# 9-de-8.net
KiCad netlist of a schematic drawn in EAGLE
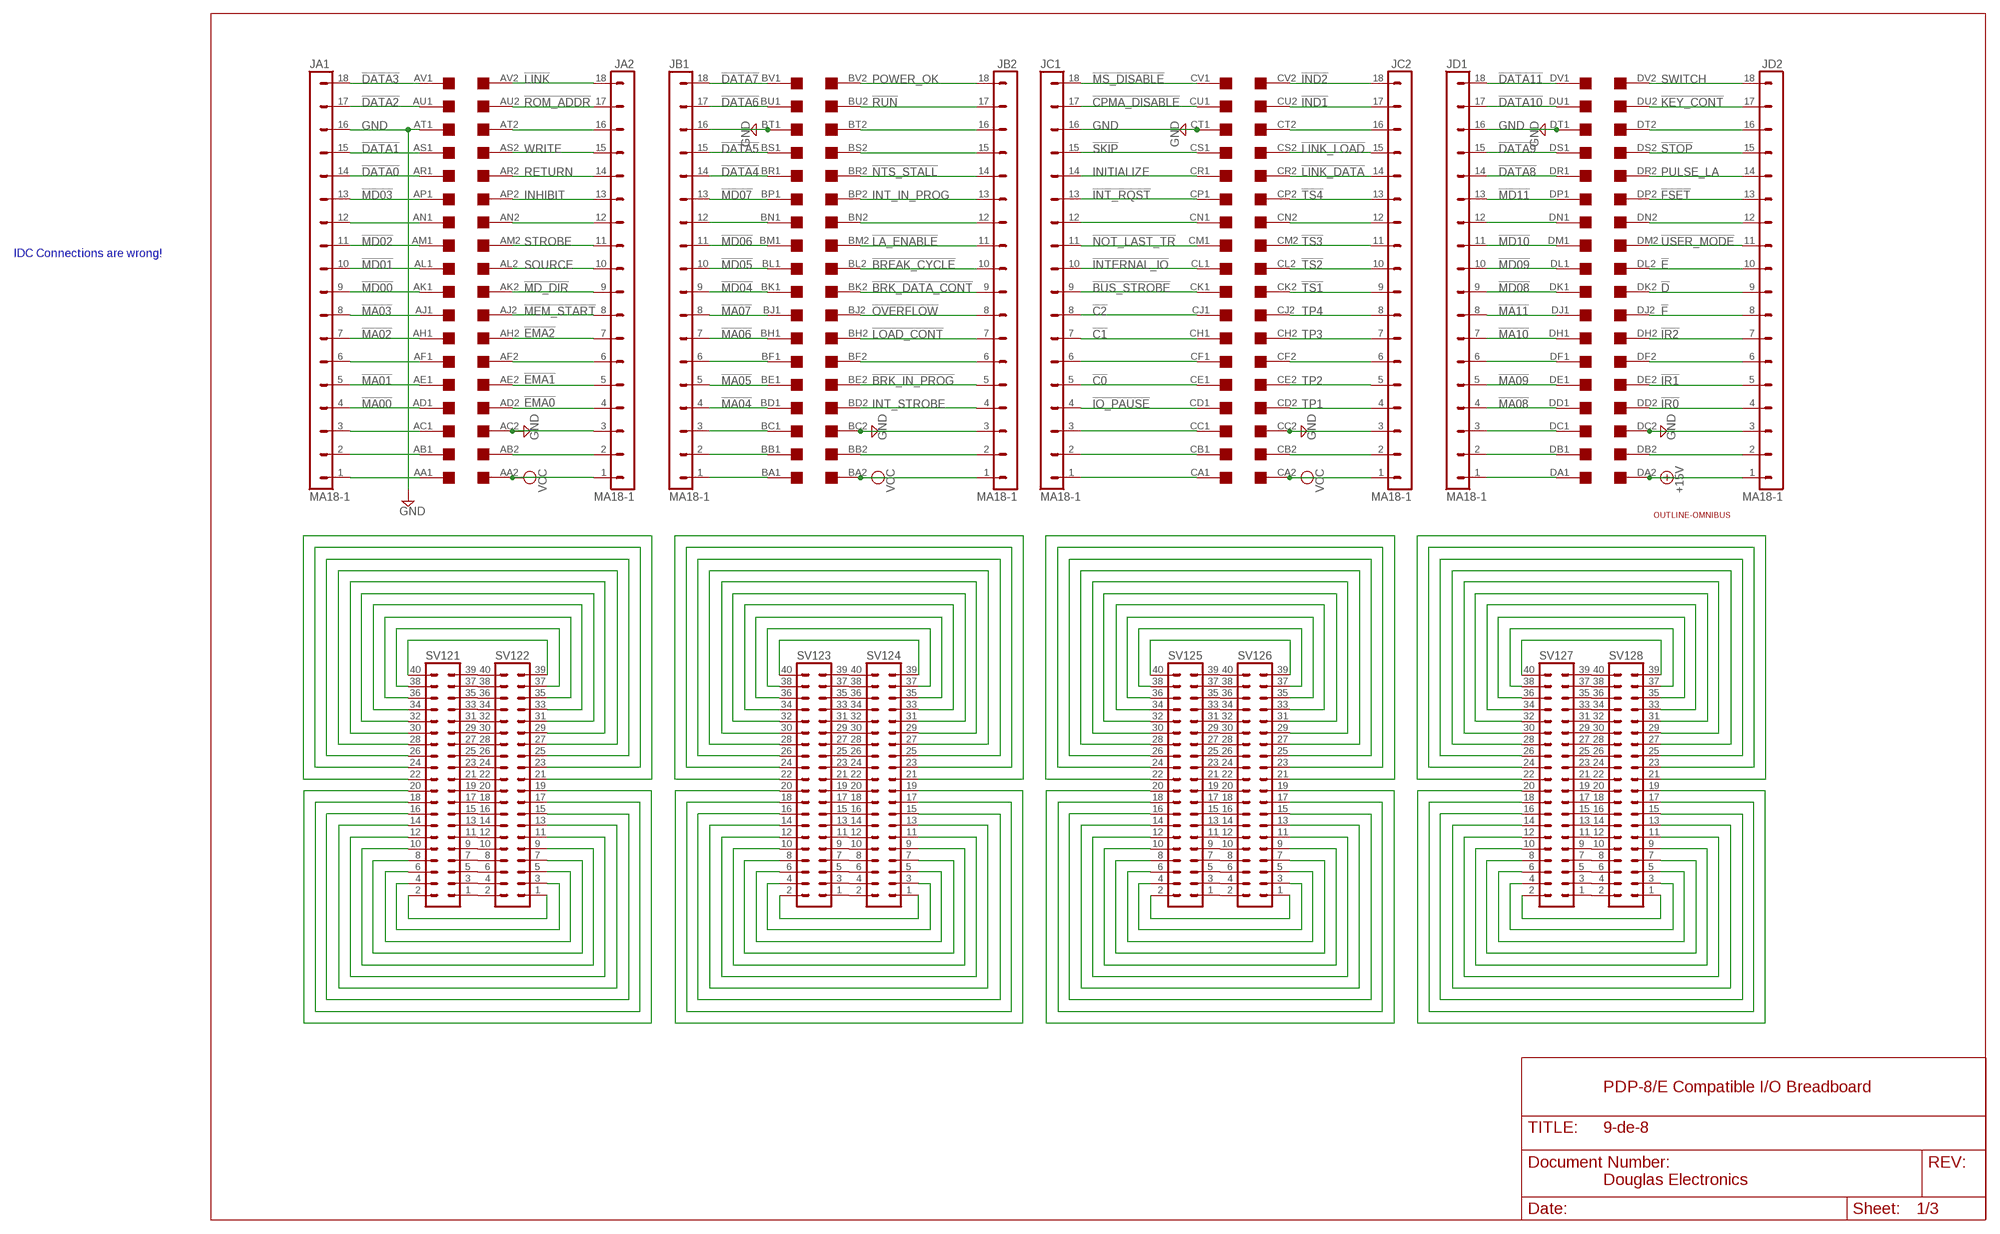
[diagram p0: schematic, sheet 1]
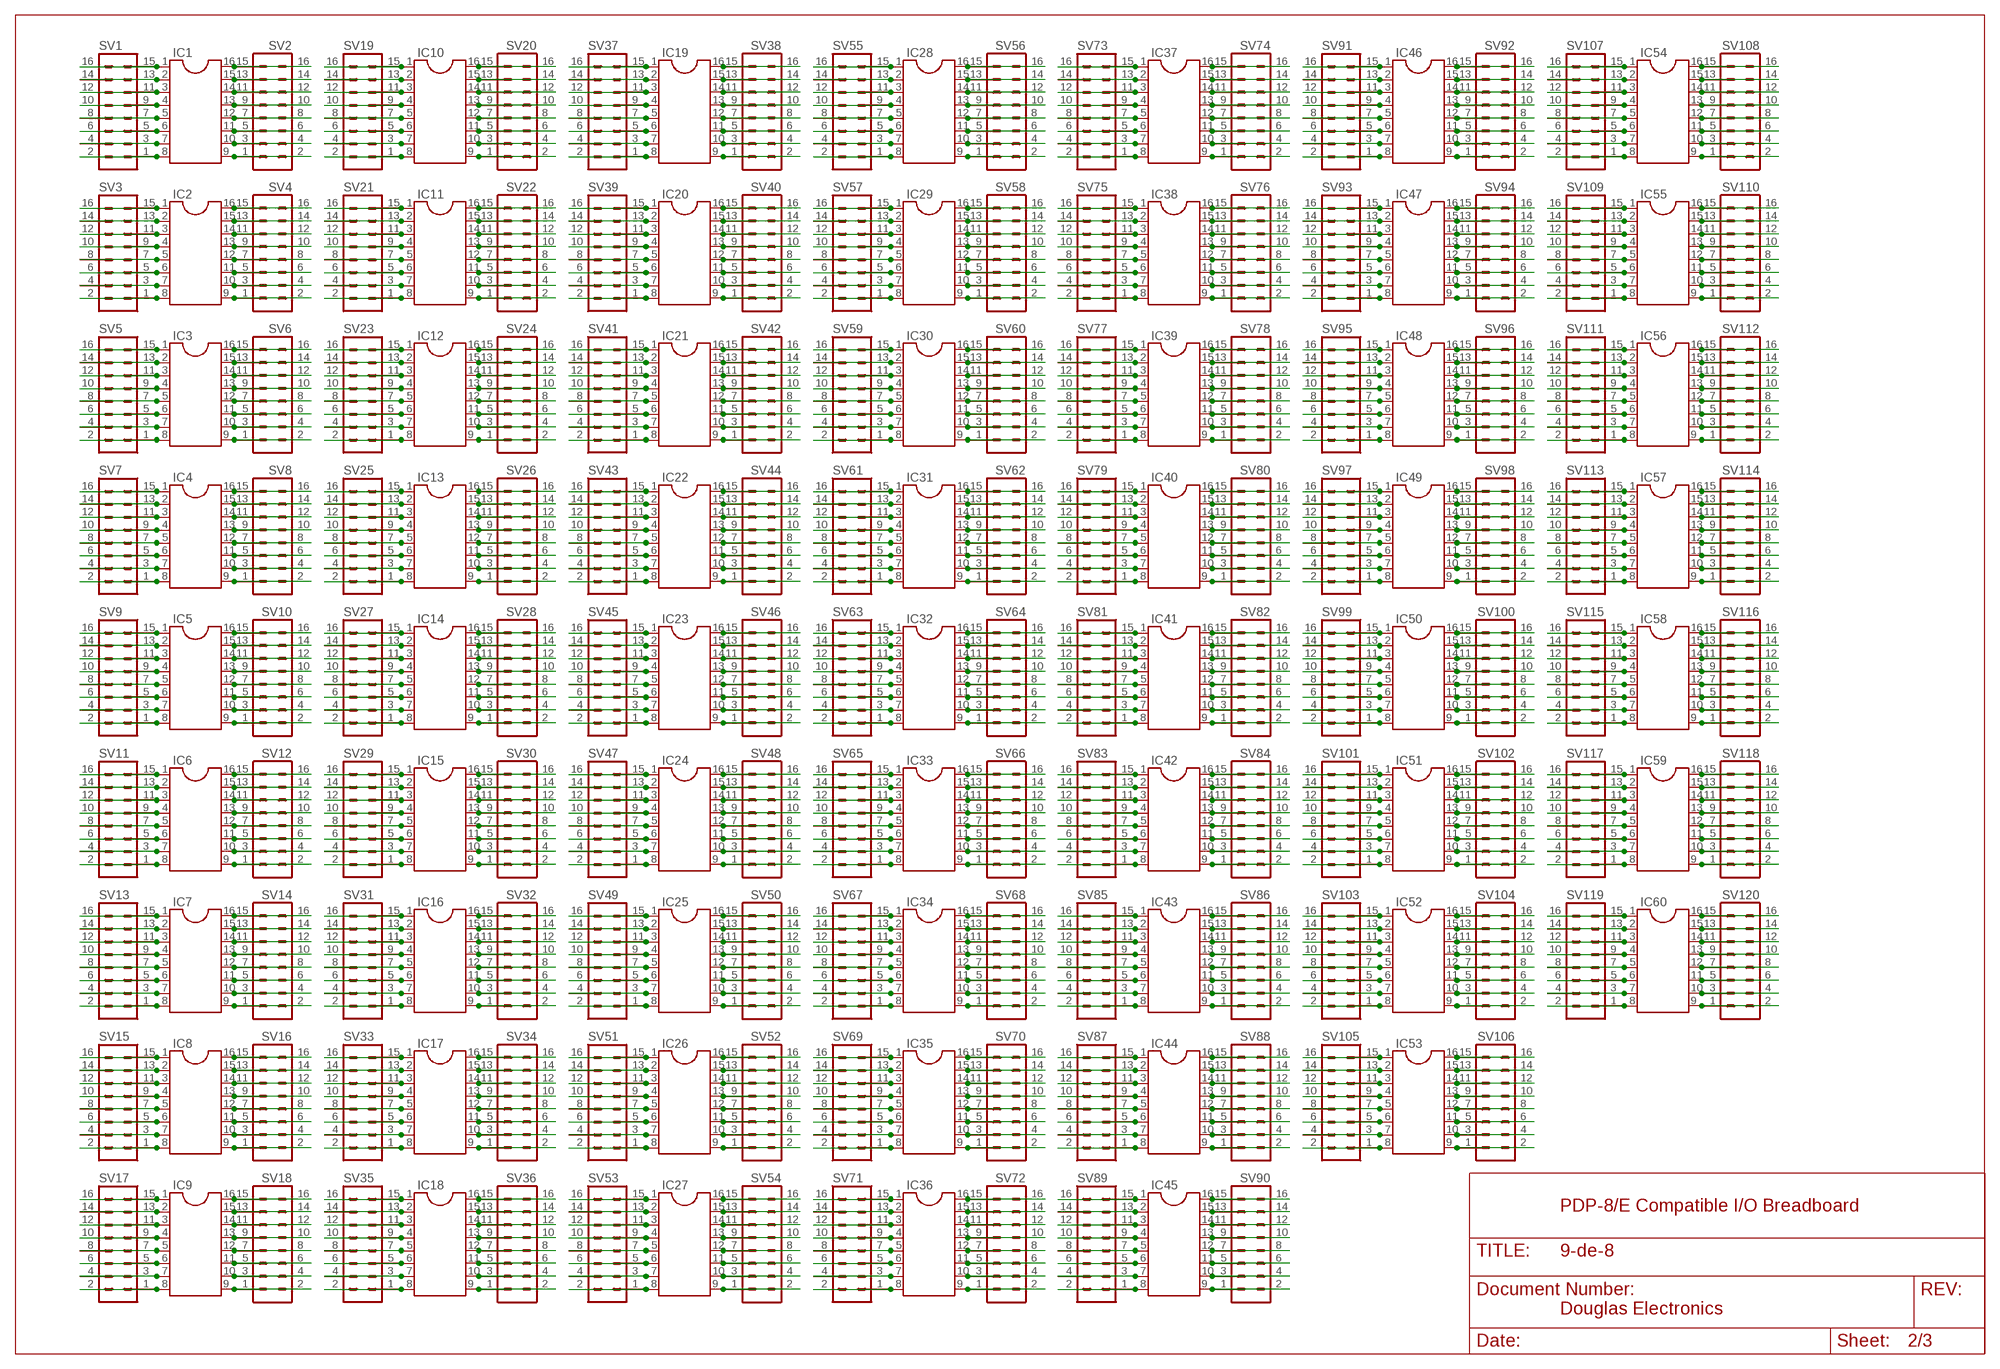
[diagram p1: schematic, sheet 2]
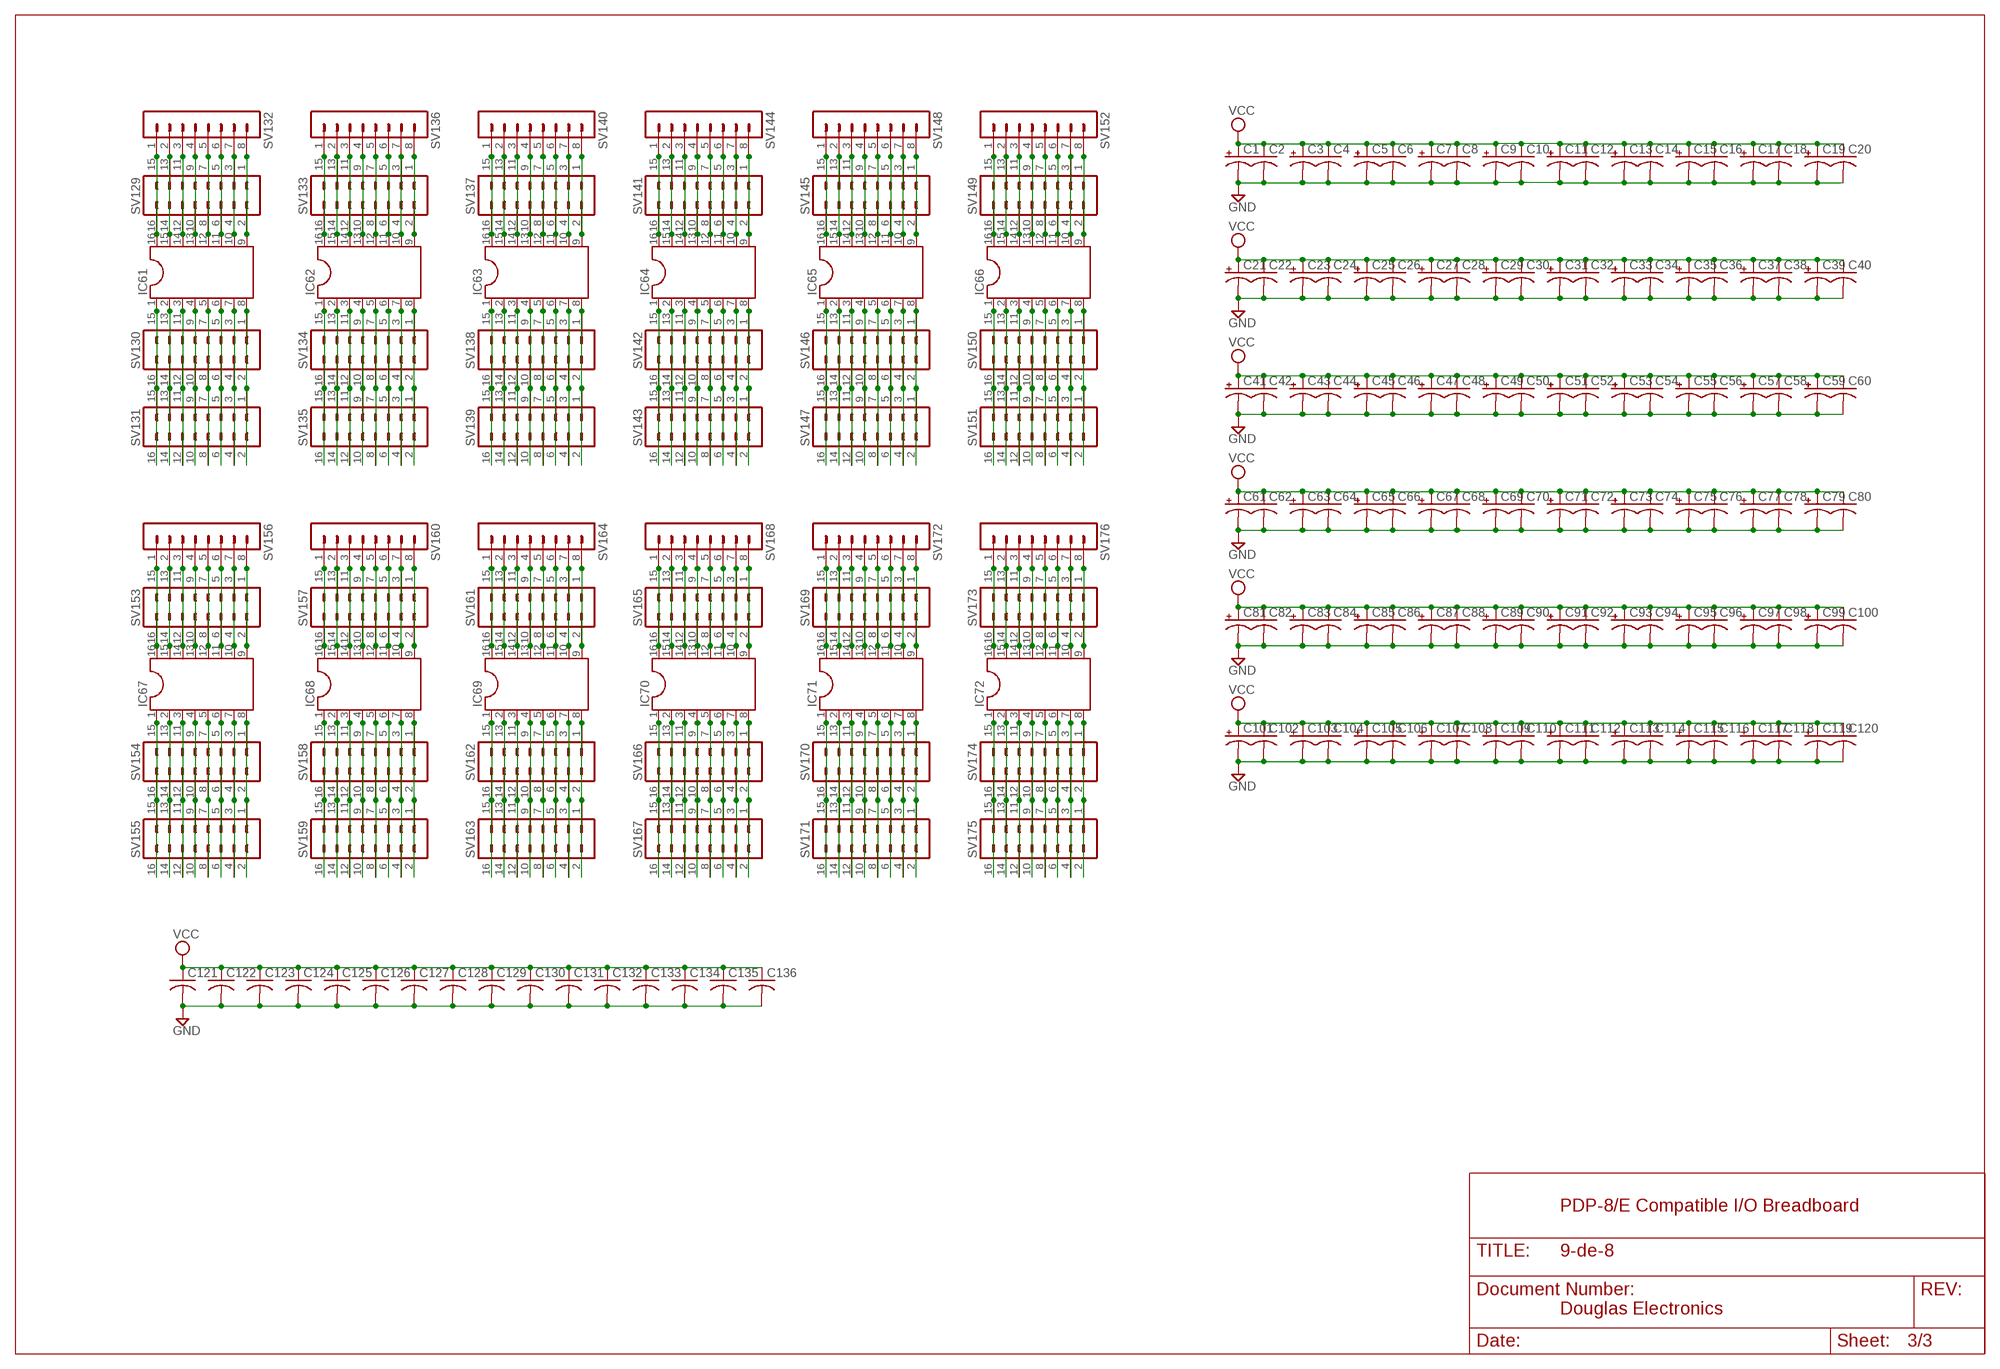
[diagram p2: schematic, sheet 3]

(export (version "E")
  (design (tool "Eeschema 10.0.6"))
  (components
    (comp (ref "JA1")
      (value "MA18-1")
      (footprint "eagle-import:MA18-1")
      (libsource (lib "eagle-import") (part "MA18-1"))
    )
    (comp (ref "JA2")
      (value "MA18-1")
      (footprint "eagle-import:MA18-1")
      (libsource (lib "eagle-import") (part "MA18-1"))
    )
    (comp (ref "JB1")
      (value "MA18-1")
      (footprint "eagle-import:MA18-1")
      (libsource (lib "eagle-import") (part "MA18-1"))
    )
    (comp (ref "JB2")
      (value "MA18-1")
      (footprint "eagle-import:MA18-1")
      (libsource (lib "eagle-import") (part "MA18-1"))
    )
    (comp (ref "JC1")
      (value "MA18-1")
      (footprint "eagle-import:MA18-1")
      (libsource (lib "eagle-import") (part "MA18-1"))
    )
    (comp (ref "JC2")
      (value "MA18-1")
      (footprint "eagle-import:MA18-1")
      (libsource (lib "eagle-import") (part "MA18-1"))
    )
    (comp (ref "JD1")
      (value "MA18-1")
      (footprint "eagle-import:MA18-1")
      (libsource (lib "eagle-import") (part "MA18-1"))
    )
    (comp (ref "JD2")
      (value "MA18-1")
      (footprint "eagle-import:MA18-1")
      (libsource (lib "eagle-import") (part "MA18-1"))
    )
    (comp (ref "SV121")
      (value "MA20-2")
      (footprint "eagle-import:MA20-2")
      (libsource (lib "eagle-import") (part "MA20-2"))
    )
    (comp (ref "SV122")
      (value "MA20-2")
      (footprint "eagle-import:MA20-2")
      (libsource (lib "eagle-import") (part "MA20-2"))
    )
    (comp (ref "SV123")
      (value "MA20-2")
      (footprint "eagle-import:MA20-2")
      (libsource (lib "eagle-import") (part "MA20-2"))
    )
    (comp (ref "SV124")
      (value "MA20-2")
      (footprint "eagle-import:MA20-2")
      (libsource (lib "eagle-import") (part "MA20-2"))
    )
    (comp (ref "SV125")
      (value "MA20-2")
      (footprint "eagle-import:MA20-2")
      (libsource (lib "eagle-import") (part "MA20-2"))
    )
    (comp (ref "SV126")
      (value "MA20-2")
      (footprint "eagle-import:MA20-2")
      (libsource (lib "eagle-import") (part "MA20-2"))
    )
    (comp (ref "SV127")
      (value "MA20-2")
      (footprint "eagle-import:MA20-2")
      (libsource (lib "eagle-import") (part "MA20-2"))
    )
    (comp (ref "SV128")
      (value "MA20-2")
      (footprint "eagle-import:MA20-2")
      (libsource (lib "eagle-import") (part "MA20-2"))
    )
    (comp (ref "U$1")
      (value "OUTLINE-OMNIBUS")
      (footprint "eagle-import:OMNIBUS")
      (libsource (lib "eagle-import") (part "OUTLINE-OMNIBUS"))
    )
    (comp (ref "U$2")
      (value "QUAD")
      (footprint "eagle-import:EDGE-CON8")
      (libsource (lib "eagle-import") (part "QUAD"))
    )
    (comp (ref "IC1")
      (value "DIL16")
      (footprint "eagle-import:DIL16")
      (libsource (lib "eagle-import") (part "DIL16"))
    )
    (comp (ref "IC2")
      (value "DIL16")
      (footprint "eagle-import:DIL16")
      (libsource (lib "eagle-import") (part "DIL16"))
    )
    (comp (ref "IC3")
      (value "DIL16")
      (footprint "eagle-import:DIL16")
      (libsource (lib "eagle-import") (part "DIL16"))
    )
    (comp (ref "IC4")
      (value "DIL16")
      (footprint "eagle-import:DIL16")
      (libsource (lib "eagle-import") (part "DIL16"))
    )
    (comp (ref "IC5")
      (value "DIL16")
      (footprint "eagle-import:DIL16")
      (libsource (lib "eagle-import") (part "DIL16"))
    )
    (comp (ref "IC6")
      (value "DIL16")
      (footprint "eagle-import:DIL16")
      (libsource (lib "eagle-import") (part "DIL16"))
    )
    (comp (ref "IC7")
      (value "DIL16")
      (footprint "eagle-import:DIL16")
      (libsource (lib "eagle-import") (part "DIL16"))
    )
    (comp (ref "IC8")
      (value "DIL16")
      (footprint "eagle-import:DIL16")
      (libsource (lib "eagle-import") (part "DIL16"))
    )
    (comp (ref "IC9")
      (value "DIL16")
      (footprint "eagle-import:DIL16")
      (libsource (lib "eagle-import") (part "DIL16"))
    )
    (comp (ref "IC10")
      (value "DIL16")
      (footprint "eagle-import:DIL16")
      (libsource (lib "eagle-import") (part "DIL16"))
    )
    (comp (ref "IC11")
      (value "DIL16")
      (footprint "eagle-import:DIL16")
      (libsource (lib "eagle-import") (part "DIL16"))
    )
    (comp (ref "IC12")
      (value "DIL16")
      (footprint "eagle-import:DIL16")
      (libsource (lib "eagle-import") (part "DIL16"))
    )
    (comp (ref "IC13")
      (value "DIL16")
      (footprint "eagle-import:DIL16")
      (libsource (lib "eagle-import") (part "DIL16"))
    )
    (comp (ref "IC14")
      (value "DIL16")
      (footprint "eagle-import:DIL16")
      (libsource (lib "eagle-import") (part "DIL16"))
    )
    (comp (ref "IC15")
      (value "DIL16")
      (footprint "eagle-import:DIL16")
      (libsource (lib "eagle-import") (part "DIL16"))
    )
    (comp (ref "IC16")
      (value "DIL16")
      (footprint "eagle-import:DIL16")
      (libsource (lib "eagle-import") (part "DIL16"))
    )
    (comp (ref "IC17")
      (value "DIL16")
      (footprint "eagle-import:DIL16")
      (libsource (lib "eagle-import") (part "DIL16"))
    )
    (comp (ref "IC18")
      (value "DIL16")
      (footprint "eagle-import:DIL16")
      (libsource (lib "eagle-import") (part "DIL16"))
    )
    (comp (ref "IC19")
      (value "DIL16")
      (footprint "eagle-import:DIL16")
      (libsource (lib "eagle-import") (part "DIL16"))
    )
    (comp (ref "IC20")
      (value "DIL16")
      (footprint "eagle-import:DIL16")
      (libsource (lib "eagle-import") (part "DIL16"))
    )
    (comp (ref "IC21")
      (value "DIL16")
      (footprint "eagle-import:DIL16")
      (libsource (lib "eagle-import") (part "DIL16"))
    )
    (comp (ref "IC22")
      (value "DIL16")
      (footprint "eagle-import:DIL16")
      (libsource (lib "eagle-import") (part "DIL16"))
    )
    (comp (ref "IC23")
      (value "DIL16")
      (footprint "eagle-import:DIL16")
      (libsource (lib "eagle-import") (part "DIL16"))
    )
    (comp (ref "IC24")
      (value "DIL16")
      (footprint "eagle-import:DIL16")
      (libsource (lib "eagle-import") (part "DIL16"))
    )
    (comp (ref "IC25")
      (value "DIL16")
      (footprint "eagle-import:DIL16")
      (libsource (lib "eagle-import") (part "DIL16"))
    )
    (comp (ref "IC26")
      (value "DIL16")
      (footprint "eagle-import:DIL16")
      (libsource (lib "eagle-import") (part "DIL16"))
    )
    (comp (ref "IC27")
      (value "DIL16")
      (footprint "eagle-import:DIL16")
      (libsource (lib "eagle-import") (part "DIL16"))
    )
    (comp (ref "IC28")
      (value "DIL16")
      (footprint "eagle-import:DIL16")
      (libsource (lib "eagle-import") (part "DIL16"))
    )
    (comp (ref "IC29")
      (value "DIL16")
      (footprint "eagle-import:DIL16")
      (libsource (lib "eagle-import") (part "DIL16"))
    )
    (comp (ref "IC30")
      (value "DIL16")
      (footprint "eagle-import:DIL16")
      (libsource (lib "eagle-import") (part "DIL16"))
    )
    (comp (ref "IC31")
      (value "DIL16")
      (footprint "eagle-import:DIL16")
      (libsource (lib "eagle-import") (part "DIL16"))
    )
    (comp (ref "IC32")
      (value "DIL16")
      (footprint "eagle-import:DIL16")
      (libsource (lib "eagle-import") (part "DIL16"))
    )
    (comp (ref "IC33")
      (value "DIL16")
      (footprint "eagle-import:DIL16")
      (libsource (lib "eagle-import") (part "DIL16"))
    )
    (comp (ref "IC34")
      (value "DIL16")
      (footprint "eagle-import:DIL16")
      (libsource (lib "eagle-import") (part "DIL16"))
    )
    (comp (ref "IC35")
      (value "DIL16")
      (footprint "eagle-import:DIL16")
      (libsource (lib "eagle-import") (part "DIL16"))
    )
    (comp (ref "IC36")
      (value "DIL16")
      (footprint "eagle-import:DIL16")
      (libsource (lib "eagle-import") (part "DIL16"))
    )
    (comp (ref "IC37")
      (value "DIL16")
      (footprint "eagle-import:DIL16")
      (libsource (lib "eagle-import") (part "DIL16"))
    )
    (comp (ref "IC38")
      (value "DIL16")
      (footprint "eagle-import:DIL16")
      (libsource (lib "eagle-import") (part "DIL16"))
    )
    (comp (ref "IC39")
      (value "DIL16")
      (footprint "eagle-import:DIL16")
      (libsource (lib "eagle-import") (part "DIL16"))
    )
    (comp (ref "IC40")
      (value "DIL16")
      (footprint "eagle-import:DIL16")
      (libsource (lib "eagle-import") (part "DIL16"))
    )
    (comp (ref "IC41")
      (value "DIL16")
      (footprint "eagle-import:DIL16")
      (libsource (lib "eagle-import") (part "DIL16"))
    )
    (comp (ref "IC42")
      (value "DIL16")
      (footprint "eagle-import:DIL16")
      (libsource (lib "eagle-import") (part "DIL16"))
    )
    (comp (ref "IC43")
      (value "DIL16")
      (footprint "eagle-import:DIL16")
      (libsource (lib "eagle-import") (part "DIL16"))
    )
    (comp (ref "IC44")
      (value "DIL16")
      (footprint "eagle-import:DIL16")
      (libsource (lib "eagle-import") (part "DIL16"))
    )
    (comp (ref "IC45")
      (value "DIL16")
      (footprint "eagle-import:DIL16")
      (libsource (lib "eagle-import") (part "DIL16"))
    )
    (comp (ref "IC46")
      (value "DIL16")
      (footprint "eagle-import:DIL16")
      (libsource (lib "eagle-import") (part "DIL16"))
    )
    (comp (ref "IC47")
      (value "DIL16")
      (footprint "eagle-import:DIL16")
      (libsource (lib "eagle-import") (part "DIL16"))
    )
    (comp (ref "IC48")
      (value "DIL16")
      (footprint "eagle-import:DIL16")
      (libsource (lib "eagle-import") (part "DIL16"))
    )
    (comp (ref "IC49")
      (value "DIL16")
      (footprint "eagle-import:DIL16")
      (libsource (lib "eagle-import") (part "DIL16"))
    )
    (comp (ref "IC50")
      (value "DIL16")
      (footprint "eagle-import:DIL16")
      (libsource (lib "eagle-import") (part "DIL16"))
    )
    (comp (ref "IC51")
      (value "DIL16")
      (footprint "eagle-import:DIL16")
      (libsource (lib "eagle-import") (part "DIL16"))
    )
    (comp (ref "IC52")
      (value "DIL16")
      (footprint "eagle-import:DIL16")
      (libsource (lib "eagle-import") (part "DIL16"))
    )
    (comp (ref "IC53")
      (value "DIL16")
      (footprint "eagle-import:DIL16")
      (libsource (lib "eagle-import") (part "DIL16"))
    )
    (comp (ref "IC54")
      (value "DIL16")
      (footprint "eagle-import:DIL16")
      (libsource (lib "eagle-import") (part "DIL16"))
    )
    (comp (ref "IC55")
      (value "DIL16")
      (footprint "eagle-import:DIL16")
      (libsource (lib "eagle-import") (part "DIL16"))
    )
    (comp (ref "IC56")
      (value "DIL16")
      (footprint "eagle-import:DIL16")
      (libsource (lib "eagle-import") (part "DIL16"))
    )
    (comp (ref "IC57")
      (value "DIL16")
      (footprint "eagle-import:DIL16")
      (libsource (lib "eagle-import") (part "DIL16"))
    )
    (comp (ref "IC58")
      (value "DIL16")
      (footprint "eagle-import:DIL16")
      (libsource (lib "eagle-import") (part "DIL16"))
    )
    (comp (ref "IC59")
      (value "DIL16")
      (footprint "eagle-import:DIL16")
      (libsource (lib "eagle-import") (part "DIL16"))
    )
    (comp (ref "IC60")
      (value "DIL16")
      (footprint "eagle-import:DIL16")
      (libsource (lib "eagle-import") (part "DIL16"))
    )
    (comp (ref "SV1")
      (value "MA08-2")
      (footprint "eagle-import:MA08-2")
      (libsource (lib "eagle-import") (part "MA08-2"))
    )
    (comp (ref "SV2")
      (value "MA08-2")
      (footprint "eagle-import:MA08-2")
      (libsource (lib "eagle-import") (part "MA08-2"))
    )
    (comp (ref "SV3")
      (value "MA08-2")
      (footprint "eagle-import:MA08-2")
      (libsource (lib "eagle-import") (part "MA08-2"))
    )
    (comp (ref "SV4")
      (value "MA08-2")
      (footprint "eagle-import:MA08-2")
      (libsource (lib "eagle-import") (part "MA08-2"))
    )
    (comp (ref "SV5")
      (value "MA08-2")
      (footprint "eagle-import:MA08-2")
      (libsource (lib "eagle-import") (part "MA08-2"))
    )
    (comp (ref "SV6")
      (value "MA08-2")
      (footprint "eagle-import:MA08-2")
      (libsource (lib "eagle-import") (part "MA08-2"))
    )
    (comp (ref "SV7")
      (value "MA08-2")
      (footprint "eagle-import:MA08-2")
      (libsource (lib "eagle-import") (part "MA08-2"))
    )
    (comp (ref "SV8")
      (value "MA08-2")
      (footprint "eagle-import:MA08-2")
      (libsource (lib "eagle-import") (part "MA08-2"))
    )
    (comp (ref "SV9")
      (value "MA08-2")
      (footprint "eagle-import:MA08-2")
      (libsource (lib "eagle-import") (part "MA08-2"))
    )
    (comp (ref "SV10")
      (value "MA08-2")
      (footprint "eagle-import:MA08-2")
      (libsource (lib "eagle-import") (part "MA08-2"))
    )
    (comp (ref "SV11")
      (value "MA08-2")
      (footprint "eagle-import:MA08-2")
      (libsource (lib "eagle-import") (part "MA08-2"))
    )
    (comp (ref "SV12")
      (value "MA08-2")
      (footprint "eagle-import:MA08-2")
      (libsource (lib "eagle-import") (part "MA08-2"))
    )
    (comp (ref "SV13")
      (value "MA08-2")
      (footprint "eagle-import:MA08-2")
      (libsource (lib "eagle-import") (part "MA08-2"))
    )
    (comp (ref "SV14")
      (value "MA08-2")
      (footprint "eagle-import:MA08-2")
      (libsource (lib "eagle-import") (part "MA08-2"))
    )
    (comp (ref "SV15")
      (value "MA08-2")
      (footprint "eagle-import:MA08-2")
      (libsource (lib "eagle-import") (part "MA08-2"))
    )
    (comp (ref "SV16")
      (value "MA08-2")
      (footprint "eagle-import:MA08-2")
      (libsource (lib "eagle-import") (part "MA08-2"))
    )
    (comp (ref "SV17")
      (value "MA08-2")
      (footprint "eagle-import:MA08-2")
      (libsource (lib "eagle-import") (part "MA08-2"))
    )
    (comp (ref "SV18")
      (value "MA08-2")
      (footprint "eagle-import:MA08-2")
      (libsource (lib "eagle-import") (part "MA08-2"))
    )
    (comp (ref "SV19")
      (value "MA08-2")
      (footprint "eagle-import:MA08-2")
      (libsource (lib "eagle-import") (part "MA08-2"))
    )
    (comp (ref "SV20")
      (value "MA08-2")
      (footprint "eagle-import:MA08-2")
      (libsource (lib "eagle-import") (part "MA08-2"))
    )
    (comp (ref "SV21")
      (value "MA08-2")
      (footprint "eagle-import:MA08-2")
      (libsource (lib "eagle-import") (part "MA08-2"))
    )
    (comp (ref "SV22")
      (value "MA08-2")
      (footprint "eagle-import:MA08-2")
      (libsource (lib "eagle-import") (part "MA08-2"))
    )
    (comp (ref "SV23")
      (value "MA08-2")
      (footprint "eagle-import:MA08-2")
      (libsource (lib "eagle-import") (part "MA08-2"))
    )
    (comp (ref "SV24")
      (value "MA08-2")
      (footprint "eagle-import:MA08-2")
      (libsource (lib "eagle-import") (part "MA08-2"))
    )
    (comp (ref "SV25")
      (value "MA08-2")
      (footprint "eagle-import:MA08-2")
      (libsource (lib "eagle-import") (part "MA08-2"))
    )
    (comp (ref "SV26")
      (value "MA08-2")
      (footprint "eagle-import:MA08-2")
      (libsource (lib "eagle-import") (part "MA08-2"))
    )
    (comp (ref "SV27")
      (value "MA08-2")
      (footprint "eagle-import:MA08-2")
      (libsource (lib "eagle-import") (part "MA08-2"))
    )
    (comp (ref "SV28")
      (value "MA08-2")
      (footprint "eagle-import:MA08-2")
      (libsource (lib "eagle-import") (part "MA08-2"))
    )
    (comp (ref "SV29")
      (value "MA08-2")
      (footprint "eagle-import:MA08-2")
      (libsource (lib "eagle-import") (part "MA08-2"))
    )
    (comp (ref "SV30")
      (value "MA08-2")
      (footprint "eagle-import:MA08-2")
      (libsource (lib "eagle-import") (part "MA08-2"))
    )
    (comp (ref "SV31")
      (value "MA08-2")
      (footprint "eagle-import:MA08-2")
      (libsource (lib "eagle-import") (part "MA08-2"))
    )
    (comp (ref "SV32")
      (value "MA08-2")
      (footprint "eagle-import:MA08-2")
      (libsource (lib "eagle-import") (part "MA08-2"))
    )
    (comp (ref "SV33")
      (value "MA08-2")
      (footprint "eagle-import:MA08-2")
      (libsource (lib "eagle-import") (part "MA08-2"))
    )
    (comp (ref "SV34")
      (value "MA08-2")
      (footprint "eagle-import:MA08-2")
      (libsource (lib "eagle-import") (part "MA08-2"))
    )
    (comp (ref "SV35")
      (value "MA08-2")
      (footprint "eagle-import:MA08-2")
      (libsource (lib "eagle-import") (part "MA08-2"))
    )
    (comp (ref "SV36")
      (value "MA08-2")
      (footprint "eagle-import:MA08-2")
      (libsource (lib "eagle-import") (part "MA08-2"))
    )
    (comp (ref "SV37")
      (value "MA08-2")
      (footprint "eagle-import:MA08-2")
      (libsource (lib "eagle-import") (part "MA08-2"))
    )
    (comp (ref "SV38")
      (value "MA08-2")
      (footprint "eagle-import:MA08-2")
      (libsource (lib "eagle-import") (part "MA08-2"))
    )
    (comp (ref "SV39")
      (value "MA08-2")
      (footprint "eagle-import:MA08-2")
      (libsource (lib "eagle-import") (part "MA08-2"))
    )
    (comp (ref "SV40")
      (value "MA08-2")
      (footprint "eagle-import:MA08-2")
      (libsource (lib "eagle-import") (part "MA08-2"))
    )
    (comp (ref "SV41")
      (value "MA08-2")
      (footprint "eagle-import:MA08-2")
      (libsource (lib "eagle-import") (part "MA08-2"))
    )
    (comp (ref "SV42")
      (value "MA08-2")
      (footprint "eagle-import:MA08-2")
      (libsource (lib "eagle-import") (part "MA08-2"))
    )
    (comp (ref "SV43")
      (value "MA08-2")
      (footprint "eagle-import:MA08-2")
      (libsource (lib "eagle-import") (part "MA08-2"))
    )
    (comp (ref "SV44")
      (value "MA08-2")
      (footprint "eagle-import:MA08-2")
      (libsource (lib "eagle-import") (part "MA08-2"))
    )
    (comp (ref "SV45")
      (value "MA08-2")
      (footprint "eagle-import:MA08-2")
      (libsource (lib "eagle-import") (part "MA08-2"))
    )
    (comp (ref "SV46")
      (value "MA08-2")
      (footprint "eagle-import:MA08-2")
      (libsource (lib "eagle-import") (part "MA08-2"))
    )
    (comp (ref "SV47")
      (value "MA08-2")
      (footprint "eagle-import:MA08-2")
      (libsource (lib "eagle-import") (part "MA08-2"))
    )
    (comp (ref "SV48")
      (value "MA08-2")
      (footprint "eagle-import:MA08-2")
      (libsource (lib "eagle-import") (part "MA08-2"))
    )
    (comp (ref "SV49")
      (value "MA08-2")
      (footprint "eagle-import:MA08-2")
      (libsource (lib "eagle-import") (part "MA08-2"))
    )
    (comp (ref "SV50")
      (value "MA08-2")
      (footprint "eagle-import:MA08-2")
      (libsource (lib "eagle-import") (part "MA08-2"))
    )
    (comp (ref "SV51")
      (value "MA08-2")
      (footprint "eagle-import:MA08-2")
      (libsource (lib "eagle-import") (part "MA08-2"))
    )
    (comp (ref "SV52")
      (value "MA08-2")
      (footprint "eagle-import:MA08-2")
      (libsource (lib "eagle-import") (part "MA08-2"))
    )
    (comp (ref "SV53")
      (value "MA08-2")
      (footprint "eagle-import:MA08-2")
      (libsource (lib "eagle-import") (part "MA08-2"))
    )
    (comp (ref "SV54")
      (value "MA08-2")
      (footprint "eagle-import:MA08-2")
      (libsource (lib "eagle-import") (part "MA08-2"))
    )
    (comp (ref "SV55")
      (value "MA08-2")
      (footprint "eagle-import:MA08-2")
      (libsource (lib "eagle-import") (part "MA08-2"))
    )
    (comp (ref "SV56")
      (value "MA08-2")
      (footprint "eagle-import:MA08-2")
      (libsource (lib "eagle-import") (part "MA08-2"))
    )
    (comp (ref "SV57")
      (value "MA08-2")
      (footprint "eagle-import:MA08-2")
      (libsource (lib "eagle-import") (part "MA08-2"))
    )
    (comp (ref "SV58")
      (value "MA08-2")
      (footprint "eagle-import:MA08-2")
      (libsource (lib "eagle-import") (part "MA08-2"))
    )
    (comp (ref "SV59")
      (value "MA08-2")
      (footprint "eagle-import:MA08-2")
      (libsource (lib "eagle-import") (part "MA08-2"))
    )
    (comp (ref "SV60")
      (value "MA08-2")
      (footprint "eagle-import:MA08-2")
      (libsource (lib "eagle-import") (part "MA08-2"))
    )
    (comp (ref "SV61")
      (value "MA08-2")
      (footprint "eagle-import:MA08-2")
      (libsource (lib "eagle-import") (part "MA08-2"))
    )
    (comp (ref "SV62")
      (value "MA08-2")
      (footprint "eagle-import:MA08-2")
      (libsource (lib "eagle-import") (part "MA08-2"))
    )
    (comp (ref "SV63")
      (value "MA08-2")
      (footprint "eagle-import:MA08-2")
      (libsource (lib "eagle-import") (part "MA08-2"))
    )
    (comp (ref "SV64")
      (value "MA08-2")
      (footprint "eagle-import:MA08-2")
      (libsource (lib "eagle-import") (part "MA08-2"))
    )
    (comp (ref "SV65")
      (value "MA08-2")
      (footprint "eagle-import:MA08-2")
      (libsource (lib "eagle-import") (part "MA08-2"))
    )
    (comp (ref "SV66")
      (value "MA08-2")
      (footprint "eagle-import:MA08-2")
      (libsource (lib "eagle-import") (part "MA08-2"))
    )
    (comp (ref "SV67")
      (value "MA08-2")
      (footprint "eagle-import:MA08-2")
      (libsource (lib "eagle-import") (part "MA08-2"))
    )
    (comp (ref "SV68")
      (value "MA08-2")
      (footprint "eagle-import:MA08-2")
      (libsource (lib "eagle-import") (part "MA08-2"))
    )
    (comp (ref "SV69")
      (value "MA08-2")
      (footprint "eagle-import:MA08-2")
      (libsource (lib "eagle-import") (part "MA08-2"))
    )
    (comp (ref "SV70")
      (value "MA08-2")
      (footprint "eagle-import:MA08-2")
      (libsource (lib "eagle-import") (part "MA08-2"))
    )
    (comp (ref "SV71")
      (value "MA08-2")
      (footprint "eagle-import:MA08-2")
      (libsource (lib "eagle-import") (part "MA08-2"))
    )
    (comp (ref "SV72")
      (value "MA08-2")
      (footprint "eagle-import:MA08-2")
      (libsource (lib "eagle-import") (part "MA08-2"))
    )
    (comp (ref "SV73")
      (value "MA08-2")
      (footprint "eagle-import:MA08-2")
      (libsource (lib "eagle-import") (part "MA08-2"))
    )
    (comp (ref "SV74")
      (value "MA08-2")
      (footprint "eagle-import:MA08-2")
      (libsource (lib "eagle-import") (part "MA08-2"))
    )
    (comp (ref "SV75")
      (value "MA08-2")
      (footprint "eagle-import:MA08-2")
      (libsource (lib "eagle-import") (part "MA08-2"))
    )
    (comp (ref "SV76")
      (value "MA08-2")
      (footprint "eagle-import:MA08-2")
      (libsource (lib "eagle-import") (part "MA08-2"))
    )
    (comp (ref "SV77")
      (value "MA08-2")
      (footprint "eagle-import:MA08-2")
      (libsource (lib "eagle-import") (part "MA08-2"))
    )
    (comp (ref "SV78")
      (value "MA08-2")
      (footprint "eagle-import:MA08-2")
      (libsource (lib "eagle-import") (part "MA08-2"))
    )
    (comp (ref "SV79")
      (value "MA08-2")
      (footprint "eagle-import:MA08-2")
      (libsource (lib "eagle-import") (part "MA08-2"))
    )
    (comp (ref "SV80")
      (value "MA08-2")
      (footprint "eagle-import:MA08-2")
      (libsource (lib "eagle-import") (part "MA08-2"))
    )
    (comp (ref "SV81")
      (value "MA08-2")
      (footprint "eagle-import:MA08-2")
      (libsource (lib "eagle-import") (part "MA08-2"))
    )
    (comp (ref "SV82")
      (value "MA08-2")
      (footprint "eagle-import:MA08-2")
      (libsource (lib "eagle-import") (part "MA08-2"))
    )
    (comp (ref "SV83")
      (value "MA08-2")
      (footprint "eagle-import:MA08-2")
      (libsource (lib "eagle-import") (part "MA08-2"))
    )
    (comp (ref "SV84")
      (value "MA08-2")
      (footprint "eagle-import:MA08-2")
      (libsource (lib "eagle-import") (part "MA08-2"))
    )
    (comp (ref "SV85")
      (value "MA08-2")
      (footprint "eagle-import:MA08-2")
      (libsource (lib "eagle-import") (part "MA08-2"))
    )
    (comp (ref "SV86")
      (value "MA08-2")
      (footprint "eagle-import:MA08-2")
      (libsource (lib "eagle-import") (part "MA08-2"))
    )
    (comp (ref "SV87")
      (value "MA08-2")
      (footprint "eagle-import:MA08-2")
      (libsource (lib "eagle-import") (part "MA08-2"))
    )
    (comp (ref "SV88")
      (value "MA08-2")
      (footprint "eagle-import:MA08-2")
      (libsource (lib "eagle-import") (part "MA08-2"))
    )
    (comp (ref "SV89")
      (value "MA08-2")
      (footprint "eagle-import:MA08-2")
      (libsource (lib "eagle-import") (part "MA08-2"))
    )
    (comp (ref "SV90")
      (value "MA08-2")
      (footprint "eagle-import:MA08-2")
      (libsource (lib "eagle-import") (part "MA08-2"))
    )
    (comp (ref "SV91")
      (value "MA08-2")
      (footprint "eagle-import:MA08-2")
      (libsource (lib "eagle-import") (part "MA08-2"))
    )
    (comp (ref "SV92")
      (value "MA08-2")
      (footprint "eagle-import:MA08-2")
      (libsource (lib "eagle-import") (part "MA08-2"))
    )
    (comp (ref "SV93")
      (value "MA08-2")
      (footprint "eagle-import:MA08-2")
      (libsource (lib "eagle-import") (part "MA08-2"))
    )
    (comp (ref "SV94")
      (value "MA08-2")
      (footprint "eagle-import:MA08-2")
      (libsource (lib "eagle-import") (part "MA08-2"))
    )
    (comp (ref "SV95")
      (value "MA08-2")
      (footprint "eagle-import:MA08-2")
      (libsource (lib "eagle-import") (part "MA08-2"))
    )
    (comp (ref "SV96")
      (value "MA08-2")
      (footprint "eagle-import:MA08-2")
      (libsource (lib "eagle-import") (part "MA08-2"))
    )
    (comp (ref "SV97")
      (value "MA08-2")
      (footprint "eagle-import:MA08-2")
      (libsource (lib "eagle-import") (part "MA08-2"))
    )
    (comp (ref "SV98")
      (value "MA08-2")
      (footprint "eagle-import:MA08-2")
      (libsource (lib "eagle-import") (part "MA08-2"))
    )
    (comp (ref "SV99")
      (value "MA08-2")
      (footprint "eagle-import:MA08-2")
      (libsource (lib "eagle-import") (part "MA08-2"))
    )
    (comp (ref "SV100")
      (value "MA08-2")
      (footprint "eagle-import:MA08-2")
      (libsource (lib "eagle-import") (part "MA08-2"))
    )
    (comp (ref "SV101")
      (value "MA08-2")
      (footprint "eagle-import:MA08-2")
      (libsource (lib "eagle-import") (part "MA08-2"))
    )
    (comp (ref "SV102")
      (value "MA08-2")
      (footprint "eagle-import:MA08-2")
      (libsource (lib "eagle-import") (part "MA08-2"))
    )
    (comp (ref "SV103")
      (value "MA08-2")
      (footprint "eagle-import:MA08-2")
      (libsource (lib "eagle-import") (part "MA08-2"))
    )
    (comp (ref "SV104")
      (value "MA08-2")
      (footprint "eagle-import:MA08-2")
      (libsource (lib "eagle-import") (part "MA08-2"))
    )
    (comp (ref "SV105")
      (value "MA08-2")
      (footprint "eagle-import:MA08-2")
      (libsource (lib "eagle-import") (part "MA08-2"))
    )
    (comp (ref "SV106")
      (value "MA08-2")
      (footprint "eagle-import:MA08-2")
      (libsource (lib "eagle-import") (part "MA08-2"))
    )
    (comp (ref "SV107")
      (value "MA08-2")
      (footprint "eagle-import:MA08-2")
      (libsource (lib "eagle-import") (part "MA08-2"))
    )
    (comp (ref "SV108")
      (value "MA08-2")
      (footprint "eagle-import:MA08-2")
      (libsource (lib "eagle-import") (part "MA08-2"))
    )
    (comp (ref "SV109")
      (value "MA08-2")
      (footprint "eagle-import:MA08-2")
      (libsource (lib "eagle-import") (part "MA08-2"))
    )
    (comp (ref "SV110")
      (value "MA08-2")
      (footprint "eagle-import:MA08-2")
      (libsource (lib "eagle-import") (part "MA08-2"))
    )
    (comp (ref "SV111")
      (value "MA08-2")
      (footprint "eagle-import:MA08-2")
      (libsource (lib "eagle-import") (part "MA08-2"))
    )
    (comp (ref "SV112")
      (value "MA08-2")
      (footprint "eagle-import:MA08-2")
      (libsource (lib "eagle-import") (part "MA08-2"))
    )
    (comp (ref "SV113")
      (value "MA08-2")
      (footprint "eagle-import:MA08-2")
      (libsource (lib "eagle-import") (part "MA08-2"))
    )
    (comp (ref "SV114")
      (value "MA08-2")
      (footprint "eagle-import:MA08-2")
      (libsource (lib "eagle-import") (part "MA08-2"))
    )
    (comp (ref "SV115")
      (value "MA08-2")
      (footprint "eagle-import:MA08-2")
      (libsource (lib "eagle-import") (part "MA08-2"))
    )
    (comp (ref "SV116")
      (value "MA08-2")
      (footprint "eagle-import:MA08-2")
      (libsource (lib "eagle-import") (part "MA08-2"))
    )
    (comp (ref "SV117")
      (value "MA08-2")
      (footprint "eagle-import:MA08-2")
      (libsource (lib "eagle-import") (part "MA08-2"))
    )
    (comp (ref "SV118")
      (value "MA08-2")
      (footprint "eagle-import:MA08-2")
      (libsource (lib "eagle-import") (part "MA08-2"))
    )
    (comp (ref "SV119")
      (value "MA08-2")
      (footprint "eagle-import:MA08-2")
      (libsource (lib "eagle-import") (part "MA08-2"))
    )
    (comp (ref "SV120")
      (value "MA08-2")
      (footprint "eagle-import:MA08-2")
      (libsource (lib "eagle-import") (part "MA08-2"))
    )
    (comp (ref "C1")
      (value "CPOL-USE12-4AXIAL")
      (footprint "eagle-import:E12-4")
      (libsource (lib "eagle-import") (part "CPOL-USE12-4AXIAL"))
    )
    (comp (ref "C2")
      (value "C-US050-025X075")
      (footprint "eagle-import:C050-025X075")
      (libsource (lib "eagle-import") (part "C-US050-025X075"))
    )
    (comp (ref "C3")
      (value "CPOL-USE12-4AXIAL")
      (footprint "eagle-import:E12-4")
      (libsource (lib "eagle-import") (part "CPOL-USE12-4AXIAL"))
    )
    (comp (ref "C4")
      (value "C-US050-025X075")
      (footprint "eagle-import:C050-025X075")
      (libsource (lib "eagle-import") (part "C-US050-025X075"))
    )
    (comp (ref "C5")
      (value "CPOL-USE12-4AXIAL")
      (footprint "eagle-import:E12-4")
      (libsource (lib "eagle-import") (part "CPOL-USE12-4AXIAL"))
    )
    (comp (ref "C6")
      (value "C-US050-025X075")
      (footprint "eagle-import:C050-025X075")
      (libsource (lib "eagle-import") (part "C-US050-025X075"))
    )
    (comp (ref "C7")
      (value "CPOL-USE12-4AXIAL")
      (footprint "eagle-import:E12-4")
      (libsource (lib "eagle-import") (part "CPOL-USE12-4AXIAL"))
    )
    (comp (ref "C8")
      (value "C-US050-025X075")
      (footprint "eagle-import:C050-025X075")
      (libsource (lib "eagle-import") (part "C-US050-025X075"))
    )
    (comp (ref "C9")
      (value "CPOL-USE12-4AXIAL")
      (footprint "eagle-import:E12-4")
      (libsource (lib "eagle-import") (part "CPOL-USE12-4AXIAL"))
    )
    (comp (ref "C10")
      (value "C-US050-025X075")
      (footprint "eagle-import:C050-025X075")
      (libsource (lib "eagle-import") (part "C-US050-025X075"))
    )
    (comp (ref "C11")
      (value "CPOL-USE12-4AXIAL")
      (footprint "eagle-import:E12-4")
      (libsource (lib "eagle-import") (part "CPOL-USE12-4AXIAL"))
    )
    (comp (ref "C12")
      (value "C-US050-025X075")
      (footprint "eagle-import:C050-025X075")
      (libsource (lib "eagle-import") (part "C-US050-025X075"))
    )
    (comp (ref "C13")
      (value "CPOL-USE12-4AXIAL")
      (footprint "eagle-import:E12-4")
      (libsource (lib "eagle-import") (part "CPOL-USE12-4AXIAL"))
    )
    (comp (ref "C14")
      (value "C-US050-025X075")
      (footprint "eagle-import:C050-025X075")
      (libsource (lib "eagle-import") (part "C-US050-025X075"))
    )
    (comp (ref "C15")
      (value "CPOL-USE12-4AXIAL")
      (footprint "eagle-import:E12-4")
      (libsource (lib "eagle-import") (part "CPOL-USE12-4AXIAL"))
    )
    (comp (ref "C16")
      (value "C-US050-025X075")
      (footprint "eagle-import:C050-025X075")
      (libsource (lib "eagle-import") (part "C-US050-025X075"))
    )
    (comp (ref "C17")
      (value "CPOL-USE12-4AXIAL")
      (footprint "eagle-import:E12-4")
      (libsource (lib "eagle-import") (part "CPOL-USE12-4AXIAL"))
    )
    (comp (ref "C18")
      (value "C-US050-025X075")
      (footprint "eagle-import:C050-025X075")
      (libsource (lib "eagle-import") (part "C-US050-025X075"))
    )
    (comp (ref "C19")
      (value "CPOL-USE12-4AXIAL")
      (footprint "eagle-import:E12-4")
      (libsource (lib "eagle-import") (part "CPOL-USE12-4AXIAL"))
    )
    (comp (ref "C20")
      (value "C-US050-025X075")
      (footprint "eagle-import:C050-025X075")
      (libsource (lib "eagle-import") (part "C-US050-025X075"))
    )
    (comp (ref "C21")
      (value "CPOL-USE12-4AXIAL")
      (footprint "eagle-import:E12-4")
      (libsource (lib "eagle-import") (part "CPOL-USE12-4AXIAL"))
    )
    (comp (ref "C22")
      (value "C-US050-025X075")
      (footprint "eagle-import:C050-025X075")
      (libsource (lib "eagle-import") (part "C-US050-025X075"))
    )
    (comp (ref "C23")
      (value "CPOL-USE12-4AXIAL")
      (footprint "eagle-import:E12-4")
      (libsource (lib "eagle-import") (part "CPOL-USE12-4AXIAL"))
    )
    (comp (ref "C24")
      (value "C-US050-025X075")
      (footprint "eagle-import:C050-025X075")
      (libsource (lib "eagle-import") (part "C-US050-025X075"))
    )
    (comp (ref "C25")
      (value "CPOL-USE12-4AXIAL")
      (footprint "eagle-import:E12-4")
      (libsource (lib "eagle-import") (part "CPOL-USE12-4AXIAL"))
    )
    (comp (ref "C26")
      (value "C-US050-025X075")
      (footprint "eagle-import:C050-025X075")
      (libsource (lib "eagle-import") (part "C-US050-025X075"))
    )
    (comp (ref "C27")
      (value "CPOL-USE12-4AXIAL")
      (footprint "eagle-import:E12-4")
      (libsource (lib "eagle-import") (part "CPOL-USE12-4AXIAL"))
    )
    (comp (ref "C28")
      (value "C-US050-025X075")
      (footprint "eagle-import:C050-025X075")
      (libsource (lib "eagle-import") (part "C-US050-025X075"))
    )
    (comp (ref "C29")
      (value "CPOL-USE12-4AXIAL")
      (footprint "eagle-import:E12-4")
      (libsource (lib "eagle-import") (part "CPOL-USE12-4AXIAL"))
    )
    (comp (ref "C30")
      (value "C-US050-025X075")
      (footprint "eagle-import:C050-025X075")
      (libsource (lib "eagle-import") (part "C-US050-025X075"))
    )
    (comp (ref "C31")
      (value "CPOL-USE12-4AXIAL")
      (footprint "eagle-import:E12-4")
      (libsource (lib "eagle-import") (part "CPOL-USE12-4AXIAL"))
    )
    (comp (ref "C32")
      (value "C-US050-025X075")
      (footprint "eagle-import:C050-025X075")
      (libsource (lib "eagle-import") (part "C-US050-025X075"))
    )
    (comp (ref "C33")
      (value "CPOL-USE12-4AXIAL")
      (footprint "eagle-import:E12-4")
      (libsource (lib "eagle-import") (part "CPOL-USE12-4AXIAL"))
    )
    (comp (ref "C34")
      (value "C-US050-025X075")
      (footprint "eagle-import:C050-025X075")
      (libsource (lib "eagle-import") (part "C-US050-025X075"))
    )
    (comp (ref "C35")
      (value "CPOL-USE12-4AXIAL")
      (footprint "eagle-import:E12-4")
      (libsource (lib "eagle-import") (part "CPOL-USE12-4AXIAL"))
    )
    (comp (ref "C36")
      (value "C-US050-025X075")
      (footprint "eagle-import:C050-025X075")
      (libsource (lib "eagle-import") (part "C-US050-025X075"))
    )
    (comp (ref "C37")
      (value "CPOL-USE12-4AXIAL")
      (footprint "eagle-import:E12-4")
      (libsource (lib "eagle-import") (part "CPOL-USE12-4AXIAL"))
    )
    (comp (ref "C38")
      (value "C-US050-025X075")
      (footprint "eagle-import:C050-025X075")
      (libsource (lib "eagle-import") (part "C-US050-025X075"))
    )
    (comp (ref "C39")
      (value "CPOL-USE12-4AXIAL")
      (footprint "eagle-import:E12-4")
      (libsource (lib "eagle-import") (part "CPOL-USE12-4AXIAL"))
    )
    (comp (ref "C40")
      (value "C-US050-025X075")
      (footprint "eagle-import:C050-025X075")
      (libsource (lib "eagle-import") (part "C-US050-025X075"))
    )
    (comp (ref "C41")
      (value "CPOL-USE12-4AXIAL")
      (footprint "eagle-import:E12-4")
      (libsource (lib "eagle-import") (part "CPOL-USE12-4AXIAL"))
    )
    (comp (ref "C42")
      (value "C-US050-025X075")
      (footprint "eagle-import:C050-025X075")
      (libsource (lib "eagle-import") (part "C-US050-025X075"))
    )
    (comp (ref "C43")
      (value "CPOL-USE12-4AXIAL")
      (footprint "eagle-import:E12-4")
      (libsource (lib "eagle-import") (part "CPOL-USE12-4AXIAL"))
    )
    (comp (ref "C44")
      (value "C-US050-025X075")
      (footprint "eagle-import:C050-025X075")
      (libsource (lib "eagle-import") (part "C-US050-025X075"))
    )
    (comp (ref "C45")
      (value "CPOL-USE12-4AXIAL")
      (footprint "eagle-import:E12-4")
      (libsource (lib "eagle-import") (part "CPOL-USE12-4AXIAL"))
    )
    (comp (ref "C46")
      (value "C-US050-025X075")
      (footprint "eagle-import:C050-025X075")
      (libsource (lib "eagle-import") (part "C-US050-025X075"))
    )
    (comp (ref "C47")
      (value "CPOL-USE12-4AXIAL")
      (footprint "eagle-import:E12-4")
      (libsource (lib "eagle-import") (part "CPOL-USE12-4AXIAL"))
    )
    (comp (ref "C48")
      (value "C-US050-025X075")
      (footprint "eagle-import:C050-025X075")
      (libsource (lib "eagle-import") (part "C-US050-025X075"))
    )
    (comp (ref "C49")
      (value "CPOL-USE12-4AXIAL")
      (footprint "eagle-import:E12-4")
      (libsource (lib "eagle-import") (part "CPOL-USE12-4AXIAL"))
    )
    (comp (ref "C50")
      (value "C-US050-025X075")
      (footprint "eagle-import:C050-025X075")
      (libsource (lib "eagle-import") (part "C-US050-025X075"))
    )
    (comp (ref "C51")
      (value "CPOL-USE12-4AXIAL")
      (footprint "eagle-import:E12-4")
      (libsource (lib "eagle-import") (part "CPOL-USE12-4AXIAL"))
    )
    (comp (ref "C52")
      (value "C-US050-025X075")
      (footprint "eagle-import:C050-025X075")
      (libsource (lib "eagle-import") (part "C-US050-025X075"))
    )
    (comp (ref "C53")
      (value "CPOL-USE12-4AXIAL")
      (footprint "eagle-import:E12-4")
      (libsource (lib "eagle-import") (part "CPOL-USE12-4AXIAL"))
    )
    (comp (ref "C54")
      (value "C-US050-025X075")
      (footprint "eagle-import:C050-025X075")
      (libsource (lib "eagle-import") (part "C-US050-025X075"))
    )
    (comp (ref "C55")
      (value "CPOL-USE12-4AXIAL")
      (footprint "eagle-import:E12-4")
      (libsource (lib "eagle-import") (part "CPOL-USE12-4AXIAL"))
    )
    (comp (ref "C56")
      (value "C-US050-025X075")
      (footprint "eagle-import:C050-025X075")
      (libsource (lib "eagle-import") (part "C-US050-025X075"))
    )
    (comp (ref "C57")
      (value "CPOL-USE12-4AXIAL")
      (footprint "eagle-import:E12-4")
      (libsource (lib "eagle-import") (part "CPOL-USE12-4AXIAL"))
    )
    (comp (ref "C58")
      (value "C-US050-025X075")
      (footprint "eagle-import:C050-025X075")
      (libsource (lib "eagle-import") (part "C-US050-025X075"))
    )
    (comp (ref "C59")
      (value "CPOL-USE12-4AXIAL")
      (footprint "eagle-import:E12-4")
      (libsource (lib "eagle-import") (part "CPOL-USE12-4AXIAL"))
    )
    (comp (ref "C60")
      (value "C-US050-025X075")
      (footprint "eagle-import:C050-025X075")
      (libsource (lib "eagle-import") (part "C-US050-025X075"))
    )
    (comp (ref "C61")
      (value "CPOL-USE12-4AXIAL")
      (footprint "eagle-import:E12-4")
      (libsource (lib "eagle-import") (part "CPOL-USE12-4AXIAL"))
    )
    (comp (ref "C62")
      (value "C-US050-025X075")
      (footprint "eagle-import:C050-025X075")
      (libsource (lib "eagle-import") (part "C-US050-025X075"))
    )
    (comp (ref "C63")
      (value "CPOL-USE12-4AXIAL")
      (footprint "eagle-import:E12-4")
      (libsource (lib "eagle-import") (part "CPOL-USE12-4AXIAL"))
    )
    (comp (ref "C64")
      (value "C-US050-025X075")
      (footprint "eagle-import:C050-025X075")
      (libsource (lib "eagle-import") (part "C-US050-025X075"))
    )
    (comp (ref "C65")
      (value "CPOL-USE12-4AXIAL")
      (footprint "eagle-import:E12-4")
      (libsource (lib "eagle-import") (part "CPOL-USE12-4AXIAL"))
    )
    (comp (ref "C66")
      (value "C-US050-025X075")
      (footprint "eagle-import:C050-025X075")
      (libsource (lib "eagle-import") (part "C-US050-025X075"))
    )
    (comp (ref "C67")
      (value "CPOL-USE12-4AXIAL")
      (footprint "eagle-import:E12-4")
      (libsource (lib "eagle-import") (part "CPOL-USE12-4AXIAL"))
    )
    (comp (ref "C68")
      (value "C-US050-025X075")
      (footprint "eagle-import:C050-025X075")
      (libsource (lib "eagle-import") (part "C-US050-025X075"))
    )
    (comp (ref "C69")
      (value "CPOL-USE12-4AXIAL")
      (footprint "eagle-import:E12-4")
      (libsource (lib "eagle-import") (part "CPOL-USE12-4AXIAL"))
    )
    (comp (ref "C70")
      (value "C-US050-025X075")
      (footprint "eagle-import:C050-025X075")
      (libsource (lib "eagle-import") (part "C-US050-025X075"))
    )
    (comp (ref "C71")
      (value "CPOL-USE12-4AXIAL")
      (footprint "eagle-import:E12-4")
      (libsource (lib "eagle-import") (part "CPOL-USE12-4AXIAL"))
    )
    (comp (ref "C72")
      (value "C-US050-025X075")
      (footprint "eagle-import:C050-025X075")
      (libsource (lib "eagle-import") (part "C-US050-025X075"))
    )
    (comp (ref "C73")
      (value "CPOL-USE12-4AXIAL")
      (footprint "eagle-import:E12-4")
      (libsource (lib "eagle-import") (part "CPOL-USE12-4AXIAL"))
    )
    (comp (ref "C74")
      (value "C-US050-025X075")
      (footprint "eagle-import:C050-025X075")
      (libsource (lib "eagle-import") (part "C-US050-025X075"))
    )
    (comp (ref "C75")
      (value "CPOL-USE12-4AXIAL")
      (footprint "eagle-import:E12-4")
      (libsource (lib "eagle-import") (part "CPOL-USE12-4AXIAL"))
    )
    (comp (ref "C76")
      (value "C-US050-025X075")
      (footprint "eagle-import:C050-025X075")
      (libsource (lib "eagle-import") (part "C-US050-025X075"))
    )
    (comp (ref "C77")
      (value "CPOL-USE12-4AXIAL")
      (footprint "eagle-import:E12-4")
      (libsource (lib "eagle-import") (part "CPOL-USE12-4AXIAL"))
    )
    (comp (ref "C78")
      (value "C-US050-025X075")
      (footprint "eagle-import:C050-025X075")
      (libsource (lib "eagle-import") (part "C-US050-025X075"))
    )
    (comp (ref "C79")
      (value "CPOL-USE12-4AXIAL")
      (footprint "eagle-import:E12-4")
      (libsource (lib "eagle-import") (part "CPOL-USE12-4AXIAL"))
    )
    (comp (ref "C80")
      (value "C-US050-025X075")
      (footprint "eagle-import:C050-025X075")
      (libsource (lib "eagle-import") (part "C-US050-025X075"))
    )
    (comp (ref "C81")
      (value "CPOL-USE12-4AXIAL")
      (footprint "eagle-import:E12-4")
      (libsource (lib "eagle-import") (part "CPOL-USE12-4AXIAL"))
    )
    (comp (ref "C82")
      (value "C-US050-025X075")
      (footprint "eagle-import:C050-025X075")
      (libsource (lib "eagle-import") (part "C-US050-025X075"))
    )
    (comp (ref "C83")
      (value "CPOL-USE12-4AXIAL")
      (footprint "eagle-import:E12-4")
      (libsource (lib "eagle-import") (part "CPOL-USE12-4AXIAL"))
    )
    (comp (ref "C84")
      (value "C-US050-025X075")
      (footprint "eagle-import:C050-025X075")
      (libsource (lib "eagle-import") (part "C-US050-025X075"))
    )
    (comp (ref "C85")
      (value "CPOL-USE12-4AXIAL")
      (footprint "eagle-import:E12-4")
      (libsource (lib "eagle-import") (part "CPOL-USE12-4AXIAL"))
    )
    (comp (ref "C86")
      (value "C-US050-025X075")
      (footprint "eagle-import:C050-025X075")
      (libsource (lib "eagle-import") (part "C-US050-025X075"))
    )
    (comp (ref "C87")
      (value "CPOL-USE12-4AXIAL")
      (footprint "eagle-import:E12-4")
      (libsource (lib "eagle-import") (part "CPOL-USE12-4AXIAL"))
    )
    (comp (ref "C88")
      (value "C-US050-025X075")
      (footprint "eagle-import:C050-025X075")
      (libsource (lib "eagle-import") (part "C-US050-025X075"))
    )
    (comp (ref "C89")
      (value "CPOL-USE12-4AXIAL")
      (footprint "eagle-import:E12-4")
      (libsource (lib "eagle-import") (part "CPOL-USE12-4AXIAL"))
    )
    (comp (ref "C90")
      (value "C-US050-025X075")
      (footprint "eagle-import:C050-025X075")
      (libsource (lib "eagle-import") (part "C-US050-025X075"))
    )
    (comp (ref "C91")
      (value "CPOL-USE12-4AXIAL")
      (footprint "eagle-import:E12-4")
      (libsource (lib "eagle-import") (part "CPOL-USE12-4AXIAL"))
    )
    (comp (ref "C92")
      (value "C-US050-025X075")
      (footprint "eagle-import:C050-025X075")
      (libsource (lib "eagle-import") (part "C-US050-025X075"))
    )
    (comp (ref "C93")
      (value "CPOL-USE12-4AXIAL")
      (footprint "eagle-import:E12-4")
      (libsource (lib "eagle-import") (part "CPOL-USE12-4AXIAL"))
    )
    (comp (ref "C94")
      (value "C-US050-025X075")
      (footprint "eagle-import:C050-025X075")
      (libsource (lib "eagle-import") (part "C-US050-025X075"))
    )
    (comp (ref "C95")
      (value "CPOL-USE12-4AXIAL")
      (footprint "eagle-import:E12-4")
      (libsource (lib "eagle-import") (part "CPOL-USE12-4AXIAL"))
    )
    (comp (ref "C96")
      (value "C-US050-025X075")
      (footprint "eagle-import:C050-025X075")
      (libsource (lib "eagle-import") (part "C-US050-025X075"))
    )
    (comp (ref "C97")
      (value "CPOL-USE12-4AXIAL")
      (footprint "eagle-import:E12-4")
      (libsource (lib "eagle-import") (part "CPOL-USE12-4AXIAL"))
    )
    (comp (ref "C98")
      (value "C-US050-025X075")
      (footprint "eagle-import:C050-025X075")
      (libsource (lib "eagle-import") (part "C-US050-025X075"))
    )
    (comp (ref "C99")
      (value "CPOL-USE12-4AXIAL")
      (footprint "eagle-import:E12-4")
      (libsource (lib "eagle-import") (part "CPOL-USE12-4AXIAL"))
    )
    (comp (ref "C100")
      (value "C-US050-025X075")
      (footprint "eagle-import:C050-025X075")
      (libsource (lib "eagle-import") (part "C-US050-025X075"))
    )
    (comp (ref "C101")
      (value "CPOL-USE12-4AXIAL")
      (footprint "eagle-import:E12-4")
      (libsource (lib "eagle-import") (part "CPOL-USE12-4AXIAL"))
    )
    (comp (ref "C102")
      (value "C-US050-025X075")
      (footprint "eagle-import:C050-025X075")
      (libsource (lib "eagle-import") (part "C-US050-025X075"))
    )
    (comp (ref "C103")
      (value "CPOL-USE12-4AXIAL")
      (footprint "eagle-import:E12-4")
      (libsource (lib "eagle-import") (part "CPOL-USE12-4AXIAL"))
    )
    (comp (ref "C104")
      (value "C-US050-025X075")
      (footprint "eagle-import:C050-025X075")
      (libsource (lib "eagle-import") (part "C-US050-025X075"))
    )
    (comp (ref "C105")
      (value "CPOL-USE12-4AXIAL")
      (footprint "eagle-import:E12-4")
      (libsource (lib "eagle-import") (part "CPOL-USE12-4AXIAL"))
    )
    (comp (ref "C106")
      (value "C-US050-025X075")
      (footprint "eagle-import:C050-025X075")
      (libsource (lib "eagle-import") (part "C-US050-025X075"))
    )
    (comp (ref "C107")
      (value "CPOL-USE12-4AXIAL")
      (footprint "eagle-import:E12-4")
      (libsource (lib "eagle-import") (part "CPOL-USE12-4AXIAL"))
    )
    (comp (ref "C108")
      (value "C-US050-025X075")
      (footprint "eagle-import:C050-025X075")
      (libsource (lib "eagle-import") (part "C-US050-025X075"))
    )
    (comp (ref "C109")
      (value "CPOL-USE12-4AXIAL")
      (footprint "eagle-import:E12-4")
      (libsource (lib "eagle-import") (part "CPOL-USE12-4AXIAL"))
    )
    (comp (ref "C110")
      (value "C-US050-025X075")
      (footprint "eagle-import:C050-025X075")
      (libsource (lib "eagle-import") (part "C-US050-025X075"))
    )
    (comp (ref "C111")
      (value "CPOL-USE12-4AXIAL")
      (footprint "eagle-import:E12-4")
      (libsource (lib "eagle-import") (part "CPOL-USE12-4AXIAL"))
    )
    (comp (ref "C112")
      (value "C-US050-025X075")
      (footprint "eagle-import:C050-025X075")
      (libsource (lib "eagle-import") (part "C-US050-025X075"))
    )
    (comp (ref "C113")
      (value "CPOL-USE12-4AXIAL")
      (footprint "eagle-import:E12-4")
      (libsource (lib "eagle-import") (part "CPOL-USE12-4AXIAL"))
    )
    (comp (ref "C114")
      (value "C-US050-025X075")
      (footprint "eagle-import:C050-025X075")
      (libsource (lib "eagle-import") (part "C-US050-025X075"))
    )
    (comp (ref "C115")
      (value "CPOL-USE12-4AXIAL")
      (footprint "eagle-import:E12-4")
      (libsource (lib "eagle-import") (part "CPOL-USE12-4AXIAL"))
    )
    (comp (ref "C116")
      (value "C-US050-025X075")
      (footprint "eagle-import:C050-025X075")
      (libsource (lib "eagle-import") (part "C-US050-025X075"))
    )
    (comp (ref "C117")
      (value "CPOL-USE12-4AXIAL")
      (footprint "eagle-import:E12-4")
      (libsource (lib "eagle-import") (part "CPOL-USE12-4AXIAL"))
    )
    (comp (ref "C118")
      (value "C-US050-025X075")
      (footprint "eagle-import:C050-025X075")
      (libsource (lib "eagle-import") (part "C-US050-025X075"))
    )
    (comp (ref "C119")
      (value "CPOL-USE12-4AXIAL")
      (footprint "eagle-import:E12-4")
      (libsource (lib "eagle-import") (part "CPOL-USE12-4AXIAL"))
    )
    (comp (ref "C120")
      (value "C-US050-025X075")
      (footprint "eagle-import:C050-025X075")
      (libsource (lib "eagle-import") (part "C-US050-025X075"))
    )
    (comp (ref "C121")
      (value "C-US075-032X103")
      (footprint "eagle-import:C075-032X103")
      (libsource (lib "eagle-import") (part "C-US075-032X103"))
    )
    (comp (ref "C122")
      (value "C-US075-032X103")
      (footprint "eagle-import:C075-032X103")
      (libsource (lib "eagle-import") (part "C-US075-032X103"))
    )
    (comp (ref "C123")
      (value "C-US075-032X103")
      (footprint "eagle-import:C075-032X103")
      (libsource (lib "eagle-import") (part "C-US075-032X103"))
    )
    (comp (ref "C124")
      (value "C-US075-032X103")
      (footprint "eagle-import:C075-032X103")
      (libsource (lib "eagle-import") (part "C-US075-032X103"))
    )
    (comp (ref "C125")
      (value "C-US075-032X103")
      (footprint "eagle-import:C075-032X103")
      (libsource (lib "eagle-import") (part "C-US075-032X103"))
    )
    (comp (ref "C126")
      (value "C-US075-032X103")
      (footprint "eagle-import:C075-032X103")
      (libsource (lib "eagle-import") (part "C-US075-032X103"))
    )
    (comp (ref "C127")
      (value "C-US075-032X103")
      (footprint "eagle-import:C075-032X103")
      (libsource (lib "eagle-import") (part "C-US075-032X103"))
    )
    (comp (ref "C128")
      (value "C-US075-032X103")
      (footprint "eagle-import:C075-032X103")
      (libsource (lib "eagle-import") (part "C-US075-032X103"))
    )
    (comp (ref "C129")
      (value "C-US075-032X103")
      (footprint "eagle-import:C075-032X103")
      (libsource (lib "eagle-import") (part "C-US075-032X103"))
    )
    (comp (ref "C130")
      (value "C-US075-032X103")
      (footprint "eagle-import:C075-032X103")
      (libsource (lib "eagle-import") (part "C-US075-032X103"))
    )
    (comp (ref "C131")
      (value "C-US075-032X103")
      (footprint "eagle-import:C075-032X103")
      (libsource (lib "eagle-import") (part "C-US075-032X103"))
    )
    (comp (ref "C132")
      (value "C-US075-032X103")
      (footprint "eagle-import:C075-032X103")
      (libsource (lib "eagle-import") (part "C-US075-032X103"))
    )
    (comp (ref "C133")
      (value "C-US075-032X103")
      (footprint "eagle-import:C075-032X103")
      (libsource (lib "eagle-import") (part "C-US075-032X103"))
    )
    (comp (ref "C134")
      (value "C-US075-032X103")
      (footprint "eagle-import:C075-032X103")
      (libsource (lib "eagle-import") (part "C-US075-032X103"))
    )
    (comp (ref "C135")
      (value "C-US075-032X103")
      (footprint "eagle-import:C075-032X103")
      (libsource (lib "eagle-import") (part "C-US075-032X103"))
    )
    (comp (ref "C136")
      (value "C-US075-032X103")
      (footprint "eagle-import:C075-032X103")
      (libsource (lib "eagle-import") (part "C-US075-032X103"))
    )
    (comp (ref "IC61")
      (value "DIL16")
      (footprint "eagle-import:DIL16")
      (libsource (lib "eagle-import") (part "DIL16"))
    )
    (comp (ref "IC62")
      (value "DIL16")
      (footprint "eagle-import:DIL16")
      (libsource (lib "eagle-import") (part "DIL16"))
    )
    (comp (ref "IC63")
      (value "DIL16")
      (footprint "eagle-import:DIL16")
      (libsource (lib "eagle-import") (part "DIL16"))
    )
    (comp (ref "IC64")
      (value "DIL16")
      (footprint "eagle-import:DIL16")
      (libsource (lib "eagle-import") (part "DIL16"))
    )
    (comp (ref "IC65")
      (value "DIL16")
      (footprint "eagle-import:DIL16")
      (libsource (lib "eagle-import") (part "DIL16"))
    )
    (comp (ref "IC66")
      (value "DIL16")
      (footprint "eagle-import:DIL16")
      (libsource (lib "eagle-import") (part "DIL16"))
    )
    (comp (ref "IC67")
      (value "DIL16")
      (footprint "eagle-import:DIL16")
      (libsource (lib "eagle-import") (part "DIL16"))
    )
    (comp (ref "IC68")
      (value "DIL16")
      (footprint "eagle-import:DIL16")
      (libsource (lib "eagle-import") (part "DIL16"))
    )
    (comp (ref "IC69")
      (value "DIL16")
      (footprint "eagle-import:DIL16")
      (libsource (lib "eagle-import") (part "DIL16"))
    )
    (comp (ref "IC70")
      (value "DIL16")
      (footprint "eagle-import:DIL16")
      (libsource (lib "eagle-import") (part "DIL16"))
    )
    (comp (ref "IC71")
      (value "DIL16")
      (footprint "eagle-import:DIL16")
      (libsource (lib "eagle-import") (part "DIL16"))
    )
    (comp (ref "IC72")
      (value "DIL16")
      (footprint "eagle-import:DIL16")
      (libsource (lib "eagle-import") (part "DIL16"))
    )
    (comp (ref "SV129")
      (value "MA08-2")
      (footprint "eagle-import:MA08-2")
      (libsource (lib "eagle-import") (part "MA08-2"))
    )
    (comp (ref "SV130")
      (value "MA08-2")
      (footprint "eagle-import:MA08-2")
      (libsource (lib "eagle-import") (part "MA08-2"))
    )
    (comp (ref "SV131")
      (value "MA08-2")
      (footprint "eagle-import:MA08-2")
      (libsource (lib "eagle-import") (part "MA08-2"))
    )
    (comp (ref "SV132")
      (value "MA08-1")
      (footprint "eagle-import:MA08-1")
      (libsource (lib "eagle-import") (part "MA08-1"))
    )
    (comp (ref "SV133")
      (value "MA08-2")
      (footprint "eagle-import:MA08-2")
      (libsource (lib "eagle-import") (part "MA08-2"))
    )
    (comp (ref "SV134")
      (value "MA08-2")
      (footprint "eagle-import:MA08-2")
      (libsource (lib "eagle-import") (part "MA08-2"))
    )
    (comp (ref "SV135")
      (value "MA08-2")
      (footprint "eagle-import:MA08-2")
      (libsource (lib "eagle-import") (part "MA08-2"))
    )
    (comp (ref "SV136")
      (value "MA08-1")
      (footprint "eagle-import:MA08-1")
      (libsource (lib "eagle-import") (part "MA08-1"))
    )
    (comp (ref "SV137")
      (value "MA08-2")
      (footprint "eagle-import:MA08-2")
      (libsource (lib "eagle-import") (part "MA08-2"))
    )
    (comp (ref "SV138")
      (value "MA08-2")
      (footprint "eagle-import:MA08-2")
      (libsource (lib "eagle-import") (part "MA08-2"))
    )
    (comp (ref "SV139")
      (value "MA08-2")
      (footprint "eagle-import:MA08-2")
      (libsource (lib "eagle-import") (part "MA08-2"))
    )
    (comp (ref "SV140")
      (value "MA08-1")
      (footprint "eagle-import:MA08-1")
      (libsource (lib "eagle-import") (part "MA08-1"))
    )
    (comp (ref "SV141")
      (value "MA08-2")
      (footprint "eagle-import:MA08-2")
      (libsource (lib "eagle-import") (part "MA08-2"))
    )
    (comp (ref "SV142")
      (value "MA08-2")
      (footprint "eagle-import:MA08-2")
      (libsource (lib "eagle-import") (part "MA08-2"))
    )
    (comp (ref "SV143")
      (value "MA08-2")
      (footprint "eagle-import:MA08-2")
      (libsource (lib "eagle-import") (part "MA08-2"))
    )
    (comp (ref "SV144")
      (value "MA08-1")
      (footprint "eagle-import:MA08-1")
      (libsource (lib "eagle-import") (part "MA08-1"))
    )
    (comp (ref "SV145")
      (value "MA08-2")
      (footprint "eagle-import:MA08-2")
      (libsource (lib "eagle-import") (part "MA08-2"))
    )
    (comp (ref "SV146")
      (value "MA08-2")
      (footprint "eagle-import:MA08-2")
      (libsource (lib "eagle-import") (part "MA08-2"))
    )
    (comp (ref "SV147")
      (value "MA08-2")
      (footprint "eagle-import:MA08-2")
      (libsource (lib "eagle-import") (part "MA08-2"))
    )
    (comp (ref "SV148")
      (value "MA08-1")
      (footprint "eagle-import:MA08-1")
      (libsource (lib "eagle-import") (part "MA08-1"))
    )
    (comp (ref "SV149")
      (value "MA08-2")
      (footprint "eagle-import:MA08-2")
      (libsource (lib "eagle-import") (part "MA08-2"))
    )
    (comp (ref "SV150")
      (value "MA08-2")
      (footprint "eagle-import:MA08-2")
      (libsource (lib "eagle-import") (part "MA08-2"))
    )
    (comp (ref "SV151")
      (value "MA08-2")
      (footprint "eagle-import:MA08-2")
      (libsource (lib "eagle-import") (part "MA08-2"))
    )
    (comp (ref "SV152")
      (value "MA08-1")
      (footprint "eagle-import:MA08-1")
      (libsource (lib "eagle-import") (part "MA08-1"))
    )
    (comp (ref "SV153")
      (value "MA08-2")
      (footprint "eagle-import:MA08-2")
      (libsource (lib "eagle-import") (part "MA08-2"))
    )
    (comp (ref "SV154")
      (value "MA08-2")
      (footprint "eagle-import:MA08-2")
      (libsource (lib "eagle-import") (part "MA08-2"))
    )
    (comp (ref "SV155")
      (value "MA08-2")
      (footprint "eagle-import:MA08-2")
      (libsource (lib "eagle-import") (part "MA08-2"))
    )
    (comp (ref "SV156")
      (value "MA08-1")
      (footprint "eagle-import:MA08-1")
      (libsource (lib "eagle-import") (part "MA08-1"))
    )
    (comp (ref "SV157")
      (value "MA08-2")
      (footprint "eagle-import:MA08-2")
      (libsource (lib "eagle-import") (part "MA08-2"))
    )
    (comp (ref "SV158")
      (value "MA08-2")
      (footprint "eagle-import:MA08-2")
      (libsource (lib "eagle-import") (part "MA08-2"))
    )
    (comp (ref "SV159")
      (value "MA08-2")
      (footprint "eagle-import:MA08-2")
      (libsource (lib "eagle-import") (part "MA08-2"))
    )
    (comp (ref "SV160")
      (value "MA08-1")
      (footprint "eagle-import:MA08-1")
      (libsource (lib "eagle-import") (part "MA08-1"))
    )
    (comp (ref "SV161")
      (value "MA08-2")
      (footprint "eagle-import:MA08-2")
      (libsource (lib "eagle-import") (part "MA08-2"))
    )
    (comp (ref "SV162")
      (value "MA08-2")
      (footprint "eagle-import:MA08-2")
      (libsource (lib "eagle-import") (part "MA08-2"))
    )
    (comp (ref "SV163")
      (value "MA08-2")
      (footprint "eagle-import:MA08-2")
      (libsource (lib "eagle-import") (part "MA08-2"))
    )
    (comp (ref "SV164")
      (value "MA08-1")
      (footprint "eagle-import:MA08-1")
      (libsource (lib "eagle-import") (part "MA08-1"))
    )
    (comp (ref "SV165")
      (value "MA08-2")
      (footprint "eagle-import:MA08-2")
      (libsource (lib "eagle-import") (part "MA08-2"))
    )
    (comp (ref "SV166")
      (value "MA08-2")
      (footprint "eagle-import:MA08-2")
      (libsource (lib "eagle-import") (part "MA08-2"))
    )
    (comp (ref "SV167")
      (value "MA08-2")
      (footprint "eagle-import:MA08-2")
      (libsource (lib "eagle-import") (part "MA08-2"))
    )
    (comp (ref "SV168")
      (value "MA08-1")
      (footprint "eagle-import:MA08-1")
      (libsource (lib "eagle-import") (part "MA08-1"))
    )
    (comp (ref "SV169")
      (value "MA08-2")
      (footprint "eagle-import:MA08-2")
      (libsource (lib "eagle-import") (part "MA08-2"))
    )
    (comp (ref "SV170")
      (value "MA08-2")
      (footprint "eagle-import:MA08-2")
      (libsource (lib "eagle-import") (part "MA08-2"))
    )
    (comp (ref "SV171")
      (value "MA08-2")
      (footprint "eagle-import:MA08-2")
      (libsource (lib "eagle-import") (part "MA08-2"))
    )
    (comp (ref "SV172")
      (value "MA08-1")
      (footprint "eagle-import:MA08-1")
      (libsource (lib "eagle-import") (part "MA08-1"))
    )
    (comp (ref "SV173")
      (value "MA08-2")
      (footprint "eagle-import:MA08-2")
      (libsource (lib "eagle-import") (part "MA08-2"))
    )
    (comp (ref "SV174")
      (value "MA08-2")
      (footprint "eagle-import:MA08-2")
      (libsource (lib "eagle-import") (part "MA08-2"))
    )
    (comp (ref "SV175")
      (value "MA08-2")
      (footprint "eagle-import:MA08-2")
      (libsource (lib "eagle-import") (part "MA08-2"))
    )
    (comp (ref "SV176")
      (value "MA08-1")
      (footprint "eagle-import:MA08-1")
      (libsource (lib "eagle-import") (part "MA08-1"))
    )
  )
  (nets
    (net (code "1") (name "+15V") (class "Default")
      (node (ref "JD2") (pin "1") (pinfunction "1_1") (pintype "passive"))
      (node (ref "U$2") (pin "DA2") (pinfunction "1_DA2") (pintype "bidirectional"))
    )
    (net (code "2") (name "GND") (class "Default")
      (node (ref "C1") (pin "-") (pinfunction "-_-") (pintype "passive"))
      (node (ref "C10") (pin "2") (pinfunction "2_2") (pintype "passive"))
      (node (ref "C100") (pin "2") (pinfunction "2_2") (pintype "passive"))
      (node (ref "C101") (pin "-") (pinfunction "-_-") (pintype "passive"))
      (node (ref "C102") (pin "2") (pinfunction "2_2") (pintype "passive"))
      (node (ref "C103") (pin "-") (pinfunction "-_-") (pintype "passive"))
      (node (ref "C104") (pin "2") (pinfunction "2_2") (pintype "passive"))
      (node (ref "C105") (pin "-") (pinfunction "-_-") (pintype "passive"))
      (node (ref "C106") (pin "2") (pinfunction "2_2") (pintype "passive"))
      (node (ref "C107") (pin "-") (pinfunction "-_-") (pintype "passive"))
      (node (ref "C108") (pin "2") (pinfunction "2_2") (pintype "passive"))
      (node (ref "C109") (pin "-") (pinfunction "-_-") (pintype "passive"))
      (node (ref "C11") (pin "-") (pinfunction "-_-") (pintype "passive"))
      (node (ref "C110") (pin "2") (pinfunction "2_2") (pintype "passive"))
      (node (ref "C111") (pin "-") (pinfunction "-_-") (pintype "passive"))
      (node (ref "C112") (pin "2") (pinfunction "2_2") (pintype "passive"))
      (node (ref "C113") (pin "-") (pinfunction "-_-") (pintype "passive"))
      (node (ref "C114") (pin "2") (pinfunction "2_2") (pintype "passive"))
      (node (ref "C115") (pin "-") (pinfunction "-_-") (pintype "passive"))
      (node (ref "C116") (pin "2") (pinfunction "2_2") (pintype "passive"))
      (node (ref "C117") (pin "-") (pinfunction "-_-") (pintype "passive"))
      (node (ref "C118") (pin "2") (pinfunction "2_2") (pintype "passive"))
      (node (ref "C119") (pin "-") (pinfunction "-_-") (pintype "passive"))
      (node (ref "C12") (pin "2") (pinfunction "2_2") (pintype "passive"))
      (node (ref "C120") (pin "2") (pinfunction "2_2") (pintype "passive"))
      (node (ref "C121") (pin "2") (pinfunction "2_2") (pintype "passive"))
      (node (ref "C122") (pin "2") (pinfunction "2_2") (pintype "passive"))
      (node (ref "C123") (pin "2") (pinfunction "2_2") (pintype "passive"))
      (node (ref "C124") (pin "2") (pinfunction "2_2") (pintype "passive"))
      (node (ref "C125") (pin "2") (pinfunction "2_2") (pintype "passive"))
      (node (ref "C126") (pin "2") (pinfunction "2_2") (pintype "passive"))
      (node (ref "C127") (pin "2") (pinfunction "2_2") (pintype "passive"))
      (node (ref "C128") (pin "2") (pinfunction "2_2") (pintype "passive"))
      (node (ref "C129") (pin "2") (pinfunction "2_2") (pintype "passive"))
      (node (ref "C13") (pin "-") (pinfunction "-_-") (pintype "passive"))
      (node (ref "C130") (pin "2") (pinfunction "2_2") (pintype "passive"))
      (node (ref "C131") (pin "2") (pinfunction "2_2") (pintype "passive"))
      (node (ref "C132") (pin "2") (pinfunction "2_2") (pintype "passive"))
      (node (ref "C133") (pin "2") (pinfunction "2_2") (pintype "passive"))
      (node (ref "C134") (pin "2") (pinfunction "2_2") (pintype "passive"))
      (node (ref "C135") (pin "2") (pinfunction "2_2") (pintype "passive"))
      (node (ref "C136") (pin "2") (pinfunction "2_2") (pintype "passive"))
      (node (ref "C14") (pin "2") (pinfunction "2_2") (pintype "passive"))
      (node (ref "C15") (pin "-") (pinfunction "-_-") (pintype "passive"))
      (node (ref "C16") (pin "2") (pinfunction "2_2") (pintype "passive"))
      (node (ref "C17") (pin "-") (pinfunction "-_-") (pintype "passive"))
      (node (ref "C18") (pin "2") (pinfunction "2_2") (pintype "passive"))
      (node (ref "C19") (pin "-") (pinfunction "-_-") (pintype "passive"))
      (node (ref "C2") (pin "2") (pinfunction "2_2") (pintype "passive"))
      (node (ref "C20") (pin "2") (pinfunction "2_2") (pintype "passive"))
      (node (ref "C21") (pin "-") (pinfunction "-_-") (pintype "passive"))
      (node (ref "C22") (pin "2") (pinfunction "2_2") (pintype "passive"))
      (node (ref "C23") (pin "-") (pinfunction "-_-") (pintype "passive"))
      (node (ref "C24") (pin "2") (pinfunction "2_2") (pintype "passive"))
      (node (ref "C25") (pin "-") (pinfunction "-_-") (pintype "passive"))
      (node (ref "C26") (pin "2") (pinfunction "2_2") (pintype "passive"))
      (node (ref "C27") (pin "-") (pinfunction "-_-") (pintype "passive"))
      (node (ref "C28") (pin "2") (pinfunction "2_2") (pintype "passive"))
      (node (ref "C29") (pin "-") (pinfunction "-_-") (pintype "passive"))
      (node (ref "C3") (pin "-") (pinfunction "-_-") (pintype "passive"))
      (node (ref "C30") (pin "2") (pinfunction "2_2") (pintype "passive"))
      (node (ref "C31") (pin "-") (pinfunction "-_-") (pintype "passive"))
      (node (ref "C32") (pin "2") (pinfunction "2_2") (pintype "passive"))
      (node (ref "C33") (pin "-") (pinfunction "-_-") (pintype "passive"))
      (node (ref "C34") (pin "2") (pinfunction "2_2") (pintype "passive"))
      (node (ref "C35") (pin "-") (pinfunction "-_-") (pintype "passive"))
      (node (ref "C36") (pin "2") (pinfunction "2_2") (pintype "passive"))
      (node (ref "C37") (pin "-") (pinfunction "-_-") (pintype "passive"))
      (node (ref "C38") (pin "2") (pinfunction "2_2") (pintype "passive"))
      (node (ref "C39") (pin "-") (pinfunction "-_-") (pintype "passive"))
      (node (ref "C4") (pin "2") (pinfunction "2_2") (pintype "passive"))
      (node (ref "C40") (pin "2") (pinfunction "2_2") (pintype "passive"))
      (node (ref "C41") (pin "-") (pinfunction "-_-") (pintype "passive"))
      (node (ref "C42") (pin "2") (pinfunction "2_2") (pintype "passive"))
      (node (ref "C43") (pin "-") (pinfunction "-_-") (pintype "passive"))
      (node (ref "C44") (pin "2") (pinfunction "2_2") (pintype "passive"))
      (node (ref "C45") (pin "-") (pinfunction "-_-") (pintype "passive"))
      (node (ref "C46") (pin "2") (pinfunction "2_2") (pintype "passive"))
      (node (ref "C47") (pin "-") (pinfunction "-_-") (pintype "passive"))
      (node (ref "C48") (pin "2") (pinfunction "2_2") (pintype "passive"))
      (node (ref "C49") (pin "-") (pinfunction "-_-") (pintype "passive"))
      (node (ref "C5") (pin "-") (pinfunction "-_-") (pintype "passive"))
      (node (ref "C50") (pin "2") (pinfunction "2_2") (pintype "passive"))
      (node (ref "C51") (pin "-") (pinfunction "-_-") (pintype "passive"))
      (node (ref "C52") (pin "2") (pinfunction "2_2") (pintype "passive"))
      (node (ref "C53") (pin "-") (pinfunction "-_-") (pintype "passive"))
      (node (ref "C54") (pin "2") (pinfunction "2_2") (pintype "passive"))
      (node (ref "C55") (pin "-") (pinfunction "-_-") (pintype "passive"))
      (node (ref "C56") (pin "2") (pinfunction "2_2") (pintype "passive"))
      (node (ref "C57") (pin "-") (pinfunction "-_-") (pintype "passive"))
      (node (ref "C58") (pin "2") (pinfunction "2_2") (pintype "passive"))
      (node (ref "C59") (pin "-") (pinfunction "-_-") (pintype "passive"))
      (node (ref "C6") (pin "2") (pinfunction "2_2") (pintype "passive"))
      (node (ref "C60") (pin "2") (pinfunction "2_2") (pintype "passive"))
      (node (ref "C61") (pin "-") (pinfunction "-_-") (pintype "passive"))
      (node (ref "C62") (pin "2") (pinfunction "2_2") (pintype "passive"))
      (node (ref "C63") (pin "-") (pinfunction "-_-") (pintype "passive"))
      (node (ref "C64") (pin "2") (pinfunction "2_2") (pintype "passive"))
      (node (ref "C65") (pin "-") (pinfunction "-_-") (pintype "passive"))
      (node (ref "C66") (pin "2") (pinfunction "2_2") (pintype "passive"))
      (node (ref "C67") (pin "-") (pinfunction "-_-") (pintype "passive"))
      (node (ref "C68") (pin "2") (pinfunction "2_2") (pintype "passive"))
      (node (ref "C69") (pin "-") (pinfunction "-_-") (pintype "passive"))
      (node (ref "C7") (pin "-") (pinfunction "-_-") (pintype "passive"))
      (node (ref "C70") (pin "2") (pinfunction "2_2") (pintype "passive"))
      (node (ref "C71") (pin "-") (pinfunction "-_-") (pintype "passive"))
      (node (ref "C72") (pin "2") (pinfunction "2_2") (pintype "passive"))
      (node (ref "C73") (pin "-") (pinfunction "-_-") (pintype "passive"))
      (node (ref "C74") (pin "2") (pinfunction "2_2") (pintype "passive"))
      (node (ref "C75") (pin "-") (pinfunction "-_-") (pintype "passive"))
      (node (ref "C76") (pin "2") (pinfunction "2_2") (pintype "passive"))
      (node (ref "C77") (pin "-") (pinfunction "-_-") (pintype "passive"))
      (node (ref "C78") (pin "2") (pinfunction "2_2") (pintype "passive"))
      (node (ref "C79") (pin "-") (pinfunction "-_-") (pintype "passive"))
      (node (ref "C8") (pin "2") (pinfunction "2_2") (pintype "passive"))
      (node (ref "C80") (pin "2") (pinfunction "2_2") (pintype "passive"))
      (node (ref "C81") (pin "-") (pinfunction "-_-") (pintype "passive"))
      (node (ref "C82") (pin "2") (pinfunction "2_2") (pintype "passive"))
      (node (ref "C83") (pin "-") (pinfunction "-_-") (pintype "passive"))
      (node (ref "C84") (pin "2") (pinfunction "2_2") (pintype "passive"))
      (node (ref "C85") (pin "-") (pinfunction "-_-") (pintype "passive"))
      (node (ref "C86") (pin "2") (pinfunction "2_2") (pintype "passive"))
      (node (ref "C87") (pin "-") (pinfunction "-_-") (pintype "passive"))
      (node (ref "C88") (pin "2") (pinfunction "2_2") (pintype "passive"))
      (node (ref "C89") (pin "-") (pinfunction "-_-") (pintype "passive"))
      (node (ref "C9") (pin "-") (pinfunction "-_-") (pintype "passive"))
      (node (ref "C90") (pin "2") (pinfunction "2_2") (pintype "passive"))
      (node (ref "C91") (pin "-") (pinfunction "-_-") (pintype "passive"))
      (node (ref "C92") (pin "2") (pinfunction "2_2") (pintype "passive"))
      (node (ref "C93") (pin "-") (pinfunction "-_-") (pintype "passive"))
      (node (ref "C94") (pin "2") (pinfunction "2_2") (pintype "passive"))
      (node (ref "C95") (pin "-") (pinfunction "-_-") (pintype "passive"))
      (node (ref "C96") (pin "2") (pinfunction "2_2") (pintype "passive"))
      (node (ref "C97") (pin "-") (pinfunction "-_-") (pintype "passive"))
      (node (ref "C98") (pin "2") (pinfunction "2_2") (pintype "passive"))
      (node (ref "C99") (pin "-") (pinfunction "-_-") (pintype "passive"))
      (node (ref "JA1") (pin "16") (pinfunction "16_16") (pintype "passive"))
      (node (ref "JA2") (pin "3") (pinfunction "3_3") (pintype "passive"))
      (node (ref "JB1") (pin "16") (pinfunction "16_16") (pintype "passive"))
      (node (ref "JB2") (pin "3") (pinfunction "3_3") (pintype "passive"))
      (node (ref "JC1") (pin "16") (pinfunction "16_16") (pintype "passive"))
      (node (ref "JC2") (pin "3") (pinfunction "3_3") (pintype "passive"))
      (node (ref "JD1") (pin "16") (pinfunction "16_16") (pintype "passive"))
      (node (ref "JD2") (pin "3") (pinfunction "3_3") (pintype "passive"))
      (node (ref "U$2") (pin "AC2") (pinfunction "1_AC2") (pintype "bidirectional"))
      (node (ref "U$2") (pin "AT1") (pinfunction "1_AT1") (pintype "bidirectional"))
      (node (ref "U$2") (pin "BC2") (pinfunction "1_BC2") (pintype "bidirectional"))
      (node (ref "U$2") (pin "BT1") (pinfunction "1_BT1") (pintype "bidirectional"))
      (node (ref "U$2") (pin "CC2") (pinfunction "1_CC2") (pintype "bidirectional"))
      (node (ref "U$2") (pin "CT1") (pinfunction "1_CT1") (pintype "bidirectional"))
      (node (ref "U$2") (pin "DC2") (pinfunction "1_DC2") (pintype "bidirectional"))
      (node (ref "U$2") (pin "DT1") (pinfunction "1_DT1") (pintype "bidirectional"))
    )
    (net (code "3") (name "INHIBIT") (class "Default")
      (node (ref "JA2") (pin "13") (pinfunction "13_13") (pintype "passive"))
      (node (ref "U$2") (pin "AP2") (pinfunction "1_AP2") (pintype "bidirectional"))
    )
    (net (code "4") (name "INITIALIZE") (class "Default")
      (node (ref "JC1") (pin "14") (pinfunction "14_14") (pintype "passive"))
      (node (ref "U$2") (pin "CR1") (pinfunction "1_CR1") (pintype "bidirectional"))
    )
    (net (code "5") (name "INT_IN_PROG") (class "Default")
      (node (ref "JB2") (pin "13") (pinfunction "13_13") (pintype "passive"))
      (node (ref "U$2") (pin "BP2") (pinfunction "1_BP2") (pintype "bidirectional"))
    )
    (net (code "6") (name "INT_STROBE") (class "Default")
      (node (ref "JB2") (pin "4") (pinfunction "4_4") (pintype "passive"))
      (node (ref "U$2") (pin "BD2") (pinfunction "1_BD2") (pintype "bidirectional"))
    )
    (net (code "7") (name "Net-(IC1-Pad1)") (class "Default")
      (node (ref "IC1") (pin "1") (pinfunction "1_1") (pintype "passive"))
      (node (ref "SV1") (pin "15") (pinfunction "15_15") (pintype "passive"))
      (node (ref "SV1") (pin "16") (pinfunction "16_16") (pintype "passive"))
    )
    (net (code "8") (name "Net-(IC1-Pad2)") (class "Default")
      (node (ref "IC1") (pin "2") (pinfunction "2_2") (pintype "passive"))
      (node (ref "SV1") (pin "13") (pinfunction "13_13") (pintype "passive"))
      (node (ref "SV1") (pin "14") (pinfunction "14_14") (pintype "passive"))
    )
    (net (code "9") (name "Net-(IC1-Pad3)") (class "Default")
      (node (ref "IC1") (pin "3") (pinfunction "3_3") (pintype "passive"))
      (node (ref "SV1") (pin "11") (pinfunction "11_11") (pintype "passive"))
      (node (ref "SV1") (pin "12") (pinfunction "12_12") (pintype "passive"))
    )
    (net (code "10") (name "Net-(IC1-Pad4)") (class "Default")
      (node (ref "IC1") (pin "4") (pinfunction "4_4") (pintype "passive"))
      (node (ref "SV1") (pin "10") (pinfunction "10_10") (pintype "passive"))
      (node (ref "SV1") (pin "9") (pinfunction "9_9") (pintype "passive"))
    )
    (net (code "11") (name "Net-(IC1-Pad5)") (class "Default")
      (node (ref "IC1") (pin "5") (pinfunction "5_5") (pintype "passive"))
      (node (ref "SV1") (pin "7") (pinfunction "7_7") (pintype "passive"))
      (node (ref "SV1") (pin "8") (pinfunction "8_8") (pintype "passive"))
    )
    (net (code "12") (name "Net-(IC1-Pad6)") (class "Default")
      (node (ref "IC1") (pin "6") (pinfunction "6_6") (pintype "passive"))
      (node (ref "SV1") (pin "5") (pinfunction "5_5") (pintype "passive"))
      (node (ref "SV1") (pin "6") (pinfunction "6_6") (pintype "passive"))
    )
    (net (code "13") (name "Net-(IC1-Pad7)") (class "Default")
      (node (ref "IC1") (pin "7") (pinfunction "7_7") (pintype "passive"))
      (node (ref "SV1") (pin "3") (pinfunction "3_3") (pintype "passive"))
      (node (ref "SV1") (pin "4") (pinfunction "4_4") (pintype "passive"))
    )
    (net (code "14") (name "Net-(IC1-Pad8)") (class "Default")
      (node (ref "IC1") (pin "8") (pinfunction "8_8") (pintype "passive"))
      (node (ref "SV1") (pin "1") (pinfunction "1_1") (pintype "passive"))
      (node (ref "SV1") (pin "2") (pinfunction "2_2") (pintype "passive"))
    )
    (net (code "15") (name "Net-(IC1-Pad9)") (class "Default")
      (node (ref "IC1") (pin "9") (pinfunction "9_9") (pintype "passive"))
      (node (ref "SV2") (pin "1") (pinfunction "1_1") (pintype "passive"))
      (node (ref "SV2") (pin "2") (pinfunction "2_2") (pintype "passive"))
    )
    (net (code "16") (name "Net-(IC1-Pad10)") (class "Default")
      (node (ref "IC1") (pin "10") (pinfunction "10_10") (pintype "passive"))
      (node (ref "SV2") (pin "3") (pinfunction "3_3") (pintype "passive"))
      (node (ref "SV2") (pin "4") (pinfunction "4_4") (pintype "passive"))
    )
    (net (code "17") (name "Net-(IC1-Pad11)") (class "Default")
      (node (ref "IC1") (pin "11") (pinfunction "11_11") (pintype "passive"))
      (node (ref "SV2") (pin "5") (pinfunction "5_5") (pintype "passive"))
      (node (ref "SV2") (pin "6") (pinfunction "6_6") (pintype "passive"))
    )
    (net (code "18") (name "Net-(IC1-Pad12)") (class "Default")
      (node (ref "IC1") (pin "12") (pinfunction "12_12") (pintype "passive"))
      (node (ref "SV2") (pin "7") (pinfunction "7_7") (pintype "passive"))
      (node (ref "SV2") (pin "8") (pinfunction "8_8") (pintype "passive"))
    )
    (net (code "19") (name "Net-(IC1-Pad13)") (class "Default")
      (node (ref "IC1") (pin "13") (pinfunction "13_13") (pintype "passive"))
      (node (ref "SV2") (pin "10") (pinfunction "10_10") (pintype "passive"))
      (node (ref "SV2") (pin "9") (pinfunction "9_9") (pintype "passive"))
    )
    (net (code "20") (name "Net-(IC1-Pad14)") (class "Default")
      (node (ref "IC1") (pin "14") (pinfunction "14_14") (pintype "passive"))
      (node (ref "SV2") (pin "11") (pinfunction "11_11") (pintype "passive"))
      (node (ref "SV2") (pin "12") (pinfunction "12_12") (pintype "passive"))
    )
    (net (code "21") (name "Net-(IC1-Pad15)") (class "Default")
      (node (ref "IC1") (pin "15") (pinfunction "15_15") (pintype "passive"))
      (node (ref "SV2") (pin "13") (pinfunction "13_13") (pintype "passive"))
      (node (ref "SV2") (pin "14") (pinfunction "14_14") (pintype "passive"))
    )
    (net (code "22") (name "Net-(IC1-Pad16)") (class "Default")
      (node (ref "IC1") (pin "16") (pinfunction "16_16") (pintype "passive"))
      (node (ref "SV2") (pin "15") (pinfunction "15_15") (pintype "passive"))
      (node (ref "SV2") (pin "16") (pinfunction "16_16") (pintype "passive"))
    )
    (net (code "23") (name "Net-(IC2-Pad1)") (class "Default")
      (node (ref "IC2") (pin "1") (pinfunction "1_1") (pintype "passive"))
      (node (ref "SV3") (pin "15") (pinfunction "15_15") (pintype "passive"))
      (node (ref "SV3") (pin "16") (pinfunction "16_16") (pintype "passive"))
    )
    (net (code "24") (name "Net-(IC2-Pad2)") (class "Default")
      (node (ref "IC2") (pin "2") (pinfunction "2_2") (pintype "passive"))
      (node (ref "SV3") (pin "13") (pinfunction "13_13") (pintype "passive"))
      (node (ref "SV3") (pin "14") (pinfunction "14_14") (pintype "passive"))
    )
    (net (code "25") (name "Net-(IC2-Pad3)") (class "Default")
      (node (ref "IC2") (pin "3") (pinfunction "3_3") (pintype "passive"))
      (node (ref "SV3") (pin "11") (pinfunction "11_11") (pintype "passive"))
      (node (ref "SV3") (pin "12") (pinfunction "12_12") (pintype "passive"))
    )
    (net (code "26") (name "Net-(IC2-Pad4)") (class "Default")
      (node (ref "IC2") (pin "4") (pinfunction "4_4") (pintype "passive"))
      (node (ref "SV3") (pin "10") (pinfunction "10_10") (pintype "passive"))
      (node (ref "SV3") (pin "9") (pinfunction "9_9") (pintype "passive"))
    )
    (net (code "27") (name "Net-(IC2-Pad5)") (class "Default")
      (node (ref "IC2") (pin "5") (pinfunction "5_5") (pintype "passive"))
      (node (ref "SV3") (pin "7") (pinfunction "7_7") (pintype "passive"))
      (node (ref "SV3") (pin "8") (pinfunction "8_8") (pintype "passive"))
    )
    (net (code "28") (name "Net-(IC2-Pad6)") (class "Default")
      (node (ref "IC2") (pin "6") (pinfunction "6_6") (pintype "passive"))
      (node (ref "SV3") (pin "5") (pinfunction "5_5") (pintype "passive"))
      (node (ref "SV3") (pin "6") (pinfunction "6_6") (pintype "passive"))
    )
    (net (code "29") (name "Net-(IC2-Pad7)") (class "Default")
      (node (ref "IC2") (pin "7") (pinfunction "7_7") (pintype "passive"))
      (node (ref "SV3") (pin "3") (pinfunction "3_3") (pintype "passive"))
      (node (ref "SV3") (pin "4") (pinfunction "4_4") (pintype "passive"))
    )
    (net (code "30") (name "Net-(IC2-Pad8)") (class "Default")
      (node (ref "IC2") (pin "8") (pinfunction "8_8") (pintype "passive"))
      (node (ref "SV3") (pin "1") (pinfunction "1_1") (pintype "passive"))
      (node (ref "SV3") (pin "2") (pinfunction "2_2") (pintype "passive"))
    )
    (net (code "31") (name "Net-(IC2-Pad9)") (class "Default")
      (node (ref "IC2") (pin "9") (pinfunction "9_9") (pintype "passive"))
      (node (ref "SV4") (pin "1") (pinfunction "1_1") (pintype "passive"))
      (node (ref "SV4") (pin "2") (pinfunction "2_2") (pintype "passive"))
    )
    (net (code "32") (name "Net-(IC2-Pad10)") (class "Default")
      (node (ref "IC2") (pin "10") (pinfunction "10_10") (pintype "passive"))
      (node (ref "SV4") (pin "3") (pinfunction "3_3") (pintype "passive"))
      (node (ref "SV4") (pin "4") (pinfunction "4_4") (pintype "passive"))
    )
    (net (code "33") (name "Net-(IC2-Pad11)") (class "Default")
      (node (ref "IC2") (pin "11") (pinfunction "11_11") (pintype "passive"))
      (node (ref "SV4") (pin "5") (pinfunction "5_5") (pintype "passive"))
      (node (ref "SV4") (pin "6") (pinfunction "6_6") (pintype "passive"))
    )
    (net (code "34") (name "Net-(IC2-Pad12)") (class "Default")
      (node (ref "IC2") (pin "12") (pinfunction "12_12") (pintype "passive"))
      (node (ref "SV4") (pin "7") (pinfunction "7_7") (pintype "passive"))
      (node (ref "SV4") (pin "8") (pinfunction "8_8") (pintype "passive"))
    )
    (net (code "35") (name "Net-(IC2-Pad13)") (class "Default")
      (node (ref "IC2") (pin "13") (pinfunction "13_13") (pintype "passive"))
      (node (ref "SV4") (pin "10") (pinfunction "10_10") (pintype "passive"))
      (node (ref "SV4") (pin "9") (pinfunction "9_9") (pintype "passive"))
    )
    (net (code "36") (name "Net-(IC2-Pad14)") (class "Default")
      (node (ref "IC2") (pin "14") (pinfunction "14_14") (pintype "passive"))
      (node (ref "SV4") (pin "11") (pinfunction "11_11") (pintype "passive"))
      (node (ref "SV4") (pin "12") (pinfunction "12_12") (pintype "passive"))
    )
    (net (code "37") (name "Net-(IC2-Pad15)") (class "Default")
      (node (ref "IC2") (pin "15") (pinfunction "15_15") (pintype "passive"))
      (node (ref "SV4") (pin "13") (pinfunction "13_13") (pintype "passive"))
      (node (ref "SV4") (pin "14") (pinfunction "14_14") (pintype "passive"))
    )
    (net (code "38") (name "Net-(IC2-Pad16)") (class "Default")
      (node (ref "IC2") (pin "16") (pinfunction "16_16") (pintype "passive"))
      (node (ref "SV4") (pin "15") (pinfunction "15_15") (pintype "passive"))
      (node (ref "SV4") (pin "16") (pinfunction "16_16") (pintype "passive"))
    )
    (net (code "39") (name "Net-(IC3-Pad1)") (class "Default")
      (node (ref "IC3") (pin "1") (pinfunction "1_1") (pintype "passive"))
      (node (ref "SV5") (pin "15") (pinfunction "15_15") (pintype "passive"))
      (node (ref "SV5") (pin "16") (pinfunction "16_16") (pintype "passive"))
    )
    (net (code "40") (name "Net-(IC3-Pad2)") (class "Default")
      (node (ref "IC3") (pin "2") (pinfunction "2_2") (pintype "passive"))
      (node (ref "SV5") (pin "13") (pinfunction "13_13") (pintype "passive"))
      (node (ref "SV5") (pin "14") (pinfunction "14_14") (pintype "passive"))
    )
    (net (code "41") (name "Net-(IC3-Pad3)") (class "Default")
      (node (ref "IC3") (pin "3") (pinfunction "3_3") (pintype "passive"))
      (node (ref "SV5") (pin "11") (pinfunction "11_11") (pintype "passive"))
      (node (ref "SV5") (pin "12") (pinfunction "12_12") (pintype "passive"))
    )
    (net (code "42") (name "Net-(IC3-Pad4)") (class "Default")
      (node (ref "IC3") (pin "4") (pinfunction "4_4") (pintype "passive"))
      (node (ref "SV5") (pin "10") (pinfunction "10_10") (pintype "passive"))
      (node (ref "SV5") (pin "9") (pinfunction "9_9") (pintype "passive"))
    )
    (net (code "43") (name "Net-(IC3-Pad5)") (class "Default")
      (node (ref "IC3") (pin "5") (pinfunction "5_5") (pintype "passive"))
      (node (ref "SV5") (pin "7") (pinfunction "7_7") (pintype "passive"))
      (node (ref "SV5") (pin "8") (pinfunction "8_8") (pintype "passive"))
    )
    (net (code "44") (name "Net-(IC3-Pad6)") (class "Default")
      (node (ref "IC3") (pin "6") (pinfunction "6_6") (pintype "passive"))
      (node (ref "SV5") (pin "5") (pinfunction "5_5") (pintype "passive"))
      (node (ref "SV5") (pin "6") (pinfunction "6_6") (pintype "passive"))
    )
    (net (code "45") (name "Net-(IC3-Pad7)") (class "Default")
      (node (ref "IC3") (pin "7") (pinfunction "7_7") (pintype "passive"))
      (node (ref "SV5") (pin "3") (pinfunction "3_3") (pintype "passive"))
      (node (ref "SV5") (pin "4") (pinfunction "4_4") (pintype "passive"))
    )
    (net (code "46") (name "Net-(IC3-Pad8)") (class "Default")
      (node (ref "IC3") (pin "8") (pinfunction "8_8") (pintype "passive"))
      (node (ref "SV5") (pin "1") (pinfunction "1_1") (pintype "passive"))
      (node (ref "SV5") (pin "2") (pinfunction "2_2") (pintype "passive"))
    )
    (net (code "47") (name "Net-(IC3-Pad9)") (class "Default")
      (node (ref "IC3") (pin "9") (pinfunction "9_9") (pintype "passive"))
      (node (ref "SV6") (pin "1") (pinfunction "1_1") (pintype "passive"))
      (node (ref "SV6") (pin "2") (pinfunction "2_2") (pintype "passive"))
    )
    (net (code "48") (name "Net-(IC3-Pad10)") (class "Default")
      (node (ref "IC3") (pin "10") (pinfunction "10_10") (pintype "passive"))
      (node (ref "SV6") (pin "3") (pinfunction "3_3") (pintype "passive"))
      (node (ref "SV6") (pin "4") (pinfunction "4_4") (pintype "passive"))
    )
    (net (code "49") (name "Net-(IC3-Pad11)") (class "Default")
      (node (ref "IC3") (pin "11") (pinfunction "11_11") (pintype "passive"))
      (node (ref "SV6") (pin "5") (pinfunction "5_5") (pintype "passive"))
      (node (ref "SV6") (pin "6") (pinfunction "6_6") (pintype "passive"))
    )
    (net (code "50") (name "Net-(IC3-Pad12)") (class "Default")
      (node (ref "IC3") (pin "12") (pinfunction "12_12") (pintype "passive"))
      (node (ref "SV6") (pin "7") (pinfunction "7_7") (pintype "passive"))
      (node (ref "SV6") (pin "8") (pinfunction "8_8") (pintype "passive"))
    )
    (net (code "51") (name "Net-(IC3-Pad13)") (class "Default")
      (node (ref "IC3") (pin "13") (pinfunction "13_13") (pintype "passive"))
      (node (ref "SV6") (pin "10") (pinfunction "10_10") (pintype "passive"))
      (node (ref "SV6") (pin "9") (pinfunction "9_9") (pintype "passive"))
    )
    (net (code "52") (name "Net-(IC3-Pad14)") (class "Default")
      (node (ref "IC3") (pin "14") (pinfunction "14_14") (pintype "passive"))
      (node (ref "SV6") (pin "11") (pinfunction "11_11") (pintype "passive"))
      (node (ref "SV6") (pin "12") (pinfunction "12_12") (pintype "passive"))
    )
    (net (code "53") (name "Net-(IC3-Pad15)") (class "Default")
      (node (ref "IC3") (pin "15") (pinfunction "15_15") (pintype "passive"))
      (node (ref "SV6") (pin "13") (pinfunction "13_13") (pintype "passive"))
      (node (ref "SV6") (pin "14") (pinfunction "14_14") (pintype "passive"))
    )
    (net (code "54") (name "Net-(IC3-Pad16)") (class "Default")
      (node (ref "IC3") (pin "16") (pinfunction "16_16") (pintype "passive"))
      (node (ref "SV6") (pin "15") (pinfunction "15_15") (pintype "passive"))
      (node (ref "SV6") (pin "16") (pinfunction "16_16") (pintype "passive"))
    )
    (net (code "55") (name "Net-(IC4-Pad1)") (class "Default")
      (node (ref "IC4") (pin "1") (pinfunction "1_1") (pintype "passive"))
      (node (ref "SV7") (pin "15") (pinfunction "15_15") (pintype "passive"))
      (node (ref "SV7") (pin "16") (pinfunction "16_16") (pintype "passive"))
    )
    (net (code "56") (name "Net-(IC4-Pad2)") (class "Default")
      (node (ref "IC4") (pin "2") (pinfunction "2_2") (pintype "passive"))
      (node (ref "SV7") (pin "13") (pinfunction "13_13") (pintype "passive"))
      (node (ref "SV7") (pin "14") (pinfunction "14_14") (pintype "passive"))
    )
    (net (code "57") (name "Net-(IC4-Pad3)") (class "Default")
      (node (ref "IC4") (pin "3") (pinfunction "3_3") (pintype "passive"))
      (node (ref "SV7") (pin "11") (pinfunction "11_11") (pintype "passive"))
      (node (ref "SV7") (pin "12") (pinfunction "12_12") (pintype "passive"))
    )
    (net (code "58") (name "Net-(IC4-Pad4)") (class "Default")
      (node (ref "IC4") (pin "4") (pinfunction "4_4") (pintype "passive"))
      (node (ref "SV7") (pin "10") (pinfunction "10_10") (pintype "passive"))
      (node (ref "SV7") (pin "9") (pinfunction "9_9") (pintype "passive"))
    )
    (net (code "59") (name "Net-(IC4-Pad5)") (class "Default")
      (node (ref "IC4") (pin "5") (pinfunction "5_5") (pintype "passive"))
      (node (ref "SV7") (pin "7") (pinfunction "7_7") (pintype "passive"))
      (node (ref "SV7") (pin "8") (pinfunction "8_8") (pintype "passive"))
    )
    (net (code "60") (name "Net-(IC4-Pad6)") (class "Default")
      (node (ref "IC4") (pin "6") (pinfunction "6_6") (pintype "passive"))
      (node (ref "SV7") (pin "5") (pinfunction "5_5") (pintype "passive"))
      (node (ref "SV7") (pin "6") (pinfunction "6_6") (pintype "passive"))
    )
    (net (code "61") (name "Net-(IC4-Pad7)") (class "Default")
      (node (ref "IC4") (pin "7") (pinfunction "7_7") (pintype "passive"))
      (node (ref "SV7") (pin "3") (pinfunction "3_3") (pintype "passive"))
      (node (ref "SV7") (pin "4") (pinfunction "4_4") (pintype "passive"))
    )
    (net (code "62") (name "Net-(IC4-Pad8)") (class "Default")
      (node (ref "IC4") (pin "8") (pinfunction "8_8") (pintype "passive"))
      (node (ref "SV7") (pin "1") (pinfunction "1_1") (pintype "passive"))
      (node (ref "SV7") (pin "2") (pinfunction "2_2") (pintype "passive"))
    )
    (net (code "63") (name "Net-(IC4-Pad9)") (class "Default")
      (node (ref "IC4") (pin "9") (pinfunction "9_9") (pintype "passive"))
      (node (ref "SV8") (pin "1") (pinfunction "1_1") (pintype "passive"))
      (node (ref "SV8") (pin "2") (pinfunction "2_2") (pintype "passive"))
    )
    (net (code "64") (name "Net-(IC4-Pad10)") (class "Default")
      (node (ref "IC4") (pin "10") (pinfunction "10_10") (pintype "passive"))
      (node (ref "SV8") (pin "3") (pinfunction "3_3") (pintype "passive"))
      (node (ref "SV8") (pin "4") (pinfunction "4_4") (pintype "passive"))
    )
    (net (code "65") (name "Net-(IC4-Pad11)") (class "Default")
      (node (ref "IC4") (pin "11") (pinfunction "11_11") (pintype "passive"))
      (node (ref "SV8") (pin "5") (pinfunction "5_5") (pintype "passive"))
      (node (ref "SV8") (pin "6") (pinfunction "6_6") (pintype "passive"))
    )
    (net (code "66") (name "Net-(IC4-Pad12)") (class "Default")
      (node (ref "IC4") (pin "12") (pinfunction "12_12") (pintype "passive"))
      (node (ref "SV8") (pin "7") (pinfunction "7_7") (pintype "passive"))
      (node (ref "SV8") (pin "8") (pinfunction "8_8") (pintype "passive"))
    )
    (net (code "67") (name "Net-(IC4-Pad13)") (class "Default")
      (node (ref "IC4") (pin "13") (pinfunction "13_13") (pintype "passive"))
      (node (ref "SV8") (pin "10") (pinfunction "10_10") (pintype "passive"))
      (node (ref "SV8") (pin "9") (pinfunction "9_9") (pintype "passive"))
    )
    (net (code "68") (name "Net-(IC4-Pad14)") (class "Default")
      (node (ref "IC4") (pin "14") (pinfunction "14_14") (pintype "passive"))
      (node (ref "SV8") (pin "11") (pinfunction "11_11") (pintype "passive"))
      (node (ref "SV8") (pin "12") (pinfunction "12_12") (pintype "passive"))
    )
    (net (code "69") (name "Net-(IC4-Pad15)") (class "Default")
      (node (ref "IC4") (pin "15") (pinfunction "15_15") (pintype "passive"))
      (node (ref "SV8") (pin "13") (pinfunction "13_13") (pintype "passive"))
      (node (ref "SV8") (pin "14") (pinfunction "14_14") (pintype "passive"))
    )
    (net (code "70") (name "Net-(IC4-Pad16)") (class "Default")
      (node (ref "IC4") (pin "16") (pinfunction "16_16") (pintype "passive"))
      (node (ref "SV8") (pin "15") (pinfunction "15_15") (pintype "passive"))
      (node (ref "SV8") (pin "16") (pinfunction "16_16") (pintype "passive"))
    )
    (net (code "71") (name "Net-(IC5-Pad1)") (class "Default")
      (node (ref "IC5") (pin "1") (pinfunction "1_1") (pintype "passive"))
      (node (ref "SV9") (pin "15") (pinfunction "15_15") (pintype "passive"))
      (node (ref "SV9") (pin "16") (pinfunction "16_16") (pintype "passive"))
    )
    (net (code "72") (name "Net-(IC5-Pad2)") (class "Default")
      (node (ref "IC5") (pin "2") (pinfunction "2_2") (pintype "passive"))
      (node (ref "SV9") (pin "13") (pinfunction "13_13") (pintype "passive"))
      (node (ref "SV9") (pin "14") (pinfunction "14_14") (pintype "passive"))
    )
    (net (code "73") (name "Net-(IC5-Pad3)") (class "Default")
      (node (ref "IC5") (pin "3") (pinfunction "3_3") (pintype "passive"))
      (node (ref "SV9") (pin "11") (pinfunction "11_11") (pintype "passive"))
      (node (ref "SV9") (pin "12") (pinfunction "12_12") (pintype "passive"))
    )
    (net (code "74") (name "Net-(IC5-Pad4)") (class "Default")
      (node (ref "IC5") (pin "4") (pinfunction "4_4") (pintype "passive"))
      (node (ref "SV9") (pin "10") (pinfunction "10_10") (pintype "passive"))
      (node (ref "SV9") (pin "9") (pinfunction "9_9") (pintype "passive"))
    )
    (net (code "75") (name "Net-(IC5-Pad5)") (class "Default")
      (node (ref "IC5") (pin "5") (pinfunction "5_5") (pintype "passive"))
      (node (ref "SV9") (pin "7") (pinfunction "7_7") (pintype "passive"))
      (node (ref "SV9") (pin "8") (pinfunction "8_8") (pintype "passive"))
    )
    (net (code "76") (name "Net-(IC5-Pad6)") (class "Default")
      (node (ref "IC5") (pin "6") (pinfunction "6_6") (pintype "passive"))
      (node (ref "SV9") (pin "5") (pinfunction "5_5") (pintype "passive"))
      (node (ref "SV9") (pin "6") (pinfunction "6_6") (pintype "passive"))
    )
    (net (code "77") (name "Net-(IC5-Pad7)") (class "Default")
      (node (ref "IC5") (pin "7") (pinfunction "7_7") (pintype "passive"))
      (node (ref "SV9") (pin "3") (pinfunction "3_3") (pintype "passive"))
      (node (ref "SV9") (pin "4") (pinfunction "4_4") (pintype "passive"))
    )
    (net (code "78") (name "Net-(IC5-Pad8)") (class "Default")
      (node (ref "IC5") (pin "8") (pinfunction "8_8") (pintype "passive"))
      (node (ref "SV9") (pin "1") (pinfunction "1_1") (pintype "passive"))
      (node (ref "SV9") (pin "2") (pinfunction "2_2") (pintype "passive"))
    )
    (net (code "79") (name "Net-(IC5-Pad9)") (class "Default")
      (node (ref "IC5") (pin "9") (pinfunction "9_9") (pintype "passive"))
      (node (ref "SV10") (pin "1") (pinfunction "1_1") (pintype "passive"))
      (node (ref "SV10") (pin "2") (pinfunction "2_2") (pintype "passive"))
    )
    (net (code "80") (name "Net-(IC5-Pad10)") (class "Default")
      (node (ref "IC5") (pin "10") (pinfunction "10_10") (pintype "passive"))
      (node (ref "SV10") (pin "3") (pinfunction "3_3") (pintype "passive"))
      (node (ref "SV10") (pin "4") (pinfunction "4_4") (pintype "passive"))
    )
    (net (code "81") (name "Net-(IC5-Pad11)") (class "Default")
      (node (ref "IC5") (pin "11") (pinfunction "11_11") (pintype "passive"))
      (node (ref "SV10") (pin "5") (pinfunction "5_5") (pintype "passive"))
      (node (ref "SV10") (pin "6") (pinfunction "6_6") (pintype "passive"))
    )
    (net (code "82") (name "Net-(IC5-Pad12)") (class "Default")
      (node (ref "IC5") (pin "12") (pinfunction "12_12") (pintype "passive"))
      (node (ref "SV10") (pin "7") (pinfunction "7_7") (pintype "passive"))
      (node (ref "SV10") (pin "8") (pinfunction "8_8") (pintype "passive"))
    )
    (net (code "83") (name "Net-(IC5-Pad13)") (class "Default")
      (node (ref "IC5") (pin "13") (pinfunction "13_13") (pintype "passive"))
      (node (ref "SV10") (pin "10") (pinfunction "10_10") (pintype "passive"))
      (node (ref "SV10") (pin "9") (pinfunction "9_9") (pintype "passive"))
    )
    (net (code "84") (name "Net-(IC5-Pad14)") (class "Default")
      (node (ref "IC5") (pin "14") (pinfunction "14_14") (pintype "passive"))
      (node (ref "SV10") (pin "11") (pinfunction "11_11") (pintype "passive"))
      (node (ref "SV10") (pin "12") (pinfunction "12_12") (pintype "passive"))
    )
    (net (code "85") (name "Net-(IC5-Pad15)") (class "Default")
      (node (ref "IC5") (pin "15") (pinfunction "15_15") (pintype "passive"))
      (node (ref "SV10") (pin "13") (pinfunction "13_13") (pintype "passive"))
      (node (ref "SV10") (pin "14") (pinfunction "14_14") (pintype "passive"))
    )
    (net (code "86") (name "Net-(IC5-Pad16)") (class "Default")
      (node (ref "IC5") (pin "16") (pinfunction "16_16") (pintype "passive"))
      (node (ref "SV10") (pin "15") (pinfunction "15_15") (pintype "passive"))
      (node (ref "SV10") (pin "16") (pinfunction "16_16") (pintype "passive"))
    )
    (net (code "87") (name "Net-(IC6-Pad1)") (class "Default")
      (node (ref "IC6") (pin "1") (pinfunction "1_1") (pintype "passive"))
      (node (ref "SV11") (pin "15") (pinfunction "15_15") (pintype "passive"))
      (node (ref "SV11") (pin "16") (pinfunction "16_16") (pintype "passive"))
    )
    (net (code "88") (name "Net-(IC6-Pad2)") (class "Default")
      (node (ref "IC6") (pin "2") (pinfunction "2_2") (pintype "passive"))
      (node (ref "SV11") (pin "13") (pinfunction "13_13") (pintype "passive"))
      (node (ref "SV11") (pin "14") (pinfunction "14_14") (pintype "passive"))
    )
    (net (code "89") (name "Net-(IC6-Pad3)") (class "Default")
      (node (ref "IC6") (pin "3") (pinfunction "3_3") (pintype "passive"))
      (node (ref "SV11") (pin "11") (pinfunction "11_11") (pintype "passive"))
      (node (ref "SV11") (pin "12") (pinfunction "12_12") (pintype "passive"))
    )
    (net (code "90") (name "Net-(IC6-Pad4)") (class "Default")
      (node (ref "IC6") (pin "4") (pinfunction "4_4") (pintype "passive"))
      (node (ref "SV11") (pin "10") (pinfunction "10_10") (pintype "passive"))
      (node (ref "SV11") (pin "9") (pinfunction "9_9") (pintype "passive"))
    )
    (net (code "91") (name "Net-(IC6-Pad5)") (class "Default")
      (node (ref "IC6") (pin "5") (pinfunction "5_5") (pintype "passive"))
      (node (ref "SV11") (pin "7") (pinfunction "7_7") (pintype "passive"))
      (node (ref "SV11") (pin "8") (pinfunction "8_8") (pintype "passive"))
    )
    (net (code "92") (name "Net-(IC6-Pad6)") (class "Default")
      (node (ref "IC6") (pin "6") (pinfunction "6_6") (pintype "passive"))
      (node (ref "SV11") (pin "5") (pinfunction "5_5") (pintype "passive"))
      (node (ref "SV11") (pin "6") (pinfunction "6_6") (pintype "passive"))
    )
    (net (code "93") (name "Net-(IC6-Pad7)") (class "Default")
      (node (ref "IC6") (pin "7") (pinfunction "7_7") (pintype "passive"))
      (node (ref "SV11") (pin "3") (pinfunction "3_3") (pintype "passive"))
      (node (ref "SV11") (pin "4") (pinfunction "4_4") (pintype "passive"))
    )
    (net (code "94") (name "Net-(IC6-Pad8)") (class "Default")
      (node (ref "IC6") (pin "8") (pinfunction "8_8") (pintype "passive"))
      (node (ref "SV11") (pin "1") (pinfunction "1_1") (pintype "passive"))
      (node (ref "SV11") (pin "2") (pinfunction "2_2") (pintype "passive"))
    )
    (net (code "95") (name "Net-(IC6-Pad9)") (class "Default")
      (node (ref "IC6") (pin "9") (pinfunction "9_9") (pintype "passive"))
      (node (ref "SV12") (pin "1") (pinfunction "1_1") (pintype "passive"))
      (node (ref "SV12") (pin "2") (pinfunction "2_2") (pintype "passive"))
    )
    (net (code "96") (name "Net-(IC6-Pad10)") (class "Default")
      (node (ref "IC6") (pin "10") (pinfunction "10_10") (pintype "passive"))
      (node (ref "SV12") (pin "3") (pinfunction "3_3") (pintype "passive"))
      (node (ref "SV12") (pin "4") (pinfunction "4_4") (pintype "passive"))
    )
    (net (code "97") (name "Net-(IC6-Pad11)") (class "Default")
      (node (ref "IC6") (pin "11") (pinfunction "11_11") (pintype "passive"))
      (node (ref "SV12") (pin "5") (pinfunction "5_5") (pintype "passive"))
      (node (ref "SV12") (pin "6") (pinfunction "6_6") (pintype "passive"))
    )
    (net (code "98") (name "Net-(IC6-Pad12)") (class "Default")
      (node (ref "IC6") (pin "12") (pinfunction "12_12") (pintype "passive"))
      (node (ref "SV12") (pin "7") (pinfunction "7_7") (pintype "passive"))
      (node (ref "SV12") (pin "8") (pinfunction "8_8") (pintype "passive"))
    )
    (net (code "99") (name "Net-(IC6-Pad13)") (class "Default")
      (node (ref "IC6") (pin "13") (pinfunction "13_13") (pintype "passive"))
      (node (ref "SV12") (pin "10") (pinfunction "10_10") (pintype "passive"))
      (node (ref "SV12") (pin "9") (pinfunction "9_9") (pintype "passive"))
    )
    (net (code "100") (name "Net-(IC6-Pad14)") (class "Default")
      (node (ref "IC6") (pin "14") (pinfunction "14_14") (pintype "passive"))
      (node (ref "SV12") (pin "11") (pinfunction "11_11") (pintype "passive"))
      (node (ref "SV12") (pin "12") (pinfunction "12_12") (pintype "passive"))
    )
    (net (code "101") (name "Net-(IC6-Pad15)") (class "Default")
      (node (ref "IC6") (pin "15") (pinfunction "15_15") (pintype "passive"))
      (node (ref "SV12") (pin "13") (pinfunction "13_13") (pintype "passive"))
      (node (ref "SV12") (pin "14") (pinfunction "14_14") (pintype "passive"))
    )
    (net (code "102") (name "Net-(IC6-Pad16)") (class "Default")
      (node (ref "IC6") (pin "16") (pinfunction "16_16") (pintype "passive"))
      (node (ref "SV12") (pin "15") (pinfunction "15_15") (pintype "passive"))
      (node (ref "SV12") (pin "16") (pinfunction "16_16") (pintype "passive"))
    )
    (net (code "103") (name "Net-(IC7-Pad1)") (class "Default")
      (node (ref "IC7") (pin "1") (pinfunction "1_1") (pintype "passive"))
      (node (ref "SV13") (pin "15") (pinfunction "15_15") (pintype "passive"))
      (node (ref "SV13") (pin "16") (pinfunction "16_16") (pintype "passive"))
    )
    (net (code "104") (name "Net-(IC7-Pad2)") (class "Default")
      (node (ref "IC7") (pin "2") (pinfunction "2_2") (pintype "passive"))
      (node (ref "SV13") (pin "13") (pinfunction "13_13") (pintype "passive"))
      (node (ref "SV13") (pin "14") (pinfunction "14_14") (pintype "passive"))
    )
    (net (code "105") (name "Net-(IC7-Pad3)") (class "Default")
      (node (ref "IC7") (pin "3") (pinfunction "3_3") (pintype "passive"))
      (node (ref "SV13") (pin "11") (pinfunction "11_11") (pintype "passive"))
      (node (ref "SV13") (pin "12") (pinfunction "12_12") (pintype "passive"))
    )
    (net (code "106") (name "Net-(IC7-Pad4)") (class "Default")
      (node (ref "IC7") (pin "4") (pinfunction "4_4") (pintype "passive"))
      (node (ref "SV13") (pin "10") (pinfunction "10_10") (pintype "passive"))
      (node (ref "SV13") (pin "9") (pinfunction "9_9") (pintype "passive"))
    )
    (net (code "107") (name "Net-(IC7-Pad5)") (class "Default")
      (node (ref "IC7") (pin "5") (pinfunction "5_5") (pintype "passive"))
      (node (ref "SV13") (pin "7") (pinfunction "7_7") (pintype "passive"))
      (node (ref "SV13") (pin "8") (pinfunction "8_8") (pintype "passive"))
    )
    (net (code "108") (name "Net-(IC7-Pad6)") (class "Default")
      (node (ref "IC7") (pin "6") (pinfunction "6_6") (pintype "passive"))
      (node (ref "SV13") (pin "5") (pinfunction "5_5") (pintype "passive"))
      (node (ref "SV13") (pin "6") (pinfunction "6_6") (pintype "passive"))
    )
    (net (code "109") (name "Net-(IC7-Pad7)") (class "Default")
      (node (ref "IC7") (pin "7") (pinfunction "7_7") (pintype "passive"))
      (node (ref "SV13") (pin "3") (pinfunction "3_3") (pintype "passive"))
      (node (ref "SV13") (pin "4") (pinfunction "4_4") (pintype "passive"))
    )
    (net (code "110") (name "Net-(IC7-Pad8)") (class "Default")
      (node (ref "IC7") (pin "8") (pinfunction "8_8") (pintype "passive"))
      (node (ref "SV13") (pin "1") (pinfunction "1_1") (pintype "passive"))
      (node (ref "SV13") (pin "2") (pinfunction "2_2") (pintype "passive"))
    )
    (net (code "111") (name "Net-(IC7-Pad9)") (class "Default")
      (node (ref "IC7") (pin "9") (pinfunction "9_9") (pintype "passive"))
      (node (ref "SV14") (pin "1") (pinfunction "1_1") (pintype "passive"))
      (node (ref "SV14") (pin "2") (pinfunction "2_2") (pintype "passive"))
    )
    (net (code "112") (name "Net-(IC7-Pad10)") (class "Default")
      (node (ref "IC7") (pin "10") (pinfunction "10_10") (pintype "passive"))
      (node (ref "SV14") (pin "3") (pinfunction "3_3") (pintype "passive"))
      (node (ref "SV14") (pin "4") (pinfunction "4_4") (pintype "passive"))
    )
    (net (code "113") (name "Net-(IC7-Pad11)") (class "Default")
      (node (ref "IC7") (pin "11") (pinfunction "11_11") (pintype "passive"))
      (node (ref "SV14") (pin "5") (pinfunction "5_5") (pintype "passive"))
      (node (ref "SV14") (pin "6") (pinfunction "6_6") (pintype "passive"))
    )
    (net (code "114") (name "Net-(IC7-Pad12)") (class "Default")
      (node (ref "IC7") (pin "12") (pinfunction "12_12") (pintype "passive"))
      (node (ref "SV14") (pin "7") (pinfunction "7_7") (pintype "passive"))
      (node (ref "SV14") (pin "8") (pinfunction "8_8") (pintype "passive"))
    )
    (net (code "115") (name "Net-(IC7-Pad13)") (class "Default")
      (node (ref "IC7") (pin "13") (pinfunction "13_13") (pintype "passive"))
      (node (ref "SV14") (pin "10") (pinfunction "10_10") (pintype "passive"))
      (node (ref "SV14") (pin "9") (pinfunction "9_9") (pintype "passive"))
    )
    (net (code "116") (name "Net-(IC7-Pad14)") (class "Default")
      (node (ref "IC7") (pin "14") (pinfunction "14_14") (pintype "passive"))
      (node (ref "SV14") (pin "11") (pinfunction "11_11") (pintype "passive"))
      (node (ref "SV14") (pin "12") (pinfunction "12_12") (pintype "passive"))
    )
    (net (code "117") (name "Net-(IC7-Pad15)") (class "Default")
      (node (ref "IC7") (pin "15") (pinfunction "15_15") (pintype "passive"))
      (node (ref "SV14") (pin "13") (pinfunction "13_13") (pintype "passive"))
      (node (ref "SV14") (pin "14") (pinfunction "14_14") (pintype "passive"))
    )
    (net (code "118") (name "Net-(IC7-Pad16)") (class "Default")
      (node (ref "IC7") (pin "16") (pinfunction "16_16") (pintype "passive"))
      (node (ref "SV14") (pin "15") (pinfunction "15_15") (pintype "passive"))
      (node (ref "SV14") (pin "16") (pinfunction "16_16") (pintype "passive"))
    )
    (net (code "119") (name "Net-(IC8-Pad1)") (class "Default")
      (node (ref "IC8") (pin "1") (pinfunction "1_1") (pintype "passive"))
      (node (ref "SV15") (pin "15") (pinfunction "15_15") (pintype "passive"))
      (node (ref "SV15") (pin "16") (pinfunction "16_16") (pintype "passive"))
    )
    (net (code "120") (name "Net-(IC8-Pad2)") (class "Default")
      (node (ref "IC8") (pin "2") (pinfunction "2_2") (pintype "passive"))
      (node (ref "SV15") (pin "13") (pinfunction "13_13") (pintype "passive"))
      (node (ref "SV15") (pin "14") (pinfunction "14_14") (pintype "passive"))
    )
    (net (code "121") (name "Net-(IC8-Pad3)") (class "Default")
      (node (ref "IC8") (pin "3") (pinfunction "3_3") (pintype "passive"))
      (node (ref "SV15") (pin "11") (pinfunction "11_11") (pintype "passive"))
      (node (ref "SV15") (pin "12") (pinfunction "12_12") (pintype "passive"))
    )
    (net (code "122") (name "Net-(IC8-Pad4)") (class "Default")
      (node (ref "IC8") (pin "4") (pinfunction "4_4") (pintype "passive"))
      (node (ref "SV15") (pin "10") (pinfunction "10_10") (pintype "passive"))
      (node (ref "SV15") (pin "9") (pinfunction "9_9") (pintype "passive"))
    )
    (net (code "123") (name "Net-(IC8-Pad5)") (class "Default")
      (node (ref "IC8") (pin "5") (pinfunction "5_5") (pintype "passive"))
      (node (ref "SV15") (pin "7") (pinfunction "7_7") (pintype "passive"))
      (node (ref "SV15") (pin "8") (pinfunction "8_8") (pintype "passive"))
    )
    (net (code "124") (name "Net-(IC8-Pad6)") (class "Default")
      (node (ref "IC8") (pin "6") (pinfunction "6_6") (pintype "passive"))
      (node (ref "SV15") (pin "5") (pinfunction "5_5") (pintype "passive"))
      (node (ref "SV15") (pin "6") (pinfunction "6_6") (pintype "passive"))
    )
    (net (code "125") (name "Net-(IC8-Pad7)") (class "Default")
      (node (ref "IC8") (pin "7") (pinfunction "7_7") (pintype "passive"))
      (node (ref "SV15") (pin "3") (pinfunction "3_3") (pintype "passive"))
      (node (ref "SV15") (pin "4") (pinfunction "4_4") (pintype "passive"))
    )
    (net (code "126") (name "Net-(IC8-Pad8)") (class "Default")
      (node (ref "IC8") (pin "8") (pinfunction "8_8") (pintype "passive"))
      (node (ref "SV15") (pin "1") (pinfunction "1_1") (pintype "passive"))
      (node (ref "SV15") (pin "2") (pinfunction "2_2") (pintype "passive"))
    )
    (net (code "127") (name "Net-(IC8-Pad9)") (class "Default")
      (node (ref "IC8") (pin "9") (pinfunction "9_9") (pintype "passive"))
      (node (ref "SV16") (pin "1") (pinfunction "1_1") (pintype "passive"))
      (node (ref "SV16") (pin "2") (pinfunction "2_2") (pintype "passive"))
    )
    (net (code "128") (name "Net-(IC8-Pad10)") (class "Default")
      (node (ref "IC8") (pin "10") (pinfunction "10_10") (pintype "passive"))
      (node (ref "SV16") (pin "3") (pinfunction "3_3") (pintype "passive"))
      (node (ref "SV16") (pin "4") (pinfunction "4_4") (pintype "passive"))
    )
    (net (code "129") (name "Net-(IC8-Pad11)") (class "Default")
      (node (ref "IC8") (pin "11") (pinfunction "11_11") (pintype "passive"))
      (node (ref "SV16") (pin "5") (pinfunction "5_5") (pintype "passive"))
      (node (ref "SV16") (pin "6") (pinfunction "6_6") (pintype "passive"))
    )
    (net (code "130") (name "Net-(IC8-Pad12)") (class "Default")
      (node (ref "IC8") (pin "12") (pinfunction "12_12") (pintype "passive"))
      (node (ref "SV16") (pin "7") (pinfunction "7_7") (pintype "passive"))
      (node (ref "SV16") (pin "8") (pinfunction "8_8") (pintype "passive"))
    )
    (net (code "131") (name "Net-(IC8-Pad13)") (class "Default")
      (node (ref "IC8") (pin "13") (pinfunction "13_13") (pintype "passive"))
      (node (ref "SV16") (pin "10") (pinfunction "10_10") (pintype "passive"))
      (node (ref "SV16") (pin "9") (pinfunction "9_9") (pintype "passive"))
    )
    (net (code "132") (name "Net-(IC8-Pad14)") (class "Default")
      (node (ref "IC8") (pin "14") (pinfunction "14_14") (pintype "passive"))
      (node (ref "SV16") (pin "11") (pinfunction "11_11") (pintype "passive"))
      (node (ref "SV16") (pin "12") (pinfunction "12_12") (pintype "passive"))
    )
    (net (code "133") (name "Net-(IC8-Pad15)") (class "Default")
      (node (ref "IC8") (pin "15") (pinfunction "15_15") (pintype "passive"))
      (node (ref "SV16") (pin "13") (pinfunction "13_13") (pintype "passive"))
      (node (ref "SV16") (pin "14") (pinfunction "14_14") (pintype "passive"))
    )
    (net (code "134") (name "Net-(IC8-Pad16)") (class "Default")
      (node (ref "IC8") (pin "16") (pinfunction "16_16") (pintype "passive"))
      (node (ref "SV16") (pin "15") (pinfunction "15_15") (pintype "passive"))
      (node (ref "SV16") (pin "16") (pinfunction "16_16") (pintype "passive"))
    )
    (net (code "135") (name "Net-(IC9-Pad1)") (class "Default")
      (node (ref "IC9") (pin "1") (pinfunction "1_1") (pintype "passive"))
      (node (ref "SV17") (pin "15") (pinfunction "15_15") (pintype "passive"))
      (node (ref "SV17") (pin "16") (pinfunction "16_16") (pintype "passive"))
    )
    (net (code "136") (name "Net-(IC9-Pad2)") (class "Default")
      (node (ref "IC9") (pin "2") (pinfunction "2_2") (pintype "passive"))
      (node (ref "SV17") (pin "13") (pinfunction "13_13") (pintype "passive"))
      (node (ref "SV17") (pin "14") (pinfunction "14_14") (pintype "passive"))
    )
    (net (code "137") (name "Net-(IC9-Pad3)") (class "Default")
      (node (ref "IC9") (pin "3") (pinfunction "3_3") (pintype "passive"))
      (node (ref "SV17") (pin "11") (pinfunction "11_11") (pintype "passive"))
      (node (ref "SV17") (pin "12") (pinfunction "12_12") (pintype "passive"))
    )
    (net (code "138") (name "Net-(IC9-Pad4)") (class "Default")
      (node (ref "IC9") (pin "4") (pinfunction "4_4") (pintype "passive"))
      (node (ref "SV17") (pin "10") (pinfunction "10_10") (pintype "passive"))
      (node (ref "SV17") (pin "9") (pinfunction "9_9") (pintype "passive"))
    )
    (net (code "139") (name "Net-(IC9-Pad5)") (class "Default")
      (node (ref "IC9") (pin "5") (pinfunction "5_5") (pintype "passive"))
      (node (ref "SV17") (pin "7") (pinfunction "7_7") (pintype "passive"))
      (node (ref "SV17") (pin "8") (pinfunction "8_8") (pintype "passive"))
    )
    (net (code "140") (name "Net-(IC9-Pad6)") (class "Default")
      (node (ref "IC9") (pin "6") (pinfunction "6_6") (pintype "passive"))
      (node (ref "SV17") (pin "5") (pinfunction "5_5") (pintype "passive"))
      (node (ref "SV17") (pin "6") (pinfunction "6_6") (pintype "passive"))
    )
    (net (code "141") (name "Net-(IC9-Pad7)") (class "Default")
      (node (ref "IC9") (pin "7") (pinfunction "7_7") (pintype "passive"))
      (node (ref "SV17") (pin "3") (pinfunction "3_3") (pintype "passive"))
      (node (ref "SV17") (pin "4") (pinfunction "4_4") (pintype "passive"))
    )
    (net (code "142") (name "Net-(IC9-Pad8)") (class "Default")
      (node (ref "IC9") (pin "8") (pinfunction "8_8") (pintype "passive"))
      (node (ref "SV17") (pin "1") (pinfunction "1_1") (pintype "passive"))
      (node (ref "SV17") (pin "2") (pinfunction "2_2") (pintype "passive"))
    )
    (net (code "143") (name "Net-(IC9-Pad9)") (class "Default")
      (node (ref "IC9") (pin "9") (pinfunction "9_9") (pintype "passive"))
      (node (ref "SV18") (pin "1") (pinfunction "1_1") (pintype "passive"))
      (node (ref "SV18") (pin "2") (pinfunction "2_2") (pintype "passive"))
    )
    (net (code "144") (name "Net-(IC9-Pad10)") (class "Default")
      (node (ref "IC9") (pin "10") (pinfunction "10_10") (pintype "passive"))
      (node (ref "SV18") (pin "3") (pinfunction "3_3") (pintype "passive"))
      (node (ref "SV18") (pin "4") (pinfunction "4_4") (pintype "passive"))
    )
    (net (code "145") (name "Net-(IC9-Pad11)") (class "Default")
      (node (ref "IC9") (pin "11") (pinfunction "11_11") (pintype "passive"))
      (node (ref "SV18") (pin "5") (pinfunction "5_5") (pintype "passive"))
      (node (ref "SV18") (pin "6") (pinfunction "6_6") (pintype "passive"))
    )
    (net (code "146") (name "Net-(IC9-Pad12)") (class "Default")
      (node (ref "IC9") (pin "12") (pinfunction "12_12") (pintype "passive"))
      (node (ref "SV18") (pin "7") (pinfunction "7_7") (pintype "passive"))
      (node (ref "SV18") (pin "8") (pinfunction "8_8") (pintype "passive"))
    )
    (net (code "147") (name "Net-(IC9-Pad13)") (class "Default")
      (node (ref "IC9") (pin "13") (pinfunction "13_13") (pintype "passive"))
      (node (ref "SV18") (pin "10") (pinfunction "10_10") (pintype "passive"))
      (node (ref "SV18") (pin "9") (pinfunction "9_9") (pintype "passive"))
    )
    (net (code "148") (name "Net-(IC9-Pad14)") (class "Default")
      (node (ref "IC9") (pin "14") (pinfunction "14_14") (pintype "passive"))
      (node (ref "SV18") (pin "11") (pinfunction "11_11") (pintype "passive"))
      (node (ref "SV18") (pin "12") (pinfunction "12_12") (pintype "passive"))
    )
    (net (code "149") (name "Net-(IC9-Pad15)") (class "Default")
      (node (ref "IC9") (pin "15") (pinfunction "15_15") (pintype "passive"))
      (node (ref "SV18") (pin "13") (pinfunction "13_13") (pintype "passive"))
      (node (ref "SV18") (pin "14") (pinfunction "14_14") (pintype "passive"))
    )
    (net (code "150") (name "Net-(IC9-Pad16)") (class "Default")
      (node (ref "IC9") (pin "16") (pinfunction "16_16") (pintype "passive"))
      (node (ref "SV18") (pin "15") (pinfunction "15_15") (pintype "passive"))
      (node (ref "SV18") (pin "16") (pinfunction "16_16") (pintype "passive"))
    )
    (net (code "151") (name "Net-(IC10-Pad1)") (class "Default")
      (node (ref "IC10") (pin "1") (pinfunction "1_1") (pintype "passive"))
      (node (ref "SV19") (pin "15") (pinfunction "15_15") (pintype "passive"))
      (node (ref "SV19") (pin "16") (pinfunction "16_16") (pintype "passive"))
    )
    (net (code "152") (name "Net-(IC10-Pad2)") (class "Default")
      (node (ref "IC10") (pin "2") (pinfunction "2_2") (pintype "passive"))
      (node (ref "SV19") (pin "13") (pinfunction "13_13") (pintype "passive"))
      (node (ref "SV19") (pin "14") (pinfunction "14_14") (pintype "passive"))
    )
    (net (code "153") (name "Net-(IC10-Pad3)") (class "Default")
      (node (ref "IC10") (pin "3") (pinfunction "3_3") (pintype "passive"))
      (node (ref "SV19") (pin "11") (pinfunction "11_11") (pintype "passive"))
      (node (ref "SV19") (pin "12") (pinfunction "12_12") (pintype "passive"))
    )
    (net (code "154") (name "Net-(IC10-Pad4)") (class "Default")
      (node (ref "IC10") (pin "4") (pinfunction "4_4") (pintype "passive"))
      (node (ref "SV19") (pin "10") (pinfunction "10_10") (pintype "passive"))
      (node (ref "SV19") (pin "9") (pinfunction "9_9") (pintype "passive"))
    )
    (net (code "155") (name "Net-(IC10-Pad5)") (class "Default")
      (node (ref "IC10") (pin "5") (pinfunction "5_5") (pintype "passive"))
      (node (ref "SV19") (pin "7") (pinfunction "7_7") (pintype "passive"))
      (node (ref "SV19") (pin "8") (pinfunction "8_8") (pintype "passive"))
    )
    (net (code "156") (name "Net-(IC10-Pad6)") (class "Default")
      (node (ref "IC10") (pin "6") (pinfunction "6_6") (pintype "passive"))
      (node (ref "SV19") (pin "5") (pinfunction "5_5") (pintype "passive"))
      (node (ref "SV19") (pin "6") (pinfunction "6_6") (pintype "passive"))
    )
    (net (code "157") (name "Net-(IC10-Pad7)") (class "Default")
      (node (ref "IC10") (pin "7") (pinfunction "7_7") (pintype "passive"))
      (node (ref "SV19") (pin "3") (pinfunction "3_3") (pintype "passive"))
      (node (ref "SV19") (pin "4") (pinfunction "4_4") (pintype "passive"))
    )
    (net (code "158") (name "Net-(IC10-Pad8)") (class "Default")
      (node (ref "IC10") (pin "8") (pinfunction "8_8") (pintype "passive"))
      (node (ref "SV19") (pin "1") (pinfunction "1_1") (pintype "passive"))
      (node (ref "SV19") (pin "2") (pinfunction "2_2") (pintype "passive"))
    )
    (net (code "159") (name "Net-(IC10-Pad9)") (class "Default")
      (node (ref "IC10") (pin "9") (pinfunction "9_9") (pintype "passive"))
      (node (ref "SV20") (pin "1") (pinfunction "1_1") (pintype "passive"))
      (node (ref "SV20") (pin "2") (pinfunction "2_2") (pintype "passive"))
    )
    (net (code "160") (name "Net-(IC10-Pad10)") (class "Default")
      (node (ref "IC10") (pin "10") (pinfunction "10_10") (pintype "passive"))
      (node (ref "SV20") (pin "3") (pinfunction "3_3") (pintype "passive"))
      (node (ref "SV20") (pin "4") (pinfunction "4_4") (pintype "passive"))
    )
    (net (code "161") (name "Net-(IC10-Pad11)") (class "Default")
      (node (ref "IC10") (pin "11") (pinfunction "11_11") (pintype "passive"))
      (node (ref "SV20") (pin "5") (pinfunction "5_5") (pintype "passive"))
      (node (ref "SV20") (pin "6") (pinfunction "6_6") (pintype "passive"))
    )
    (net (code "162") (name "Net-(IC10-Pad12)") (class "Default")
      (node (ref "IC10") (pin "12") (pinfunction "12_12") (pintype "passive"))
      (node (ref "SV20") (pin "7") (pinfunction "7_7") (pintype "passive"))
      (node (ref "SV20") (pin "8") (pinfunction "8_8") (pintype "passive"))
    )
    (net (code "163") (name "Net-(IC10-Pad13)") (class "Default")
      (node (ref "IC10") (pin "13") (pinfunction "13_13") (pintype "passive"))
      (node (ref "SV20") (pin "10") (pinfunction "10_10") (pintype "passive"))
      (node (ref "SV20") (pin "9") (pinfunction "9_9") (pintype "passive"))
    )
    (net (code "164") (name "Net-(IC10-Pad14)") (class "Default")
      (node (ref "IC10") (pin "14") (pinfunction "14_14") (pintype "passive"))
      (node (ref "SV20") (pin "11") (pinfunction "11_11") (pintype "passive"))
      (node (ref "SV20") (pin "12") (pinfunction "12_12") (pintype "passive"))
    )
    (net (code "165") (name "Net-(IC10-Pad15)") (class "Default")
      (node (ref "IC10") (pin "15") (pinfunction "15_15") (pintype "passive"))
      (node (ref "SV20") (pin "13") (pinfunction "13_13") (pintype "passive"))
      (node (ref "SV20") (pin "14") (pinfunction "14_14") (pintype "passive"))
    )
    (net (code "166") (name "Net-(IC10-Pad16)") (class "Default")
      (node (ref "IC10") (pin "16") (pinfunction "16_16") (pintype "passive"))
      (node (ref "SV20") (pin "15") (pinfunction "15_15") (pintype "passive"))
      (node (ref "SV20") (pin "16") (pinfunction "16_16") (pintype "passive"))
    )
    (net (code "167") (name "Net-(IC11-Pad1)") (class "Default")
      (node (ref "IC11") (pin "1") (pinfunction "1_1") (pintype "passive"))
      (node (ref "SV21") (pin "15") (pinfunction "15_15") (pintype "passive"))
      (node (ref "SV21") (pin "16") (pinfunction "16_16") (pintype "passive"))
    )
    (net (code "168") (name "Net-(IC11-Pad2)") (class "Default")
      (node (ref "IC11") (pin "2") (pinfunction "2_2") (pintype "passive"))
      (node (ref "SV21") (pin "13") (pinfunction "13_13") (pintype "passive"))
      (node (ref "SV21") (pin "14") (pinfunction "14_14") (pintype "passive"))
    )
    (net (code "169") (name "Net-(IC11-Pad3)") (class "Default")
      (node (ref "IC11") (pin "3") (pinfunction "3_3") (pintype "passive"))
      (node (ref "SV21") (pin "11") (pinfunction "11_11") (pintype "passive"))
      (node (ref "SV21") (pin "12") (pinfunction "12_12") (pintype "passive"))
    )
    (net (code "170") (name "Net-(IC11-Pad4)") (class "Default")
      (node (ref "IC11") (pin "4") (pinfunction "4_4") (pintype "passive"))
      (node (ref "SV21") (pin "10") (pinfunction "10_10") (pintype "passive"))
      (node (ref "SV21") (pin "9") (pinfunction "9_9") (pintype "passive"))
    )
    (net (code "171") (name "Net-(IC11-Pad5)") (class "Default")
      (node (ref "IC11") (pin "5") (pinfunction "5_5") (pintype "passive"))
      (node (ref "SV21") (pin "7") (pinfunction "7_7") (pintype "passive"))
      (node (ref "SV21") (pin "8") (pinfunction "8_8") (pintype "passive"))
    )
    (net (code "172") (name "Net-(IC11-Pad6)") (class "Default")
      (node (ref "IC11") (pin "6") (pinfunction "6_6") (pintype "passive"))
      (node (ref "SV21") (pin "5") (pinfunction "5_5") (pintype "passive"))
      (node (ref "SV21") (pin "6") (pinfunction "6_6") (pintype "passive"))
    )
    (net (code "173") (name "Net-(IC11-Pad7)") (class "Default")
      (node (ref "IC11") (pin "7") (pinfunction "7_7") (pintype "passive"))
      (node (ref "SV21") (pin "3") (pinfunction "3_3") (pintype "passive"))
      (node (ref "SV21") (pin "4") (pinfunction "4_4") (pintype "passive"))
    )
    (net (code "174") (name "Net-(IC11-Pad8)") (class "Default")
      (node (ref "IC11") (pin "8") (pinfunction "8_8") (pintype "passive"))
      (node (ref "SV21") (pin "1") (pinfunction "1_1") (pintype "passive"))
      (node (ref "SV21") (pin "2") (pinfunction "2_2") (pintype "passive"))
    )
    (net (code "175") (name "Net-(IC11-Pad9)") (class "Default")
      (node (ref "IC11") (pin "9") (pinfunction "9_9") (pintype "passive"))
      (node (ref "SV22") (pin "1") (pinfunction "1_1") (pintype "passive"))
      (node (ref "SV22") (pin "2") (pinfunction "2_2") (pintype "passive"))
    )
    (net (code "176") (name "Net-(IC11-Pad10)") (class "Default")
      (node (ref "IC11") (pin "10") (pinfunction "10_10") (pintype "passive"))
      (node (ref "SV22") (pin "3") (pinfunction "3_3") (pintype "passive"))
      (node (ref "SV22") (pin "4") (pinfunction "4_4") (pintype "passive"))
    )
    (net (code "177") (name "Net-(IC11-Pad11)") (class "Default")
      (node (ref "IC11") (pin "11") (pinfunction "11_11") (pintype "passive"))
      (node (ref "SV22") (pin "5") (pinfunction "5_5") (pintype "passive"))
      (node (ref "SV22") (pin "6") (pinfunction "6_6") (pintype "passive"))
    )
    (net (code "178") (name "Net-(IC11-Pad12)") (class "Default")
      (node (ref "IC11") (pin "12") (pinfunction "12_12") (pintype "passive"))
      (node (ref "SV22") (pin "7") (pinfunction "7_7") (pintype "passive"))
      (node (ref "SV22") (pin "8") (pinfunction "8_8") (pintype "passive"))
    )
    (net (code "179") (name "Net-(IC11-Pad13)") (class "Default")
      (node (ref "IC11") (pin "13") (pinfunction "13_13") (pintype "passive"))
      (node (ref "SV22") (pin "10") (pinfunction "10_10") (pintype "passive"))
      (node (ref "SV22") (pin "9") (pinfunction "9_9") (pintype "passive"))
    )
    (net (code "180") (name "Net-(IC11-Pad14)") (class "Default")
      (node (ref "IC11") (pin "14") (pinfunction "14_14") (pintype "passive"))
      (node (ref "SV22") (pin "11") (pinfunction "11_11") (pintype "passive"))
      (node (ref "SV22") (pin "12") (pinfunction "12_12") (pintype "passive"))
    )
    (net (code "181") (name "Net-(IC11-Pad15)") (class "Default")
      (node (ref "IC11") (pin "15") (pinfunction "15_15") (pintype "passive"))
      (node (ref "SV22") (pin "13") (pinfunction "13_13") (pintype "passive"))
      (node (ref "SV22") (pin "14") (pinfunction "14_14") (pintype "passive"))
    )
    (net (code "182") (name "Net-(IC11-Pad16)") (class "Default")
      (node (ref "IC11") (pin "16") (pinfunction "16_16") (pintype "passive"))
      (node (ref "SV22") (pin "15") (pinfunction "15_15") (pintype "passive"))
      (node (ref "SV22") (pin "16") (pinfunction "16_16") (pintype "passive"))
    )
    (net (code "183") (name "Net-(IC12-Pad1)") (class "Default")
      (node (ref "IC12") (pin "1") (pinfunction "1_1") (pintype "passive"))
      (node (ref "SV23") (pin "15") (pinfunction "15_15") (pintype "passive"))
      (node (ref "SV23") (pin "16") (pinfunction "16_16") (pintype "passive"))
    )
    (net (code "184") (name "Net-(IC12-Pad2)") (class "Default")
      (node (ref "IC12") (pin "2") (pinfunction "2_2") (pintype "passive"))
      (node (ref "SV23") (pin "13") (pinfunction "13_13") (pintype "passive"))
      (node (ref "SV23") (pin "14") (pinfunction "14_14") (pintype "passive"))
    )
    (net (code "185") (name "Net-(IC12-Pad3)") (class "Default")
      (node (ref "IC12") (pin "3") (pinfunction "3_3") (pintype "passive"))
      (node (ref "SV23") (pin "11") (pinfunction "11_11") (pintype "passive"))
      (node (ref "SV23") (pin "12") (pinfunction "12_12") (pintype "passive"))
    )
    (net (code "186") (name "Net-(IC12-Pad4)") (class "Default")
      (node (ref "IC12") (pin "4") (pinfunction "4_4") (pintype "passive"))
      (node (ref "SV23") (pin "10") (pinfunction "10_10") (pintype "passive"))
      (node (ref "SV23") (pin "9") (pinfunction "9_9") (pintype "passive"))
    )
    (net (code "187") (name "Net-(IC12-Pad5)") (class "Default")
      (node (ref "IC12") (pin "5") (pinfunction "5_5") (pintype "passive"))
      (node (ref "SV23") (pin "7") (pinfunction "7_7") (pintype "passive"))
      (node (ref "SV23") (pin "8") (pinfunction "8_8") (pintype "passive"))
    )
    (net (code "188") (name "Net-(IC12-Pad6)") (class "Default")
      (node (ref "IC12") (pin "6") (pinfunction "6_6") (pintype "passive"))
      (node (ref "SV23") (pin "5") (pinfunction "5_5") (pintype "passive"))
      (node (ref "SV23") (pin "6") (pinfunction "6_6") (pintype "passive"))
    )
    (net (code "189") (name "Net-(IC12-Pad7)") (class "Default")
      (node (ref "IC12") (pin "7") (pinfunction "7_7") (pintype "passive"))
      (node (ref "SV23") (pin "3") (pinfunction "3_3") (pintype "passive"))
      (node (ref "SV23") (pin "4") (pinfunction "4_4") (pintype "passive"))
    )
    (net (code "190") (name "Net-(IC12-Pad8)") (class "Default")
      (node (ref "IC12") (pin "8") (pinfunction "8_8") (pintype "passive"))
      (node (ref "SV23") (pin "1") (pinfunction "1_1") (pintype "passive"))
      (node (ref "SV23") (pin "2") (pinfunction "2_2") (pintype "passive"))
    )
    (net (code "191") (name "Net-(IC12-Pad9)") (class "Default")
      (node (ref "IC12") (pin "9") (pinfunction "9_9") (pintype "passive"))
      (node (ref "SV24") (pin "1") (pinfunction "1_1") (pintype "passive"))
      (node (ref "SV24") (pin "2") (pinfunction "2_2") (pintype "passive"))
    )
    (net (code "192") (name "Net-(IC12-Pad10)") (class "Default")
      (node (ref "IC12") (pin "10") (pinfunction "10_10") (pintype "passive"))
      (node (ref "SV24") (pin "3") (pinfunction "3_3") (pintype "passive"))
      (node (ref "SV24") (pin "4") (pinfunction "4_4") (pintype "passive"))
    )
    (net (code "193") (name "Net-(IC12-Pad11)") (class "Default")
      (node (ref "IC12") (pin "11") (pinfunction "11_11") (pintype "passive"))
      (node (ref "SV24") (pin "5") (pinfunction "5_5") (pintype "passive"))
      (node (ref "SV24") (pin "6") (pinfunction "6_6") (pintype "passive"))
    )
    (net (code "194") (name "Net-(IC12-Pad12)") (class "Default")
      (node (ref "IC12") (pin "12") (pinfunction "12_12") (pintype "passive"))
      (node (ref "SV24") (pin "7") (pinfunction "7_7") (pintype "passive"))
      (node (ref "SV24") (pin "8") (pinfunction "8_8") (pintype "passive"))
    )
    (net (code "195") (name "Net-(IC12-Pad13)") (class "Default")
      (node (ref "IC12") (pin "13") (pinfunction "13_13") (pintype "passive"))
      (node (ref "SV24") (pin "10") (pinfunction "10_10") (pintype "passive"))
      (node (ref "SV24") (pin "9") (pinfunction "9_9") (pintype "passive"))
    )
    (net (code "196") (name "Net-(IC12-Pad14)") (class "Default")
      (node (ref "IC12") (pin "14") (pinfunction "14_14") (pintype "passive"))
      (node (ref "SV24") (pin "11") (pinfunction "11_11") (pintype "passive"))
      (node (ref "SV24") (pin "12") (pinfunction "12_12") (pintype "passive"))
    )
    (net (code "197") (name "Net-(IC12-Pad15)") (class "Default")
      (node (ref "IC12") (pin "15") (pinfunction "15_15") (pintype "passive"))
      (node (ref "SV24") (pin "13") (pinfunction "13_13") (pintype "passive"))
      (node (ref "SV24") (pin "14") (pinfunction "14_14") (pintype "passive"))
    )
    (net (code "198") (name "Net-(IC12-Pad16)") (class "Default")
      (node (ref "IC12") (pin "16") (pinfunction "16_16") (pintype "passive"))
      (node (ref "SV24") (pin "15") (pinfunction "15_15") (pintype "passive"))
      (node (ref "SV24") (pin "16") (pinfunction "16_16") (pintype "passive"))
    )
    (net (code "199") (name "Net-(IC13-Pad1)") (class "Default")
      (node (ref "IC13") (pin "1") (pinfunction "1_1") (pintype "passive"))
      (node (ref "SV25") (pin "15") (pinfunction "15_15") (pintype "passive"))
      (node (ref "SV25") (pin "16") (pinfunction "16_16") (pintype "passive"))
    )
    (net (code "200") (name "Net-(IC13-Pad2)") (class "Default")
      (node (ref "IC13") (pin "2") (pinfunction "2_2") (pintype "passive"))
      (node (ref "SV25") (pin "13") (pinfunction "13_13") (pintype "passive"))
      (node (ref "SV25") (pin "14") (pinfunction "14_14") (pintype "passive"))
    )
    (net (code "201") (name "Net-(IC13-Pad3)") (class "Default")
      (node (ref "IC13") (pin "3") (pinfunction "3_3") (pintype "passive"))
      (node (ref "SV25") (pin "11") (pinfunction "11_11") (pintype "passive"))
      (node (ref "SV25") (pin "12") (pinfunction "12_12") (pintype "passive"))
    )
    (net (code "202") (name "Net-(IC13-Pad4)") (class "Default")
      (node (ref "IC13") (pin "4") (pinfunction "4_4") (pintype "passive"))
      (node (ref "SV25") (pin "10") (pinfunction "10_10") (pintype "passive"))
      (node (ref "SV25") (pin "9") (pinfunction "9_9") (pintype "passive"))
    )
    (net (code "203") (name "Net-(IC13-Pad5)") (class "Default")
      (node (ref "IC13") (pin "5") (pinfunction "5_5") (pintype "passive"))
      (node (ref "SV25") (pin "7") (pinfunction "7_7") (pintype "passive"))
      (node (ref "SV25") (pin "8") (pinfunction "8_8") (pintype "passive"))
    )
    (net (code "204") (name "Net-(IC13-Pad6)") (class "Default")
      (node (ref "IC13") (pin "6") (pinfunction "6_6") (pintype "passive"))
      (node (ref "SV25") (pin "5") (pinfunction "5_5") (pintype "passive"))
      (node (ref "SV25") (pin "6") (pinfunction "6_6") (pintype "passive"))
    )
    (net (code "205") (name "Net-(IC13-Pad7)") (class "Default")
      (node (ref "IC13") (pin "7") (pinfunction "7_7") (pintype "passive"))
      (node (ref "SV25") (pin "3") (pinfunction "3_3") (pintype "passive"))
      (node (ref "SV25") (pin "4") (pinfunction "4_4") (pintype "passive"))
    )
    (net (code "206") (name "Net-(IC13-Pad8)") (class "Default")
      (node (ref "IC13") (pin "8") (pinfunction "8_8") (pintype "passive"))
      (node (ref "SV25") (pin "1") (pinfunction "1_1") (pintype "passive"))
      (node (ref "SV25") (pin "2") (pinfunction "2_2") (pintype "passive"))
    )
    (net (code "207") (name "Net-(IC13-Pad9)") (class "Default")
      (node (ref "IC13") (pin "9") (pinfunction "9_9") (pintype "passive"))
      (node (ref "SV26") (pin "1") (pinfunction "1_1") (pintype "passive"))
      (node (ref "SV26") (pin "2") (pinfunction "2_2") (pintype "passive"))
    )
    (net (code "208") (name "Net-(IC13-Pad10)") (class "Default")
      (node (ref "IC13") (pin "10") (pinfunction "10_10") (pintype "passive"))
      (node (ref "SV26") (pin "3") (pinfunction "3_3") (pintype "passive"))
      (node (ref "SV26") (pin "4") (pinfunction "4_4") (pintype "passive"))
    )
    (net (code "209") (name "Net-(IC13-Pad11)") (class "Default")
      (node (ref "IC13") (pin "11") (pinfunction "11_11") (pintype "passive"))
      (node (ref "SV26") (pin "5") (pinfunction "5_5") (pintype "passive"))
      (node (ref "SV26") (pin "6") (pinfunction "6_6") (pintype "passive"))
    )
    (net (code "210") (name "Net-(IC13-Pad12)") (class "Default")
      (node (ref "IC13") (pin "12") (pinfunction "12_12") (pintype "passive"))
      (node (ref "SV26") (pin "7") (pinfunction "7_7") (pintype "passive"))
      (node (ref "SV26") (pin "8") (pinfunction "8_8") (pintype "passive"))
    )
    (net (code "211") (name "Net-(IC13-Pad13)") (class "Default")
      (node (ref "IC13") (pin "13") (pinfunction "13_13") (pintype "passive"))
      (node (ref "SV26") (pin "10") (pinfunction "10_10") (pintype "passive"))
      (node (ref "SV26") (pin "9") (pinfunction "9_9") (pintype "passive"))
    )
    (net (code "212") (name "Net-(IC13-Pad14)") (class "Default")
      (node (ref "IC13") (pin "14") (pinfunction "14_14") (pintype "passive"))
      (node (ref "SV26") (pin "11") (pinfunction "11_11") (pintype "passive"))
      (node (ref "SV26") (pin "12") (pinfunction "12_12") (pintype "passive"))
    )
    (net (code "213") (name "Net-(IC13-Pad15)") (class "Default")
      (node (ref "IC13") (pin "15") (pinfunction "15_15") (pintype "passive"))
      (node (ref "SV26") (pin "13") (pinfunction "13_13") (pintype "passive"))
      (node (ref "SV26") (pin "14") (pinfunction "14_14") (pintype "passive"))
    )
    (net (code "214") (name "Net-(IC13-Pad16)") (class "Default")
      (node (ref "IC13") (pin "16") (pinfunction "16_16") (pintype "passive"))
      (node (ref "SV26") (pin "15") (pinfunction "15_15") (pintype "passive"))
      (node (ref "SV26") (pin "16") (pinfunction "16_16") (pintype "passive"))
    )
    (net (code "215") (name "Net-(IC14-Pad1)") (class "Default")
      (node (ref "IC14") (pin "1") (pinfunction "1_1") (pintype "passive"))
      (node (ref "SV27") (pin "15") (pinfunction "15_15") (pintype "passive"))
      (node (ref "SV27") (pin "16") (pinfunction "16_16") (pintype "passive"))
    )
    (net (code "216") (name "Net-(IC14-Pad2)") (class "Default")
      (node (ref "IC14") (pin "2") (pinfunction "2_2") (pintype "passive"))
      (node (ref "SV27") (pin "13") (pinfunction "13_13") (pintype "passive"))
      (node (ref "SV27") (pin "14") (pinfunction "14_14") (pintype "passive"))
    )
    (net (code "217") (name "Net-(IC14-Pad3)") (class "Default")
      (node (ref "IC14") (pin "3") (pinfunction "3_3") (pintype "passive"))
      (node (ref "SV27") (pin "11") (pinfunction "11_11") (pintype "passive"))
      (node (ref "SV27") (pin "12") (pinfunction "12_12") (pintype "passive"))
    )
    (net (code "218") (name "Net-(IC14-Pad4)") (class "Default")
      (node (ref "IC14") (pin "4") (pinfunction "4_4") (pintype "passive"))
      (node (ref "SV27") (pin "10") (pinfunction "10_10") (pintype "passive"))
      (node (ref "SV27") (pin "9") (pinfunction "9_9") (pintype "passive"))
    )
    (net (code "219") (name "Net-(IC14-Pad5)") (class "Default")
      (node (ref "IC14") (pin "5") (pinfunction "5_5") (pintype "passive"))
      (node (ref "SV27") (pin "7") (pinfunction "7_7") (pintype "passive"))
      (node (ref "SV27") (pin "8") (pinfunction "8_8") (pintype "passive"))
    )
    (net (code "220") (name "Net-(IC14-Pad6)") (class "Default")
      (node (ref "IC14") (pin "6") (pinfunction "6_6") (pintype "passive"))
      (node (ref "SV27") (pin "5") (pinfunction "5_5") (pintype "passive"))
      (node (ref "SV27") (pin "6") (pinfunction "6_6") (pintype "passive"))
    )
    (net (code "221") (name "Net-(IC14-Pad7)") (class "Default")
      (node (ref "IC14") (pin "7") (pinfunction "7_7") (pintype "passive"))
      (node (ref "SV27") (pin "3") (pinfunction "3_3") (pintype "passive"))
      (node (ref "SV27") (pin "4") (pinfunction "4_4") (pintype "passive"))
    )
    (net (code "222") (name "Net-(IC14-Pad8)") (class "Default")
      (node (ref "IC14") (pin "8") (pinfunction "8_8") (pintype "passive"))
      (node (ref "SV27") (pin "1") (pinfunction "1_1") (pintype "passive"))
      (node (ref "SV27") (pin "2") (pinfunction "2_2") (pintype "passive"))
    )
    (net (code "223") (name "Net-(IC14-Pad9)") (class "Default")
      (node (ref "IC14") (pin "9") (pinfunction "9_9") (pintype "passive"))
      (node (ref "SV28") (pin "1") (pinfunction "1_1") (pintype "passive"))
      (node (ref "SV28") (pin "2") (pinfunction "2_2") (pintype "passive"))
    )
    (net (code "224") (name "Net-(IC14-Pad10)") (class "Default")
      (node (ref "IC14") (pin "10") (pinfunction "10_10") (pintype "passive"))
      (node (ref "SV28") (pin "3") (pinfunction "3_3") (pintype "passive"))
      (node (ref "SV28") (pin "4") (pinfunction "4_4") (pintype "passive"))
    )
    (net (code "225") (name "Net-(IC14-Pad11)") (class "Default")
      (node (ref "IC14") (pin "11") (pinfunction "11_11") (pintype "passive"))
      (node (ref "SV28") (pin "5") (pinfunction "5_5") (pintype "passive"))
      (node (ref "SV28") (pin "6") (pinfunction "6_6") (pintype "passive"))
    )
    (net (code "226") (name "Net-(IC14-Pad12)") (class "Default")
      (node (ref "IC14") (pin "12") (pinfunction "12_12") (pintype "passive"))
      (node (ref "SV28") (pin "7") (pinfunction "7_7") (pintype "passive"))
      (node (ref "SV28") (pin "8") (pinfunction "8_8") (pintype "passive"))
    )
    (net (code "227") (name "Net-(IC14-Pad13)") (class "Default")
      (node (ref "IC14") (pin "13") (pinfunction "13_13") (pintype "passive"))
      (node (ref "SV28") (pin "10") (pinfunction "10_10") (pintype "passive"))
      (node (ref "SV28") (pin "9") (pinfunction "9_9") (pintype "passive"))
    )
    (net (code "228") (name "Net-(IC14-Pad14)") (class "Default")
      (node (ref "IC14") (pin "14") (pinfunction "14_14") (pintype "passive"))
      (node (ref "SV28") (pin "11") (pinfunction "11_11") (pintype "passive"))
      (node (ref "SV28") (pin "12") (pinfunction "12_12") (pintype "passive"))
    )
    (net (code "229") (name "Net-(IC14-Pad15)") (class "Default")
      (node (ref "IC14") (pin "15") (pinfunction "15_15") (pintype "passive"))
      (node (ref "SV28") (pin "13") (pinfunction "13_13") (pintype "passive"))
      (node (ref "SV28") (pin "14") (pinfunction "14_14") (pintype "passive"))
    )
    (net (code "230") (name "Net-(IC14-Pad16)") (class "Default")
      (node (ref "IC14") (pin "16") (pinfunction "16_16") (pintype "passive"))
      (node (ref "SV28") (pin "15") (pinfunction "15_15") (pintype "passive"))
      (node (ref "SV28") (pin "16") (pinfunction "16_16") (pintype "passive"))
    )
    (net (code "231") (name "Net-(IC15-Pad1)") (class "Default")
      (node (ref "IC15") (pin "1") (pinfunction "1_1") (pintype "passive"))
      (node (ref "SV29") (pin "15") (pinfunction "15_15") (pintype "passive"))
      (node (ref "SV29") (pin "16") (pinfunction "16_16") (pintype "passive"))
    )
    (net (code "232") (name "Net-(IC15-Pad2)") (class "Default")
      (node (ref "IC15") (pin "2") (pinfunction "2_2") (pintype "passive"))
      (node (ref "SV29") (pin "13") (pinfunction "13_13") (pintype "passive"))
      (node (ref "SV29") (pin "14") (pinfunction "14_14") (pintype "passive"))
    )
    (net (code "233") (name "Net-(IC15-Pad3)") (class "Default")
      (node (ref "IC15") (pin "3") (pinfunction "3_3") (pintype "passive"))
      (node (ref "SV29") (pin "11") (pinfunction "11_11") (pintype "passive"))
      (node (ref "SV29") (pin "12") (pinfunction "12_12") (pintype "passive"))
    )
    (net (code "234") (name "Net-(IC15-Pad4)") (class "Default")
      (node (ref "IC15") (pin "4") (pinfunction "4_4") (pintype "passive"))
      (node (ref "SV29") (pin "10") (pinfunction "10_10") (pintype "passive"))
      (node (ref "SV29") (pin "9") (pinfunction "9_9") (pintype "passive"))
    )
    (net (code "235") (name "Net-(IC15-Pad5)") (class "Default")
      (node (ref "IC15") (pin "5") (pinfunction "5_5") (pintype "passive"))
      (node (ref "SV29") (pin "7") (pinfunction "7_7") (pintype "passive"))
      (node (ref "SV29") (pin "8") (pinfunction "8_8") (pintype "passive"))
    )
    (net (code "236") (name "Net-(IC15-Pad6)") (class "Default")
      (node (ref "IC15") (pin "6") (pinfunction "6_6") (pintype "passive"))
      (node (ref "SV29") (pin "5") (pinfunction "5_5") (pintype "passive"))
      (node (ref "SV29") (pin "6") (pinfunction "6_6") (pintype "passive"))
    )
    (net (code "237") (name "Net-(IC15-Pad7)") (class "Default")
      (node (ref "IC15") (pin "7") (pinfunction "7_7") (pintype "passive"))
      (node (ref "SV29") (pin "3") (pinfunction "3_3") (pintype "passive"))
      (node (ref "SV29") (pin "4") (pinfunction "4_4") (pintype "passive"))
    )
    (net (code "238") (name "Net-(IC15-Pad8)") (class "Default")
      (node (ref "IC15") (pin "8") (pinfunction "8_8") (pintype "passive"))
      (node (ref "SV29") (pin "1") (pinfunction "1_1") (pintype "passive"))
      (node (ref "SV29") (pin "2") (pinfunction "2_2") (pintype "passive"))
    )
    (net (code "239") (name "Net-(IC15-Pad9)") (class "Default")
      (node (ref "IC15") (pin "9") (pinfunction "9_9") (pintype "passive"))
      (node (ref "SV30") (pin "1") (pinfunction "1_1") (pintype "passive"))
      (node (ref "SV30") (pin "2") (pinfunction "2_2") (pintype "passive"))
    )
    (net (code "240") (name "Net-(IC15-Pad10)") (class "Default")
      (node (ref "IC15") (pin "10") (pinfunction "10_10") (pintype "passive"))
      (node (ref "SV30") (pin "3") (pinfunction "3_3") (pintype "passive"))
      (node (ref "SV30") (pin "4") (pinfunction "4_4") (pintype "passive"))
    )
    (net (code "241") (name "Net-(IC15-Pad11)") (class "Default")
      (node (ref "IC15") (pin "11") (pinfunction "11_11") (pintype "passive"))
      (node (ref "SV30") (pin "5") (pinfunction "5_5") (pintype "passive"))
      (node (ref "SV30") (pin "6") (pinfunction "6_6") (pintype "passive"))
    )
    (net (code "242") (name "Net-(IC15-Pad12)") (class "Default")
      (node (ref "IC15") (pin "12") (pinfunction "12_12") (pintype "passive"))
      (node (ref "SV30") (pin "7") (pinfunction "7_7") (pintype "passive"))
      (node (ref "SV30") (pin "8") (pinfunction "8_8") (pintype "passive"))
    )
    (net (code "243") (name "Net-(IC15-Pad13)") (class "Default")
      (node (ref "IC15") (pin "13") (pinfunction "13_13") (pintype "passive"))
      (node (ref "SV30") (pin "10") (pinfunction "10_10") (pintype "passive"))
      (node (ref "SV30") (pin "9") (pinfunction "9_9") (pintype "passive"))
    )
    (net (code "244") (name "Net-(IC15-Pad14)") (class "Default")
      (node (ref "IC15") (pin "14") (pinfunction "14_14") (pintype "passive"))
      (node (ref "SV30") (pin "11") (pinfunction "11_11") (pintype "passive"))
      (node (ref "SV30") (pin "12") (pinfunction "12_12") (pintype "passive"))
    )
    (net (code "245") (name "Net-(IC15-Pad15)") (class "Default")
      (node (ref "IC15") (pin "15") (pinfunction "15_15") (pintype "passive"))
      (node (ref "SV30") (pin "13") (pinfunction "13_13") (pintype "passive"))
      (node (ref "SV30") (pin "14") (pinfunction "14_14") (pintype "passive"))
    )
    (net (code "246") (name "Net-(IC15-Pad16)") (class "Default")
      (node (ref "IC15") (pin "16") (pinfunction "16_16") (pintype "passive"))
      (node (ref "SV30") (pin "15") (pinfunction "15_15") (pintype "passive"))
      (node (ref "SV30") (pin "16") (pinfunction "16_16") (pintype "passive"))
    )
    (net (code "247") (name "Net-(IC16-Pad1)") (class "Default")
      (node (ref "IC16") (pin "1") (pinfunction "1_1") (pintype "passive"))
      (node (ref "SV31") (pin "15") (pinfunction "15_15") (pintype "passive"))
      (node (ref "SV31") (pin "16") (pinfunction "16_16") (pintype "passive"))
    )
    (net (code "248") (name "Net-(IC16-Pad2)") (class "Default")
      (node (ref "IC16") (pin "2") (pinfunction "2_2") (pintype "passive"))
      (node (ref "SV31") (pin "13") (pinfunction "13_13") (pintype "passive"))
      (node (ref "SV31") (pin "14") (pinfunction "14_14") (pintype "passive"))
    )
    (net (code "249") (name "Net-(IC16-Pad3)") (class "Default")
      (node (ref "IC16") (pin "3") (pinfunction "3_3") (pintype "passive"))
      (node (ref "SV31") (pin "11") (pinfunction "11_11") (pintype "passive"))
      (node (ref "SV31") (pin "12") (pinfunction "12_12") (pintype "passive"))
    )
    (net (code "250") (name "Net-(IC16-Pad4)") (class "Default")
      (node (ref "IC16") (pin "4") (pinfunction "4_4") (pintype "passive"))
      (node (ref "SV31") (pin "10") (pinfunction "10_10") (pintype "passive"))
      (node (ref "SV31") (pin "9") (pinfunction "9_9") (pintype "passive"))
    )
    (net (code "251") (name "Net-(IC16-Pad5)") (class "Default")
      (node (ref "IC16") (pin "5") (pinfunction "5_5") (pintype "passive"))
      (node (ref "SV31") (pin "7") (pinfunction "7_7") (pintype "passive"))
      (node (ref "SV31") (pin "8") (pinfunction "8_8") (pintype "passive"))
    )
    (net (code "252") (name "Net-(IC16-Pad6)") (class "Default")
      (node (ref "IC16") (pin "6") (pinfunction "6_6") (pintype "passive"))
      (node (ref "SV31") (pin "5") (pinfunction "5_5") (pintype "passive"))
      (node (ref "SV31") (pin "6") (pinfunction "6_6") (pintype "passive"))
    )
    (net (code "253") (name "Net-(IC16-Pad7)") (class "Default")
      (node (ref "IC16") (pin "7") (pinfunction "7_7") (pintype "passive"))
      (node (ref "SV31") (pin "3") (pinfunction "3_3") (pintype "passive"))
      (node (ref "SV31") (pin "4") (pinfunction "4_4") (pintype "passive"))
    )
    (net (code "254") (name "Net-(IC16-Pad8)") (class "Default")
      (node (ref "IC16") (pin "8") (pinfunction "8_8") (pintype "passive"))
      (node (ref "SV31") (pin "1") (pinfunction "1_1") (pintype "passive"))
      (node (ref "SV31") (pin "2") (pinfunction "2_2") (pintype "passive"))
    )
    (net (code "255") (name "Net-(IC16-Pad9)") (class "Default")
      (node (ref "IC16") (pin "9") (pinfunction "9_9") (pintype "passive"))
      (node (ref "SV32") (pin "1") (pinfunction "1_1") (pintype "passive"))
      (node (ref "SV32") (pin "2") (pinfunction "2_2") (pintype "passive"))
    )
    (net (code "256") (name "Net-(IC16-Pad10)") (class "Default")
      (node (ref "IC16") (pin "10") (pinfunction "10_10") (pintype "passive"))
      (node (ref "SV32") (pin "3") (pinfunction "3_3") (pintype "passive"))
      (node (ref "SV32") (pin "4") (pinfunction "4_4") (pintype "passive"))
    )
    (net (code "257") (name "Net-(IC16-Pad11)") (class "Default")
      (node (ref "IC16") (pin "11") (pinfunction "11_11") (pintype "passive"))
      (node (ref "SV32") (pin "5") (pinfunction "5_5") (pintype "passive"))
      (node (ref "SV32") (pin "6") (pinfunction "6_6") (pintype "passive"))
    )
    (net (code "258") (name "Net-(IC16-Pad12)") (class "Default")
      (node (ref "IC16") (pin "12") (pinfunction "12_12") (pintype "passive"))
      (node (ref "SV32") (pin "7") (pinfunction "7_7") (pintype "passive"))
      (node (ref "SV32") (pin "8") (pinfunction "8_8") (pintype "passive"))
    )
    (net (code "259") (name "Net-(IC16-Pad13)") (class "Default")
      (node (ref "IC16") (pin "13") (pinfunction "13_13") (pintype "passive"))
      (node (ref "SV32") (pin "10") (pinfunction "10_10") (pintype "passive"))
      (node (ref "SV32") (pin "9") (pinfunction "9_9") (pintype "passive"))
    )
    (net (code "260") (name "Net-(IC16-Pad14)") (class "Default")
      (node (ref "IC16") (pin "14") (pinfunction "14_14") (pintype "passive"))
      (node (ref "SV32") (pin "11") (pinfunction "11_11") (pintype "passive"))
      (node (ref "SV32") (pin "12") (pinfunction "12_12") (pintype "passive"))
    )
    (net (code "261") (name "Net-(IC16-Pad15)") (class "Default")
      (node (ref "IC16") (pin "15") (pinfunction "15_15") (pintype "passive"))
      (node (ref "SV32") (pin "13") (pinfunction "13_13") (pintype "passive"))
      (node (ref "SV32") (pin "14") (pinfunction "14_14") (pintype "passive"))
    )
    (net (code "262") (name "Net-(IC16-Pad16)") (class "Default")
      (node (ref "IC16") (pin "16") (pinfunction "16_16") (pintype "passive"))
      (node (ref "SV32") (pin "15") (pinfunction "15_15") (pintype "passive"))
      (node (ref "SV32") (pin "16") (pinfunction "16_16") (pintype "passive"))
    )
    (net (code "263") (name "Net-(IC17-Pad1)") (class "Default")
      (node (ref "IC17") (pin "1") (pinfunction "1_1") (pintype "passive"))
      (node (ref "SV33") (pin "15") (pinfunction "15_15") (pintype "passive"))
      (node (ref "SV33") (pin "16") (pinfunction "16_16") (pintype "passive"))
    )
    (net (code "264") (name "Net-(IC17-Pad2)") (class "Default")
      (node (ref "IC17") (pin "2") (pinfunction "2_2") (pintype "passive"))
      (node (ref "SV33") (pin "13") (pinfunction "13_13") (pintype "passive"))
      (node (ref "SV33") (pin "14") (pinfunction "14_14") (pintype "passive"))
    )
    (net (code "265") (name "Net-(IC17-Pad3)") (class "Default")
      (node (ref "IC17") (pin "3") (pinfunction "3_3") (pintype "passive"))
      (node (ref "SV33") (pin "11") (pinfunction "11_11") (pintype "passive"))
      (node (ref "SV33") (pin "12") (pinfunction "12_12") (pintype "passive"))
    )
    (net (code "266") (name "Net-(IC17-Pad4)") (class "Default")
      (node (ref "IC17") (pin "4") (pinfunction "4_4") (pintype "passive"))
      (node (ref "SV33") (pin "10") (pinfunction "10_10") (pintype "passive"))
      (node (ref "SV33") (pin "9") (pinfunction "9_9") (pintype "passive"))
    )
    (net (code "267") (name "Net-(IC17-Pad5)") (class "Default")
      (node (ref "IC17") (pin "5") (pinfunction "5_5") (pintype "passive"))
      (node (ref "SV33") (pin "7") (pinfunction "7_7") (pintype "passive"))
      (node (ref "SV33") (pin "8") (pinfunction "8_8") (pintype "passive"))
    )
    (net (code "268") (name "Net-(IC17-Pad6)") (class "Default")
      (node (ref "IC17") (pin "6") (pinfunction "6_6") (pintype "passive"))
      (node (ref "SV33") (pin "5") (pinfunction "5_5") (pintype "passive"))
      (node (ref "SV33") (pin "6") (pinfunction "6_6") (pintype "passive"))
    )
    (net (code "269") (name "Net-(IC17-Pad7)") (class "Default")
      (node (ref "IC17") (pin "7") (pinfunction "7_7") (pintype "passive"))
      (node (ref "SV33") (pin "3") (pinfunction "3_3") (pintype "passive"))
      (node (ref "SV33") (pin "4") (pinfunction "4_4") (pintype "passive"))
    )
    (net (code "270") (name "Net-(IC17-Pad8)") (class "Default")
      (node (ref "IC17") (pin "8") (pinfunction "8_8") (pintype "passive"))
      (node (ref "SV33") (pin "1") (pinfunction "1_1") (pintype "passive"))
      (node (ref "SV33") (pin "2") (pinfunction "2_2") (pintype "passive"))
    )
    (net (code "271") (name "Net-(IC17-Pad9)") (class "Default")
      (node (ref "IC17") (pin "9") (pinfunction "9_9") (pintype "passive"))
      (node (ref "SV34") (pin "1") (pinfunction "1_1") (pintype "passive"))
      (node (ref "SV34") (pin "2") (pinfunction "2_2") (pintype "passive"))
    )
    (net (code "272") (name "Net-(IC17-Pad10)") (class "Default")
      (node (ref "IC17") (pin "10") (pinfunction "10_10") (pintype "passive"))
      (node (ref "SV34") (pin "3") (pinfunction "3_3") (pintype "passive"))
      (node (ref "SV34") (pin "4") (pinfunction "4_4") (pintype "passive"))
    )
    (net (code "273") (name "Net-(IC17-Pad11)") (class "Default")
      (node (ref "IC17") (pin "11") (pinfunction "11_11") (pintype "passive"))
      (node (ref "SV34") (pin "5") (pinfunction "5_5") (pintype "passive"))
      (node (ref "SV34") (pin "6") (pinfunction "6_6") (pintype "passive"))
    )
    (net (code "274") (name "Net-(IC17-Pad12)") (class "Default")
      (node (ref "IC17") (pin "12") (pinfunction "12_12") (pintype "passive"))
      (node (ref "SV34") (pin "7") (pinfunction "7_7") (pintype "passive"))
      (node (ref "SV34") (pin "8") (pinfunction "8_8") (pintype "passive"))
    )
    (net (code "275") (name "Net-(IC17-Pad13)") (class "Default")
      (node (ref "IC17") (pin "13") (pinfunction "13_13") (pintype "passive"))
      (node (ref "SV34") (pin "10") (pinfunction "10_10") (pintype "passive"))
      (node (ref "SV34") (pin "9") (pinfunction "9_9") (pintype "passive"))
    )
    (net (code "276") (name "Net-(IC17-Pad14)") (class "Default")
      (node (ref "IC17") (pin "14") (pinfunction "14_14") (pintype "passive"))
      (node (ref "SV34") (pin "11") (pinfunction "11_11") (pintype "passive"))
      (node (ref "SV34") (pin "12") (pinfunction "12_12") (pintype "passive"))
    )
    (net (code "277") (name "Net-(IC17-Pad15)") (class "Default")
      (node (ref "IC17") (pin "15") (pinfunction "15_15") (pintype "passive"))
      (node (ref "SV34") (pin "13") (pinfunction "13_13") (pintype "passive"))
      (node (ref "SV34") (pin "14") (pinfunction "14_14") (pintype "passive"))
    )
    (net (code "278") (name "Net-(IC17-Pad16)") (class "Default")
      (node (ref "IC17") (pin "16") (pinfunction "16_16") (pintype "passive"))
      (node (ref "SV34") (pin "15") (pinfunction "15_15") (pintype "passive"))
      (node (ref "SV34") (pin "16") (pinfunction "16_16") (pintype "passive"))
    )
    (net (code "279") (name "Net-(IC18-Pad1)") (class "Default")
      (node (ref "IC18") (pin "1") (pinfunction "1_1") (pintype "passive"))
      (node (ref "SV35") (pin "15") (pinfunction "15_15") (pintype "passive"))
      (node (ref "SV35") (pin "16") (pinfunction "16_16") (pintype "passive"))
    )
    (net (code "280") (name "Net-(IC18-Pad2)") (class "Default")
      (node (ref "IC18") (pin "2") (pinfunction "2_2") (pintype "passive"))
      (node (ref "SV35") (pin "13") (pinfunction "13_13") (pintype "passive"))
      (node (ref "SV35") (pin "14") (pinfunction "14_14") (pintype "passive"))
    )
    (net (code "281") (name "Net-(IC18-Pad3)") (class "Default")
      (node (ref "IC18") (pin "3") (pinfunction "3_3") (pintype "passive"))
      (node (ref "SV35") (pin "11") (pinfunction "11_11") (pintype "passive"))
      (node (ref "SV35") (pin "12") (pinfunction "12_12") (pintype "passive"))
    )
    (net (code "282") (name "Net-(IC18-Pad4)") (class "Default")
      (node (ref "IC18") (pin "4") (pinfunction "4_4") (pintype "passive"))
      (node (ref "SV35") (pin "10") (pinfunction "10_10") (pintype "passive"))
      (node (ref "SV35") (pin "9") (pinfunction "9_9") (pintype "passive"))
    )
    (net (code "283") (name "Net-(IC18-Pad5)") (class "Default")
      (node (ref "IC18") (pin "5") (pinfunction "5_5") (pintype "passive"))
      (node (ref "SV35") (pin "7") (pinfunction "7_7") (pintype "passive"))
      (node (ref "SV35") (pin "8") (pinfunction "8_8") (pintype "passive"))
    )
    (net (code "284") (name "Net-(IC18-Pad6)") (class "Default")
      (node (ref "IC18") (pin "6") (pinfunction "6_6") (pintype "passive"))
      (node (ref "SV35") (pin "5") (pinfunction "5_5") (pintype "passive"))
      (node (ref "SV35") (pin "6") (pinfunction "6_6") (pintype "passive"))
    )
    (net (code "285") (name "Net-(IC18-Pad7)") (class "Default")
      (node (ref "IC18") (pin "7") (pinfunction "7_7") (pintype "passive"))
      (node (ref "SV35") (pin "3") (pinfunction "3_3") (pintype "passive"))
      (node (ref "SV35") (pin "4") (pinfunction "4_4") (pintype "passive"))
    )
    (net (code "286") (name "Net-(IC18-Pad8)") (class "Default")
      (node (ref "IC18") (pin "8") (pinfunction "8_8") (pintype "passive"))
      (node (ref "SV35") (pin "1") (pinfunction "1_1") (pintype "passive"))
      (node (ref "SV35") (pin "2") (pinfunction "2_2") (pintype "passive"))
    )
    (net (code "287") (name "Net-(IC18-Pad9)") (class "Default")
      (node (ref "IC18") (pin "9") (pinfunction "9_9") (pintype "passive"))
      (node (ref "SV36") (pin "1") (pinfunction "1_1") (pintype "passive"))
      (node (ref "SV36") (pin "2") (pinfunction "2_2") (pintype "passive"))
    )
    (net (code "288") (name "Net-(IC18-Pad10)") (class "Default")
      (node (ref "IC18") (pin "10") (pinfunction "10_10") (pintype "passive"))
      (node (ref "SV36") (pin "3") (pinfunction "3_3") (pintype "passive"))
      (node (ref "SV36") (pin "4") (pinfunction "4_4") (pintype "passive"))
    )
    (net (code "289") (name "Net-(IC18-Pad11)") (class "Default")
      (node (ref "IC18") (pin "11") (pinfunction "11_11") (pintype "passive"))
      (node (ref "SV36") (pin "5") (pinfunction "5_5") (pintype "passive"))
      (node (ref "SV36") (pin "6") (pinfunction "6_6") (pintype "passive"))
    )
    (net (code "290") (name "Net-(IC18-Pad12)") (class "Default")
      (node (ref "IC18") (pin "12") (pinfunction "12_12") (pintype "passive"))
      (node (ref "SV36") (pin "7") (pinfunction "7_7") (pintype "passive"))
      (node (ref "SV36") (pin "8") (pinfunction "8_8") (pintype "passive"))
    )
    (net (code "291") (name "Net-(IC18-Pad13)") (class "Default")
      (node (ref "IC18") (pin "13") (pinfunction "13_13") (pintype "passive"))
      (node (ref "SV36") (pin "10") (pinfunction "10_10") (pintype "passive"))
      (node (ref "SV36") (pin "9") (pinfunction "9_9") (pintype "passive"))
    )
    (net (code "292") (name "Net-(IC18-Pad14)") (class "Default")
      (node (ref "IC18") (pin "14") (pinfunction "14_14") (pintype "passive"))
      (node (ref "SV36") (pin "11") (pinfunction "11_11") (pintype "passive"))
      (node (ref "SV36") (pin "12") (pinfunction "12_12") (pintype "passive"))
    )
    (net (code "293") (name "Net-(IC18-Pad15)") (class "Default")
      (node (ref "IC18") (pin "15") (pinfunction "15_15") (pintype "passive"))
      (node (ref "SV36") (pin "13") (pinfunction "13_13") (pintype "passive"))
      (node (ref "SV36") (pin "14") (pinfunction "14_14") (pintype "passive"))
    )
    (net (code "294") (name "Net-(IC18-Pad16)") (class "Default")
      (node (ref "IC18") (pin "16") (pinfunction "16_16") (pintype "passive"))
      (node (ref "SV36") (pin "15") (pinfunction "15_15") (pintype "passive"))
      (node (ref "SV36") (pin "16") (pinfunction "16_16") (pintype "passive"))
    )
    (net (code "295") (name "Net-(IC19-Pad1)") (class "Default")
      (node (ref "IC19") (pin "1") (pinfunction "1_1") (pintype "passive"))
      (node (ref "SV37") (pin "15") (pinfunction "15_15") (pintype "passive"))
      (node (ref "SV37") (pin "16") (pinfunction "16_16") (pintype "passive"))
    )
    (net (code "296") (name "Net-(IC19-Pad2)") (class "Default")
      (node (ref "IC19") (pin "2") (pinfunction "2_2") (pintype "passive"))
      (node (ref "SV37") (pin "13") (pinfunction "13_13") (pintype "passive"))
      (node (ref "SV37") (pin "14") (pinfunction "14_14") (pintype "passive"))
    )
    (net (code "297") (name "Net-(IC19-Pad3)") (class "Default")
      (node (ref "IC19") (pin "3") (pinfunction "3_3") (pintype "passive"))
      (node (ref "SV37") (pin "11") (pinfunction "11_11") (pintype "passive"))
      (node (ref "SV37") (pin "12") (pinfunction "12_12") (pintype "passive"))
    )
    (net (code "298") (name "Net-(IC19-Pad4)") (class "Default")
      (node (ref "IC19") (pin "4") (pinfunction "4_4") (pintype "passive"))
      (node (ref "SV37") (pin "10") (pinfunction "10_10") (pintype "passive"))
      (node (ref "SV37") (pin "9") (pinfunction "9_9") (pintype "passive"))
    )
    (net (code "299") (name "Net-(IC19-Pad5)") (class "Default")
      (node (ref "IC19") (pin "5") (pinfunction "5_5") (pintype "passive"))
      (node (ref "SV37") (pin "7") (pinfunction "7_7") (pintype "passive"))
      (node (ref "SV37") (pin "8") (pinfunction "8_8") (pintype "passive"))
    )
    (net (code "300") (name "Net-(IC19-Pad6)") (class "Default")
      (node (ref "IC19") (pin "6") (pinfunction "6_6") (pintype "passive"))
      (node (ref "SV37") (pin "5") (pinfunction "5_5") (pintype "passive"))
      (node (ref "SV37") (pin "6") (pinfunction "6_6") (pintype "passive"))
    )
    (net (code "301") (name "Net-(IC19-Pad7)") (class "Default")
      (node (ref "IC19") (pin "7") (pinfunction "7_7") (pintype "passive"))
      (node (ref "SV37") (pin "3") (pinfunction "3_3") (pintype "passive"))
      (node (ref "SV37") (pin "4") (pinfunction "4_4") (pintype "passive"))
    )
    (net (code "302") (name "Net-(IC19-Pad8)") (class "Default")
      (node (ref "IC19") (pin "8") (pinfunction "8_8") (pintype "passive"))
      (node (ref "SV37") (pin "1") (pinfunction "1_1") (pintype "passive"))
      (node (ref "SV37") (pin "2") (pinfunction "2_2") (pintype "passive"))
    )
    (net (code "303") (name "Net-(IC19-Pad9)") (class "Default")
      (node (ref "IC19") (pin "9") (pinfunction "9_9") (pintype "passive"))
      (node (ref "SV38") (pin "1") (pinfunction "1_1") (pintype "passive"))
      (node (ref "SV38") (pin "2") (pinfunction "2_2") (pintype "passive"))
    )
    (net (code "304") (name "Net-(IC19-Pad10)") (class "Default")
      (node (ref "IC19") (pin "10") (pinfunction "10_10") (pintype "passive"))
      (node (ref "SV38") (pin "3") (pinfunction "3_3") (pintype "passive"))
      (node (ref "SV38") (pin "4") (pinfunction "4_4") (pintype "passive"))
    )
    (net (code "305") (name "Net-(IC19-Pad11)") (class "Default")
      (node (ref "IC19") (pin "11") (pinfunction "11_11") (pintype "passive"))
      (node (ref "SV38") (pin "5") (pinfunction "5_5") (pintype "passive"))
      (node (ref "SV38") (pin "6") (pinfunction "6_6") (pintype "passive"))
    )
    (net (code "306") (name "Net-(IC19-Pad12)") (class "Default")
      (node (ref "IC19") (pin "12") (pinfunction "12_12") (pintype "passive"))
      (node (ref "SV38") (pin "7") (pinfunction "7_7") (pintype "passive"))
      (node (ref "SV38") (pin "8") (pinfunction "8_8") (pintype "passive"))
    )
    (net (code "307") (name "Net-(IC19-Pad13)") (class "Default")
      (node (ref "IC19") (pin "13") (pinfunction "13_13") (pintype "passive"))
      (node (ref "SV38") (pin "10") (pinfunction "10_10") (pintype "passive"))
      (node (ref "SV38") (pin "9") (pinfunction "9_9") (pintype "passive"))
    )
    (net (code "308") (name "Net-(IC19-Pad14)") (class "Default")
      (node (ref "IC19") (pin "14") (pinfunction "14_14") (pintype "passive"))
      (node (ref "SV38") (pin "11") (pinfunction "11_11") (pintype "passive"))
      (node (ref "SV38") (pin "12") (pinfunction "12_12") (pintype "passive"))
    )
    (net (code "309") (name "Net-(IC19-Pad15)") (class "Default")
      (node (ref "IC19") (pin "15") (pinfunction "15_15") (pintype "passive"))
      (node (ref "SV38") (pin "13") (pinfunction "13_13") (pintype "passive"))
      (node (ref "SV38") (pin "14") (pinfunction "14_14") (pintype "passive"))
    )
    (net (code "310") (name "Net-(IC19-Pad16)") (class "Default")
      (node (ref "IC19") (pin "16") (pinfunction "16_16") (pintype "passive"))
      (node (ref "SV38") (pin "15") (pinfunction "15_15") (pintype "passive"))
      (node (ref "SV38") (pin "16") (pinfunction "16_16") (pintype "passive"))
    )
    (net (code "311") (name "Net-(IC20-Pad1)") (class "Default")
      (node (ref "IC20") (pin "1") (pinfunction "1_1") (pintype "passive"))
      (node (ref "SV39") (pin "15") (pinfunction "15_15") (pintype "passive"))
      (node (ref "SV39") (pin "16") (pinfunction "16_16") (pintype "passive"))
    )
    (net (code "312") (name "Net-(IC20-Pad2)") (class "Default")
      (node (ref "IC20") (pin "2") (pinfunction "2_2") (pintype "passive"))
      (node (ref "SV39") (pin "13") (pinfunction "13_13") (pintype "passive"))
      (node (ref "SV39") (pin "14") (pinfunction "14_14") (pintype "passive"))
    )
    (net (code "313") (name "Net-(IC20-Pad3)") (class "Default")
      (node (ref "IC20") (pin "3") (pinfunction "3_3") (pintype "passive"))
      (node (ref "SV39") (pin "11") (pinfunction "11_11") (pintype "passive"))
      (node (ref "SV39") (pin "12") (pinfunction "12_12") (pintype "passive"))
    )
    (net (code "314") (name "Net-(IC20-Pad4)") (class "Default")
      (node (ref "IC20") (pin "4") (pinfunction "4_4") (pintype "passive"))
      (node (ref "SV39") (pin "10") (pinfunction "10_10") (pintype "passive"))
      (node (ref "SV39") (pin "9") (pinfunction "9_9") (pintype "passive"))
    )
    (net (code "315") (name "Net-(IC20-Pad5)") (class "Default")
      (node (ref "IC20") (pin "5") (pinfunction "5_5") (pintype "passive"))
      (node (ref "SV39") (pin "7") (pinfunction "7_7") (pintype "passive"))
      (node (ref "SV39") (pin "8") (pinfunction "8_8") (pintype "passive"))
    )
    (net (code "316") (name "Net-(IC20-Pad6)") (class "Default")
      (node (ref "IC20") (pin "6") (pinfunction "6_6") (pintype "passive"))
      (node (ref "SV39") (pin "5") (pinfunction "5_5") (pintype "passive"))
      (node (ref "SV39") (pin "6") (pinfunction "6_6") (pintype "passive"))
    )
    (net (code "317") (name "Net-(IC20-Pad7)") (class "Default")
      (node (ref "IC20") (pin "7") (pinfunction "7_7") (pintype "passive"))
      (node (ref "SV39") (pin "3") (pinfunction "3_3") (pintype "passive"))
      (node (ref "SV39") (pin "4") (pinfunction "4_4") (pintype "passive"))
    )
    (net (code "318") (name "Net-(IC20-Pad8)") (class "Default")
      (node (ref "IC20") (pin "8") (pinfunction "8_8") (pintype "passive"))
      (node (ref "SV39") (pin "1") (pinfunction "1_1") (pintype "passive"))
      (node (ref "SV39") (pin "2") (pinfunction "2_2") (pintype "passive"))
    )
    (net (code "319") (name "Net-(IC20-Pad9)") (class "Default")
      (node (ref "IC20") (pin "9") (pinfunction "9_9") (pintype "passive"))
      (node (ref "SV40") (pin "1") (pinfunction "1_1") (pintype "passive"))
      (node (ref "SV40") (pin "2") (pinfunction "2_2") (pintype "passive"))
    )
    (net (code "320") (name "Net-(IC20-Pad10)") (class "Default")
      (node (ref "IC20") (pin "10") (pinfunction "10_10") (pintype "passive"))
      (node (ref "SV40") (pin "3") (pinfunction "3_3") (pintype "passive"))
      (node (ref "SV40") (pin "4") (pinfunction "4_4") (pintype "passive"))
    )
    (net (code "321") (name "Net-(IC20-Pad11)") (class "Default")
      (node (ref "IC20") (pin "11") (pinfunction "11_11") (pintype "passive"))
      (node (ref "SV40") (pin "5") (pinfunction "5_5") (pintype "passive"))
      (node (ref "SV40") (pin "6") (pinfunction "6_6") (pintype "passive"))
    )
    (net (code "322") (name "Net-(IC20-Pad12)") (class "Default")
      (node (ref "IC20") (pin "12") (pinfunction "12_12") (pintype "passive"))
      (node (ref "SV40") (pin "7") (pinfunction "7_7") (pintype "passive"))
      (node (ref "SV40") (pin "8") (pinfunction "8_8") (pintype "passive"))
    )
    (net (code "323") (name "Net-(IC20-Pad13)") (class "Default")
      (node (ref "IC20") (pin "13") (pinfunction "13_13") (pintype "passive"))
      (node (ref "SV40") (pin "10") (pinfunction "10_10") (pintype "passive"))
      (node (ref "SV40") (pin "9") (pinfunction "9_9") (pintype "passive"))
    )
    (net (code "324") (name "Net-(IC20-Pad14)") (class "Default")
      (node (ref "IC20") (pin "14") (pinfunction "14_14") (pintype "passive"))
      (node (ref "SV40") (pin "11") (pinfunction "11_11") (pintype "passive"))
      (node (ref "SV40") (pin "12") (pinfunction "12_12") (pintype "passive"))
    )
    (net (code "325") (name "Net-(IC20-Pad15)") (class "Default")
      (node (ref "IC20") (pin "15") (pinfunction "15_15") (pintype "passive"))
      (node (ref "SV40") (pin "13") (pinfunction "13_13") (pintype "passive"))
      (node (ref "SV40") (pin "14") (pinfunction "14_14") (pintype "passive"))
    )
    (net (code "326") (name "Net-(IC20-Pad16)") (class "Default")
      (node (ref "IC20") (pin "16") (pinfunction "16_16") (pintype "passive"))
      (node (ref "SV40") (pin "15") (pinfunction "15_15") (pintype "passive"))
      (node (ref "SV40") (pin "16") (pinfunction "16_16") (pintype "passive"))
    )
    (net (code "327") (name "Net-(IC21-Pad1)") (class "Default")
      (node (ref "IC21") (pin "1") (pinfunction "1_1") (pintype "passive"))
      (node (ref "SV41") (pin "15") (pinfunction "15_15") (pintype "passive"))
      (node (ref "SV41") (pin "16") (pinfunction "16_16") (pintype "passive"))
    )
    (net (code "328") (name "Net-(IC21-Pad2)") (class "Default")
      (node (ref "IC21") (pin "2") (pinfunction "2_2") (pintype "passive"))
      (node (ref "SV41") (pin "13") (pinfunction "13_13") (pintype "passive"))
      (node (ref "SV41") (pin "14") (pinfunction "14_14") (pintype "passive"))
    )
    (net (code "329") (name "Net-(IC21-Pad3)") (class "Default")
      (node (ref "IC21") (pin "3") (pinfunction "3_3") (pintype "passive"))
      (node (ref "SV41") (pin "11") (pinfunction "11_11") (pintype "passive"))
      (node (ref "SV41") (pin "12") (pinfunction "12_12") (pintype "passive"))
    )
    (net (code "330") (name "Net-(IC21-Pad4)") (class "Default")
      (node (ref "IC21") (pin "4") (pinfunction "4_4") (pintype "passive"))
      (node (ref "SV41") (pin "10") (pinfunction "10_10") (pintype "passive"))
      (node (ref "SV41") (pin "9") (pinfunction "9_9") (pintype "passive"))
    )
    (net (code "331") (name "Net-(IC21-Pad5)") (class "Default")
      (node (ref "IC21") (pin "5") (pinfunction "5_5") (pintype "passive"))
      (node (ref "SV41") (pin "7") (pinfunction "7_7") (pintype "passive"))
      (node (ref "SV41") (pin "8") (pinfunction "8_8") (pintype "passive"))
    )
    (net (code "332") (name "Net-(IC21-Pad6)") (class "Default")
      (node (ref "IC21") (pin "6") (pinfunction "6_6") (pintype "passive"))
      (node (ref "SV41") (pin "5") (pinfunction "5_5") (pintype "passive"))
      (node (ref "SV41") (pin "6") (pinfunction "6_6") (pintype "passive"))
    )
    (net (code "333") (name "Net-(IC21-Pad7)") (class "Default")
      (node (ref "IC21") (pin "7") (pinfunction "7_7") (pintype "passive"))
      (node (ref "SV41") (pin "3") (pinfunction "3_3") (pintype "passive"))
      (node (ref "SV41") (pin "4") (pinfunction "4_4") (pintype "passive"))
    )
    (net (code "334") (name "Net-(IC21-Pad8)") (class "Default")
      (node (ref "IC21") (pin "8") (pinfunction "8_8") (pintype "passive"))
      (node (ref "SV41") (pin "1") (pinfunction "1_1") (pintype "passive"))
      (node (ref "SV41") (pin "2") (pinfunction "2_2") (pintype "passive"))
    )
    (net (code "335") (name "Net-(IC21-Pad9)") (class "Default")
      (node (ref "IC21") (pin "9") (pinfunction "9_9") (pintype "passive"))
      (node (ref "SV42") (pin "1") (pinfunction "1_1") (pintype "passive"))
      (node (ref "SV42") (pin "2") (pinfunction "2_2") (pintype "passive"))
    )
    (net (code "336") (name "Net-(IC21-Pad10)") (class "Default")
      (node (ref "IC21") (pin "10") (pinfunction "10_10") (pintype "passive"))
      (node (ref "SV42") (pin "3") (pinfunction "3_3") (pintype "passive"))
      (node (ref "SV42") (pin "4") (pinfunction "4_4") (pintype "passive"))
    )
    (net (code "337") (name "Net-(IC21-Pad11)") (class "Default")
      (node (ref "IC21") (pin "11") (pinfunction "11_11") (pintype "passive"))
      (node (ref "SV42") (pin "5") (pinfunction "5_5") (pintype "passive"))
      (node (ref "SV42") (pin "6") (pinfunction "6_6") (pintype "passive"))
    )
    (net (code "338") (name "Net-(IC21-Pad12)") (class "Default")
      (node (ref "IC21") (pin "12") (pinfunction "12_12") (pintype "passive"))
      (node (ref "SV42") (pin "7") (pinfunction "7_7") (pintype "passive"))
      (node (ref "SV42") (pin "8") (pinfunction "8_8") (pintype "passive"))
    )
    (net (code "339") (name "Net-(IC21-Pad13)") (class "Default")
      (node (ref "IC21") (pin "13") (pinfunction "13_13") (pintype "passive"))
      (node (ref "SV42") (pin "10") (pinfunction "10_10") (pintype "passive"))
      (node (ref "SV42") (pin "9") (pinfunction "9_9") (pintype "passive"))
    )
    (net (code "340") (name "Net-(IC21-Pad14)") (class "Default")
      (node (ref "IC21") (pin "14") (pinfunction "14_14") (pintype "passive"))
      (node (ref "SV42") (pin "11") (pinfunction "11_11") (pintype "passive"))
      (node (ref "SV42") (pin "12") (pinfunction "12_12") (pintype "passive"))
    )
    (net (code "341") (name "Net-(IC21-Pad15)") (class "Default")
      (node (ref "IC21") (pin "15") (pinfunction "15_15") (pintype "passive"))
      (node (ref "SV42") (pin "13") (pinfunction "13_13") (pintype "passive"))
      (node (ref "SV42") (pin "14") (pinfunction "14_14") (pintype "passive"))
    )
    (net (code "342") (name "Net-(IC21-Pad16)") (class "Default")
      (node (ref "IC21") (pin "16") (pinfunction "16_16") (pintype "passive"))
      (node (ref "SV42") (pin "15") (pinfunction "15_15") (pintype "passive"))
      (node (ref "SV42") (pin "16") (pinfunction "16_16") (pintype "passive"))
    )
    (net (code "343") (name "Net-(IC22-Pad1)") (class "Default")
      (node (ref "IC22") (pin "1") (pinfunction "1_1") (pintype "passive"))
      (node (ref "SV43") (pin "15") (pinfunction "15_15") (pintype "passive"))
      (node (ref "SV43") (pin "16") (pinfunction "16_16") (pintype "passive"))
    )
    (net (code "344") (name "Net-(IC22-Pad2)") (class "Default")
      (node (ref "IC22") (pin "2") (pinfunction "2_2") (pintype "passive"))
      (node (ref "SV43") (pin "13") (pinfunction "13_13") (pintype "passive"))
      (node (ref "SV43") (pin "14") (pinfunction "14_14") (pintype "passive"))
    )
    (net (code "345") (name "Net-(IC22-Pad3)") (class "Default")
      (node (ref "IC22") (pin "3") (pinfunction "3_3") (pintype "passive"))
      (node (ref "SV43") (pin "11") (pinfunction "11_11") (pintype "passive"))
      (node (ref "SV43") (pin "12") (pinfunction "12_12") (pintype "passive"))
    )
    (net (code "346") (name "Net-(IC22-Pad4)") (class "Default")
      (node (ref "IC22") (pin "4") (pinfunction "4_4") (pintype "passive"))
      (node (ref "SV43") (pin "10") (pinfunction "10_10") (pintype "passive"))
      (node (ref "SV43") (pin "9") (pinfunction "9_9") (pintype "passive"))
    )
    (net (code "347") (name "Net-(IC22-Pad5)") (class "Default")
      (node (ref "IC22") (pin "5") (pinfunction "5_5") (pintype "passive"))
      (node (ref "SV43") (pin "7") (pinfunction "7_7") (pintype "passive"))
      (node (ref "SV43") (pin "8") (pinfunction "8_8") (pintype "passive"))
    )
    (net (code "348") (name "Net-(IC22-Pad6)") (class "Default")
      (node (ref "IC22") (pin "6") (pinfunction "6_6") (pintype "passive"))
      (node (ref "SV43") (pin "5") (pinfunction "5_5") (pintype "passive"))
      (node (ref "SV43") (pin "6") (pinfunction "6_6") (pintype "passive"))
    )
    (net (code "349") (name "Net-(IC22-Pad7)") (class "Default")
      (node (ref "IC22") (pin "7") (pinfunction "7_7") (pintype "passive"))
      (node (ref "SV43") (pin "3") (pinfunction "3_3") (pintype "passive"))
      (node (ref "SV43") (pin "4") (pinfunction "4_4") (pintype "passive"))
    )
    (net (code "350") (name "Net-(IC22-Pad8)") (class "Default")
      (node (ref "IC22") (pin "8") (pinfunction "8_8") (pintype "passive"))
      (node (ref "SV43") (pin "1") (pinfunction "1_1") (pintype "passive"))
      (node (ref "SV43") (pin "2") (pinfunction "2_2") (pintype "passive"))
    )
    (net (code "351") (name "Net-(IC22-Pad9)") (class "Default")
      (node (ref "IC22") (pin "9") (pinfunction "9_9") (pintype "passive"))
      (node (ref "SV44") (pin "1") (pinfunction "1_1") (pintype "passive"))
      (node (ref "SV44") (pin "2") (pinfunction "2_2") (pintype "passive"))
    )
    (net (code "352") (name "Net-(IC22-Pad10)") (class "Default")
      (node (ref "IC22") (pin "10") (pinfunction "10_10") (pintype "passive"))
      (node (ref "SV44") (pin "3") (pinfunction "3_3") (pintype "passive"))
      (node (ref "SV44") (pin "4") (pinfunction "4_4") (pintype "passive"))
    )
    (net (code "353") (name "Net-(IC22-Pad11)") (class "Default")
      (node (ref "IC22") (pin "11") (pinfunction "11_11") (pintype "passive"))
      (node (ref "SV44") (pin "5") (pinfunction "5_5") (pintype "passive"))
      (node (ref "SV44") (pin "6") (pinfunction "6_6") (pintype "passive"))
    )
    (net (code "354") (name "Net-(IC22-Pad12)") (class "Default")
      (node (ref "IC22") (pin "12") (pinfunction "12_12") (pintype "passive"))
      (node (ref "SV44") (pin "7") (pinfunction "7_7") (pintype "passive"))
      (node (ref "SV44") (pin "8") (pinfunction "8_8") (pintype "passive"))
    )
    (net (code "355") (name "Net-(IC22-Pad13)") (class "Default")
      (node (ref "IC22") (pin "13") (pinfunction "13_13") (pintype "passive"))
      (node (ref "SV44") (pin "10") (pinfunction "10_10") (pintype "passive"))
      (node (ref "SV44") (pin "9") (pinfunction "9_9") (pintype "passive"))
    )
    (net (code "356") (name "Net-(IC22-Pad14)") (class "Default")
      (node (ref "IC22") (pin "14") (pinfunction "14_14") (pintype "passive"))
      (node (ref "SV44") (pin "11") (pinfunction "11_11") (pintype "passive"))
      (node (ref "SV44") (pin "12") (pinfunction "12_12") (pintype "passive"))
    )
    (net (code "357") (name "Net-(IC22-Pad15)") (class "Default")
      (node (ref "IC22") (pin "15") (pinfunction "15_15") (pintype "passive"))
      (node (ref "SV44") (pin "13") (pinfunction "13_13") (pintype "passive"))
      (node (ref "SV44") (pin "14") (pinfunction "14_14") (pintype "passive"))
    )
    (net (code "358") (name "Net-(IC22-Pad16)") (class "Default")
      (node (ref "IC22") (pin "16") (pinfunction "16_16") (pintype "passive"))
      (node (ref "SV44") (pin "15") (pinfunction "15_15") (pintype "passive"))
      (node (ref "SV44") (pin "16") (pinfunction "16_16") (pintype "passive"))
    )
    (net (code "359") (name "Net-(IC23-Pad1)") (class "Default")
      (node (ref "IC23") (pin "1") (pinfunction "1_1") (pintype "passive"))
      (node (ref "SV45") (pin "15") (pinfunction "15_15") (pintype "passive"))
      (node (ref "SV45") (pin "16") (pinfunction "16_16") (pintype "passive"))
    )
    (net (code "360") (name "Net-(IC23-Pad2)") (class "Default")
      (node (ref "IC23") (pin "2") (pinfunction "2_2") (pintype "passive"))
      (node (ref "SV45") (pin "13") (pinfunction "13_13") (pintype "passive"))
      (node (ref "SV45") (pin "14") (pinfunction "14_14") (pintype "passive"))
    )
    (net (code "361") (name "Net-(IC23-Pad3)") (class "Default")
      (node (ref "IC23") (pin "3") (pinfunction "3_3") (pintype "passive"))
      (node (ref "SV45") (pin "11") (pinfunction "11_11") (pintype "passive"))
      (node (ref "SV45") (pin "12") (pinfunction "12_12") (pintype "passive"))
    )
    (net (code "362") (name "Net-(IC23-Pad4)") (class "Default")
      (node (ref "IC23") (pin "4") (pinfunction "4_4") (pintype "passive"))
      (node (ref "SV45") (pin "10") (pinfunction "10_10") (pintype "passive"))
      (node (ref "SV45") (pin "9") (pinfunction "9_9") (pintype "passive"))
    )
    (net (code "363") (name "Net-(IC23-Pad5)") (class "Default")
      (node (ref "IC23") (pin "5") (pinfunction "5_5") (pintype "passive"))
      (node (ref "SV45") (pin "7") (pinfunction "7_7") (pintype "passive"))
      (node (ref "SV45") (pin "8") (pinfunction "8_8") (pintype "passive"))
    )
    (net (code "364") (name "Net-(IC23-Pad6)") (class "Default")
      (node (ref "IC23") (pin "6") (pinfunction "6_6") (pintype "passive"))
      (node (ref "SV45") (pin "5") (pinfunction "5_5") (pintype "passive"))
      (node (ref "SV45") (pin "6") (pinfunction "6_6") (pintype "passive"))
    )
    (net (code "365") (name "Net-(IC23-Pad7)") (class "Default")
      (node (ref "IC23") (pin "7") (pinfunction "7_7") (pintype "passive"))
      (node (ref "SV45") (pin "3") (pinfunction "3_3") (pintype "passive"))
      (node (ref "SV45") (pin "4") (pinfunction "4_4") (pintype "passive"))
    )
    (net (code "366") (name "Net-(IC23-Pad8)") (class "Default")
      (node (ref "IC23") (pin "8") (pinfunction "8_8") (pintype "passive"))
      (node (ref "SV45") (pin "1") (pinfunction "1_1") (pintype "passive"))
      (node (ref "SV45") (pin "2") (pinfunction "2_2") (pintype "passive"))
    )
    (net (code "367") (name "Net-(IC23-Pad9)") (class "Default")
      (node (ref "IC23") (pin "9") (pinfunction "9_9") (pintype "passive"))
      (node (ref "SV46") (pin "1") (pinfunction "1_1") (pintype "passive"))
      (node (ref "SV46") (pin "2") (pinfunction "2_2") (pintype "passive"))
    )
    (net (code "368") (name "Net-(IC23-Pad10)") (class "Default")
      (node (ref "IC23") (pin "10") (pinfunction "10_10") (pintype "passive"))
      (node (ref "SV46") (pin "3") (pinfunction "3_3") (pintype "passive"))
      (node (ref "SV46") (pin "4") (pinfunction "4_4") (pintype "passive"))
    )
    (net (code "369") (name "Net-(IC23-Pad11)") (class "Default")
      (node (ref "IC23") (pin "11") (pinfunction "11_11") (pintype "passive"))
      (node (ref "SV46") (pin "5") (pinfunction "5_5") (pintype "passive"))
      (node (ref "SV46") (pin "6") (pinfunction "6_6") (pintype "passive"))
    )
    (net (code "370") (name "Net-(IC23-Pad12)") (class "Default")
      (node (ref "IC23") (pin "12") (pinfunction "12_12") (pintype "passive"))
      (node (ref "SV46") (pin "7") (pinfunction "7_7") (pintype "passive"))
      (node (ref "SV46") (pin "8") (pinfunction "8_8") (pintype "passive"))
    )
    (net (code "371") (name "Net-(IC23-Pad13)") (class "Default")
      (node (ref "IC23") (pin "13") (pinfunction "13_13") (pintype "passive"))
      (node (ref "SV46") (pin "10") (pinfunction "10_10") (pintype "passive"))
      (node (ref "SV46") (pin "9") (pinfunction "9_9") (pintype "passive"))
    )
    (net (code "372") (name "Net-(IC23-Pad14)") (class "Default")
      (node (ref "IC23") (pin "14") (pinfunction "14_14") (pintype "passive"))
      (node (ref "SV46") (pin "11") (pinfunction "11_11") (pintype "passive"))
      (node (ref "SV46") (pin "12") (pinfunction "12_12") (pintype "passive"))
    )
    (net (code "373") (name "Net-(IC23-Pad15)") (class "Default")
      (node (ref "IC23") (pin "15") (pinfunction "15_15") (pintype "passive"))
      (node (ref "SV46") (pin "13") (pinfunction "13_13") (pintype "passive"))
      (node (ref "SV46") (pin "14") (pinfunction "14_14") (pintype "passive"))
    )
    (net (code "374") (name "Net-(IC23-Pad16)") (class "Default")
      (node (ref "IC23") (pin "16") (pinfunction "16_16") (pintype "passive"))
      (node (ref "SV46") (pin "15") (pinfunction "15_15") (pintype "passive"))
      (node (ref "SV46") (pin "16") (pinfunction "16_16") (pintype "passive"))
    )
    (net (code "375") (name "Net-(IC24-Pad1)") (class "Default")
      (node (ref "IC24") (pin "1") (pinfunction "1_1") (pintype "passive"))
      (node (ref "SV47") (pin "15") (pinfunction "15_15") (pintype "passive"))
      (node (ref "SV47") (pin "16") (pinfunction "16_16") (pintype "passive"))
    )
    (net (code "376") (name "Net-(IC24-Pad2)") (class "Default")
      (node (ref "IC24") (pin "2") (pinfunction "2_2") (pintype "passive"))
      (node (ref "SV47") (pin "13") (pinfunction "13_13") (pintype "passive"))
      (node (ref "SV47") (pin "14") (pinfunction "14_14") (pintype "passive"))
    )
    (net (code "377") (name "Net-(IC24-Pad3)") (class "Default")
      (node (ref "IC24") (pin "3") (pinfunction "3_3") (pintype "passive"))
      (node (ref "SV47") (pin "11") (pinfunction "11_11") (pintype "passive"))
      (node (ref "SV47") (pin "12") (pinfunction "12_12") (pintype "passive"))
    )
    (net (code "378") (name "Net-(IC24-Pad4)") (class "Default")
      (node (ref "IC24") (pin "4") (pinfunction "4_4") (pintype "passive"))
      (node (ref "SV47") (pin "10") (pinfunction "10_10") (pintype "passive"))
      (node (ref "SV47") (pin "9") (pinfunction "9_9") (pintype "passive"))
    )
    (net (code "379") (name "Net-(IC24-Pad5)") (class "Default")
      (node (ref "IC24") (pin "5") (pinfunction "5_5") (pintype "passive"))
      (node (ref "SV47") (pin "7") (pinfunction "7_7") (pintype "passive"))
      (node (ref "SV47") (pin "8") (pinfunction "8_8") (pintype "passive"))
    )
    (net (code "380") (name "Net-(IC24-Pad6)") (class "Default")
      (node (ref "IC24") (pin "6") (pinfunction "6_6") (pintype "passive"))
      (node (ref "SV47") (pin "5") (pinfunction "5_5") (pintype "passive"))
      (node (ref "SV47") (pin "6") (pinfunction "6_6") (pintype "passive"))
    )
    (net (code "381") (name "Net-(IC24-Pad7)") (class "Default")
      (node (ref "IC24") (pin "7") (pinfunction "7_7") (pintype "passive"))
      (node (ref "SV47") (pin "3") (pinfunction "3_3") (pintype "passive"))
      (node (ref "SV47") (pin "4") (pinfunction "4_4") (pintype "passive"))
    )
    (net (code "382") (name "Net-(IC24-Pad8)") (class "Default")
      (node (ref "IC24") (pin "8") (pinfunction "8_8") (pintype "passive"))
      (node (ref "SV47") (pin "1") (pinfunction "1_1") (pintype "passive"))
      (node (ref "SV47") (pin "2") (pinfunction "2_2") (pintype "passive"))
    )
    (net (code "383") (name "Net-(IC24-Pad9)") (class "Default")
      (node (ref "IC24") (pin "9") (pinfunction "9_9") (pintype "passive"))
      (node (ref "SV48") (pin "1") (pinfunction "1_1") (pintype "passive"))
      (node (ref "SV48") (pin "2") (pinfunction "2_2") (pintype "passive"))
    )
    (net (code "384") (name "Net-(IC24-Pad10)") (class "Default")
      (node (ref "IC24") (pin "10") (pinfunction "10_10") (pintype "passive"))
      (node (ref "SV48") (pin "3") (pinfunction "3_3") (pintype "passive"))
      (node (ref "SV48") (pin "4") (pinfunction "4_4") (pintype "passive"))
    )
    (net (code "385") (name "Net-(IC24-Pad11)") (class "Default")
      (node (ref "IC24") (pin "11") (pinfunction "11_11") (pintype "passive"))
      (node (ref "SV48") (pin "5") (pinfunction "5_5") (pintype "passive"))
      (node (ref "SV48") (pin "6") (pinfunction "6_6") (pintype "passive"))
    )
    (net (code "386") (name "Net-(IC24-Pad12)") (class "Default")
      (node (ref "IC24") (pin "12") (pinfunction "12_12") (pintype "passive"))
      (node (ref "SV48") (pin "7") (pinfunction "7_7") (pintype "passive"))
      (node (ref "SV48") (pin "8") (pinfunction "8_8") (pintype "passive"))
    )
    (net (code "387") (name "Net-(IC24-Pad13)") (class "Default")
      (node (ref "IC24") (pin "13") (pinfunction "13_13") (pintype "passive"))
      (node (ref "SV48") (pin "10") (pinfunction "10_10") (pintype "passive"))
      (node (ref "SV48") (pin "9") (pinfunction "9_9") (pintype "passive"))
    )
    (net (code "388") (name "Net-(IC24-Pad14)") (class "Default")
      (node (ref "IC24") (pin "14") (pinfunction "14_14") (pintype "passive"))
      (node (ref "SV48") (pin "11") (pinfunction "11_11") (pintype "passive"))
      (node (ref "SV48") (pin "12") (pinfunction "12_12") (pintype "passive"))
    )
    (net (code "389") (name "Net-(IC24-Pad15)") (class "Default")
      (node (ref "IC24") (pin "15") (pinfunction "15_15") (pintype "passive"))
      (node (ref "SV48") (pin "13") (pinfunction "13_13") (pintype "passive"))
      (node (ref "SV48") (pin "14") (pinfunction "14_14") (pintype "passive"))
    )
    (net (code "390") (name "Net-(IC24-Pad16)") (class "Default")
      (node (ref "IC24") (pin "16") (pinfunction "16_16") (pintype "passive"))
      (node (ref "SV48") (pin "15") (pinfunction "15_15") (pintype "passive"))
      (node (ref "SV48") (pin "16") (pinfunction "16_16") (pintype "passive"))
    )
    (net (code "391") (name "Net-(IC25-Pad1)") (class "Default")
      (node (ref "IC25") (pin "1") (pinfunction "1_1") (pintype "passive"))
      (node (ref "SV49") (pin "15") (pinfunction "15_15") (pintype "passive"))
      (node (ref "SV49") (pin "16") (pinfunction "16_16") (pintype "passive"))
    )
    (net (code "392") (name "Net-(IC25-Pad2)") (class "Default")
      (node (ref "IC25") (pin "2") (pinfunction "2_2") (pintype "passive"))
      (node (ref "SV49") (pin "13") (pinfunction "13_13") (pintype "passive"))
      (node (ref "SV49") (pin "14") (pinfunction "14_14") (pintype "passive"))
    )
    (net (code "393") (name "Net-(IC25-Pad3)") (class "Default")
      (node (ref "IC25") (pin "3") (pinfunction "3_3") (pintype "passive"))
      (node (ref "SV49") (pin "11") (pinfunction "11_11") (pintype "passive"))
      (node (ref "SV49") (pin "12") (pinfunction "12_12") (pintype "passive"))
    )
    (net (code "394") (name "Net-(IC25-Pad4)") (class "Default")
      (node (ref "IC25") (pin "4") (pinfunction "4_4") (pintype "passive"))
      (node (ref "SV49") (pin "10") (pinfunction "10_10") (pintype "passive"))
      (node (ref "SV49") (pin "9") (pinfunction "9_9") (pintype "passive"))
    )
    (net (code "395") (name "Net-(IC25-Pad5)") (class "Default")
      (node (ref "IC25") (pin "5") (pinfunction "5_5") (pintype "passive"))
      (node (ref "SV49") (pin "7") (pinfunction "7_7") (pintype "passive"))
      (node (ref "SV49") (pin "8") (pinfunction "8_8") (pintype "passive"))
    )
    (net (code "396") (name "Net-(IC25-Pad6)") (class "Default")
      (node (ref "IC25") (pin "6") (pinfunction "6_6") (pintype "passive"))
      (node (ref "SV49") (pin "5") (pinfunction "5_5") (pintype "passive"))
      (node (ref "SV49") (pin "6") (pinfunction "6_6") (pintype "passive"))
    )
    (net (code "397") (name "Net-(IC25-Pad7)") (class "Default")
      (node (ref "IC25") (pin "7") (pinfunction "7_7") (pintype "passive"))
      (node (ref "SV49") (pin "3") (pinfunction "3_3") (pintype "passive"))
      (node (ref "SV49") (pin "4") (pinfunction "4_4") (pintype "passive"))
    )
    (net (code "398") (name "Net-(IC25-Pad8)") (class "Default")
      (node (ref "IC25") (pin "8") (pinfunction "8_8") (pintype "passive"))
      (node (ref "SV49") (pin "1") (pinfunction "1_1") (pintype "passive"))
      (node (ref "SV49") (pin "2") (pinfunction "2_2") (pintype "passive"))
    )
    (net (code "399") (name "Net-(IC25-Pad9)") (class "Default")
      (node (ref "IC25") (pin "9") (pinfunction "9_9") (pintype "passive"))
      (node (ref "SV50") (pin "1") (pinfunction "1_1") (pintype "passive"))
      (node (ref "SV50") (pin "2") (pinfunction "2_2") (pintype "passive"))
    )
    (net (code "400") (name "Net-(IC25-Pad10)") (class "Default")
      (node (ref "IC25") (pin "10") (pinfunction "10_10") (pintype "passive"))
      (node (ref "SV50") (pin "3") (pinfunction "3_3") (pintype "passive"))
      (node (ref "SV50") (pin "4") (pinfunction "4_4") (pintype "passive"))
    )
    (net (code "401") (name "Net-(IC25-Pad11)") (class "Default")
      (node (ref "IC25") (pin "11") (pinfunction "11_11") (pintype "passive"))
      (node (ref "SV50") (pin "5") (pinfunction "5_5") (pintype "passive"))
      (node (ref "SV50") (pin "6") (pinfunction "6_6") (pintype "passive"))
    )
    (net (code "402") (name "Net-(IC25-Pad12)") (class "Default")
      (node (ref "IC25") (pin "12") (pinfunction "12_12") (pintype "passive"))
      (node (ref "SV50") (pin "7") (pinfunction "7_7") (pintype "passive"))
      (node (ref "SV50") (pin "8") (pinfunction "8_8") (pintype "passive"))
    )
    (net (code "403") (name "Net-(IC25-Pad13)") (class "Default")
      (node (ref "IC25") (pin "13") (pinfunction "13_13") (pintype "passive"))
      (node (ref "SV50") (pin "10") (pinfunction "10_10") (pintype "passive"))
      (node (ref "SV50") (pin "9") (pinfunction "9_9") (pintype "passive"))
    )
    (net (code "404") (name "Net-(IC25-Pad14)") (class "Default")
      (node (ref "IC25") (pin "14") (pinfunction "14_14") (pintype "passive"))
      (node (ref "SV50") (pin "11") (pinfunction "11_11") (pintype "passive"))
      (node (ref "SV50") (pin "12") (pinfunction "12_12") (pintype "passive"))
    )
    (net (code "405") (name "Net-(IC25-Pad15)") (class "Default")
      (node (ref "IC25") (pin "15") (pinfunction "15_15") (pintype "passive"))
      (node (ref "SV50") (pin "13") (pinfunction "13_13") (pintype "passive"))
      (node (ref "SV50") (pin "14") (pinfunction "14_14") (pintype "passive"))
    )
    (net (code "406") (name "Net-(IC25-Pad16)") (class "Default")
      (node (ref "IC25") (pin "16") (pinfunction "16_16") (pintype "passive"))
      (node (ref "SV50") (pin "15") (pinfunction "15_15") (pintype "passive"))
      (node (ref "SV50") (pin "16") (pinfunction "16_16") (pintype "passive"))
    )
    (net (code "407") (name "Net-(IC26-Pad1)") (class "Default")
      (node (ref "IC26") (pin "1") (pinfunction "1_1") (pintype "passive"))
      (node (ref "SV51") (pin "15") (pinfunction "15_15") (pintype "passive"))
      (node (ref "SV51") (pin "16") (pinfunction "16_16") (pintype "passive"))
    )
    (net (code "408") (name "Net-(IC26-Pad2)") (class "Default")
      (node (ref "IC26") (pin "2") (pinfunction "2_2") (pintype "passive"))
      (node (ref "SV51") (pin "13") (pinfunction "13_13") (pintype "passive"))
      (node (ref "SV51") (pin "14") (pinfunction "14_14") (pintype "passive"))
    )
    (net (code "409") (name "Net-(IC26-Pad3)") (class "Default")
      (node (ref "IC26") (pin "3") (pinfunction "3_3") (pintype "passive"))
      (node (ref "SV51") (pin "11") (pinfunction "11_11") (pintype "passive"))
      (node (ref "SV51") (pin "12") (pinfunction "12_12") (pintype "passive"))
    )
    (net (code "410") (name "Net-(IC26-Pad4)") (class "Default")
      (node (ref "IC26") (pin "4") (pinfunction "4_4") (pintype "passive"))
      (node (ref "SV51") (pin "10") (pinfunction "10_10") (pintype "passive"))
      (node (ref "SV51") (pin "9") (pinfunction "9_9") (pintype "passive"))
    )
    (net (code "411") (name "Net-(IC26-Pad5)") (class "Default")
      (node (ref "IC26") (pin "5") (pinfunction "5_5") (pintype "passive"))
      (node (ref "SV51") (pin "7") (pinfunction "7_7") (pintype "passive"))
      (node (ref "SV51") (pin "8") (pinfunction "8_8") (pintype "passive"))
    )
    (net (code "412") (name "Net-(IC26-Pad6)") (class "Default")
      (node (ref "IC26") (pin "6") (pinfunction "6_6") (pintype "passive"))
      (node (ref "SV51") (pin "5") (pinfunction "5_5") (pintype "passive"))
      (node (ref "SV51") (pin "6") (pinfunction "6_6") (pintype "passive"))
    )
    (net (code "413") (name "Net-(IC26-Pad7)") (class "Default")
      (node (ref "IC26") (pin "7") (pinfunction "7_7") (pintype "passive"))
      (node (ref "SV51") (pin "3") (pinfunction "3_3") (pintype "passive"))
      (node (ref "SV51") (pin "4") (pinfunction "4_4") (pintype "passive"))
    )
    (net (code "414") (name "Net-(IC26-Pad8)") (class "Default")
      (node (ref "IC26") (pin "8") (pinfunction "8_8") (pintype "passive"))
      (node (ref "SV51") (pin "1") (pinfunction "1_1") (pintype "passive"))
      (node (ref "SV51") (pin "2") (pinfunction "2_2") (pintype "passive"))
    )
    (net (code "415") (name "Net-(IC26-Pad9)") (class "Default")
      (node (ref "IC26") (pin "9") (pinfunction "9_9") (pintype "passive"))
      (node (ref "SV52") (pin "1") (pinfunction "1_1") (pintype "passive"))
      (node (ref "SV52") (pin "2") (pinfunction "2_2") (pintype "passive"))
    )
    (net (code "416") (name "Net-(IC26-Pad10)") (class "Default")
      (node (ref "IC26") (pin "10") (pinfunction "10_10") (pintype "passive"))
      (node (ref "SV52") (pin "3") (pinfunction "3_3") (pintype "passive"))
      (node (ref "SV52") (pin "4") (pinfunction "4_4") (pintype "passive"))
    )
    (net (code "417") (name "Net-(IC26-Pad11)") (class "Default")
      (node (ref "IC26") (pin "11") (pinfunction "11_11") (pintype "passive"))
      (node (ref "SV52") (pin "5") (pinfunction "5_5") (pintype "passive"))
      (node (ref "SV52") (pin "6") (pinfunction "6_6") (pintype "passive"))
    )
    (net (code "418") (name "Net-(IC26-Pad12)") (class "Default")
      (node (ref "IC26") (pin "12") (pinfunction "12_12") (pintype "passive"))
      (node (ref "SV52") (pin "7") (pinfunction "7_7") (pintype "passive"))
      (node (ref "SV52") (pin "8") (pinfunction "8_8") (pintype "passive"))
    )
    (net (code "419") (name "Net-(IC26-Pad13)") (class "Default")
      (node (ref "IC26") (pin "13") (pinfunction "13_13") (pintype "passive"))
      (node (ref "SV52") (pin "10") (pinfunction "10_10") (pintype "passive"))
      (node (ref "SV52") (pin "9") (pinfunction "9_9") (pintype "passive"))
    )
    (net (code "420") (name "Net-(IC26-Pad14)") (class "Default")
      (node (ref "IC26") (pin "14") (pinfunction "14_14") (pintype "passive"))
      (node (ref "SV52") (pin "11") (pinfunction "11_11") (pintype "passive"))
      (node (ref "SV52") (pin "12") (pinfunction "12_12") (pintype "passive"))
    )
    (net (code "421") (name "Net-(IC26-Pad15)") (class "Default")
      (node (ref "IC26") (pin "15") (pinfunction "15_15") (pintype "passive"))
      (node (ref "SV52") (pin "13") (pinfunction "13_13") (pintype "passive"))
      (node (ref "SV52") (pin "14") (pinfunction "14_14") (pintype "passive"))
    )
    (net (code "422") (name "Net-(IC26-Pad16)") (class "Default")
      (node (ref "IC26") (pin "16") (pinfunction "16_16") (pintype "passive"))
      (node (ref "SV52") (pin "15") (pinfunction "15_15") (pintype "passive"))
      (node (ref "SV52") (pin "16") (pinfunction "16_16") (pintype "passive"))
    )
    (net (code "423") (name "Net-(IC27-Pad1)") (class "Default")
      (node (ref "IC27") (pin "1") (pinfunction "1_1") (pintype "passive"))
      (node (ref "SV53") (pin "15") (pinfunction "15_15") (pintype "passive"))
      (node (ref "SV53") (pin "16") (pinfunction "16_16") (pintype "passive"))
    )
    (net (code "424") (name "Net-(IC27-Pad2)") (class "Default")
      (node (ref "IC27") (pin "2") (pinfunction "2_2") (pintype "passive"))
      (node (ref "SV53") (pin "13") (pinfunction "13_13") (pintype "passive"))
      (node (ref "SV53") (pin "14") (pinfunction "14_14") (pintype "passive"))
    )
    (net (code "425") (name "Net-(IC27-Pad3)") (class "Default")
      (node (ref "IC27") (pin "3") (pinfunction "3_3") (pintype "passive"))
      (node (ref "SV53") (pin "11") (pinfunction "11_11") (pintype "passive"))
      (node (ref "SV53") (pin "12") (pinfunction "12_12") (pintype "passive"))
    )
    (net (code "426") (name "Net-(IC27-Pad4)") (class "Default")
      (node (ref "IC27") (pin "4") (pinfunction "4_4") (pintype "passive"))
      (node (ref "SV53") (pin "10") (pinfunction "10_10") (pintype "passive"))
      (node (ref "SV53") (pin "9") (pinfunction "9_9") (pintype "passive"))
    )
    (net (code "427") (name "Net-(IC27-Pad5)") (class "Default")
      (node (ref "IC27") (pin "5") (pinfunction "5_5") (pintype "passive"))
      (node (ref "SV53") (pin "7") (pinfunction "7_7") (pintype "passive"))
      (node (ref "SV53") (pin "8") (pinfunction "8_8") (pintype "passive"))
    )
    (net (code "428") (name "Net-(IC27-Pad6)") (class "Default")
      (node (ref "IC27") (pin "6") (pinfunction "6_6") (pintype "passive"))
      (node (ref "SV53") (pin "5") (pinfunction "5_5") (pintype "passive"))
      (node (ref "SV53") (pin "6") (pinfunction "6_6") (pintype "passive"))
    )
    (net (code "429") (name "Net-(IC27-Pad7)") (class "Default")
      (node (ref "IC27") (pin "7") (pinfunction "7_7") (pintype "passive"))
      (node (ref "SV53") (pin "3") (pinfunction "3_3") (pintype "passive"))
      (node (ref "SV53") (pin "4") (pinfunction "4_4") (pintype "passive"))
    )
    (net (code "430") (name "Net-(IC27-Pad8)") (class "Default")
      (node (ref "IC27") (pin "8") (pinfunction "8_8") (pintype "passive"))
      (node (ref "SV53") (pin "1") (pinfunction "1_1") (pintype "passive"))
      (node (ref "SV53") (pin "2") (pinfunction "2_2") (pintype "passive"))
    )
    (net (code "431") (name "Net-(IC27-Pad9)") (class "Default")
      (node (ref "IC27") (pin "9") (pinfunction "9_9") (pintype "passive"))
      (node (ref "SV54") (pin "1") (pinfunction "1_1") (pintype "passive"))
      (node (ref "SV54") (pin "2") (pinfunction "2_2") (pintype "passive"))
    )
    (net (code "432") (name "Net-(IC27-Pad10)") (class "Default")
      (node (ref "IC27") (pin "10") (pinfunction "10_10") (pintype "passive"))
      (node (ref "SV54") (pin "3") (pinfunction "3_3") (pintype "passive"))
      (node (ref "SV54") (pin "4") (pinfunction "4_4") (pintype "passive"))
    )
    (net (code "433") (name "Net-(IC27-Pad11)") (class "Default")
      (node (ref "IC27") (pin "11") (pinfunction "11_11") (pintype "passive"))
      (node (ref "SV54") (pin "5") (pinfunction "5_5") (pintype "passive"))
      (node (ref "SV54") (pin "6") (pinfunction "6_6") (pintype "passive"))
    )
    (net (code "434") (name "Net-(IC27-Pad12)") (class "Default")
      (node (ref "IC27") (pin "12") (pinfunction "12_12") (pintype "passive"))
      (node (ref "SV54") (pin "7") (pinfunction "7_7") (pintype "passive"))
      (node (ref "SV54") (pin "8") (pinfunction "8_8") (pintype "passive"))
    )
    (net (code "435") (name "Net-(IC27-Pad13)") (class "Default")
      (node (ref "IC27") (pin "13") (pinfunction "13_13") (pintype "passive"))
      (node (ref "SV54") (pin "10") (pinfunction "10_10") (pintype "passive"))
      (node (ref "SV54") (pin "9") (pinfunction "9_9") (pintype "passive"))
    )
    (net (code "436") (name "Net-(IC27-Pad14)") (class "Default")
      (node (ref "IC27") (pin "14") (pinfunction "14_14") (pintype "passive"))
      (node (ref "SV54") (pin "11") (pinfunction "11_11") (pintype "passive"))
      (node (ref "SV54") (pin "12") (pinfunction "12_12") (pintype "passive"))
    )
    (net (code "437") (name "Net-(IC27-Pad15)") (class "Default")
      (node (ref "IC27") (pin "15") (pinfunction "15_15") (pintype "passive"))
      (node (ref "SV54") (pin "13") (pinfunction "13_13") (pintype "passive"))
      (node (ref "SV54") (pin "14") (pinfunction "14_14") (pintype "passive"))
    )
    (net (code "438") (name "Net-(IC27-Pad16)") (class "Default")
      (node (ref "IC27") (pin "16") (pinfunction "16_16") (pintype "passive"))
      (node (ref "SV54") (pin "15") (pinfunction "15_15") (pintype "passive"))
      (node (ref "SV54") (pin "16") (pinfunction "16_16") (pintype "passive"))
    )
    (net (code "439") (name "Net-(IC28-Pad1)") (class "Default")
      (node (ref "IC28") (pin "1") (pinfunction "1_1") (pintype "passive"))
      (node (ref "SV55") (pin "15") (pinfunction "15_15") (pintype "passive"))
      (node (ref "SV55") (pin "16") (pinfunction "16_16") (pintype "passive"))
    )
    (net (code "440") (name "Net-(IC28-Pad2)") (class "Default")
      (node (ref "IC28") (pin "2") (pinfunction "2_2") (pintype "passive"))
      (node (ref "SV55") (pin "13") (pinfunction "13_13") (pintype "passive"))
      (node (ref "SV55") (pin "14") (pinfunction "14_14") (pintype "passive"))
    )
    (net (code "441") (name "Net-(IC28-Pad3)") (class "Default")
      (node (ref "IC28") (pin "3") (pinfunction "3_3") (pintype "passive"))
      (node (ref "SV55") (pin "11") (pinfunction "11_11") (pintype "passive"))
      (node (ref "SV55") (pin "12") (pinfunction "12_12") (pintype "passive"))
    )
    (net (code "442") (name "Net-(IC28-Pad4)") (class "Default")
      (node (ref "IC28") (pin "4") (pinfunction "4_4") (pintype "passive"))
      (node (ref "SV55") (pin "10") (pinfunction "10_10") (pintype "passive"))
      (node (ref "SV55") (pin "9") (pinfunction "9_9") (pintype "passive"))
    )
    (net (code "443") (name "Net-(IC28-Pad5)") (class "Default")
      (node (ref "IC28") (pin "5") (pinfunction "5_5") (pintype "passive"))
      (node (ref "SV55") (pin "7") (pinfunction "7_7") (pintype "passive"))
      (node (ref "SV55") (pin "8") (pinfunction "8_8") (pintype "passive"))
    )
    (net (code "444") (name "Net-(IC28-Pad6)") (class "Default")
      (node (ref "IC28") (pin "6") (pinfunction "6_6") (pintype "passive"))
      (node (ref "SV55") (pin "5") (pinfunction "5_5") (pintype "passive"))
      (node (ref "SV55") (pin "6") (pinfunction "6_6") (pintype "passive"))
    )
    (net (code "445") (name "Net-(IC28-Pad7)") (class "Default")
      (node (ref "IC28") (pin "7") (pinfunction "7_7") (pintype "passive"))
      (node (ref "SV55") (pin "3") (pinfunction "3_3") (pintype "passive"))
      (node (ref "SV55") (pin "4") (pinfunction "4_4") (pintype "passive"))
    )
    (net (code "446") (name "Net-(IC28-Pad8)") (class "Default")
      (node (ref "IC28") (pin "8") (pinfunction "8_8") (pintype "passive"))
      (node (ref "SV55") (pin "1") (pinfunction "1_1") (pintype "passive"))
      (node (ref "SV55") (pin "2") (pinfunction "2_2") (pintype "passive"))
    )
    (net (code "447") (name "Net-(IC28-Pad9)") (class "Default")
      (node (ref "IC28") (pin "9") (pinfunction "9_9") (pintype "passive"))
      (node (ref "SV56") (pin "1") (pinfunction "1_1") (pintype "passive"))
      (node (ref "SV56") (pin "2") (pinfunction "2_2") (pintype "passive"))
    )
    (net (code "448") (name "Net-(IC28-Pad10)") (class "Default")
      (node (ref "IC28") (pin "10") (pinfunction "10_10") (pintype "passive"))
      (node (ref "SV56") (pin "3") (pinfunction "3_3") (pintype "passive"))
      (node (ref "SV56") (pin "4") (pinfunction "4_4") (pintype "passive"))
    )
    (net (code "449") (name "Net-(IC28-Pad11)") (class "Default")
      (node (ref "IC28") (pin "11") (pinfunction "11_11") (pintype "passive"))
      (node (ref "SV56") (pin "5") (pinfunction "5_5") (pintype "passive"))
      (node (ref "SV56") (pin "6") (pinfunction "6_6") (pintype "passive"))
    )
    (net (code "450") (name "Net-(IC28-Pad12)") (class "Default")
      (node (ref "IC28") (pin "12") (pinfunction "12_12") (pintype "passive"))
      (node (ref "SV56") (pin "7") (pinfunction "7_7") (pintype "passive"))
      (node (ref "SV56") (pin "8") (pinfunction "8_8") (pintype "passive"))
    )
    (net (code "451") (name "Net-(IC28-Pad13)") (class "Default")
      (node (ref "IC28") (pin "13") (pinfunction "13_13") (pintype "passive"))
      (node (ref "SV56") (pin "10") (pinfunction "10_10") (pintype "passive"))
      (node (ref "SV56") (pin "9") (pinfunction "9_9") (pintype "passive"))
    )
    (net (code "452") (name "Net-(IC28-Pad14)") (class "Default")
      (node (ref "IC28") (pin "14") (pinfunction "14_14") (pintype "passive"))
      (node (ref "SV56") (pin "11") (pinfunction "11_11") (pintype "passive"))
      (node (ref "SV56") (pin "12") (pinfunction "12_12") (pintype "passive"))
    )
    (net (code "453") (name "Net-(IC28-Pad15)") (class "Default")
      (node (ref "IC28") (pin "15") (pinfunction "15_15") (pintype "passive"))
      (node (ref "SV56") (pin "13") (pinfunction "13_13") (pintype "passive"))
      (node (ref "SV56") (pin "14") (pinfunction "14_14") (pintype "passive"))
    )
    (net (code "454") (name "Net-(IC28-Pad16)") (class "Default")
      (node (ref "IC28") (pin "16") (pinfunction "16_16") (pintype "passive"))
      (node (ref "SV56") (pin "15") (pinfunction "15_15") (pintype "passive"))
      (node (ref "SV56") (pin "16") (pinfunction "16_16") (pintype "passive"))
    )
    (net (code "455") (name "Net-(IC29-Pad1)") (class "Default")
      (node (ref "IC29") (pin "1") (pinfunction "1_1") (pintype "passive"))
      (node (ref "SV57") (pin "15") (pinfunction "15_15") (pintype "passive"))
      (node (ref "SV57") (pin "16") (pinfunction "16_16") (pintype "passive"))
    )
    (net (code "456") (name "Net-(IC29-Pad2)") (class "Default")
      (node (ref "IC29") (pin "2") (pinfunction "2_2") (pintype "passive"))
      (node (ref "SV57") (pin "13") (pinfunction "13_13") (pintype "passive"))
      (node (ref "SV57") (pin "14") (pinfunction "14_14") (pintype "passive"))
    )
    (net (code "457") (name "Net-(IC29-Pad3)") (class "Default")
      (node (ref "IC29") (pin "3") (pinfunction "3_3") (pintype "passive"))
      (node (ref "SV57") (pin "11") (pinfunction "11_11") (pintype "passive"))
      (node (ref "SV57") (pin "12") (pinfunction "12_12") (pintype "passive"))
    )
    (net (code "458") (name "Net-(IC29-Pad4)") (class "Default")
      (node (ref "IC29") (pin "4") (pinfunction "4_4") (pintype "passive"))
      (node (ref "SV57") (pin "10") (pinfunction "10_10") (pintype "passive"))
      (node (ref "SV57") (pin "9") (pinfunction "9_9") (pintype "passive"))
    )
    (net (code "459") (name "Net-(IC29-Pad5)") (class "Default")
      (node (ref "IC29") (pin "5") (pinfunction "5_5") (pintype "passive"))
      (node (ref "SV57") (pin "7") (pinfunction "7_7") (pintype "passive"))
      (node (ref "SV57") (pin "8") (pinfunction "8_8") (pintype "passive"))
    )
    (net (code "460") (name "Net-(IC29-Pad6)") (class "Default")
      (node (ref "IC29") (pin "6") (pinfunction "6_6") (pintype "passive"))
      (node (ref "SV57") (pin "5") (pinfunction "5_5") (pintype "passive"))
      (node (ref "SV57") (pin "6") (pinfunction "6_6") (pintype "passive"))
    )
    (net (code "461") (name "Net-(IC29-Pad7)") (class "Default")
      (node (ref "IC29") (pin "7") (pinfunction "7_7") (pintype "passive"))
      (node (ref "SV57") (pin "3") (pinfunction "3_3") (pintype "passive"))
      (node (ref "SV57") (pin "4") (pinfunction "4_4") (pintype "passive"))
    )
    (net (code "462") (name "Net-(IC29-Pad8)") (class "Default")
      (node (ref "IC29") (pin "8") (pinfunction "8_8") (pintype "passive"))
      (node (ref "SV57") (pin "1") (pinfunction "1_1") (pintype "passive"))
      (node (ref "SV57") (pin "2") (pinfunction "2_2") (pintype "passive"))
    )
    (net (code "463") (name "Net-(IC29-Pad9)") (class "Default")
      (node (ref "IC29") (pin "9") (pinfunction "9_9") (pintype "passive"))
      (node (ref "SV58") (pin "1") (pinfunction "1_1") (pintype "passive"))
      (node (ref "SV58") (pin "2") (pinfunction "2_2") (pintype "passive"))
    )
    (net (code "464") (name "Net-(IC29-Pad10)") (class "Default")
      (node (ref "IC29") (pin "10") (pinfunction "10_10") (pintype "passive"))
      (node (ref "SV58") (pin "3") (pinfunction "3_3") (pintype "passive"))
      (node (ref "SV58") (pin "4") (pinfunction "4_4") (pintype "passive"))
    )
    (net (code "465") (name "Net-(IC29-Pad11)") (class "Default")
      (node (ref "IC29") (pin "11") (pinfunction "11_11") (pintype "passive"))
      (node (ref "SV58") (pin "5") (pinfunction "5_5") (pintype "passive"))
      (node (ref "SV58") (pin "6") (pinfunction "6_6") (pintype "passive"))
    )
    (net (code "466") (name "Net-(IC29-Pad12)") (class "Default")
      (node (ref "IC29") (pin "12") (pinfunction "12_12") (pintype "passive"))
      (node (ref "SV58") (pin "7") (pinfunction "7_7") (pintype "passive"))
      (node (ref "SV58") (pin "8") (pinfunction "8_8") (pintype "passive"))
    )
    (net (code "467") (name "Net-(IC29-Pad13)") (class "Default")
      (node (ref "IC29") (pin "13") (pinfunction "13_13") (pintype "passive"))
      (node (ref "SV58") (pin "10") (pinfunction "10_10") (pintype "passive"))
      (node (ref "SV58") (pin "9") (pinfunction "9_9") (pintype "passive"))
    )
    (net (code "468") (name "Net-(IC29-Pad14)") (class "Default")
      (node (ref "IC29") (pin "14") (pinfunction "14_14") (pintype "passive"))
      (node (ref "SV58") (pin "11") (pinfunction "11_11") (pintype "passive"))
      (node (ref "SV58") (pin "12") (pinfunction "12_12") (pintype "passive"))
    )
    (net (code "469") (name "Net-(IC29-Pad15)") (class "Default")
      (node (ref "IC29") (pin "15") (pinfunction "15_15") (pintype "passive"))
      (node (ref "SV58") (pin "13") (pinfunction "13_13") (pintype "passive"))
      (node (ref "SV58") (pin "14") (pinfunction "14_14") (pintype "passive"))
    )
    (net (code "470") (name "Net-(IC29-Pad16)") (class "Default")
      (node (ref "IC29") (pin "16") (pinfunction "16_16") (pintype "passive"))
      (node (ref "SV58") (pin "15") (pinfunction "15_15") (pintype "passive"))
      (node (ref "SV58") (pin "16") (pinfunction "16_16") (pintype "passive"))
    )
    (net (code "471") (name "Net-(IC30-Pad1)") (class "Default")
      (node (ref "IC30") (pin "1") (pinfunction "1_1") (pintype "passive"))
      (node (ref "SV59") (pin "15") (pinfunction "15_15") (pintype "passive"))
      (node (ref "SV59") (pin "16") (pinfunction "16_16") (pintype "passive"))
    )
    (net (code "472") (name "Net-(IC30-Pad2)") (class "Default")
      (node (ref "IC30") (pin "2") (pinfunction "2_2") (pintype "passive"))
      (node (ref "SV59") (pin "13") (pinfunction "13_13") (pintype "passive"))
      (node (ref "SV59") (pin "14") (pinfunction "14_14") (pintype "passive"))
    )
    (net (code "473") (name "Net-(IC30-Pad3)") (class "Default")
      (node (ref "IC30") (pin "3") (pinfunction "3_3") (pintype "passive"))
      (node (ref "SV59") (pin "11") (pinfunction "11_11") (pintype "passive"))
      (node (ref "SV59") (pin "12") (pinfunction "12_12") (pintype "passive"))
    )
    (net (code "474") (name "Net-(IC30-Pad4)") (class "Default")
      (node (ref "IC30") (pin "4") (pinfunction "4_4") (pintype "passive"))
      (node (ref "SV59") (pin "10") (pinfunction "10_10") (pintype "passive"))
      (node (ref "SV59") (pin "9") (pinfunction "9_9") (pintype "passive"))
    )
    (net (code "475") (name "Net-(IC30-Pad5)") (class "Default")
      (node (ref "IC30") (pin "5") (pinfunction "5_5") (pintype "passive"))
      (node (ref "SV59") (pin "7") (pinfunction "7_7") (pintype "passive"))
      (node (ref "SV59") (pin "8") (pinfunction "8_8") (pintype "passive"))
    )
    (net (code "476") (name "Net-(IC30-Pad6)") (class "Default")
      (node (ref "IC30") (pin "6") (pinfunction "6_6") (pintype "passive"))
      (node (ref "SV59") (pin "5") (pinfunction "5_5") (pintype "passive"))
      (node (ref "SV59") (pin "6") (pinfunction "6_6") (pintype "passive"))
    )
    (net (code "477") (name "Net-(IC30-Pad7)") (class "Default")
      (node (ref "IC30") (pin "7") (pinfunction "7_7") (pintype "passive"))
      (node (ref "SV59") (pin "3") (pinfunction "3_3") (pintype "passive"))
      (node (ref "SV59") (pin "4") (pinfunction "4_4") (pintype "passive"))
    )
    (net (code "478") (name "Net-(IC30-Pad8)") (class "Default")
      (node (ref "IC30") (pin "8") (pinfunction "8_8") (pintype "passive"))
      (node (ref "SV59") (pin "1") (pinfunction "1_1") (pintype "passive"))
      (node (ref "SV59") (pin "2") (pinfunction "2_2") (pintype "passive"))
    )
    (net (code "479") (name "Net-(IC30-Pad9)") (class "Default")
      (node (ref "IC30") (pin "9") (pinfunction "9_9") (pintype "passive"))
      (node (ref "SV60") (pin "1") (pinfunction "1_1") (pintype "passive"))
      (node (ref "SV60") (pin "2") (pinfunction "2_2") (pintype "passive"))
    )
    (net (code "480") (name "Net-(IC30-Pad10)") (class "Default")
      (node (ref "IC30") (pin "10") (pinfunction "10_10") (pintype "passive"))
      (node (ref "SV60") (pin "3") (pinfunction "3_3") (pintype "passive"))
      (node (ref "SV60") (pin "4") (pinfunction "4_4") (pintype "passive"))
    )
    (net (code "481") (name "Net-(IC30-Pad11)") (class "Default")
      (node (ref "IC30") (pin "11") (pinfunction "11_11") (pintype "passive"))
      (node (ref "SV60") (pin "5") (pinfunction "5_5") (pintype "passive"))
      (node (ref "SV60") (pin "6") (pinfunction "6_6") (pintype "passive"))
    )
    (net (code "482") (name "Net-(IC30-Pad12)") (class "Default")
      (node (ref "IC30") (pin "12") (pinfunction "12_12") (pintype "passive"))
      (node (ref "SV60") (pin "7") (pinfunction "7_7") (pintype "passive"))
      (node (ref "SV60") (pin "8") (pinfunction "8_8") (pintype "passive"))
    )
    (net (code "483") (name "Net-(IC30-Pad13)") (class "Default")
      (node (ref "IC30") (pin "13") (pinfunction "13_13") (pintype "passive"))
      (node (ref "SV60") (pin "10") (pinfunction "10_10") (pintype "passive"))
      (node (ref "SV60") (pin "9") (pinfunction "9_9") (pintype "passive"))
    )
    (net (code "484") (name "Net-(IC30-Pad14)") (class "Default")
      (node (ref "IC30") (pin "14") (pinfunction "14_14") (pintype "passive"))
      (node (ref "SV60") (pin "11") (pinfunction "11_11") (pintype "passive"))
      (node (ref "SV60") (pin "12") (pinfunction "12_12") (pintype "passive"))
    )
    (net (code "485") (name "Net-(IC30-Pad15)") (class "Default")
      (node (ref "IC30") (pin "15") (pinfunction "15_15") (pintype "passive"))
      (node (ref "SV60") (pin "13") (pinfunction "13_13") (pintype "passive"))
      (node (ref "SV60") (pin "14") (pinfunction "14_14") (pintype "passive"))
    )
    (net (code "486") (name "Net-(IC30-Pad16)") (class "Default")
      (node (ref "IC30") (pin "16") (pinfunction "16_16") (pintype "passive"))
      (node (ref "SV60") (pin "15") (pinfunction "15_15") (pintype "passive"))
      (node (ref "SV60") (pin "16") (pinfunction "16_16") (pintype "passive"))
    )
    (net (code "487") (name "Net-(IC31-Pad1)") (class "Default")
      (node (ref "IC31") (pin "1") (pinfunction "1_1") (pintype "passive"))
      (node (ref "SV61") (pin "15") (pinfunction "15_15") (pintype "passive"))
      (node (ref "SV61") (pin "16") (pinfunction "16_16") (pintype "passive"))
    )
    (net (code "488") (name "Net-(IC31-Pad2)") (class "Default")
      (node (ref "IC31") (pin "2") (pinfunction "2_2") (pintype "passive"))
      (node (ref "SV61") (pin "13") (pinfunction "13_13") (pintype "passive"))
      (node (ref "SV61") (pin "14") (pinfunction "14_14") (pintype "passive"))
    )
    (net (code "489") (name "Net-(IC31-Pad3)") (class "Default")
      (node (ref "IC31") (pin "3") (pinfunction "3_3") (pintype "passive"))
      (node (ref "SV61") (pin "11") (pinfunction "11_11") (pintype "passive"))
      (node (ref "SV61") (pin "12") (pinfunction "12_12") (pintype "passive"))
    )
    (net (code "490") (name "Net-(IC31-Pad4)") (class "Default")
      (node (ref "IC31") (pin "4") (pinfunction "4_4") (pintype "passive"))
      (node (ref "SV61") (pin "10") (pinfunction "10_10") (pintype "passive"))
      (node (ref "SV61") (pin "9") (pinfunction "9_9") (pintype "passive"))
    )
    (net (code "491") (name "Net-(IC31-Pad5)") (class "Default")
      (node (ref "IC31") (pin "5") (pinfunction "5_5") (pintype "passive"))
      (node (ref "SV61") (pin "7") (pinfunction "7_7") (pintype "passive"))
      (node (ref "SV61") (pin "8") (pinfunction "8_8") (pintype "passive"))
    )
    (net (code "492") (name "Net-(IC31-Pad6)") (class "Default")
      (node (ref "IC31") (pin "6") (pinfunction "6_6") (pintype "passive"))
      (node (ref "SV61") (pin "5") (pinfunction "5_5") (pintype "passive"))
      (node (ref "SV61") (pin "6") (pinfunction "6_6") (pintype "passive"))
    )
    (net (code "493") (name "Net-(IC31-Pad7)") (class "Default")
      (node (ref "IC31") (pin "7") (pinfunction "7_7") (pintype "passive"))
      (node (ref "SV61") (pin "3") (pinfunction "3_3") (pintype "passive"))
      (node (ref "SV61") (pin "4") (pinfunction "4_4") (pintype "passive"))
    )
    (net (code "494") (name "Net-(IC31-Pad8)") (class "Default")
      (node (ref "IC31") (pin "8") (pinfunction "8_8") (pintype "passive"))
      (node (ref "SV61") (pin "1") (pinfunction "1_1") (pintype "passive"))
      (node (ref "SV61") (pin "2") (pinfunction "2_2") (pintype "passive"))
    )
    (net (code "495") (name "Net-(IC31-Pad9)") (class "Default")
      (node (ref "IC31") (pin "9") (pinfunction "9_9") (pintype "passive"))
      (node (ref "SV62") (pin "1") (pinfunction "1_1") (pintype "passive"))
      (node (ref "SV62") (pin "2") (pinfunction "2_2") (pintype "passive"))
    )
    (net (code "496") (name "Net-(IC31-Pad10)") (class "Default")
      (node (ref "IC31") (pin "10") (pinfunction "10_10") (pintype "passive"))
      (node (ref "SV62") (pin "3") (pinfunction "3_3") (pintype "passive"))
      (node (ref "SV62") (pin "4") (pinfunction "4_4") (pintype "passive"))
    )
    (net (code "497") (name "Net-(IC31-Pad11)") (class "Default")
      (node (ref "IC31") (pin "11") (pinfunction "11_11") (pintype "passive"))
      (node (ref "SV62") (pin "5") (pinfunction "5_5") (pintype "passive"))
      (node (ref "SV62") (pin "6") (pinfunction "6_6") (pintype "passive"))
    )
    (net (code "498") (name "Net-(IC31-Pad12)") (class "Default")
      (node (ref "IC31") (pin "12") (pinfunction "12_12") (pintype "passive"))
      (node (ref "SV62") (pin "7") (pinfunction "7_7") (pintype "passive"))
      (node (ref "SV62") (pin "8") (pinfunction "8_8") (pintype "passive"))
    )
    (net (code "499") (name "Net-(IC31-Pad13)") (class "Default")
      (node (ref "IC31") (pin "13") (pinfunction "13_13") (pintype "passive"))
      (node (ref "SV62") (pin "10") (pinfunction "10_10") (pintype "passive"))
      (node (ref "SV62") (pin "9") (pinfunction "9_9") (pintype "passive"))
    )
    (net (code "500") (name "Net-(IC31-Pad14)") (class "Default")
      (node (ref "IC31") (pin "14") (pinfunction "14_14") (pintype "passive"))
      (node (ref "SV62") (pin "11") (pinfunction "11_11") (pintype "passive"))
      (node (ref "SV62") (pin "12") (pinfunction "12_12") (pintype "passive"))
    )
    (net (code "501") (name "Net-(IC31-Pad15)") (class "Default")
      (node (ref "IC31") (pin "15") (pinfunction "15_15") (pintype "passive"))
      (node (ref "SV62") (pin "13") (pinfunction "13_13") (pintype "passive"))
      (node (ref "SV62") (pin "14") (pinfunction "14_14") (pintype "passive"))
    )
    (net (code "502") (name "Net-(IC31-Pad16)") (class "Default")
      (node (ref "IC31") (pin "16") (pinfunction "16_16") (pintype "passive"))
      (node (ref "SV62") (pin "15") (pinfunction "15_15") (pintype "passive"))
      (node (ref "SV62") (pin "16") (pinfunction "16_16") (pintype "passive"))
    )
    (net (code "503") (name "Net-(IC32-Pad1)") (class "Default")
      (node (ref "IC32") (pin "1") (pinfunction "1_1") (pintype "passive"))
      (node (ref "SV63") (pin "15") (pinfunction "15_15") (pintype "passive"))
      (node (ref "SV63") (pin "16") (pinfunction "16_16") (pintype "passive"))
    )
    (net (code "504") (name "Net-(IC32-Pad2)") (class "Default")
      (node (ref "IC32") (pin "2") (pinfunction "2_2") (pintype "passive"))
      (node (ref "SV63") (pin "13") (pinfunction "13_13") (pintype "passive"))
      (node (ref "SV63") (pin "14") (pinfunction "14_14") (pintype "passive"))
    )
    (net (code "505") (name "Net-(IC32-Pad3)") (class "Default")
      (node (ref "IC32") (pin "3") (pinfunction "3_3") (pintype "passive"))
      (node (ref "SV63") (pin "11") (pinfunction "11_11") (pintype "passive"))
      (node (ref "SV63") (pin "12") (pinfunction "12_12") (pintype "passive"))
    )
    (net (code "506") (name "Net-(IC32-Pad4)") (class "Default")
      (node (ref "IC32") (pin "4") (pinfunction "4_4") (pintype "passive"))
      (node (ref "SV63") (pin "10") (pinfunction "10_10") (pintype "passive"))
      (node (ref "SV63") (pin "9") (pinfunction "9_9") (pintype "passive"))
    )
    (net (code "507") (name "Net-(IC32-Pad5)") (class "Default")
      (node (ref "IC32") (pin "5") (pinfunction "5_5") (pintype "passive"))
      (node (ref "SV63") (pin "7") (pinfunction "7_7") (pintype "passive"))
      (node (ref "SV63") (pin "8") (pinfunction "8_8") (pintype "passive"))
    )
    (net (code "508") (name "Net-(IC32-Pad6)") (class "Default")
      (node (ref "IC32") (pin "6") (pinfunction "6_6") (pintype "passive"))
      (node (ref "SV63") (pin "5") (pinfunction "5_5") (pintype "passive"))
      (node (ref "SV63") (pin "6") (pinfunction "6_6") (pintype "passive"))
    )
    (net (code "509") (name "Net-(IC32-Pad7)") (class "Default")
      (node (ref "IC32") (pin "7") (pinfunction "7_7") (pintype "passive"))
      (node (ref "SV63") (pin "3") (pinfunction "3_3") (pintype "passive"))
      (node (ref "SV63") (pin "4") (pinfunction "4_4") (pintype "passive"))
    )
    (net (code "510") (name "Net-(IC32-Pad8)") (class "Default")
      (node (ref "IC32") (pin "8") (pinfunction "8_8") (pintype "passive"))
      (node (ref "SV63") (pin "1") (pinfunction "1_1") (pintype "passive"))
      (node (ref "SV63") (pin "2") (pinfunction "2_2") (pintype "passive"))
    )
    (net (code "511") (name "Net-(IC32-Pad9)") (class "Default")
      (node (ref "IC32") (pin "9") (pinfunction "9_9") (pintype "passive"))
      (node (ref "SV64") (pin "1") (pinfunction "1_1") (pintype "passive"))
      (node (ref "SV64") (pin "2") (pinfunction "2_2") (pintype "passive"))
    )
    (net (code "512") (name "Net-(IC32-Pad10)") (class "Default")
      (node (ref "IC32") (pin "10") (pinfunction "10_10") (pintype "passive"))
      (node (ref "SV64") (pin "3") (pinfunction "3_3") (pintype "passive"))
      (node (ref "SV64") (pin "4") (pinfunction "4_4") (pintype "passive"))
    )
    (net (code "513") (name "Net-(IC32-Pad11)") (class "Default")
      (node (ref "IC32") (pin "11") (pinfunction "11_11") (pintype "passive"))
      (node (ref "SV64") (pin "5") (pinfunction "5_5") (pintype "passive"))
      (node (ref "SV64") (pin "6") (pinfunction "6_6") (pintype "passive"))
    )
    (net (code "514") (name "Net-(IC32-Pad12)") (class "Default")
      (node (ref "IC32") (pin "12") (pinfunction "12_12") (pintype "passive"))
      (node (ref "SV64") (pin "7") (pinfunction "7_7") (pintype "passive"))
      (node (ref "SV64") (pin "8") (pinfunction "8_8") (pintype "passive"))
    )
    (net (code "515") (name "Net-(IC32-Pad13)") (class "Default")
      (node (ref "IC32") (pin "13") (pinfunction "13_13") (pintype "passive"))
      (node (ref "SV64") (pin "10") (pinfunction "10_10") (pintype "passive"))
      (node (ref "SV64") (pin "9") (pinfunction "9_9") (pintype "passive"))
    )
    (net (code "516") (name "Net-(IC32-Pad14)") (class "Default")
      (node (ref "IC32") (pin "14") (pinfunction "14_14") (pintype "passive"))
      (node (ref "SV64") (pin "11") (pinfunction "11_11") (pintype "passive"))
      (node (ref "SV64") (pin "12") (pinfunction "12_12") (pintype "passive"))
    )
    (net (code "517") (name "Net-(IC32-Pad15)") (class "Default")
      (node (ref "IC32") (pin "15") (pinfunction "15_15") (pintype "passive"))
      (node (ref "SV64") (pin "13") (pinfunction "13_13") (pintype "passive"))
      (node (ref "SV64") (pin "14") (pinfunction "14_14") (pintype "passive"))
    )
    (net (code "518") (name "Net-(IC32-Pad16)") (class "Default")
      (node (ref "IC32") (pin "16") (pinfunction "16_16") (pintype "passive"))
      (node (ref "SV64") (pin "15") (pinfunction "15_15") (pintype "passive"))
      (node (ref "SV64") (pin "16") (pinfunction "16_16") (pintype "passive"))
    )
    (net (code "519") (name "Net-(IC33-Pad1)") (class "Default")
      (node (ref "IC33") (pin "1") (pinfunction "1_1") (pintype "passive"))
      (node (ref "SV65") (pin "15") (pinfunction "15_15") (pintype "passive"))
      (node (ref "SV65") (pin "16") (pinfunction "16_16") (pintype "passive"))
    )
    (net (code "520") (name "Net-(IC33-Pad2)") (class "Default")
      (node (ref "IC33") (pin "2") (pinfunction "2_2") (pintype "passive"))
      (node (ref "SV65") (pin "13") (pinfunction "13_13") (pintype "passive"))
      (node (ref "SV65") (pin "14") (pinfunction "14_14") (pintype "passive"))
    )
    (net (code "521") (name "Net-(IC33-Pad3)") (class "Default")
      (node (ref "IC33") (pin "3") (pinfunction "3_3") (pintype "passive"))
      (node (ref "SV65") (pin "11") (pinfunction "11_11") (pintype "passive"))
      (node (ref "SV65") (pin "12") (pinfunction "12_12") (pintype "passive"))
    )
    (net (code "522") (name "Net-(IC33-Pad4)") (class "Default")
      (node (ref "IC33") (pin "4") (pinfunction "4_4") (pintype "passive"))
      (node (ref "SV65") (pin "10") (pinfunction "10_10") (pintype "passive"))
      (node (ref "SV65") (pin "9") (pinfunction "9_9") (pintype "passive"))
    )
    (net (code "523") (name "Net-(IC33-Pad5)") (class "Default")
      (node (ref "IC33") (pin "5") (pinfunction "5_5") (pintype "passive"))
      (node (ref "SV65") (pin "7") (pinfunction "7_7") (pintype "passive"))
      (node (ref "SV65") (pin "8") (pinfunction "8_8") (pintype "passive"))
    )
    (net (code "524") (name "Net-(IC33-Pad6)") (class "Default")
      (node (ref "IC33") (pin "6") (pinfunction "6_6") (pintype "passive"))
      (node (ref "SV65") (pin "5") (pinfunction "5_5") (pintype "passive"))
      (node (ref "SV65") (pin "6") (pinfunction "6_6") (pintype "passive"))
    )
    (net (code "525") (name "Net-(IC33-Pad7)") (class "Default")
      (node (ref "IC33") (pin "7") (pinfunction "7_7") (pintype "passive"))
      (node (ref "SV65") (pin "3") (pinfunction "3_3") (pintype "passive"))
      (node (ref "SV65") (pin "4") (pinfunction "4_4") (pintype "passive"))
    )
    (net (code "526") (name "Net-(IC33-Pad8)") (class "Default")
      (node (ref "IC33") (pin "8") (pinfunction "8_8") (pintype "passive"))
      (node (ref "SV65") (pin "1") (pinfunction "1_1") (pintype "passive"))
      (node (ref "SV65") (pin "2") (pinfunction "2_2") (pintype "passive"))
    )
    (net (code "527") (name "Net-(IC33-Pad9)") (class "Default")
      (node (ref "IC33") (pin "9") (pinfunction "9_9") (pintype "passive"))
      (node (ref "SV66") (pin "1") (pinfunction "1_1") (pintype "passive"))
      (node (ref "SV66") (pin "2") (pinfunction "2_2") (pintype "passive"))
    )
    (net (code "528") (name "Net-(IC33-Pad10)") (class "Default")
      (node (ref "IC33") (pin "10") (pinfunction "10_10") (pintype "passive"))
      (node (ref "SV66") (pin "3") (pinfunction "3_3") (pintype "passive"))
      (node (ref "SV66") (pin "4") (pinfunction "4_4") (pintype "passive"))
    )
    (net (code "529") (name "Net-(IC33-Pad11)") (class "Default")
      (node (ref "IC33") (pin "11") (pinfunction "11_11") (pintype "passive"))
      (node (ref "SV66") (pin "5") (pinfunction "5_5") (pintype "passive"))
      (node (ref "SV66") (pin "6") (pinfunction "6_6") (pintype "passive"))
    )
    (net (code "530") (name "Net-(IC33-Pad12)") (class "Default")
      (node (ref "IC33") (pin "12") (pinfunction "12_12") (pintype "passive"))
      (node (ref "SV66") (pin "7") (pinfunction "7_7") (pintype "passive"))
      (node (ref "SV66") (pin "8") (pinfunction "8_8") (pintype "passive"))
    )
    (net (code "531") (name "Net-(IC33-Pad13)") (class "Default")
      (node (ref "IC33") (pin "13") (pinfunction "13_13") (pintype "passive"))
      (node (ref "SV66") (pin "10") (pinfunction "10_10") (pintype "passive"))
      (node (ref "SV66") (pin "9") (pinfunction "9_9") (pintype "passive"))
    )
    (net (code "532") (name "Net-(IC33-Pad14)") (class "Default")
      (node (ref "IC33") (pin "14") (pinfunction "14_14") (pintype "passive"))
      (node (ref "SV66") (pin "11") (pinfunction "11_11") (pintype "passive"))
      (node (ref "SV66") (pin "12") (pinfunction "12_12") (pintype "passive"))
    )
    (net (code "533") (name "Net-(IC33-Pad15)") (class "Default")
      (node (ref "IC33") (pin "15") (pinfunction "15_15") (pintype "passive"))
      (node (ref "SV66") (pin "13") (pinfunction "13_13") (pintype "passive"))
      (node (ref "SV66") (pin "14") (pinfunction "14_14") (pintype "passive"))
    )
    (net (code "534") (name "Net-(IC33-Pad16)") (class "Default")
      (node (ref "IC33") (pin "16") (pinfunction "16_16") (pintype "passive"))
      (node (ref "SV66") (pin "15") (pinfunction "15_15") (pintype "passive"))
      (node (ref "SV66") (pin "16") (pinfunction "16_16") (pintype "passive"))
    )
    (net (code "535") (name "Net-(IC34-Pad1)") (class "Default")
      (node (ref "IC34") (pin "1") (pinfunction "1_1") (pintype "passive"))
      (node (ref "SV67") (pin "15") (pinfunction "15_15") (pintype "passive"))
      (node (ref "SV67") (pin "16") (pinfunction "16_16") (pintype "passive"))
    )
    (net (code "536") (name "Net-(IC34-Pad2)") (class "Default")
      (node (ref "IC34") (pin "2") (pinfunction "2_2") (pintype "passive"))
      (node (ref "SV67") (pin "13") (pinfunction "13_13") (pintype "passive"))
      (node (ref "SV67") (pin "14") (pinfunction "14_14") (pintype "passive"))
    )
    (net (code "537") (name "Net-(IC34-Pad3)") (class "Default")
      (node (ref "IC34") (pin "3") (pinfunction "3_3") (pintype "passive"))
      (node (ref "SV67") (pin "11") (pinfunction "11_11") (pintype "passive"))
      (node (ref "SV67") (pin "12") (pinfunction "12_12") (pintype "passive"))
    )
    (net (code "538") (name "Net-(IC34-Pad4)") (class "Default")
      (node (ref "IC34") (pin "4") (pinfunction "4_4") (pintype "passive"))
      (node (ref "SV67") (pin "10") (pinfunction "10_10") (pintype "passive"))
      (node (ref "SV67") (pin "9") (pinfunction "9_9") (pintype "passive"))
    )
    (net (code "539") (name "Net-(IC34-Pad5)") (class "Default")
      (node (ref "IC34") (pin "5") (pinfunction "5_5") (pintype "passive"))
      (node (ref "SV67") (pin "7") (pinfunction "7_7") (pintype "passive"))
      (node (ref "SV67") (pin "8") (pinfunction "8_8") (pintype "passive"))
    )
    (net (code "540") (name "Net-(IC34-Pad6)") (class "Default")
      (node (ref "IC34") (pin "6") (pinfunction "6_6") (pintype "passive"))
      (node (ref "SV67") (pin "5") (pinfunction "5_5") (pintype "passive"))
      (node (ref "SV67") (pin "6") (pinfunction "6_6") (pintype "passive"))
    )
    (net (code "541") (name "Net-(IC34-Pad7)") (class "Default")
      (node (ref "IC34") (pin "7") (pinfunction "7_7") (pintype "passive"))
      (node (ref "SV67") (pin "3") (pinfunction "3_3") (pintype "passive"))
      (node (ref "SV67") (pin "4") (pinfunction "4_4") (pintype "passive"))
    )
    (net (code "542") (name "Net-(IC34-Pad8)") (class "Default")
      (node (ref "IC34") (pin "8") (pinfunction "8_8") (pintype "passive"))
      (node (ref "SV67") (pin "1") (pinfunction "1_1") (pintype "passive"))
      (node (ref "SV67") (pin "2") (pinfunction "2_2") (pintype "passive"))
    )
    (net (code "543") (name "Net-(IC34-Pad9)") (class "Default")
      (node (ref "IC34") (pin "9") (pinfunction "9_9") (pintype "passive"))
      (node (ref "SV68") (pin "1") (pinfunction "1_1") (pintype "passive"))
      (node (ref "SV68") (pin "2") (pinfunction "2_2") (pintype "passive"))
    )
    (net (code "544") (name "Net-(IC34-Pad10)") (class "Default")
      (node (ref "IC34") (pin "10") (pinfunction "10_10") (pintype "passive"))
      (node (ref "SV68") (pin "3") (pinfunction "3_3") (pintype "passive"))
      (node (ref "SV68") (pin "4") (pinfunction "4_4") (pintype "passive"))
    )
    (net (code "545") (name "Net-(IC34-Pad11)") (class "Default")
      (node (ref "IC34") (pin "11") (pinfunction "11_11") (pintype "passive"))
      (node (ref "SV68") (pin "5") (pinfunction "5_5") (pintype "passive"))
      (node (ref "SV68") (pin "6") (pinfunction "6_6") (pintype "passive"))
    )
    (net (code "546") (name "Net-(IC34-Pad12)") (class "Default")
      (node (ref "IC34") (pin "12") (pinfunction "12_12") (pintype "passive"))
      (node (ref "SV68") (pin "7") (pinfunction "7_7") (pintype "passive"))
      (node (ref "SV68") (pin "8") (pinfunction "8_8") (pintype "passive"))
    )
    (net (code "547") (name "Net-(IC34-Pad13)") (class "Default")
      (node (ref "IC34") (pin "13") (pinfunction "13_13") (pintype "passive"))
      (node (ref "SV68") (pin "10") (pinfunction "10_10") (pintype "passive"))
      (node (ref "SV68") (pin "9") (pinfunction "9_9") (pintype "passive"))
    )
    (net (code "548") (name "Net-(IC34-Pad14)") (class "Default")
      (node (ref "IC34") (pin "14") (pinfunction "14_14") (pintype "passive"))
      (node (ref "SV68") (pin "11") (pinfunction "11_11") (pintype "passive"))
      (node (ref "SV68") (pin "12") (pinfunction "12_12") (pintype "passive"))
    )
    (net (code "549") (name "Net-(IC34-Pad15)") (class "Default")
      (node (ref "IC34") (pin "15") (pinfunction "15_15") (pintype "passive"))
      (node (ref "SV68") (pin "13") (pinfunction "13_13") (pintype "passive"))
      (node (ref "SV68") (pin "14") (pinfunction "14_14") (pintype "passive"))
    )
    (net (code "550") (name "Net-(IC34-Pad16)") (class "Default")
      (node (ref "IC34") (pin "16") (pinfunction "16_16") (pintype "passive"))
      (node (ref "SV68") (pin "15") (pinfunction "15_15") (pintype "passive"))
      (node (ref "SV68") (pin "16") (pinfunction "16_16") (pintype "passive"))
    )
    (net (code "551") (name "Net-(IC35-Pad1)") (class "Default")
      (node (ref "IC35") (pin "1") (pinfunction "1_1") (pintype "passive"))
      (node (ref "SV69") (pin "15") (pinfunction "15_15") (pintype "passive"))
      (node (ref "SV69") (pin "16") (pinfunction "16_16") (pintype "passive"))
    )
    (net (code "552") (name "Net-(IC35-Pad2)") (class "Default")
      (node (ref "IC35") (pin "2") (pinfunction "2_2") (pintype "passive"))
      (node (ref "SV69") (pin "13") (pinfunction "13_13") (pintype "passive"))
      (node (ref "SV69") (pin "14") (pinfunction "14_14") (pintype "passive"))
    )
    (net (code "553") (name "Net-(IC35-Pad3)") (class "Default")
      (node (ref "IC35") (pin "3") (pinfunction "3_3") (pintype "passive"))
      (node (ref "SV69") (pin "11") (pinfunction "11_11") (pintype "passive"))
      (node (ref "SV69") (pin "12") (pinfunction "12_12") (pintype "passive"))
    )
    (net (code "554") (name "Net-(IC35-Pad4)") (class "Default")
      (node (ref "IC35") (pin "4") (pinfunction "4_4") (pintype "passive"))
      (node (ref "SV69") (pin "10") (pinfunction "10_10") (pintype "passive"))
      (node (ref "SV69") (pin "9") (pinfunction "9_9") (pintype "passive"))
    )
    (net (code "555") (name "Net-(IC35-Pad5)") (class "Default")
      (node (ref "IC35") (pin "5") (pinfunction "5_5") (pintype "passive"))
      (node (ref "SV69") (pin "7") (pinfunction "7_7") (pintype "passive"))
      (node (ref "SV69") (pin "8") (pinfunction "8_8") (pintype "passive"))
    )
    (net (code "556") (name "Net-(IC35-Pad6)") (class "Default")
      (node (ref "IC35") (pin "6") (pinfunction "6_6") (pintype "passive"))
      (node (ref "SV69") (pin "5") (pinfunction "5_5") (pintype "passive"))
      (node (ref "SV69") (pin "6") (pinfunction "6_6") (pintype "passive"))
    )
    (net (code "557") (name "Net-(IC35-Pad7)") (class "Default")
      (node (ref "IC35") (pin "7") (pinfunction "7_7") (pintype "passive"))
      (node (ref "SV69") (pin "3") (pinfunction "3_3") (pintype "passive"))
      (node (ref "SV69") (pin "4") (pinfunction "4_4") (pintype "passive"))
    )
    (net (code "558") (name "Net-(IC35-Pad8)") (class "Default")
      (node (ref "IC35") (pin "8") (pinfunction "8_8") (pintype "passive"))
      (node (ref "SV69") (pin "1") (pinfunction "1_1") (pintype "passive"))
      (node (ref "SV69") (pin "2") (pinfunction "2_2") (pintype "passive"))
    )
    (net (code "559") (name "Net-(IC35-Pad9)") (class "Default")
      (node (ref "IC35") (pin "9") (pinfunction "9_9") (pintype "passive"))
      (node (ref "SV70") (pin "1") (pinfunction "1_1") (pintype "passive"))
      (node (ref "SV70") (pin "2") (pinfunction "2_2") (pintype "passive"))
    )
    (net (code "560") (name "Net-(IC35-Pad10)") (class "Default")
      (node (ref "IC35") (pin "10") (pinfunction "10_10") (pintype "passive"))
      (node (ref "SV70") (pin "3") (pinfunction "3_3") (pintype "passive"))
      (node (ref "SV70") (pin "4") (pinfunction "4_4") (pintype "passive"))
    )
    (net (code "561") (name "Net-(IC35-Pad11)") (class "Default")
      (node (ref "IC35") (pin "11") (pinfunction "11_11") (pintype "passive"))
      (node (ref "SV70") (pin "5") (pinfunction "5_5") (pintype "passive"))
      (node (ref "SV70") (pin "6") (pinfunction "6_6") (pintype "passive"))
    )
    (net (code "562") (name "Net-(IC35-Pad12)") (class "Default")
      (node (ref "IC35") (pin "12") (pinfunction "12_12") (pintype "passive"))
      (node (ref "SV70") (pin "7") (pinfunction "7_7") (pintype "passive"))
      (node (ref "SV70") (pin "8") (pinfunction "8_8") (pintype "passive"))
    )
    (net (code "563") (name "Net-(IC35-Pad13)") (class "Default")
      (node (ref "IC35") (pin "13") (pinfunction "13_13") (pintype "passive"))
      (node (ref "SV70") (pin "10") (pinfunction "10_10") (pintype "passive"))
      (node (ref "SV70") (pin "9") (pinfunction "9_9") (pintype "passive"))
    )
    (net (code "564") (name "Net-(IC35-Pad14)") (class "Default")
      (node (ref "IC35") (pin "14") (pinfunction "14_14") (pintype "passive"))
      (node (ref "SV70") (pin "11") (pinfunction "11_11") (pintype "passive"))
      (node (ref "SV70") (pin "12") (pinfunction "12_12") (pintype "passive"))
    )
    (net (code "565") (name "Net-(IC35-Pad15)") (class "Default")
      (node (ref "IC35") (pin "15") (pinfunction "15_15") (pintype "passive"))
      (node (ref "SV70") (pin "13") (pinfunction "13_13") (pintype "passive"))
      (node (ref "SV70") (pin "14") (pinfunction "14_14") (pintype "passive"))
    )
    (net (code "566") (name "Net-(IC35-Pad16)") (class "Default")
      (node (ref "IC35") (pin "16") (pinfunction "16_16") (pintype "passive"))
      (node (ref "SV70") (pin "15") (pinfunction "15_15") (pintype "passive"))
      (node (ref "SV70") (pin "16") (pinfunction "16_16") (pintype "passive"))
    )
    (net (code "567") (name "Net-(IC36-Pad1)") (class "Default")
      (node (ref "IC36") (pin "1") (pinfunction "1_1") (pintype "passive"))
      (node (ref "SV71") (pin "15") (pinfunction "15_15") (pintype "passive"))
      (node (ref "SV71") (pin "16") (pinfunction "16_16") (pintype "passive"))
    )
    (net (code "568") (name "Net-(IC36-Pad2)") (class "Default")
      (node (ref "IC36") (pin "2") (pinfunction "2_2") (pintype "passive"))
      (node (ref "SV71") (pin "13") (pinfunction "13_13") (pintype "passive"))
      (node (ref "SV71") (pin "14") (pinfunction "14_14") (pintype "passive"))
    )
    (net (code "569") (name "Net-(IC36-Pad3)") (class "Default")
      (node (ref "IC36") (pin "3") (pinfunction "3_3") (pintype "passive"))
      (node (ref "SV71") (pin "11") (pinfunction "11_11") (pintype "passive"))
      (node (ref "SV71") (pin "12") (pinfunction "12_12") (pintype "passive"))
    )
    (net (code "570") (name "Net-(IC36-Pad4)") (class "Default")
      (node (ref "IC36") (pin "4") (pinfunction "4_4") (pintype "passive"))
      (node (ref "SV71") (pin "10") (pinfunction "10_10") (pintype "passive"))
      (node (ref "SV71") (pin "9") (pinfunction "9_9") (pintype "passive"))
    )
    (net (code "571") (name "Net-(IC36-Pad5)") (class "Default")
      (node (ref "IC36") (pin "5") (pinfunction "5_5") (pintype "passive"))
      (node (ref "SV71") (pin "7") (pinfunction "7_7") (pintype "passive"))
      (node (ref "SV71") (pin "8") (pinfunction "8_8") (pintype "passive"))
    )
    (net (code "572") (name "Net-(IC36-Pad6)") (class "Default")
      (node (ref "IC36") (pin "6") (pinfunction "6_6") (pintype "passive"))
      (node (ref "SV71") (pin "5") (pinfunction "5_5") (pintype "passive"))
      (node (ref "SV71") (pin "6") (pinfunction "6_6") (pintype "passive"))
    )
    (net (code "573") (name "Net-(IC36-Pad7)") (class "Default")
      (node (ref "IC36") (pin "7") (pinfunction "7_7") (pintype "passive"))
      (node (ref "SV71") (pin "3") (pinfunction "3_3") (pintype "passive"))
      (node (ref "SV71") (pin "4") (pinfunction "4_4") (pintype "passive"))
    )
    (net (code "574") (name "Net-(IC36-Pad8)") (class "Default")
      (node (ref "IC36") (pin "8") (pinfunction "8_8") (pintype "passive"))
      (node (ref "SV71") (pin "1") (pinfunction "1_1") (pintype "passive"))
      (node (ref "SV71") (pin "2") (pinfunction "2_2") (pintype "passive"))
    )
    (net (code "575") (name "Net-(IC36-Pad9)") (class "Default")
      (node (ref "IC36") (pin "9") (pinfunction "9_9") (pintype "passive"))
      (node (ref "SV72") (pin "1") (pinfunction "1_1") (pintype "passive"))
      (node (ref "SV72") (pin "2") (pinfunction "2_2") (pintype "passive"))
    )
    (net (code "576") (name "Net-(IC36-Pad10)") (class "Default")
      (node (ref "IC36") (pin "10") (pinfunction "10_10") (pintype "passive"))
      (node (ref "SV72") (pin "3") (pinfunction "3_3") (pintype "passive"))
      (node (ref "SV72") (pin "4") (pinfunction "4_4") (pintype "passive"))
    )
    (net (code "577") (name "Net-(IC36-Pad11)") (class "Default")
      (node (ref "IC36") (pin "11") (pinfunction "11_11") (pintype "passive"))
      (node (ref "SV72") (pin "5") (pinfunction "5_5") (pintype "passive"))
      (node (ref "SV72") (pin "6") (pinfunction "6_6") (pintype "passive"))
    )
    (net (code "578") (name "Net-(IC36-Pad12)") (class "Default")
      (node (ref "IC36") (pin "12") (pinfunction "12_12") (pintype "passive"))
      (node (ref "SV72") (pin "7") (pinfunction "7_7") (pintype "passive"))
      (node (ref "SV72") (pin "8") (pinfunction "8_8") (pintype "passive"))
    )
    (net (code "579") (name "Net-(IC36-Pad13)") (class "Default")
      (node (ref "IC36") (pin "13") (pinfunction "13_13") (pintype "passive"))
      (node (ref "SV72") (pin "10") (pinfunction "10_10") (pintype "passive"))
      (node (ref "SV72") (pin "9") (pinfunction "9_9") (pintype "passive"))
    )
    (net (code "580") (name "Net-(IC36-Pad14)") (class "Default")
      (node (ref "IC36") (pin "14") (pinfunction "14_14") (pintype "passive"))
      (node (ref "SV72") (pin "11") (pinfunction "11_11") (pintype "passive"))
      (node (ref "SV72") (pin "12") (pinfunction "12_12") (pintype "passive"))
    )
    (net (code "581") (name "Net-(IC36-Pad15)") (class "Default")
      (node (ref "IC36") (pin "15") (pinfunction "15_15") (pintype "passive"))
      (node (ref "SV72") (pin "13") (pinfunction "13_13") (pintype "passive"))
      (node (ref "SV72") (pin "14") (pinfunction "14_14") (pintype "passive"))
    )
    (net (code "582") (name "Net-(IC36-Pad16)") (class "Default")
      (node (ref "IC36") (pin "16") (pinfunction "16_16") (pintype "passive"))
      (node (ref "SV72") (pin "15") (pinfunction "15_15") (pintype "passive"))
      (node (ref "SV72") (pin "16") (pinfunction "16_16") (pintype "passive"))
    )
    (net (code "583") (name "Net-(IC37-Pad1)") (class "Default")
      (node (ref "IC37") (pin "1") (pinfunction "1_1") (pintype "passive"))
      (node (ref "SV73") (pin "15") (pinfunction "15_15") (pintype "passive"))
      (node (ref "SV73") (pin "16") (pinfunction "16_16") (pintype "passive"))
    )
    (net (code "584") (name "Net-(IC37-Pad2)") (class "Default")
      (node (ref "IC37") (pin "2") (pinfunction "2_2") (pintype "passive"))
      (node (ref "SV73") (pin "13") (pinfunction "13_13") (pintype "passive"))
      (node (ref "SV73") (pin "14") (pinfunction "14_14") (pintype "passive"))
    )
    (net (code "585") (name "Net-(IC37-Pad3)") (class "Default")
      (node (ref "IC37") (pin "3") (pinfunction "3_3") (pintype "passive"))
      (node (ref "SV73") (pin "11") (pinfunction "11_11") (pintype "passive"))
      (node (ref "SV73") (pin "12") (pinfunction "12_12") (pintype "passive"))
    )
    (net (code "586") (name "Net-(IC37-Pad4)") (class "Default")
      (node (ref "IC37") (pin "4") (pinfunction "4_4") (pintype "passive"))
      (node (ref "SV73") (pin "10") (pinfunction "10_10") (pintype "passive"))
      (node (ref "SV73") (pin "9") (pinfunction "9_9") (pintype "passive"))
    )
    (net (code "587") (name "Net-(IC37-Pad5)") (class "Default")
      (node (ref "IC37") (pin "5") (pinfunction "5_5") (pintype "passive"))
      (node (ref "SV73") (pin "7") (pinfunction "7_7") (pintype "passive"))
      (node (ref "SV73") (pin "8") (pinfunction "8_8") (pintype "passive"))
    )
    (net (code "588") (name "Net-(IC37-Pad6)") (class "Default")
      (node (ref "IC37") (pin "6") (pinfunction "6_6") (pintype "passive"))
      (node (ref "SV73") (pin "5") (pinfunction "5_5") (pintype "passive"))
      (node (ref "SV73") (pin "6") (pinfunction "6_6") (pintype "passive"))
    )
    (net (code "589") (name "Net-(IC37-Pad7)") (class "Default")
      (node (ref "IC37") (pin "7") (pinfunction "7_7") (pintype "passive"))
      (node (ref "SV73") (pin "3") (pinfunction "3_3") (pintype "passive"))
      (node (ref "SV73") (pin "4") (pinfunction "4_4") (pintype "passive"))
    )
    (net (code "590") (name "Net-(IC37-Pad8)") (class "Default")
      (node (ref "IC37") (pin "8") (pinfunction "8_8") (pintype "passive"))
      (node (ref "SV73") (pin "1") (pinfunction "1_1") (pintype "passive"))
      (node (ref "SV73") (pin "2") (pinfunction "2_2") (pintype "passive"))
    )
    (net (code "591") (name "Net-(IC37-Pad9)") (class "Default")
      (node (ref "IC37") (pin "9") (pinfunction "9_9") (pintype "passive"))
      (node (ref "SV74") (pin "1") (pinfunction "1_1") (pintype "passive"))
      (node (ref "SV74") (pin "2") (pinfunction "2_2") (pintype "passive"))
    )
    (net (code "592") (name "Net-(IC37-Pad10)") (class "Default")
      (node (ref "IC37") (pin "10") (pinfunction "10_10") (pintype "passive"))
      (node (ref "SV74") (pin "3") (pinfunction "3_3") (pintype "passive"))
      (node (ref "SV74") (pin "4") (pinfunction "4_4") (pintype "passive"))
    )
    (net (code "593") (name "Net-(IC37-Pad11)") (class "Default")
      (node (ref "IC37") (pin "11") (pinfunction "11_11") (pintype "passive"))
      (node (ref "SV74") (pin "5") (pinfunction "5_5") (pintype "passive"))
      (node (ref "SV74") (pin "6") (pinfunction "6_6") (pintype "passive"))
    )
    (net (code "594") (name "Net-(IC37-Pad12)") (class "Default")
      (node (ref "IC37") (pin "12") (pinfunction "12_12") (pintype "passive"))
      (node (ref "SV74") (pin "7") (pinfunction "7_7") (pintype "passive"))
      (node (ref "SV74") (pin "8") (pinfunction "8_8") (pintype "passive"))
    )
    (net (code "595") (name "Net-(IC37-Pad13)") (class "Default")
      (node (ref "IC37") (pin "13") (pinfunction "13_13") (pintype "passive"))
      (node (ref "SV74") (pin "10") (pinfunction "10_10") (pintype "passive"))
      (node (ref "SV74") (pin "9") (pinfunction "9_9") (pintype "passive"))
    )
    (net (code "596") (name "Net-(IC37-Pad14)") (class "Default")
      (node (ref "IC37") (pin "14") (pinfunction "14_14") (pintype "passive"))
      (node (ref "SV74") (pin "11") (pinfunction "11_11") (pintype "passive"))
      (node (ref "SV74") (pin "12") (pinfunction "12_12") (pintype "passive"))
    )
    (net (code "597") (name "Net-(IC37-Pad15)") (class "Default")
      (node (ref "IC37") (pin "15") (pinfunction "15_15") (pintype "passive"))
      (node (ref "SV74") (pin "13") (pinfunction "13_13") (pintype "passive"))
      (node (ref "SV74") (pin "14") (pinfunction "14_14") (pintype "passive"))
    )
    (net (code "598") (name "Net-(IC37-Pad16)") (class "Default")
      (node (ref "IC37") (pin "16") (pinfunction "16_16") (pintype "passive"))
      (node (ref "SV74") (pin "15") (pinfunction "15_15") (pintype "passive"))
      (node (ref "SV74") (pin "16") (pinfunction "16_16") (pintype "passive"))
    )
    (net (code "599") (name "Net-(IC38-Pad1)") (class "Default")
      (node (ref "IC38") (pin "1") (pinfunction "1_1") (pintype "passive"))
      (node (ref "SV75") (pin "15") (pinfunction "15_15") (pintype "passive"))
      (node (ref "SV75") (pin "16") (pinfunction "16_16") (pintype "passive"))
    )
    (net (code "600") (name "Net-(IC38-Pad2)") (class "Default")
      (node (ref "IC38") (pin "2") (pinfunction "2_2") (pintype "passive"))
      (node (ref "SV75") (pin "13") (pinfunction "13_13") (pintype "passive"))
      (node (ref "SV75") (pin "14") (pinfunction "14_14") (pintype "passive"))
    )
    (net (code "601") (name "Net-(IC38-Pad3)") (class "Default")
      (node (ref "IC38") (pin "3") (pinfunction "3_3") (pintype "passive"))
      (node (ref "SV75") (pin "11") (pinfunction "11_11") (pintype "passive"))
      (node (ref "SV75") (pin "12") (pinfunction "12_12") (pintype "passive"))
    )
    (net (code "602") (name "Net-(IC38-Pad4)") (class "Default")
      (node (ref "IC38") (pin "4") (pinfunction "4_4") (pintype "passive"))
      (node (ref "SV75") (pin "10") (pinfunction "10_10") (pintype "passive"))
      (node (ref "SV75") (pin "9") (pinfunction "9_9") (pintype "passive"))
    )
    (net (code "603") (name "Net-(IC38-Pad5)") (class "Default")
      (node (ref "IC38") (pin "5") (pinfunction "5_5") (pintype "passive"))
      (node (ref "SV75") (pin "7") (pinfunction "7_7") (pintype "passive"))
      (node (ref "SV75") (pin "8") (pinfunction "8_8") (pintype "passive"))
    )
    (net (code "604") (name "Net-(IC38-Pad6)") (class "Default")
      (node (ref "IC38") (pin "6") (pinfunction "6_6") (pintype "passive"))
      (node (ref "SV75") (pin "5") (pinfunction "5_5") (pintype "passive"))
      (node (ref "SV75") (pin "6") (pinfunction "6_6") (pintype "passive"))
    )
    (net (code "605") (name "Net-(IC38-Pad7)") (class "Default")
      (node (ref "IC38") (pin "7") (pinfunction "7_7") (pintype "passive"))
      (node (ref "SV75") (pin "3") (pinfunction "3_3") (pintype "passive"))
      (node (ref "SV75") (pin "4") (pinfunction "4_4") (pintype "passive"))
    )
    (net (code "606") (name "Net-(IC38-Pad8)") (class "Default")
      (node (ref "IC38") (pin "8") (pinfunction "8_8") (pintype "passive"))
      (node (ref "SV75") (pin "1") (pinfunction "1_1") (pintype "passive"))
      (node (ref "SV75") (pin "2") (pinfunction "2_2") (pintype "passive"))
    )
    (net (code "607") (name "Net-(IC38-Pad9)") (class "Default")
      (node (ref "IC38") (pin "9") (pinfunction "9_9") (pintype "passive"))
      (node (ref "SV76") (pin "1") (pinfunction "1_1") (pintype "passive"))
      (node (ref "SV76") (pin "2") (pinfunction "2_2") (pintype "passive"))
    )
    (net (code "608") (name "Net-(IC38-Pad10)") (class "Default")
      (node (ref "IC38") (pin "10") (pinfunction "10_10") (pintype "passive"))
      (node (ref "SV76") (pin "3") (pinfunction "3_3") (pintype "passive"))
      (node (ref "SV76") (pin "4") (pinfunction "4_4") (pintype "passive"))
    )
    (net (code "609") (name "Net-(IC38-Pad11)") (class "Default")
      (node (ref "IC38") (pin "11") (pinfunction "11_11") (pintype "passive"))
      (node (ref "SV76") (pin "5") (pinfunction "5_5") (pintype "passive"))
      (node (ref "SV76") (pin "6") (pinfunction "6_6") (pintype "passive"))
    )
    (net (code "610") (name "Net-(IC38-Pad12)") (class "Default")
      (node (ref "IC38") (pin "12") (pinfunction "12_12") (pintype "passive"))
      (node (ref "SV76") (pin "7") (pinfunction "7_7") (pintype "passive"))
      (node (ref "SV76") (pin "8") (pinfunction "8_8") (pintype "passive"))
    )
    (net (code "611") (name "Net-(IC38-Pad13)") (class "Default")
      (node (ref "IC38") (pin "13") (pinfunction "13_13") (pintype "passive"))
      (node (ref "SV76") (pin "10") (pinfunction "10_10") (pintype "passive"))
      (node (ref "SV76") (pin "9") (pinfunction "9_9") (pintype "passive"))
    )
    (net (code "612") (name "Net-(IC38-Pad14)") (class "Default")
      (node (ref "IC38") (pin "14") (pinfunction "14_14") (pintype "passive"))
      (node (ref "SV76") (pin "11") (pinfunction "11_11") (pintype "passive"))
      (node (ref "SV76") (pin "12") (pinfunction "12_12") (pintype "passive"))
    )
    (net (code "613") (name "Net-(IC38-Pad15)") (class "Default")
      (node (ref "IC38") (pin "15") (pinfunction "15_15") (pintype "passive"))
      (node (ref "SV76") (pin "13") (pinfunction "13_13") (pintype "passive"))
      (node (ref "SV76") (pin "14") (pinfunction "14_14") (pintype "passive"))
    )
    (net (code "614") (name "Net-(IC38-Pad16)") (class "Default")
      (node (ref "IC38") (pin "16") (pinfunction "16_16") (pintype "passive"))
      (node (ref "SV76") (pin "15") (pinfunction "15_15") (pintype "passive"))
      (node (ref "SV76") (pin "16") (pinfunction "16_16") (pintype "passive"))
    )
    (net (code "615") (name "Net-(IC39-Pad1)") (class "Default")
      (node (ref "IC39") (pin "1") (pinfunction "1_1") (pintype "passive"))
      (node (ref "SV77") (pin "15") (pinfunction "15_15") (pintype "passive"))
      (node (ref "SV77") (pin "16") (pinfunction "16_16") (pintype "passive"))
    )
    (net (code "616") (name "Net-(IC39-Pad2)") (class "Default")
      (node (ref "IC39") (pin "2") (pinfunction "2_2") (pintype "passive"))
      (node (ref "SV77") (pin "13") (pinfunction "13_13") (pintype "passive"))
      (node (ref "SV77") (pin "14") (pinfunction "14_14") (pintype "passive"))
    )
    (net (code "617") (name "Net-(IC39-Pad3)") (class "Default")
      (node (ref "IC39") (pin "3") (pinfunction "3_3") (pintype "passive"))
      (node (ref "SV77") (pin "11") (pinfunction "11_11") (pintype "passive"))
      (node (ref "SV77") (pin "12") (pinfunction "12_12") (pintype "passive"))
    )
    (net (code "618") (name "Net-(IC39-Pad4)") (class "Default")
      (node (ref "IC39") (pin "4") (pinfunction "4_4") (pintype "passive"))
      (node (ref "SV77") (pin "10") (pinfunction "10_10") (pintype "passive"))
      (node (ref "SV77") (pin "9") (pinfunction "9_9") (pintype "passive"))
    )
    (net (code "619") (name "Net-(IC39-Pad5)") (class "Default")
      (node (ref "IC39") (pin "5") (pinfunction "5_5") (pintype "passive"))
      (node (ref "SV77") (pin "7") (pinfunction "7_7") (pintype "passive"))
      (node (ref "SV77") (pin "8") (pinfunction "8_8") (pintype "passive"))
    )
    (net (code "620") (name "Net-(IC39-Pad6)") (class "Default")
      (node (ref "IC39") (pin "6") (pinfunction "6_6") (pintype "passive"))
      (node (ref "SV77") (pin "5") (pinfunction "5_5") (pintype "passive"))
      (node (ref "SV77") (pin "6") (pinfunction "6_6") (pintype "passive"))
    )
    (net (code "621") (name "Net-(IC39-Pad7)") (class "Default")
      (node (ref "IC39") (pin "7") (pinfunction "7_7") (pintype "passive"))
      (node (ref "SV77") (pin "3") (pinfunction "3_3") (pintype "passive"))
      (node (ref "SV77") (pin "4") (pinfunction "4_4") (pintype "passive"))
    )
    (net (code "622") (name "Net-(IC39-Pad8)") (class "Default")
      (node (ref "IC39") (pin "8") (pinfunction "8_8") (pintype "passive"))
      (node (ref "SV77") (pin "1") (pinfunction "1_1") (pintype "passive"))
      (node (ref "SV77") (pin "2") (pinfunction "2_2") (pintype "passive"))
    )
    (net (code "623") (name "Net-(IC39-Pad9)") (class "Default")
      (node (ref "IC39") (pin "9") (pinfunction "9_9") (pintype "passive"))
      (node (ref "SV78") (pin "1") (pinfunction "1_1") (pintype "passive"))
      (node (ref "SV78") (pin "2") (pinfunction "2_2") (pintype "passive"))
    )
    (net (code "624") (name "Net-(IC39-Pad10)") (class "Default")
      (node (ref "IC39") (pin "10") (pinfunction "10_10") (pintype "passive"))
      (node (ref "SV78") (pin "3") (pinfunction "3_3") (pintype "passive"))
      (node (ref "SV78") (pin "4") (pinfunction "4_4") (pintype "passive"))
    )
    (net (code "625") (name "Net-(IC39-Pad11)") (class "Default")
      (node (ref "IC39") (pin "11") (pinfunction "11_11") (pintype "passive"))
      (node (ref "SV78") (pin "5") (pinfunction "5_5") (pintype "passive"))
      (node (ref "SV78") (pin "6") (pinfunction "6_6") (pintype "passive"))
    )
    (net (code "626") (name "Net-(IC39-Pad12)") (class "Default")
      (node (ref "IC39") (pin "12") (pinfunction "12_12") (pintype "passive"))
      (node (ref "SV78") (pin "7") (pinfunction "7_7") (pintype "passive"))
      (node (ref "SV78") (pin "8") (pinfunction "8_8") (pintype "passive"))
    )
    (net (code "627") (name "Net-(IC39-Pad13)") (class "Default")
      (node (ref "IC39") (pin "13") (pinfunction "13_13") (pintype "passive"))
      (node (ref "SV78") (pin "10") (pinfunction "10_10") (pintype "passive"))
      (node (ref "SV78") (pin "9") (pinfunction "9_9") (pintype "passive"))
    )
    (net (code "628") (name "Net-(IC39-Pad14)") (class "Default")
      (node (ref "IC39") (pin "14") (pinfunction "14_14") (pintype "passive"))
      (node (ref "SV78") (pin "11") (pinfunction "11_11") (pintype "passive"))
      (node (ref "SV78") (pin "12") (pinfunction "12_12") (pintype "passive"))
    )
    (net (code "629") (name "Net-(IC39-Pad15)") (class "Default")
      (node (ref "IC39") (pin "15") (pinfunction "15_15") (pintype "passive"))
      (node (ref "SV78") (pin "13") (pinfunction "13_13") (pintype "passive"))
      (node (ref "SV78") (pin "14") (pinfunction "14_14") (pintype "passive"))
    )
    (net (code "630") (name "Net-(IC39-Pad16)") (class "Default")
      (node (ref "IC39") (pin "16") (pinfunction "16_16") (pintype "passive"))
      (node (ref "SV78") (pin "15") (pinfunction "15_15") (pintype "passive"))
      (node (ref "SV78") (pin "16") (pinfunction "16_16") (pintype "passive"))
    )
    (net (code "631") (name "Net-(IC40-Pad1)") (class "Default")
      (node (ref "IC40") (pin "1") (pinfunction "1_1") (pintype "passive"))
      (node (ref "SV79") (pin "15") (pinfunction "15_15") (pintype "passive"))
      (node (ref "SV79") (pin "16") (pinfunction "16_16") (pintype "passive"))
    )
    (net (code "632") (name "Net-(IC40-Pad2)") (class "Default")
      (node (ref "IC40") (pin "2") (pinfunction "2_2") (pintype "passive"))
      (node (ref "SV79") (pin "13") (pinfunction "13_13") (pintype "passive"))
      (node (ref "SV79") (pin "14") (pinfunction "14_14") (pintype "passive"))
    )
    (net (code "633") (name "Net-(IC40-Pad3)") (class "Default")
      (node (ref "IC40") (pin "3") (pinfunction "3_3") (pintype "passive"))
      (node (ref "SV79") (pin "11") (pinfunction "11_11") (pintype "passive"))
      (node (ref "SV79") (pin "12") (pinfunction "12_12") (pintype "passive"))
    )
    (net (code "634") (name "Net-(IC40-Pad4)") (class "Default")
      (node (ref "IC40") (pin "4") (pinfunction "4_4") (pintype "passive"))
      (node (ref "SV79") (pin "10") (pinfunction "10_10") (pintype "passive"))
      (node (ref "SV79") (pin "9") (pinfunction "9_9") (pintype "passive"))
    )
    (net (code "635") (name "Net-(IC40-Pad5)") (class "Default")
      (node (ref "IC40") (pin "5") (pinfunction "5_5") (pintype "passive"))
      (node (ref "SV79") (pin "7") (pinfunction "7_7") (pintype "passive"))
      (node (ref "SV79") (pin "8") (pinfunction "8_8") (pintype "passive"))
    )
    (net (code "636") (name "Net-(IC40-Pad6)") (class "Default")
      (node (ref "IC40") (pin "6") (pinfunction "6_6") (pintype "passive"))
      (node (ref "SV79") (pin "5") (pinfunction "5_5") (pintype "passive"))
      (node (ref "SV79") (pin "6") (pinfunction "6_6") (pintype "passive"))
    )
    (net (code "637") (name "Net-(IC40-Pad7)") (class "Default")
      (node (ref "IC40") (pin "7") (pinfunction "7_7") (pintype "passive"))
      (node (ref "SV79") (pin "3") (pinfunction "3_3") (pintype "passive"))
      (node (ref "SV79") (pin "4") (pinfunction "4_4") (pintype "passive"))
    )
    (net (code "638") (name "Net-(IC40-Pad8)") (class "Default")
      (node (ref "IC40") (pin "8") (pinfunction "8_8") (pintype "passive"))
      (node (ref "SV79") (pin "1") (pinfunction "1_1") (pintype "passive"))
      (node (ref "SV79") (pin "2") (pinfunction "2_2") (pintype "passive"))
    )
    (net (code "639") (name "Net-(IC40-Pad9)") (class "Default")
      (node (ref "IC40") (pin "9") (pinfunction "9_9") (pintype "passive"))
      (node (ref "SV80") (pin "1") (pinfunction "1_1") (pintype "passive"))
      (node (ref "SV80") (pin "2") (pinfunction "2_2") (pintype "passive"))
    )
    (net (code "640") (name "Net-(IC40-Pad10)") (class "Default")
      (node (ref "IC40") (pin "10") (pinfunction "10_10") (pintype "passive"))
      (node (ref "SV80") (pin "3") (pinfunction "3_3") (pintype "passive"))
      (node (ref "SV80") (pin "4") (pinfunction "4_4") (pintype "passive"))
    )
    (net (code "641") (name "Net-(IC40-Pad11)") (class "Default")
      (node (ref "IC40") (pin "11") (pinfunction "11_11") (pintype "passive"))
      (node (ref "SV80") (pin "5") (pinfunction "5_5") (pintype "passive"))
      (node (ref "SV80") (pin "6") (pinfunction "6_6") (pintype "passive"))
    )
    (net (code "642") (name "Net-(IC40-Pad12)") (class "Default")
      (node (ref "IC40") (pin "12") (pinfunction "12_12") (pintype "passive"))
      (node (ref "SV80") (pin "7") (pinfunction "7_7") (pintype "passive"))
      (node (ref "SV80") (pin "8") (pinfunction "8_8") (pintype "passive"))
    )
    (net (code "643") (name "Net-(IC40-Pad13)") (class "Default")
      (node (ref "IC40") (pin "13") (pinfunction "13_13") (pintype "passive"))
      (node (ref "SV80") (pin "10") (pinfunction "10_10") (pintype "passive"))
      (node (ref "SV80") (pin "9") (pinfunction "9_9") (pintype "passive"))
    )
    (net (code "644") (name "Net-(IC40-Pad14)") (class "Default")
      (node (ref "IC40") (pin "14") (pinfunction "14_14") (pintype "passive"))
      (node (ref "SV80") (pin "11") (pinfunction "11_11") (pintype "passive"))
      (node (ref "SV80") (pin "12") (pinfunction "12_12") (pintype "passive"))
    )
    (net (code "645") (name "Net-(IC40-Pad15)") (class "Default")
      (node (ref "IC40") (pin "15") (pinfunction "15_15") (pintype "passive"))
      (node (ref "SV80") (pin "13") (pinfunction "13_13") (pintype "passive"))
      (node (ref "SV80") (pin "14") (pinfunction "14_14") (pintype "passive"))
    )
    (net (code "646") (name "Net-(IC40-Pad16)") (class "Default")
      (node (ref "IC40") (pin "16") (pinfunction "16_16") (pintype "passive"))
      (node (ref "SV80") (pin "15") (pinfunction "15_15") (pintype "passive"))
      (node (ref "SV80") (pin "16") (pinfunction "16_16") (pintype "passive"))
    )
    (net (code "647") (name "Net-(IC41-Pad1)") (class "Default")
      (node (ref "IC41") (pin "1") (pinfunction "1_1") (pintype "passive"))
      (node (ref "SV81") (pin "15") (pinfunction "15_15") (pintype "passive"))
      (node (ref "SV81") (pin "16") (pinfunction "16_16") (pintype "passive"))
    )
    (net (code "648") (name "Net-(IC41-Pad2)") (class "Default")
      (node (ref "IC41") (pin "2") (pinfunction "2_2") (pintype "passive"))
      (node (ref "SV81") (pin "13") (pinfunction "13_13") (pintype "passive"))
      (node (ref "SV81") (pin "14") (pinfunction "14_14") (pintype "passive"))
    )
    (net (code "649") (name "Net-(IC41-Pad3)") (class "Default")
      (node (ref "IC41") (pin "3") (pinfunction "3_3") (pintype "passive"))
      (node (ref "SV81") (pin "11") (pinfunction "11_11") (pintype "passive"))
      (node (ref "SV81") (pin "12") (pinfunction "12_12") (pintype "passive"))
    )
    (net (code "650") (name "Net-(IC41-Pad4)") (class "Default")
      (node (ref "IC41") (pin "4") (pinfunction "4_4") (pintype "passive"))
      (node (ref "SV81") (pin "10") (pinfunction "10_10") (pintype "passive"))
      (node (ref "SV81") (pin "9") (pinfunction "9_9") (pintype "passive"))
    )
    (net (code "651") (name "Net-(IC41-Pad5)") (class "Default")
      (node (ref "IC41") (pin "5") (pinfunction "5_5") (pintype "passive"))
      (node (ref "SV81") (pin "7") (pinfunction "7_7") (pintype "passive"))
      (node (ref "SV81") (pin "8") (pinfunction "8_8") (pintype "passive"))
    )
    (net (code "652") (name "Net-(IC41-Pad6)") (class "Default")
      (node (ref "IC41") (pin "6") (pinfunction "6_6") (pintype "passive"))
      (node (ref "SV81") (pin "5") (pinfunction "5_5") (pintype "passive"))
      (node (ref "SV81") (pin "6") (pinfunction "6_6") (pintype "passive"))
    )
    (net (code "653") (name "Net-(IC41-Pad7)") (class "Default")
      (node (ref "IC41") (pin "7") (pinfunction "7_7") (pintype "passive"))
      (node (ref "SV81") (pin "3") (pinfunction "3_3") (pintype "passive"))
      (node (ref "SV81") (pin "4") (pinfunction "4_4") (pintype "passive"))
    )
    (net (code "654") (name "Net-(IC41-Pad8)") (class "Default")
      (node (ref "IC41") (pin "8") (pinfunction "8_8") (pintype "passive"))
      (node (ref "SV81") (pin "1") (pinfunction "1_1") (pintype "passive"))
      (node (ref "SV81") (pin "2") (pinfunction "2_2") (pintype "passive"))
    )
    (net (code "655") (name "Net-(IC41-Pad9)") (class "Default")
      (node (ref "IC41") (pin "9") (pinfunction "9_9") (pintype "passive"))
      (node (ref "SV82") (pin "1") (pinfunction "1_1") (pintype "passive"))
      (node (ref "SV82") (pin "2") (pinfunction "2_2") (pintype "passive"))
    )
    (net (code "656") (name "Net-(IC41-Pad10)") (class "Default")
      (node (ref "IC41") (pin "10") (pinfunction "10_10") (pintype "passive"))
      (node (ref "SV82") (pin "3") (pinfunction "3_3") (pintype "passive"))
      (node (ref "SV82") (pin "4") (pinfunction "4_4") (pintype "passive"))
    )
    (net (code "657") (name "Net-(IC41-Pad11)") (class "Default")
      (node (ref "IC41") (pin "11") (pinfunction "11_11") (pintype "passive"))
      (node (ref "SV82") (pin "5") (pinfunction "5_5") (pintype "passive"))
      (node (ref "SV82") (pin "6") (pinfunction "6_6") (pintype "passive"))
    )
    (net (code "658") (name "Net-(IC41-Pad12)") (class "Default")
      (node (ref "IC41") (pin "12") (pinfunction "12_12") (pintype "passive"))
      (node (ref "SV82") (pin "7") (pinfunction "7_7") (pintype "passive"))
      (node (ref "SV82") (pin "8") (pinfunction "8_8") (pintype "passive"))
    )
    (net (code "659") (name "Net-(IC41-Pad13)") (class "Default")
      (node (ref "IC41") (pin "13") (pinfunction "13_13") (pintype "passive"))
      (node (ref "SV82") (pin "10") (pinfunction "10_10") (pintype "passive"))
      (node (ref "SV82") (pin "9") (pinfunction "9_9") (pintype "passive"))
    )
    (net (code "660") (name "Net-(IC41-Pad14)") (class "Default")
      (node (ref "IC41") (pin "14") (pinfunction "14_14") (pintype "passive"))
      (node (ref "SV82") (pin "11") (pinfunction "11_11") (pintype "passive"))
      (node (ref "SV82") (pin "12") (pinfunction "12_12") (pintype "passive"))
    )
    (net (code "661") (name "Net-(IC41-Pad15)") (class "Default")
      (node (ref "IC41") (pin "15") (pinfunction "15_15") (pintype "passive"))
      (node (ref "SV82") (pin "13") (pinfunction "13_13") (pintype "passive"))
      (node (ref "SV82") (pin "14") (pinfunction "14_14") (pintype "passive"))
    )
    (net (code "662") (name "Net-(IC41-Pad16)") (class "Default")
      (node (ref "IC41") (pin "16") (pinfunction "16_16") (pintype "passive"))
      (node (ref "SV82") (pin "15") (pinfunction "15_15") (pintype "passive"))
      (node (ref "SV82") (pin "16") (pinfunction "16_16") (pintype "passive"))
    )
    (net (code "663") (name "Net-(IC42-Pad1)") (class "Default")
      (node (ref "IC42") (pin "1") (pinfunction "1_1") (pintype "passive"))
      (node (ref "SV83") (pin "15") (pinfunction "15_15") (pintype "passive"))
      (node (ref "SV83") (pin "16") (pinfunction "16_16") (pintype "passive"))
    )
    (net (code "664") (name "Net-(IC42-Pad2)") (class "Default")
      (node (ref "IC42") (pin "2") (pinfunction "2_2") (pintype "passive"))
      (node (ref "SV83") (pin "13") (pinfunction "13_13") (pintype "passive"))
      (node (ref "SV83") (pin "14") (pinfunction "14_14") (pintype "passive"))
    )
    (net (code "665") (name "Net-(IC42-Pad3)") (class "Default")
      (node (ref "IC42") (pin "3") (pinfunction "3_3") (pintype "passive"))
      (node (ref "SV83") (pin "11") (pinfunction "11_11") (pintype "passive"))
      (node (ref "SV83") (pin "12") (pinfunction "12_12") (pintype "passive"))
    )
    (net (code "666") (name "Net-(IC42-Pad4)") (class "Default")
      (node (ref "IC42") (pin "4") (pinfunction "4_4") (pintype "passive"))
      (node (ref "SV83") (pin "10") (pinfunction "10_10") (pintype "passive"))
      (node (ref "SV83") (pin "9") (pinfunction "9_9") (pintype "passive"))
    )
    (net (code "667") (name "Net-(IC42-Pad5)") (class "Default")
      (node (ref "IC42") (pin "5") (pinfunction "5_5") (pintype "passive"))
      (node (ref "SV83") (pin "7") (pinfunction "7_7") (pintype "passive"))
      (node (ref "SV83") (pin "8") (pinfunction "8_8") (pintype "passive"))
    )
    (net (code "668") (name "Net-(IC42-Pad6)") (class "Default")
      (node (ref "IC42") (pin "6") (pinfunction "6_6") (pintype "passive"))
      (node (ref "SV83") (pin "5") (pinfunction "5_5") (pintype "passive"))
      (node (ref "SV83") (pin "6") (pinfunction "6_6") (pintype "passive"))
    )
    (net (code "669") (name "Net-(IC42-Pad7)") (class "Default")
      (node (ref "IC42") (pin "7") (pinfunction "7_7") (pintype "passive"))
      (node (ref "SV83") (pin "3") (pinfunction "3_3") (pintype "passive"))
      (node (ref "SV83") (pin "4") (pinfunction "4_4") (pintype "passive"))
    )
    (net (code "670") (name "Net-(IC42-Pad8)") (class "Default")
      (node (ref "IC42") (pin "8") (pinfunction "8_8") (pintype "passive"))
      (node (ref "SV83") (pin "1") (pinfunction "1_1") (pintype "passive"))
      (node (ref "SV83") (pin "2") (pinfunction "2_2") (pintype "passive"))
    )
    (net (code "671") (name "Net-(IC42-Pad9)") (class "Default")
      (node (ref "IC42") (pin "9") (pinfunction "9_9") (pintype "passive"))
      (node (ref "SV84") (pin "1") (pinfunction "1_1") (pintype "passive"))
      (node (ref "SV84") (pin "2") (pinfunction "2_2") (pintype "passive"))
    )
    (net (code "672") (name "Net-(IC42-Pad10)") (class "Default")
      (node (ref "IC42") (pin "10") (pinfunction "10_10") (pintype "passive"))
      (node (ref "SV84") (pin "3") (pinfunction "3_3") (pintype "passive"))
      (node (ref "SV84") (pin "4") (pinfunction "4_4") (pintype "passive"))
    )
    (net (code "673") (name "Net-(IC42-Pad11)") (class "Default")
      (node (ref "IC42") (pin "11") (pinfunction "11_11") (pintype "passive"))
      (node (ref "SV84") (pin "5") (pinfunction "5_5") (pintype "passive"))
      (node (ref "SV84") (pin "6") (pinfunction "6_6") (pintype "passive"))
    )
    (net (code "674") (name "Net-(IC42-Pad12)") (class "Default")
      (node (ref "IC42") (pin "12") (pinfunction "12_12") (pintype "passive"))
      (node (ref "SV84") (pin "7") (pinfunction "7_7") (pintype "passive"))
      (node (ref "SV84") (pin "8") (pinfunction "8_8") (pintype "passive"))
    )
    (net (code "675") (name "Net-(IC42-Pad13)") (class "Default")
      (node (ref "IC42") (pin "13") (pinfunction "13_13") (pintype "passive"))
      (node (ref "SV84") (pin "10") (pinfunction "10_10") (pintype "passive"))
      (node (ref "SV84") (pin "9") (pinfunction "9_9") (pintype "passive"))
    )
    (net (code "676") (name "Net-(IC42-Pad14)") (class "Default")
      (node (ref "IC42") (pin "14") (pinfunction "14_14") (pintype "passive"))
      (node (ref "SV84") (pin "11") (pinfunction "11_11") (pintype "passive"))
      (node (ref "SV84") (pin "12") (pinfunction "12_12") (pintype "passive"))
    )
    (net (code "677") (name "Net-(IC42-Pad15)") (class "Default")
      (node (ref "IC42") (pin "15") (pinfunction "15_15") (pintype "passive"))
      (node (ref "SV84") (pin "13") (pinfunction "13_13") (pintype "passive"))
      (node (ref "SV84") (pin "14") (pinfunction "14_14") (pintype "passive"))
    )
    (net (code "678") (name "Net-(IC42-Pad16)") (class "Default")
      (node (ref "IC42") (pin "16") (pinfunction "16_16") (pintype "passive"))
      (node (ref "SV84") (pin "15") (pinfunction "15_15") (pintype "passive"))
      (node (ref "SV84") (pin "16") (pinfunction "16_16") (pintype "passive"))
    )
    (net (code "679") (name "Net-(IC43-Pad1)") (class "Default")
      (node (ref "IC43") (pin "1") (pinfunction "1_1") (pintype "passive"))
      (node (ref "SV85") (pin "15") (pinfunction "15_15") (pintype "passive"))
      (node (ref "SV85") (pin "16") (pinfunction "16_16") (pintype "passive"))
    )
    (net (code "680") (name "Net-(IC43-Pad2)") (class "Default")
      (node (ref "IC43") (pin "2") (pinfunction "2_2") (pintype "passive"))
      (node (ref "SV85") (pin "13") (pinfunction "13_13") (pintype "passive"))
      (node (ref "SV85") (pin "14") (pinfunction "14_14") (pintype "passive"))
    )
    (net (code "681") (name "Net-(IC43-Pad3)") (class "Default")
      (node (ref "IC43") (pin "3") (pinfunction "3_3") (pintype "passive"))
      (node (ref "SV85") (pin "11") (pinfunction "11_11") (pintype "passive"))
      (node (ref "SV85") (pin "12") (pinfunction "12_12") (pintype "passive"))
    )
    (net (code "682") (name "Net-(IC43-Pad4)") (class "Default")
      (node (ref "IC43") (pin "4") (pinfunction "4_4") (pintype "passive"))
      (node (ref "SV85") (pin "10") (pinfunction "10_10") (pintype "passive"))
      (node (ref "SV85") (pin "9") (pinfunction "9_9") (pintype "passive"))
    )
    (net (code "683") (name "Net-(IC43-Pad5)") (class "Default")
      (node (ref "IC43") (pin "5") (pinfunction "5_5") (pintype "passive"))
      (node (ref "SV85") (pin "7") (pinfunction "7_7") (pintype "passive"))
      (node (ref "SV85") (pin "8") (pinfunction "8_8") (pintype "passive"))
    )
    (net (code "684") (name "Net-(IC43-Pad6)") (class "Default")
      (node (ref "IC43") (pin "6") (pinfunction "6_6") (pintype "passive"))
      (node (ref "SV85") (pin "5") (pinfunction "5_5") (pintype "passive"))
      (node (ref "SV85") (pin "6") (pinfunction "6_6") (pintype "passive"))
    )
    (net (code "685") (name "Net-(IC43-Pad7)") (class "Default")
      (node (ref "IC43") (pin "7") (pinfunction "7_7") (pintype "passive"))
      (node (ref "SV85") (pin "3") (pinfunction "3_3") (pintype "passive"))
      (node (ref "SV85") (pin "4") (pinfunction "4_4") (pintype "passive"))
    )
    (net (code "686") (name "Net-(IC43-Pad8)") (class "Default")
      (node (ref "IC43") (pin "8") (pinfunction "8_8") (pintype "passive"))
      (node (ref "SV85") (pin "1") (pinfunction "1_1") (pintype "passive"))
      (node (ref "SV85") (pin "2") (pinfunction "2_2") (pintype "passive"))
    )
    (net (code "687") (name "Net-(IC43-Pad9)") (class "Default")
      (node (ref "IC43") (pin "9") (pinfunction "9_9") (pintype "passive"))
      (node (ref "SV86") (pin "1") (pinfunction "1_1") (pintype "passive"))
      (node (ref "SV86") (pin "2") (pinfunction "2_2") (pintype "passive"))
    )
    (net (code "688") (name "Net-(IC43-Pad10)") (class "Default")
      (node (ref "IC43") (pin "10") (pinfunction "10_10") (pintype "passive"))
      (node (ref "SV86") (pin "3") (pinfunction "3_3") (pintype "passive"))
      (node (ref "SV86") (pin "4") (pinfunction "4_4") (pintype "passive"))
    )
    (net (code "689") (name "Net-(IC43-Pad11)") (class "Default")
      (node (ref "IC43") (pin "11") (pinfunction "11_11") (pintype "passive"))
      (node (ref "SV86") (pin "5") (pinfunction "5_5") (pintype "passive"))
      (node (ref "SV86") (pin "6") (pinfunction "6_6") (pintype "passive"))
    )
    (net (code "690") (name "Net-(IC43-Pad12)") (class "Default")
      (node (ref "IC43") (pin "12") (pinfunction "12_12") (pintype "passive"))
      (node (ref "SV86") (pin "7") (pinfunction "7_7") (pintype "passive"))
      (node (ref "SV86") (pin "8") (pinfunction "8_8") (pintype "passive"))
    )
    (net (code "691") (name "Net-(IC43-Pad13)") (class "Default")
      (node (ref "IC43") (pin "13") (pinfunction "13_13") (pintype "passive"))
      (node (ref "SV86") (pin "10") (pinfunction "10_10") (pintype "passive"))
      (node (ref "SV86") (pin "9") (pinfunction "9_9") (pintype "passive"))
    )
    (net (code "692") (name "Net-(IC43-Pad14)") (class "Default")
      (node (ref "IC43") (pin "14") (pinfunction "14_14") (pintype "passive"))
      (node (ref "SV86") (pin "11") (pinfunction "11_11") (pintype "passive"))
      (node (ref "SV86") (pin "12") (pinfunction "12_12") (pintype "passive"))
    )
    (net (code "693") (name "Net-(IC43-Pad15)") (class "Default")
      (node (ref "IC43") (pin "15") (pinfunction "15_15") (pintype "passive"))
      (node (ref "SV86") (pin "13") (pinfunction "13_13") (pintype "passive"))
      (node (ref "SV86") (pin "14") (pinfunction "14_14") (pintype "passive"))
    )
    (net (code "694") (name "Net-(IC43-Pad16)") (class "Default")
      (node (ref "IC43") (pin "16") (pinfunction "16_16") (pintype "passive"))
      (node (ref "SV86") (pin "15") (pinfunction "15_15") (pintype "passive"))
      (node (ref "SV86") (pin "16") (pinfunction "16_16") (pintype "passive"))
    )
    (net (code "695") (name "Net-(IC44-Pad1)") (class "Default")
      (node (ref "IC44") (pin "1") (pinfunction "1_1") (pintype "passive"))
      (node (ref "SV87") (pin "15") (pinfunction "15_15") (pintype "passive"))
      (node (ref "SV87") (pin "16") (pinfunction "16_16") (pintype "passive"))
    )
    (net (code "696") (name "Net-(IC44-Pad2)") (class "Default")
      (node (ref "IC44") (pin "2") (pinfunction "2_2") (pintype "passive"))
      (node (ref "SV87") (pin "13") (pinfunction "13_13") (pintype "passive"))
      (node (ref "SV87") (pin "14") (pinfunction "14_14") (pintype "passive"))
    )
    (net (code "697") (name "Net-(IC44-Pad3)") (class "Default")
      (node (ref "IC44") (pin "3") (pinfunction "3_3") (pintype "passive"))
      (node (ref "SV87") (pin "11") (pinfunction "11_11") (pintype "passive"))
      (node (ref "SV87") (pin "12") (pinfunction "12_12") (pintype "passive"))
    )
    (net (code "698") (name "Net-(IC44-Pad4)") (class "Default")
      (node (ref "IC44") (pin "4") (pinfunction "4_4") (pintype "passive"))
      (node (ref "SV87") (pin "10") (pinfunction "10_10") (pintype "passive"))
      (node (ref "SV87") (pin "9") (pinfunction "9_9") (pintype "passive"))
    )
    (net (code "699") (name "Net-(IC44-Pad5)") (class "Default")
      (node (ref "IC44") (pin "5") (pinfunction "5_5") (pintype "passive"))
      (node (ref "SV87") (pin "7") (pinfunction "7_7") (pintype "passive"))
      (node (ref "SV87") (pin "8") (pinfunction "8_8") (pintype "passive"))
    )
    (net (code "700") (name "Net-(IC44-Pad6)") (class "Default")
      (node (ref "IC44") (pin "6") (pinfunction "6_6") (pintype "passive"))
      (node (ref "SV87") (pin "5") (pinfunction "5_5") (pintype "passive"))
      (node (ref "SV87") (pin "6") (pinfunction "6_6") (pintype "passive"))
    )
    (net (code "701") (name "Net-(IC44-Pad7)") (class "Default")
      (node (ref "IC44") (pin "7") (pinfunction "7_7") (pintype "passive"))
      (node (ref "SV87") (pin "3") (pinfunction "3_3") (pintype "passive"))
      (node (ref "SV87") (pin "4") (pinfunction "4_4") (pintype "passive"))
    )
    (net (code "702") (name "Net-(IC44-Pad8)") (class "Default")
      (node (ref "IC44") (pin "8") (pinfunction "8_8") (pintype "passive"))
      (node (ref "SV87") (pin "1") (pinfunction "1_1") (pintype "passive"))
      (node (ref "SV87") (pin "2") (pinfunction "2_2") (pintype "passive"))
    )
    (net (code "703") (name "Net-(IC44-Pad9)") (class "Default")
      (node (ref "IC44") (pin "9") (pinfunction "9_9") (pintype "passive"))
      (node (ref "SV88") (pin "1") (pinfunction "1_1") (pintype "passive"))
      (node (ref "SV88") (pin "2") (pinfunction "2_2") (pintype "passive"))
    )
    (net (code "704") (name "Net-(IC44-Pad10)") (class "Default")
      (node (ref "IC44") (pin "10") (pinfunction "10_10") (pintype "passive"))
      (node (ref "SV88") (pin "3") (pinfunction "3_3") (pintype "passive"))
      (node (ref "SV88") (pin "4") (pinfunction "4_4") (pintype "passive"))
    )
    (net (code "705") (name "Net-(IC44-Pad11)") (class "Default")
      (node (ref "IC44") (pin "11") (pinfunction "11_11") (pintype "passive"))
      (node (ref "SV88") (pin "5") (pinfunction "5_5") (pintype "passive"))
      (node (ref "SV88") (pin "6") (pinfunction "6_6") (pintype "passive"))
    )
    (net (code "706") (name "Net-(IC44-Pad12)") (class "Default")
      (node (ref "IC44") (pin "12") (pinfunction "12_12") (pintype "passive"))
      (node (ref "SV88") (pin "7") (pinfunction "7_7") (pintype "passive"))
      (node (ref "SV88") (pin "8") (pinfunction "8_8") (pintype "passive"))
    )
    (net (code "707") (name "Net-(IC44-Pad13)") (class "Default")
      (node (ref "IC44") (pin "13") (pinfunction "13_13") (pintype "passive"))
      (node (ref "SV88") (pin "10") (pinfunction "10_10") (pintype "passive"))
      (node (ref "SV88") (pin "9") (pinfunction "9_9") (pintype "passive"))
    )
    (net (code "708") (name "Net-(IC44-Pad14)") (class "Default")
      (node (ref "IC44") (pin "14") (pinfunction "14_14") (pintype "passive"))
      (node (ref "SV88") (pin "11") (pinfunction "11_11") (pintype "passive"))
      (node (ref "SV88") (pin "12") (pinfunction "12_12") (pintype "passive"))
    )
    (net (code "709") (name "Net-(IC44-Pad15)") (class "Default")
      (node (ref "IC44") (pin "15") (pinfunction "15_15") (pintype "passive"))
      (node (ref "SV88") (pin "13") (pinfunction "13_13") (pintype "passive"))
      (node (ref "SV88") (pin "14") (pinfunction "14_14") (pintype "passive"))
    )
    (net (code "710") (name "Net-(IC44-Pad16)") (class "Default")
      (node (ref "IC44") (pin "16") (pinfunction "16_16") (pintype "passive"))
      (node (ref "SV88") (pin "15") (pinfunction "15_15") (pintype "passive"))
      (node (ref "SV88") (pin "16") (pinfunction "16_16") (pintype "passive"))
    )
    (net (code "711") (name "Net-(IC45-Pad1)") (class "Default")
      (node (ref "IC45") (pin "1") (pinfunction "1_1") (pintype "passive"))
      (node (ref "SV89") (pin "15") (pinfunction "15_15") (pintype "passive"))
      (node (ref "SV89") (pin "16") (pinfunction "16_16") (pintype "passive"))
    )
    (net (code "712") (name "Net-(IC45-Pad2)") (class "Default")
      (node (ref "IC45") (pin "2") (pinfunction "2_2") (pintype "passive"))
      (node (ref "SV89") (pin "13") (pinfunction "13_13") (pintype "passive"))
      (node (ref "SV89") (pin "14") (pinfunction "14_14") (pintype "passive"))
    )
    (net (code "713") (name "Net-(IC45-Pad3)") (class "Default")
      (node (ref "IC45") (pin "3") (pinfunction "3_3") (pintype "passive"))
      (node (ref "SV89") (pin "11") (pinfunction "11_11") (pintype "passive"))
      (node (ref "SV89") (pin "12") (pinfunction "12_12") (pintype "passive"))
    )
    (net (code "714") (name "Net-(IC45-Pad4)") (class "Default")
      (node (ref "IC45") (pin "4") (pinfunction "4_4") (pintype "passive"))
      (node (ref "SV89") (pin "10") (pinfunction "10_10") (pintype "passive"))
      (node (ref "SV89") (pin "9") (pinfunction "9_9") (pintype "passive"))
    )
    (net (code "715") (name "Net-(IC45-Pad5)") (class "Default")
      (node (ref "IC45") (pin "5") (pinfunction "5_5") (pintype "passive"))
      (node (ref "SV89") (pin "7") (pinfunction "7_7") (pintype "passive"))
      (node (ref "SV89") (pin "8") (pinfunction "8_8") (pintype "passive"))
    )
    (net (code "716") (name "Net-(IC45-Pad6)") (class "Default")
      (node (ref "IC45") (pin "6") (pinfunction "6_6") (pintype "passive"))
      (node (ref "SV89") (pin "5") (pinfunction "5_5") (pintype "passive"))
      (node (ref "SV89") (pin "6") (pinfunction "6_6") (pintype "passive"))
    )
    (net (code "717") (name "Net-(IC45-Pad7)") (class "Default")
      (node (ref "IC45") (pin "7") (pinfunction "7_7") (pintype "passive"))
      (node (ref "SV89") (pin "3") (pinfunction "3_3") (pintype "passive"))
      (node (ref "SV89") (pin "4") (pinfunction "4_4") (pintype "passive"))
    )
    (net (code "718") (name "Net-(IC45-Pad8)") (class "Default")
      (node (ref "IC45") (pin "8") (pinfunction "8_8") (pintype "passive"))
      (node (ref "SV89") (pin "1") (pinfunction "1_1") (pintype "passive"))
      (node (ref "SV89") (pin "2") (pinfunction "2_2") (pintype "passive"))
    )
    (net (code "719") (name "Net-(IC45-Pad9)") (class "Default")
      (node (ref "IC45") (pin "9") (pinfunction "9_9") (pintype "passive"))
      (node (ref "SV90") (pin "1") (pinfunction "1_1") (pintype "passive"))
      (node (ref "SV90") (pin "2") (pinfunction "2_2") (pintype "passive"))
    )
    (net (code "720") (name "Net-(IC45-Pad10)") (class "Default")
      (node (ref "IC45") (pin "10") (pinfunction "10_10") (pintype "passive"))
      (node (ref "SV90") (pin "3") (pinfunction "3_3") (pintype "passive"))
      (node (ref "SV90") (pin "4") (pinfunction "4_4") (pintype "passive"))
    )
    (net (code "721") (name "Net-(IC45-Pad11)") (class "Default")
      (node (ref "IC45") (pin "11") (pinfunction "11_11") (pintype "passive"))
      (node (ref "SV90") (pin "5") (pinfunction "5_5") (pintype "passive"))
      (node (ref "SV90") (pin "6") (pinfunction "6_6") (pintype "passive"))
    )
    (net (code "722") (name "Net-(IC45-Pad12)") (class "Default")
      (node (ref "IC45") (pin "12") (pinfunction "12_12") (pintype "passive"))
      (node (ref "SV90") (pin "7") (pinfunction "7_7") (pintype "passive"))
      (node (ref "SV90") (pin "8") (pinfunction "8_8") (pintype "passive"))
    )
    (net (code "723") (name "Net-(IC45-Pad13)") (class "Default")
      (node (ref "IC45") (pin "13") (pinfunction "13_13") (pintype "passive"))
      (node (ref "SV90") (pin "10") (pinfunction "10_10") (pintype "passive"))
      (node (ref "SV90") (pin "9") (pinfunction "9_9") (pintype "passive"))
    )
    (net (code "724") (name "Net-(IC45-Pad14)") (class "Default")
      (node (ref "IC45") (pin "14") (pinfunction "14_14") (pintype "passive"))
      (node (ref "SV90") (pin "11") (pinfunction "11_11") (pintype "passive"))
      (node (ref "SV90") (pin "12") (pinfunction "12_12") (pintype "passive"))
    )
    (net (code "725") (name "Net-(IC45-Pad15)") (class "Default")
      (node (ref "IC45") (pin "15") (pinfunction "15_15") (pintype "passive"))
      (node (ref "SV90") (pin "13") (pinfunction "13_13") (pintype "passive"))
      (node (ref "SV90") (pin "14") (pinfunction "14_14") (pintype "passive"))
    )
    (net (code "726") (name "Net-(IC45-Pad16)") (class "Default")
      (node (ref "IC45") (pin "16") (pinfunction "16_16") (pintype "passive"))
      (node (ref "SV90") (pin "15") (pinfunction "15_15") (pintype "passive"))
      (node (ref "SV90") (pin "16") (pinfunction "16_16") (pintype "passive"))
    )
    (net (code "727") (name "Net-(IC46-Pad1)") (class "Default")
      (node (ref "IC46") (pin "1") (pinfunction "1_1") (pintype "passive"))
      (node (ref "SV91") (pin "15") (pinfunction "15_15") (pintype "passive"))
      (node (ref "SV91") (pin "16") (pinfunction "16_16") (pintype "passive"))
    )
    (net (code "728") (name "Net-(IC46-Pad2)") (class "Default")
      (node (ref "IC46") (pin "2") (pinfunction "2_2") (pintype "passive"))
      (node (ref "SV91") (pin "13") (pinfunction "13_13") (pintype "passive"))
      (node (ref "SV91") (pin "14") (pinfunction "14_14") (pintype "passive"))
    )
    (net (code "729") (name "Net-(IC46-Pad3)") (class "Default")
      (node (ref "IC46") (pin "3") (pinfunction "3_3") (pintype "passive"))
      (node (ref "SV91") (pin "11") (pinfunction "11_11") (pintype "passive"))
      (node (ref "SV91") (pin "12") (pinfunction "12_12") (pintype "passive"))
    )
    (net (code "730") (name "Net-(IC46-Pad4)") (class "Default")
      (node (ref "IC46") (pin "4") (pinfunction "4_4") (pintype "passive"))
      (node (ref "SV91") (pin "10") (pinfunction "10_10") (pintype "passive"))
      (node (ref "SV91") (pin "9") (pinfunction "9_9") (pintype "passive"))
    )
    (net (code "731") (name "Net-(IC46-Pad5)") (class "Default")
      (node (ref "IC46") (pin "5") (pinfunction "5_5") (pintype "passive"))
      (node (ref "SV91") (pin "7") (pinfunction "7_7") (pintype "passive"))
      (node (ref "SV91") (pin "8") (pinfunction "8_8") (pintype "passive"))
    )
    (net (code "732") (name "Net-(IC46-Pad6)") (class "Default")
      (node (ref "IC46") (pin "6") (pinfunction "6_6") (pintype "passive"))
      (node (ref "SV91") (pin "5") (pinfunction "5_5") (pintype "passive"))
      (node (ref "SV91") (pin "6") (pinfunction "6_6") (pintype "passive"))
    )
    (net (code "733") (name "Net-(IC46-Pad7)") (class "Default")
      (node (ref "IC46") (pin "7") (pinfunction "7_7") (pintype "passive"))
      (node (ref "SV91") (pin "3") (pinfunction "3_3") (pintype "passive"))
      (node (ref "SV91") (pin "4") (pinfunction "4_4") (pintype "passive"))
    )
    (net (code "734") (name "Net-(IC46-Pad8)") (class "Default")
      (node (ref "IC46") (pin "8") (pinfunction "8_8") (pintype "passive"))
      (node (ref "SV91") (pin "1") (pinfunction "1_1") (pintype "passive"))
      (node (ref "SV91") (pin "2") (pinfunction "2_2") (pintype "passive"))
    )
    (net (code "735") (name "Net-(IC46-Pad9)") (class "Default")
      (node (ref "IC46") (pin "9") (pinfunction "9_9") (pintype "passive"))
      (node (ref "SV92") (pin "1") (pinfunction "1_1") (pintype "passive"))
      (node (ref "SV92") (pin "2") (pinfunction "2_2") (pintype "passive"))
    )
    (net (code "736") (name "Net-(IC46-Pad10)") (class "Default")
      (node (ref "IC46") (pin "10") (pinfunction "10_10") (pintype "passive"))
      (node (ref "SV92") (pin "3") (pinfunction "3_3") (pintype "passive"))
      (node (ref "SV92") (pin "4") (pinfunction "4_4") (pintype "passive"))
    )
    (net (code "737") (name "Net-(IC46-Pad11)") (class "Default")
      (node (ref "IC46") (pin "11") (pinfunction "11_11") (pintype "passive"))
      (node (ref "SV92") (pin "5") (pinfunction "5_5") (pintype "passive"))
      (node (ref "SV92") (pin "6") (pinfunction "6_6") (pintype "passive"))
    )
    (net (code "738") (name "Net-(IC46-Pad12)") (class "Default")
      (node (ref "IC46") (pin "12") (pinfunction "12_12") (pintype "passive"))
      (node (ref "SV92") (pin "7") (pinfunction "7_7") (pintype "passive"))
      (node (ref "SV92") (pin "8") (pinfunction "8_8") (pintype "passive"))
    )
    (net (code "739") (name "Net-(IC46-Pad13)") (class "Default")
      (node (ref "IC46") (pin "13") (pinfunction "13_13") (pintype "passive"))
      (node (ref "SV92") (pin "10") (pinfunction "10_10") (pintype "passive"))
      (node (ref "SV92") (pin "9") (pinfunction "9_9") (pintype "passive"))
    )
    (net (code "740") (name "Net-(IC46-Pad14)") (class "Default")
      (node (ref "IC46") (pin "14") (pinfunction "14_14") (pintype "passive"))
      (node (ref "SV92") (pin "11") (pinfunction "11_11") (pintype "passive"))
      (node (ref "SV92") (pin "12") (pinfunction "12_12") (pintype "passive"))
    )
    (net (code "741") (name "Net-(IC46-Pad15)") (class "Default")
      (node (ref "IC46") (pin "15") (pinfunction "15_15") (pintype "passive"))
      (node (ref "SV92") (pin "13") (pinfunction "13_13") (pintype "passive"))
      (node (ref "SV92") (pin "14") (pinfunction "14_14") (pintype "passive"))
    )
    (net (code "742") (name "Net-(IC46-Pad16)") (class "Default")
      (node (ref "IC46") (pin "16") (pinfunction "16_16") (pintype "passive"))
      (node (ref "SV92") (pin "15") (pinfunction "15_15") (pintype "passive"))
      (node (ref "SV92") (pin "16") (pinfunction "16_16") (pintype "passive"))
    )
    (net (code "743") (name "Net-(IC47-Pad1)") (class "Default")
      (node (ref "IC47") (pin "1") (pinfunction "1_1") (pintype "passive"))
      (node (ref "SV93") (pin "15") (pinfunction "15_15") (pintype "passive"))
      (node (ref "SV93") (pin "16") (pinfunction "16_16") (pintype "passive"))
    )
    (net (code "744") (name "Net-(IC47-Pad2)") (class "Default")
      (node (ref "IC47") (pin "2") (pinfunction "2_2") (pintype "passive"))
      (node (ref "SV93") (pin "13") (pinfunction "13_13") (pintype "passive"))
      (node (ref "SV93") (pin "14") (pinfunction "14_14") (pintype "passive"))
    )
    (net (code "745") (name "Net-(IC47-Pad3)") (class "Default")
      (node (ref "IC47") (pin "3") (pinfunction "3_3") (pintype "passive"))
      (node (ref "SV93") (pin "11") (pinfunction "11_11") (pintype "passive"))
      (node (ref "SV93") (pin "12") (pinfunction "12_12") (pintype "passive"))
    )
    (net (code "746") (name "Net-(IC47-Pad4)") (class "Default")
      (node (ref "IC47") (pin "4") (pinfunction "4_4") (pintype "passive"))
      (node (ref "SV93") (pin "10") (pinfunction "10_10") (pintype "passive"))
      (node (ref "SV93") (pin "9") (pinfunction "9_9") (pintype "passive"))
    )
    (net (code "747") (name "Net-(IC47-Pad5)") (class "Default")
      (node (ref "IC47") (pin "5") (pinfunction "5_5") (pintype "passive"))
      (node (ref "SV93") (pin "7") (pinfunction "7_7") (pintype "passive"))
      (node (ref "SV93") (pin "8") (pinfunction "8_8") (pintype "passive"))
    )
    (net (code "748") (name "Net-(IC47-Pad6)") (class "Default")
      (node (ref "IC47") (pin "6") (pinfunction "6_6") (pintype "passive"))
      (node (ref "SV93") (pin "5") (pinfunction "5_5") (pintype "passive"))
      (node (ref "SV93") (pin "6") (pinfunction "6_6") (pintype "passive"))
    )
    (net (code "749") (name "Net-(IC47-Pad7)") (class "Default")
      (node (ref "IC47") (pin "7") (pinfunction "7_7") (pintype "passive"))
      (node (ref "SV93") (pin "3") (pinfunction "3_3") (pintype "passive"))
      (node (ref "SV93") (pin "4") (pinfunction "4_4") (pintype "passive"))
    )
    (net (code "750") (name "Net-(IC47-Pad8)") (class "Default")
      (node (ref "IC47") (pin "8") (pinfunction "8_8") (pintype "passive"))
      (node (ref "SV93") (pin "1") (pinfunction "1_1") (pintype "passive"))
      (node (ref "SV93") (pin "2") (pinfunction "2_2") (pintype "passive"))
    )
    (net (code "751") (name "Net-(IC47-Pad9)") (class "Default")
      (node (ref "IC47") (pin "9") (pinfunction "9_9") (pintype "passive"))
      (node (ref "SV94") (pin "1") (pinfunction "1_1") (pintype "passive"))
      (node (ref "SV94") (pin "2") (pinfunction "2_2") (pintype "passive"))
    )
    (net (code "752") (name "Net-(IC47-Pad10)") (class "Default")
      (node (ref "IC47") (pin "10") (pinfunction "10_10") (pintype "passive"))
      (node (ref "SV94") (pin "3") (pinfunction "3_3") (pintype "passive"))
      (node (ref "SV94") (pin "4") (pinfunction "4_4") (pintype "passive"))
    )
    (net (code "753") (name "Net-(IC47-Pad11)") (class "Default")
      (node (ref "IC47") (pin "11") (pinfunction "11_11") (pintype "passive"))
      (node (ref "SV94") (pin "5") (pinfunction "5_5") (pintype "passive"))
      (node (ref "SV94") (pin "6") (pinfunction "6_6") (pintype "passive"))
    )
    (net (code "754") (name "Net-(IC47-Pad12)") (class "Default")
      (node (ref "IC47") (pin "12") (pinfunction "12_12") (pintype "passive"))
      (node (ref "SV94") (pin "7") (pinfunction "7_7") (pintype "passive"))
      (node (ref "SV94") (pin "8") (pinfunction "8_8") (pintype "passive"))
    )
    (net (code "755") (name "Net-(IC47-Pad13)") (class "Default")
      (node (ref "IC47") (pin "13") (pinfunction "13_13") (pintype "passive"))
      (node (ref "SV94") (pin "10") (pinfunction "10_10") (pintype "passive"))
      (node (ref "SV94") (pin "9") (pinfunction "9_9") (pintype "passive"))
    )
    (net (code "756") (name "Net-(IC47-Pad14)") (class "Default")
      (node (ref "IC47") (pin "14") (pinfunction "14_14") (pintype "passive"))
      (node (ref "SV94") (pin "11") (pinfunction "11_11") (pintype "passive"))
      (node (ref "SV94") (pin "12") (pinfunction "12_12") (pintype "passive"))
    )
    (net (code "757") (name "Net-(IC47-Pad15)") (class "Default")
      (node (ref "IC47") (pin "15") (pinfunction "15_15") (pintype "passive"))
      (node (ref "SV94") (pin "13") (pinfunction "13_13") (pintype "passive"))
      (node (ref "SV94") (pin "14") (pinfunction "14_14") (pintype "passive"))
    )
    (net (code "758") (name "Net-(IC47-Pad16)") (class "Default")
      (node (ref "IC47") (pin "16") (pinfunction "16_16") (pintype "passive"))
      (node (ref "SV94") (pin "15") (pinfunction "15_15") (pintype "passive"))
      (node (ref "SV94") (pin "16") (pinfunction "16_16") (pintype "passive"))
    )
    (net (code "759") (name "Net-(IC48-Pad1)") (class "Default")
      (node (ref "IC48") (pin "1") (pinfunction "1_1") (pintype "passive"))
      (node (ref "SV95") (pin "15") (pinfunction "15_15") (pintype "passive"))
      (node (ref "SV95") (pin "16") (pinfunction "16_16") (pintype "passive"))
    )
    (net (code "760") (name "Net-(IC48-Pad2)") (class "Default")
      (node (ref "IC48") (pin "2") (pinfunction "2_2") (pintype "passive"))
      (node (ref "SV95") (pin "13") (pinfunction "13_13") (pintype "passive"))
      (node (ref "SV95") (pin "14") (pinfunction "14_14") (pintype "passive"))
    )
    (net (code "761") (name "Net-(IC48-Pad3)") (class "Default")
      (node (ref "IC48") (pin "3") (pinfunction "3_3") (pintype "passive"))
      (node (ref "SV95") (pin "11") (pinfunction "11_11") (pintype "passive"))
      (node (ref "SV95") (pin "12") (pinfunction "12_12") (pintype "passive"))
    )
    (net (code "762") (name "Net-(IC48-Pad4)") (class "Default")
      (node (ref "IC48") (pin "4") (pinfunction "4_4") (pintype "passive"))
      (node (ref "SV95") (pin "10") (pinfunction "10_10") (pintype "passive"))
      (node (ref "SV95") (pin "9") (pinfunction "9_9") (pintype "passive"))
    )
    (net (code "763") (name "Net-(IC48-Pad5)") (class "Default")
      (node (ref "IC48") (pin "5") (pinfunction "5_5") (pintype "passive"))
      (node (ref "SV95") (pin "7") (pinfunction "7_7") (pintype "passive"))
      (node (ref "SV95") (pin "8") (pinfunction "8_8") (pintype "passive"))
    )
    (net (code "764") (name "Net-(IC48-Pad6)") (class "Default")
      (node (ref "IC48") (pin "6") (pinfunction "6_6") (pintype "passive"))
      (node (ref "SV95") (pin "5") (pinfunction "5_5") (pintype "passive"))
      (node (ref "SV95") (pin "6") (pinfunction "6_6") (pintype "passive"))
    )
    (net (code "765") (name "Net-(IC48-Pad7)") (class "Default")
      (node (ref "IC48") (pin "7") (pinfunction "7_7") (pintype "passive"))
      (node (ref "SV95") (pin "3") (pinfunction "3_3") (pintype "passive"))
      (node (ref "SV95") (pin "4") (pinfunction "4_4") (pintype "passive"))
    )
    (net (code "766") (name "Net-(IC48-Pad8)") (class "Default")
      (node (ref "IC48") (pin "8") (pinfunction "8_8") (pintype "passive"))
      (node (ref "SV95") (pin "1") (pinfunction "1_1") (pintype "passive"))
      (node (ref "SV95") (pin "2") (pinfunction "2_2") (pintype "passive"))
    )
    (net (code "767") (name "Net-(IC48-Pad9)") (class "Default")
      (node (ref "IC48") (pin "9") (pinfunction "9_9") (pintype "passive"))
      (node (ref "SV96") (pin "1") (pinfunction "1_1") (pintype "passive"))
      (node (ref "SV96") (pin "2") (pinfunction "2_2") (pintype "passive"))
    )
    (net (code "768") (name "Net-(IC48-Pad10)") (class "Default")
      (node (ref "IC48") (pin "10") (pinfunction "10_10") (pintype "passive"))
      (node (ref "SV96") (pin "3") (pinfunction "3_3") (pintype "passive"))
      (node (ref "SV96") (pin "4") (pinfunction "4_4") (pintype "passive"))
    )
    (net (code "769") (name "Net-(IC48-Pad11)") (class "Default")
      (node (ref "IC48") (pin "11") (pinfunction "11_11") (pintype "passive"))
      (node (ref "SV96") (pin "5") (pinfunction "5_5") (pintype "passive"))
      (node (ref "SV96") (pin "6") (pinfunction "6_6") (pintype "passive"))
    )
    (net (code "770") (name "Net-(IC48-Pad12)") (class "Default")
      (node (ref "IC48") (pin "12") (pinfunction "12_12") (pintype "passive"))
      (node (ref "SV96") (pin "7") (pinfunction "7_7") (pintype "passive"))
      (node (ref "SV96") (pin "8") (pinfunction "8_8") (pintype "passive"))
    )
    (net (code "771") (name "Net-(IC48-Pad13)") (class "Default")
      (node (ref "IC48") (pin "13") (pinfunction "13_13") (pintype "passive"))
      (node (ref "SV96") (pin "10") (pinfunction "10_10") (pintype "passive"))
      (node (ref "SV96") (pin "9") (pinfunction "9_9") (pintype "passive"))
    )
    (net (code "772") (name "Net-(IC48-Pad14)") (class "Default")
      (node (ref "IC48") (pin "14") (pinfunction "14_14") (pintype "passive"))
      (node (ref "SV96") (pin "11") (pinfunction "11_11") (pintype "passive"))
      (node (ref "SV96") (pin "12") (pinfunction "12_12") (pintype "passive"))
    )
    (net (code "773") (name "Net-(IC48-Pad15)") (class "Default")
      (node (ref "IC48") (pin "15") (pinfunction "15_15") (pintype "passive"))
      (node (ref "SV96") (pin "13") (pinfunction "13_13") (pintype "passive"))
      (node (ref "SV96") (pin "14") (pinfunction "14_14") (pintype "passive"))
    )
    (net (code "774") (name "Net-(IC48-Pad16)") (class "Default")
      (node (ref "IC48") (pin "16") (pinfunction "16_16") (pintype "passive"))
      (node (ref "SV96") (pin "15") (pinfunction "15_15") (pintype "passive"))
      (node (ref "SV96") (pin "16") (pinfunction "16_16") (pintype "passive"))
    )
    (net (code "775") (name "Net-(IC49-Pad1)") (class "Default")
      (node (ref "IC49") (pin "1") (pinfunction "1_1") (pintype "passive"))
      (node (ref "SV97") (pin "15") (pinfunction "15_15") (pintype "passive"))
      (node (ref "SV97") (pin "16") (pinfunction "16_16") (pintype "passive"))
    )
    (net (code "776") (name "Net-(IC49-Pad2)") (class "Default")
      (node (ref "IC49") (pin "2") (pinfunction "2_2") (pintype "passive"))
      (node (ref "SV97") (pin "13") (pinfunction "13_13") (pintype "passive"))
      (node (ref "SV97") (pin "14") (pinfunction "14_14") (pintype "passive"))
    )
    (net (code "777") (name "Net-(IC49-Pad3)") (class "Default")
      (node (ref "IC49") (pin "3") (pinfunction "3_3") (pintype "passive"))
      (node (ref "SV97") (pin "11") (pinfunction "11_11") (pintype "passive"))
      (node (ref "SV97") (pin "12") (pinfunction "12_12") (pintype "passive"))
    )
    (net (code "778") (name "Net-(IC49-Pad4)") (class "Default")
      (node (ref "IC49") (pin "4") (pinfunction "4_4") (pintype "passive"))
      (node (ref "SV97") (pin "10") (pinfunction "10_10") (pintype "passive"))
      (node (ref "SV97") (pin "9") (pinfunction "9_9") (pintype "passive"))
    )
    (net (code "779") (name "Net-(IC49-Pad5)") (class "Default")
      (node (ref "IC49") (pin "5") (pinfunction "5_5") (pintype "passive"))
      (node (ref "SV97") (pin "7") (pinfunction "7_7") (pintype "passive"))
      (node (ref "SV97") (pin "8") (pinfunction "8_8") (pintype "passive"))
    )
    (net (code "780") (name "Net-(IC49-Pad6)") (class "Default")
      (node (ref "IC49") (pin "6") (pinfunction "6_6") (pintype "passive"))
      (node (ref "SV97") (pin "5") (pinfunction "5_5") (pintype "passive"))
      (node (ref "SV97") (pin "6") (pinfunction "6_6") (pintype "passive"))
    )
    (net (code "781") (name "Net-(IC49-Pad7)") (class "Default")
      (node (ref "IC49") (pin "7") (pinfunction "7_7") (pintype "passive"))
      (node (ref "SV97") (pin "3") (pinfunction "3_3") (pintype "passive"))
      (node (ref "SV97") (pin "4") (pinfunction "4_4") (pintype "passive"))
    )
    (net (code "782") (name "Net-(IC49-Pad8)") (class "Default")
      (node (ref "IC49") (pin "8") (pinfunction "8_8") (pintype "passive"))
      (node (ref "SV97") (pin "1") (pinfunction "1_1") (pintype "passive"))
      (node (ref "SV97") (pin "2") (pinfunction "2_2") (pintype "passive"))
    )
    (net (code "783") (name "Net-(IC49-Pad9)") (class "Default")
      (node (ref "IC49") (pin "9") (pinfunction "9_9") (pintype "passive"))
      (node (ref "SV98") (pin "1") (pinfunction "1_1") (pintype "passive"))
      (node (ref "SV98") (pin "2") (pinfunction "2_2") (pintype "passive"))
    )
    (net (code "784") (name "Net-(IC49-Pad10)") (class "Default")
      (node (ref "IC49") (pin "10") (pinfunction "10_10") (pintype "passive"))
      (node (ref "SV98") (pin "3") (pinfunction "3_3") (pintype "passive"))
      (node (ref "SV98") (pin "4") (pinfunction "4_4") (pintype "passive"))
    )
    (net (code "785") (name "Net-(IC49-Pad11)") (class "Default")
      (node (ref "IC49") (pin "11") (pinfunction "11_11") (pintype "passive"))
      (node (ref "SV98") (pin "5") (pinfunction "5_5") (pintype "passive"))
      (node (ref "SV98") (pin "6") (pinfunction "6_6") (pintype "passive"))
    )
    (net (code "786") (name "Net-(IC49-Pad12)") (class "Default")
      (node (ref "IC49") (pin "12") (pinfunction "12_12") (pintype "passive"))
      (node (ref "SV98") (pin "7") (pinfunction "7_7") (pintype "passive"))
      (node (ref "SV98") (pin "8") (pinfunction "8_8") (pintype "passive"))
    )
    (net (code "787") (name "Net-(IC49-Pad13)") (class "Default")
      (node (ref "IC49") (pin "13") (pinfunction "13_13") (pintype "passive"))
      (node (ref "SV98") (pin "10") (pinfunction "10_10") (pintype "passive"))
      (node (ref "SV98") (pin "9") (pinfunction "9_9") (pintype "passive"))
    )
    (net (code "788") (name "Net-(IC49-Pad14)") (class "Default")
      (node (ref "IC49") (pin "14") (pinfunction "14_14") (pintype "passive"))
      (node (ref "SV98") (pin "11") (pinfunction "11_11") (pintype "passive"))
      (node (ref "SV98") (pin "12") (pinfunction "12_12") (pintype "passive"))
    )
    (net (code "789") (name "Net-(IC49-Pad15)") (class "Default")
      (node (ref "IC49") (pin "15") (pinfunction "15_15") (pintype "passive"))
      (node (ref "SV98") (pin "13") (pinfunction "13_13") (pintype "passive"))
      (node (ref "SV98") (pin "14") (pinfunction "14_14") (pintype "passive"))
    )
    (net (code "790") (name "Net-(IC49-Pad16)") (class "Default")
      (node (ref "IC49") (pin "16") (pinfunction "16_16") (pintype "passive"))
      (node (ref "SV98") (pin "15") (pinfunction "15_15") (pintype "passive"))
      (node (ref "SV98") (pin "16") (pinfunction "16_16") (pintype "passive"))
    )
    (net (code "791") (name "Net-(IC50-Pad1)") (class "Default")
      (node (ref "IC50") (pin "1") (pinfunction "1_1") (pintype "passive"))
      (node (ref "SV99") (pin "15") (pinfunction "15_15") (pintype "passive"))
      (node (ref "SV99") (pin "16") (pinfunction "16_16") (pintype "passive"))
    )
    (net (code "792") (name "Net-(IC50-Pad2)") (class "Default")
      (node (ref "IC50") (pin "2") (pinfunction "2_2") (pintype "passive"))
      (node (ref "SV99") (pin "13") (pinfunction "13_13") (pintype "passive"))
      (node (ref "SV99") (pin "14") (pinfunction "14_14") (pintype "passive"))
    )
    (net (code "793") (name "Net-(IC50-Pad3)") (class "Default")
      (node (ref "IC50") (pin "3") (pinfunction "3_3") (pintype "passive"))
      (node (ref "SV99") (pin "11") (pinfunction "11_11") (pintype "passive"))
      (node (ref "SV99") (pin "12") (pinfunction "12_12") (pintype "passive"))
    )
    (net (code "794") (name "Net-(IC50-Pad4)") (class "Default")
      (node (ref "IC50") (pin "4") (pinfunction "4_4") (pintype "passive"))
      (node (ref "SV99") (pin "10") (pinfunction "10_10") (pintype "passive"))
      (node (ref "SV99") (pin "9") (pinfunction "9_9") (pintype "passive"))
    )
    (net (code "795") (name "Net-(IC50-Pad5)") (class "Default")
      (node (ref "IC50") (pin "5") (pinfunction "5_5") (pintype "passive"))
      (node (ref "SV99") (pin "7") (pinfunction "7_7") (pintype "passive"))
      (node (ref "SV99") (pin "8") (pinfunction "8_8") (pintype "passive"))
    )
    (net (code "796") (name "Net-(IC50-Pad6)") (class "Default")
      (node (ref "IC50") (pin "6") (pinfunction "6_6") (pintype "passive"))
      (node (ref "SV99") (pin "5") (pinfunction "5_5") (pintype "passive"))
      (node (ref "SV99") (pin "6") (pinfunction "6_6") (pintype "passive"))
    )
    (net (code "797") (name "Net-(IC50-Pad7)") (class "Default")
      (node (ref "IC50") (pin "7") (pinfunction "7_7") (pintype "passive"))
      (node (ref "SV99") (pin "3") (pinfunction "3_3") (pintype "passive"))
      (node (ref "SV99") (pin "4") (pinfunction "4_4") (pintype "passive"))
    )
    (net (code "798") (name "Net-(IC50-Pad8)") (class "Default")
      (node (ref "IC50") (pin "8") (pinfunction "8_8") (pintype "passive"))
      (node (ref "SV99") (pin "1") (pinfunction "1_1") (pintype "passive"))
      (node (ref "SV99") (pin "2") (pinfunction "2_2") (pintype "passive"))
    )
    (net (code "799") (name "Net-(IC50-Pad9)") (class "Default")
      (node (ref "IC50") (pin "9") (pinfunction "9_9") (pintype "passive"))
      (node (ref "SV100") (pin "1") (pinfunction "1_1") (pintype "passive"))
      (node (ref "SV100") (pin "2") (pinfunction "2_2") (pintype "passive"))
    )
    (net (code "800") (name "Net-(IC50-Pad10)") (class "Default")
      (node (ref "IC50") (pin "10") (pinfunction "10_10") (pintype "passive"))
      (node (ref "SV100") (pin "3") (pinfunction "3_3") (pintype "passive"))
      (node (ref "SV100") (pin "4") (pinfunction "4_4") (pintype "passive"))
    )
    (net (code "801") (name "Net-(IC50-Pad11)") (class "Default")
      (node (ref "IC50") (pin "11") (pinfunction "11_11") (pintype "passive"))
      (node (ref "SV100") (pin "5") (pinfunction "5_5") (pintype "passive"))
      (node (ref "SV100") (pin "6") (pinfunction "6_6") (pintype "passive"))
    )
    (net (code "802") (name "Net-(IC50-Pad12)") (class "Default")
      (node (ref "IC50") (pin "12") (pinfunction "12_12") (pintype "passive"))
      (node (ref "SV100") (pin "7") (pinfunction "7_7") (pintype "passive"))
      (node (ref "SV100") (pin "8") (pinfunction "8_8") (pintype "passive"))
    )
    (net (code "803") (name "Net-(IC50-Pad13)") (class "Default")
      (node (ref "IC50") (pin "13") (pinfunction "13_13") (pintype "passive"))
      (node (ref "SV100") (pin "10") (pinfunction "10_10") (pintype "passive"))
      (node (ref "SV100") (pin "9") (pinfunction "9_9") (pintype "passive"))
    )
    (net (code "804") (name "Net-(IC50-Pad14)") (class "Default")
      (node (ref "IC50") (pin "14") (pinfunction "14_14") (pintype "passive"))
      (node (ref "SV100") (pin "11") (pinfunction "11_11") (pintype "passive"))
      (node (ref "SV100") (pin "12") (pinfunction "12_12") (pintype "passive"))
    )
    (net (code "805") (name "Net-(IC50-Pad15)") (class "Default")
      (node (ref "IC50") (pin "15") (pinfunction "15_15") (pintype "passive"))
      (node (ref "SV100") (pin "13") (pinfunction "13_13") (pintype "passive"))
      (node (ref "SV100") (pin "14") (pinfunction "14_14") (pintype "passive"))
    )
    (net (code "806") (name "Net-(IC50-Pad16)") (class "Default")
      (node (ref "IC50") (pin "16") (pinfunction "16_16") (pintype "passive"))
      (node (ref "SV100") (pin "15") (pinfunction "15_15") (pintype "passive"))
      (node (ref "SV100") (pin "16") (pinfunction "16_16") (pintype "passive"))
    )
    (net (code "807") (name "Net-(IC51-Pad1)") (class "Default")
      (node (ref "IC51") (pin "1") (pinfunction "1_1") (pintype "passive"))
      (node (ref "SV101") (pin "15") (pinfunction "15_15") (pintype "passive"))
      (node (ref "SV101") (pin "16") (pinfunction "16_16") (pintype "passive"))
    )
    (net (code "808") (name "Net-(IC51-Pad2)") (class "Default")
      (node (ref "IC51") (pin "2") (pinfunction "2_2") (pintype "passive"))
      (node (ref "SV101") (pin "13") (pinfunction "13_13") (pintype "passive"))
      (node (ref "SV101") (pin "14") (pinfunction "14_14") (pintype "passive"))
    )
    (net (code "809") (name "Net-(IC51-Pad3)") (class "Default")
      (node (ref "IC51") (pin "3") (pinfunction "3_3") (pintype "passive"))
      (node (ref "SV101") (pin "11") (pinfunction "11_11") (pintype "passive"))
      (node (ref "SV101") (pin "12") (pinfunction "12_12") (pintype "passive"))
    )
    (net (code "810") (name "Net-(IC51-Pad4)") (class "Default")
      (node (ref "IC51") (pin "4") (pinfunction "4_4") (pintype "passive"))
      (node (ref "SV101") (pin "10") (pinfunction "10_10") (pintype "passive"))
      (node (ref "SV101") (pin "9") (pinfunction "9_9") (pintype "passive"))
    )
    (net (code "811") (name "Net-(IC51-Pad5)") (class "Default")
      (node (ref "IC51") (pin "5") (pinfunction "5_5") (pintype "passive"))
      (node (ref "SV101") (pin "7") (pinfunction "7_7") (pintype "passive"))
      (node (ref "SV101") (pin "8") (pinfunction "8_8") (pintype "passive"))
    )
    (net (code "812") (name "Net-(IC51-Pad6)") (class "Default")
      (node (ref "IC51") (pin "6") (pinfunction "6_6") (pintype "passive"))
      (node (ref "SV101") (pin "5") (pinfunction "5_5") (pintype "passive"))
      (node (ref "SV101") (pin "6") (pinfunction "6_6") (pintype "passive"))
    )
    (net (code "813") (name "Net-(IC51-Pad7)") (class "Default")
      (node (ref "IC51") (pin "7") (pinfunction "7_7") (pintype "passive"))
      (node (ref "SV101") (pin "3") (pinfunction "3_3") (pintype "passive"))
      (node (ref "SV101") (pin "4") (pinfunction "4_4") (pintype "passive"))
    )
    (net (code "814") (name "Net-(IC51-Pad8)") (class "Default")
      (node (ref "IC51") (pin "8") (pinfunction "8_8") (pintype "passive"))
      (node (ref "SV101") (pin "1") (pinfunction "1_1") (pintype "passive"))
      (node (ref "SV101") (pin "2") (pinfunction "2_2") (pintype "passive"))
    )
    (net (code "815") (name "Net-(IC51-Pad9)") (class "Default")
      (node (ref "IC51") (pin "9") (pinfunction "9_9") (pintype "passive"))
      (node (ref "SV102") (pin "1") (pinfunction "1_1") (pintype "passive"))
      (node (ref "SV102") (pin "2") (pinfunction "2_2") (pintype "passive"))
    )
    (net (code "816") (name "Net-(IC51-Pad10)") (class "Default")
      (node (ref "IC51") (pin "10") (pinfunction "10_10") (pintype "passive"))
      (node (ref "SV102") (pin "3") (pinfunction "3_3") (pintype "passive"))
      (node (ref "SV102") (pin "4") (pinfunction "4_4") (pintype "passive"))
    )
    (net (code "817") (name "Net-(IC51-Pad11)") (class "Default")
      (node (ref "IC51") (pin "11") (pinfunction "11_11") (pintype "passive"))
      (node (ref "SV102") (pin "5") (pinfunction "5_5") (pintype "passive"))
      (node (ref "SV102") (pin "6") (pinfunction "6_6") (pintype "passive"))
    )
    (net (code "818") (name "Net-(IC51-Pad12)") (class "Default")
      (node (ref "IC51") (pin "12") (pinfunction "12_12") (pintype "passive"))
      (node (ref "SV102") (pin "7") (pinfunction "7_7") (pintype "passive"))
      (node (ref "SV102") (pin "8") (pinfunction "8_8") (pintype "passive"))
    )
    (net (code "819") (name "Net-(IC51-Pad13)") (class "Default")
      (node (ref "IC51") (pin "13") (pinfunction "13_13") (pintype "passive"))
      (node (ref "SV102") (pin "10") (pinfunction "10_10") (pintype "passive"))
      (node (ref "SV102") (pin "9") (pinfunction "9_9") (pintype "passive"))
    )
    (net (code "820") (name "Net-(IC51-Pad14)") (class "Default")
      (node (ref "IC51") (pin "14") (pinfunction "14_14") (pintype "passive"))
      (node (ref "SV102") (pin "11") (pinfunction "11_11") (pintype "passive"))
      (node (ref "SV102") (pin "12") (pinfunction "12_12") (pintype "passive"))
    )
    (net (code "821") (name "Net-(IC51-Pad15)") (class "Default")
      (node (ref "IC51") (pin "15") (pinfunction "15_15") (pintype "passive"))
      (node (ref "SV102") (pin "13") (pinfunction "13_13") (pintype "passive"))
      (node (ref "SV102") (pin "14") (pinfunction "14_14") (pintype "passive"))
    )
    (net (code "822") (name "Net-(IC51-Pad16)") (class "Default")
      (node (ref "IC51") (pin "16") (pinfunction "16_16") (pintype "passive"))
      (node (ref "SV102") (pin "15") (pinfunction "15_15") (pintype "passive"))
      (node (ref "SV102") (pin "16") (pinfunction "16_16") (pintype "passive"))
    )
    (net (code "823") (name "Net-(IC52-Pad1)") (class "Default")
      (node (ref "IC52") (pin "1") (pinfunction "1_1") (pintype "passive"))
      (node (ref "SV103") (pin "15") (pinfunction "15_15") (pintype "passive"))
      (node (ref "SV103") (pin "16") (pinfunction "16_16") (pintype "passive"))
    )
    (net (code "824") (name "Net-(IC52-Pad2)") (class "Default")
      (node (ref "IC52") (pin "2") (pinfunction "2_2") (pintype "passive"))
      (node (ref "SV103") (pin "13") (pinfunction "13_13") (pintype "passive"))
      (node (ref "SV103") (pin "14") (pinfunction "14_14") (pintype "passive"))
    )
    (net (code "825") (name "Net-(IC52-Pad3)") (class "Default")
      (node (ref "IC52") (pin "3") (pinfunction "3_3") (pintype "passive"))
      (node (ref "SV103") (pin "11") (pinfunction "11_11") (pintype "passive"))
      (node (ref "SV103") (pin "12") (pinfunction "12_12") (pintype "passive"))
    )
    (net (code "826") (name "Net-(IC52-Pad4)") (class "Default")
      (node (ref "IC52") (pin "4") (pinfunction "4_4") (pintype "passive"))
      (node (ref "SV103") (pin "10") (pinfunction "10_10") (pintype "passive"))
      (node (ref "SV103") (pin "9") (pinfunction "9_9") (pintype "passive"))
    )
    (net (code "827") (name "Net-(IC52-Pad5)") (class "Default")
      (node (ref "IC52") (pin "5") (pinfunction "5_5") (pintype "passive"))
      (node (ref "SV103") (pin "7") (pinfunction "7_7") (pintype "passive"))
      (node (ref "SV103") (pin "8") (pinfunction "8_8") (pintype "passive"))
    )
    (net (code "828") (name "Net-(IC52-Pad6)") (class "Default")
      (node (ref "IC52") (pin "6") (pinfunction "6_6") (pintype "passive"))
      (node (ref "SV103") (pin "5") (pinfunction "5_5") (pintype "passive"))
      (node (ref "SV103") (pin "6") (pinfunction "6_6") (pintype "passive"))
    )
    (net (code "829") (name "Net-(IC52-Pad7)") (class "Default")
      (node (ref "IC52") (pin "7") (pinfunction "7_7") (pintype "passive"))
      (node (ref "SV103") (pin "3") (pinfunction "3_3") (pintype "passive"))
      (node (ref "SV103") (pin "4") (pinfunction "4_4") (pintype "passive"))
    )
    (net (code "830") (name "Net-(IC52-Pad8)") (class "Default")
      (node (ref "IC52") (pin "8") (pinfunction "8_8") (pintype "passive"))
      (node (ref "SV103") (pin "1") (pinfunction "1_1") (pintype "passive"))
      (node (ref "SV103") (pin "2") (pinfunction "2_2") (pintype "passive"))
    )
    (net (code "831") (name "Net-(IC52-Pad9)") (class "Default")
      (node (ref "IC52") (pin "9") (pinfunction "9_9") (pintype "passive"))
      (node (ref "SV104") (pin "1") (pinfunction "1_1") (pintype "passive"))
      (node (ref "SV104") (pin "2") (pinfunction "2_2") (pintype "passive"))
    )
    (net (code "832") (name "Net-(IC52-Pad10)") (class "Default")
      (node (ref "IC52") (pin "10") (pinfunction "10_10") (pintype "passive"))
      (node (ref "SV104") (pin "3") (pinfunction "3_3") (pintype "passive"))
      (node (ref "SV104") (pin "4") (pinfunction "4_4") (pintype "passive"))
    )
    (net (code "833") (name "Net-(IC52-Pad11)") (class "Default")
      (node (ref "IC52") (pin "11") (pinfunction "11_11") (pintype "passive"))
      (node (ref "SV104") (pin "5") (pinfunction "5_5") (pintype "passive"))
      (node (ref "SV104") (pin "6") (pinfunction "6_6") (pintype "passive"))
    )
    (net (code "834") (name "Net-(IC52-Pad12)") (class "Default")
      (node (ref "IC52") (pin "12") (pinfunction "12_12") (pintype "passive"))
      (node (ref "SV104") (pin "7") (pinfunction "7_7") (pintype "passive"))
      (node (ref "SV104") (pin "8") (pinfunction "8_8") (pintype "passive"))
    )
    (net (code "835") (name "Net-(IC52-Pad13)") (class "Default")
      (node (ref "IC52") (pin "13") (pinfunction "13_13") (pintype "passive"))
      (node (ref "SV104") (pin "10") (pinfunction "10_10") (pintype "passive"))
      (node (ref "SV104") (pin "9") (pinfunction "9_9") (pintype "passive"))
    )
    (net (code "836") (name "Net-(IC52-Pad14)") (class "Default")
      (node (ref "IC52") (pin "14") (pinfunction "14_14") (pintype "passive"))
      (node (ref "SV104") (pin "11") (pinfunction "11_11") (pintype "passive"))
      (node (ref "SV104") (pin "12") (pinfunction "12_12") (pintype "passive"))
    )
    (net (code "837") (name "Net-(IC52-Pad15)") (class "Default")
      (node (ref "IC52") (pin "15") (pinfunction "15_15") (pintype "passive"))
      (node (ref "SV104") (pin "13") (pinfunction "13_13") (pintype "passive"))
      (node (ref "SV104") (pin "14") (pinfunction "14_14") (pintype "passive"))
    )
    (net (code "838") (name "Net-(IC52-Pad16)") (class "Default")
      (node (ref "IC52") (pin "16") (pinfunction "16_16") (pintype "passive"))
      (node (ref "SV104") (pin "15") (pinfunction "15_15") (pintype "passive"))
      (node (ref "SV104") (pin "16") (pinfunction "16_16") (pintype "passive"))
    )
    (net (code "839") (name "Net-(IC53-Pad1)") (class "Default")
      (node (ref "IC53") (pin "1") (pinfunction "1_1") (pintype "passive"))
      (node (ref "SV105") (pin "15") (pinfunction "15_15") (pintype "passive"))
      (node (ref "SV105") (pin "16") (pinfunction "16_16") (pintype "passive"))
    )
    (net (code "840") (name "Net-(IC53-Pad2)") (class "Default")
      (node (ref "IC53") (pin "2") (pinfunction "2_2") (pintype "passive"))
      (node (ref "SV105") (pin "13") (pinfunction "13_13") (pintype "passive"))
      (node (ref "SV105") (pin "14") (pinfunction "14_14") (pintype "passive"))
    )
    (net (code "841") (name "Net-(IC53-Pad3)") (class "Default")
      (node (ref "IC53") (pin "3") (pinfunction "3_3") (pintype "passive"))
      (node (ref "SV105") (pin "11") (pinfunction "11_11") (pintype "passive"))
      (node (ref "SV105") (pin "12") (pinfunction "12_12") (pintype "passive"))
    )
    (net (code "842") (name "Net-(IC53-Pad4)") (class "Default")
      (node (ref "IC53") (pin "4") (pinfunction "4_4") (pintype "passive"))
      (node (ref "SV105") (pin "10") (pinfunction "10_10") (pintype "passive"))
      (node (ref "SV105") (pin "9") (pinfunction "9_9") (pintype "passive"))
    )
    (net (code "843") (name "Net-(IC53-Pad5)") (class "Default")
      (node (ref "IC53") (pin "5") (pinfunction "5_5") (pintype "passive"))
      (node (ref "SV105") (pin "7") (pinfunction "7_7") (pintype "passive"))
      (node (ref "SV105") (pin "8") (pinfunction "8_8") (pintype "passive"))
    )
    (net (code "844") (name "Net-(IC53-Pad6)") (class "Default")
      (node (ref "IC53") (pin "6") (pinfunction "6_6") (pintype "passive"))
      (node (ref "SV105") (pin "5") (pinfunction "5_5") (pintype "passive"))
      (node (ref "SV105") (pin "6") (pinfunction "6_6") (pintype "passive"))
    )
    (net (code "845") (name "Net-(IC53-Pad7)") (class "Default")
      (node (ref "IC53") (pin "7") (pinfunction "7_7") (pintype "passive"))
      (node (ref "SV105") (pin "3") (pinfunction "3_3") (pintype "passive"))
      (node (ref "SV105") (pin "4") (pinfunction "4_4") (pintype "passive"))
    )
    (net (code "846") (name "Net-(IC53-Pad8)") (class "Default")
      (node (ref "IC53") (pin "8") (pinfunction "8_8") (pintype "passive"))
      (node (ref "SV105") (pin "1") (pinfunction "1_1") (pintype "passive"))
      (node (ref "SV105") (pin "2") (pinfunction "2_2") (pintype "passive"))
    )
    (net (code "847") (name "Net-(IC53-Pad9)") (class "Default")
      (node (ref "IC53") (pin "9") (pinfunction "9_9") (pintype "passive"))
      (node (ref "SV106") (pin "1") (pinfunction "1_1") (pintype "passive"))
      (node (ref "SV106") (pin "2") (pinfunction "2_2") (pintype "passive"))
    )
    (net (code "848") (name "Net-(IC53-Pad10)") (class "Default")
      (node (ref "IC53") (pin "10") (pinfunction "10_10") (pintype "passive"))
      (node (ref "SV106") (pin "3") (pinfunction "3_3") (pintype "passive"))
      (node (ref "SV106") (pin "4") (pinfunction "4_4") (pintype "passive"))
    )
    (net (code "849") (name "Net-(IC53-Pad11)") (class "Default")
      (node (ref "IC53") (pin "11") (pinfunction "11_11") (pintype "passive"))
      (node (ref "SV106") (pin "5") (pinfunction "5_5") (pintype "passive"))
      (node (ref "SV106") (pin "6") (pinfunction "6_6") (pintype "passive"))
    )
    (net (code "850") (name "Net-(IC53-Pad12)") (class "Default")
      (node (ref "IC53") (pin "12") (pinfunction "12_12") (pintype "passive"))
      (node (ref "SV106") (pin "7") (pinfunction "7_7") (pintype "passive"))
      (node (ref "SV106") (pin "8") (pinfunction "8_8") (pintype "passive"))
    )
    (net (code "851") (name "Net-(IC53-Pad13)") (class "Default")
      (node (ref "IC53") (pin "13") (pinfunction "13_13") (pintype "passive"))
      (node (ref "SV106") (pin "10") (pinfunction "10_10") (pintype "passive"))
      (node (ref "SV106") (pin "9") (pinfunction "9_9") (pintype "passive"))
    )
    (net (code "852") (name "Net-(IC53-Pad14)") (class "Default")
      (node (ref "IC53") (pin "14") (pinfunction "14_14") (pintype "passive"))
      (node (ref "SV106") (pin "11") (pinfunction "11_11") (pintype "passive"))
      (node (ref "SV106") (pin "12") (pinfunction "12_12") (pintype "passive"))
    )
    (net (code "853") (name "Net-(IC53-Pad15)") (class "Default")
      (node (ref "IC53") (pin "15") (pinfunction "15_15") (pintype "passive"))
      (node (ref "SV106") (pin "13") (pinfunction "13_13") (pintype "passive"))
      (node (ref "SV106") (pin "14") (pinfunction "14_14") (pintype "passive"))
    )
    (net (code "854") (name "Net-(IC53-Pad16)") (class "Default")
      (node (ref "IC53") (pin "16") (pinfunction "16_16") (pintype "passive"))
      (node (ref "SV106") (pin "15") (pinfunction "15_15") (pintype "passive"))
      (node (ref "SV106") (pin "16") (pinfunction "16_16") (pintype "passive"))
    )
    (net (code "855") (name "Net-(IC54-Pad1)") (class "Default")
      (node (ref "IC54") (pin "1") (pinfunction "1_1") (pintype "passive"))
      (node (ref "SV107") (pin "15") (pinfunction "15_15") (pintype "passive"))
      (node (ref "SV107") (pin "16") (pinfunction "16_16") (pintype "passive"))
    )
    (net (code "856") (name "Net-(IC54-Pad2)") (class "Default")
      (node (ref "IC54") (pin "2") (pinfunction "2_2") (pintype "passive"))
      (node (ref "SV107") (pin "13") (pinfunction "13_13") (pintype "passive"))
      (node (ref "SV107") (pin "14") (pinfunction "14_14") (pintype "passive"))
    )
    (net (code "857") (name "Net-(IC54-Pad3)") (class "Default")
      (node (ref "IC54") (pin "3") (pinfunction "3_3") (pintype "passive"))
      (node (ref "SV107") (pin "11") (pinfunction "11_11") (pintype "passive"))
      (node (ref "SV107") (pin "12") (pinfunction "12_12") (pintype "passive"))
    )
    (net (code "858") (name "Net-(IC54-Pad4)") (class "Default")
      (node (ref "IC54") (pin "4") (pinfunction "4_4") (pintype "passive"))
      (node (ref "SV107") (pin "10") (pinfunction "10_10") (pintype "passive"))
      (node (ref "SV107") (pin "9") (pinfunction "9_9") (pintype "passive"))
    )
    (net (code "859") (name "Net-(IC54-Pad5)") (class "Default")
      (node (ref "IC54") (pin "5") (pinfunction "5_5") (pintype "passive"))
      (node (ref "SV107") (pin "7") (pinfunction "7_7") (pintype "passive"))
      (node (ref "SV107") (pin "8") (pinfunction "8_8") (pintype "passive"))
    )
    (net (code "860") (name "Net-(IC54-Pad6)") (class "Default")
      (node (ref "IC54") (pin "6") (pinfunction "6_6") (pintype "passive"))
      (node (ref "SV107") (pin "5") (pinfunction "5_5") (pintype "passive"))
      (node (ref "SV107") (pin "6") (pinfunction "6_6") (pintype "passive"))
    )
    (net (code "861") (name "Net-(IC54-Pad7)") (class "Default")
      (node (ref "IC54") (pin "7") (pinfunction "7_7") (pintype "passive"))
      (node (ref "SV107") (pin "3") (pinfunction "3_3") (pintype "passive"))
      (node (ref "SV107") (pin "4") (pinfunction "4_4") (pintype "passive"))
    )
    (net (code "862") (name "Net-(IC54-Pad8)") (class "Default")
      (node (ref "IC54") (pin "8") (pinfunction "8_8") (pintype "passive"))
      (node (ref "SV107") (pin "1") (pinfunction "1_1") (pintype "passive"))
      (node (ref "SV107") (pin "2") (pinfunction "2_2") (pintype "passive"))
    )
    (net (code "863") (name "Net-(IC54-Pad9)") (class "Default")
      (node (ref "IC54") (pin "9") (pinfunction "9_9") (pintype "passive"))
      (node (ref "SV108") (pin "1") (pinfunction "1_1") (pintype "passive"))
      (node (ref "SV108") (pin "2") (pinfunction "2_2") (pintype "passive"))
    )
    (net (code "864") (name "Net-(IC54-Pad10)") (class "Default")
      (node (ref "IC54") (pin "10") (pinfunction "10_10") (pintype "passive"))
      (node (ref "SV108") (pin "3") (pinfunction "3_3") (pintype "passive"))
      (node (ref "SV108") (pin "4") (pinfunction "4_4") (pintype "passive"))
    )
    (net (code "865") (name "Net-(IC54-Pad11)") (class "Default")
      (node (ref "IC54") (pin "11") (pinfunction "11_11") (pintype "passive"))
      (node (ref "SV108") (pin "5") (pinfunction "5_5") (pintype "passive"))
      (node (ref "SV108") (pin "6") (pinfunction "6_6") (pintype "passive"))
    )
    (net (code "866") (name "Net-(IC54-Pad12)") (class "Default")
      (node (ref "IC54") (pin "12") (pinfunction "12_12") (pintype "passive"))
      (node (ref "SV108") (pin "7") (pinfunction "7_7") (pintype "passive"))
      (node (ref "SV108") (pin "8") (pinfunction "8_8") (pintype "passive"))
    )
    (net (code "867") (name "Net-(IC54-Pad13)") (class "Default")
      (node (ref "IC54") (pin "13") (pinfunction "13_13") (pintype "passive"))
      (node (ref "SV108") (pin "10") (pinfunction "10_10") (pintype "passive"))
      (node (ref "SV108") (pin "9") (pinfunction "9_9") (pintype "passive"))
    )
    (net (code "868") (name "Net-(IC54-Pad14)") (class "Default")
      (node (ref "IC54") (pin "14") (pinfunction "14_14") (pintype "passive"))
      (node (ref "SV108") (pin "11") (pinfunction "11_11") (pintype "passive"))
      (node (ref "SV108") (pin "12") (pinfunction "12_12") (pintype "passive"))
    )
    (net (code "869") (name "Net-(IC54-Pad15)") (class "Default")
      (node (ref "IC54") (pin "15") (pinfunction "15_15") (pintype "passive"))
      (node (ref "SV108") (pin "13") (pinfunction "13_13") (pintype "passive"))
      (node (ref "SV108") (pin "14") (pinfunction "14_14") (pintype "passive"))
    )
    (net (code "870") (name "Net-(IC54-Pad16)") (class "Default")
      (node (ref "IC54") (pin "16") (pinfunction "16_16") (pintype "passive"))
      (node (ref "SV108") (pin "15") (pinfunction "15_15") (pintype "passive"))
      (node (ref "SV108") (pin "16") (pinfunction "16_16") (pintype "passive"))
    )
    (net (code "871") (name "Net-(IC55-Pad1)") (class "Default")
      (node (ref "IC55") (pin "1") (pinfunction "1_1") (pintype "passive"))
      (node (ref "SV109") (pin "15") (pinfunction "15_15") (pintype "passive"))
      (node (ref "SV109") (pin "16") (pinfunction "16_16") (pintype "passive"))
    )
    (net (code "872") (name "Net-(IC55-Pad2)") (class "Default")
      (node (ref "IC55") (pin "2") (pinfunction "2_2") (pintype "passive"))
      (node (ref "SV109") (pin "13") (pinfunction "13_13") (pintype "passive"))
      (node (ref "SV109") (pin "14") (pinfunction "14_14") (pintype "passive"))
    )
    (net (code "873") (name "Net-(IC55-Pad3)") (class "Default")
      (node (ref "IC55") (pin "3") (pinfunction "3_3") (pintype "passive"))
      (node (ref "SV109") (pin "11") (pinfunction "11_11") (pintype "passive"))
      (node (ref "SV109") (pin "12") (pinfunction "12_12") (pintype "passive"))
    )
    (net (code "874") (name "Net-(IC55-Pad4)") (class "Default")
      (node (ref "IC55") (pin "4") (pinfunction "4_4") (pintype "passive"))
      (node (ref "SV109") (pin "10") (pinfunction "10_10") (pintype "passive"))
      (node (ref "SV109") (pin "9") (pinfunction "9_9") (pintype "passive"))
    )
    (net (code "875") (name "Net-(IC55-Pad5)") (class "Default")
      (node (ref "IC55") (pin "5") (pinfunction "5_5") (pintype "passive"))
      (node (ref "SV109") (pin "7") (pinfunction "7_7") (pintype "passive"))
      (node (ref "SV109") (pin "8") (pinfunction "8_8") (pintype "passive"))
    )
    (net (code "876") (name "Net-(IC55-Pad6)") (class "Default")
      (node (ref "IC55") (pin "6") (pinfunction "6_6") (pintype "passive"))
      (node (ref "SV109") (pin "5") (pinfunction "5_5") (pintype "passive"))
      (node (ref "SV109") (pin "6") (pinfunction "6_6") (pintype "passive"))
    )
    (net (code "877") (name "Net-(IC55-Pad7)") (class "Default")
      (node (ref "IC55") (pin "7") (pinfunction "7_7") (pintype "passive"))
      (node (ref "SV109") (pin "3") (pinfunction "3_3") (pintype "passive"))
      (node (ref "SV109") (pin "4") (pinfunction "4_4") (pintype "passive"))
    )
    (net (code "878") (name "Net-(IC55-Pad8)") (class "Default")
      (node (ref "IC55") (pin "8") (pinfunction "8_8") (pintype "passive"))
      (node (ref "SV109") (pin "1") (pinfunction "1_1") (pintype "passive"))
      (node (ref "SV109") (pin "2") (pinfunction "2_2") (pintype "passive"))
    )
    (net (code "879") (name "Net-(IC55-Pad9)") (class "Default")
      (node (ref "IC55") (pin "9") (pinfunction "9_9") (pintype "passive"))
      (node (ref "SV110") (pin "1") (pinfunction "1_1") (pintype "passive"))
      (node (ref "SV110") (pin "2") (pinfunction "2_2") (pintype "passive"))
    )
    (net (code "880") (name "Net-(IC55-Pad10)") (class "Default")
      (node (ref "IC55") (pin "10") (pinfunction "10_10") (pintype "passive"))
      (node (ref "SV110") (pin "3") (pinfunction "3_3") (pintype "passive"))
      (node (ref "SV110") (pin "4") (pinfunction "4_4") (pintype "passive"))
    )
    (net (code "881") (name "Net-(IC55-Pad11)") (class "Default")
      (node (ref "IC55") (pin "11") (pinfunction "11_11") (pintype "passive"))
      (node (ref "SV110") (pin "5") (pinfunction "5_5") (pintype "passive"))
      (node (ref "SV110") (pin "6") (pinfunction "6_6") (pintype "passive"))
    )
    (net (code "882") (name "Net-(IC55-Pad12)") (class "Default")
      (node (ref "IC55") (pin "12") (pinfunction "12_12") (pintype "passive"))
      (node (ref "SV110") (pin "7") (pinfunction "7_7") (pintype "passive"))
      (node (ref "SV110") (pin "8") (pinfunction "8_8") (pintype "passive"))
    )
    (net (code "883") (name "Net-(IC55-Pad13)") (class "Default")
      (node (ref "IC55") (pin "13") (pinfunction "13_13") (pintype "passive"))
      (node (ref "SV110") (pin "10") (pinfunction "10_10") (pintype "passive"))
      (node (ref "SV110") (pin "9") (pinfunction "9_9") (pintype "passive"))
    )
    (net (code "884") (name "Net-(IC55-Pad14)") (class "Default")
      (node (ref "IC55") (pin "14") (pinfunction "14_14") (pintype "passive"))
      (node (ref "SV110") (pin "11") (pinfunction "11_11") (pintype "passive"))
      (node (ref "SV110") (pin "12") (pinfunction "12_12") (pintype "passive"))
    )
    (net (code "885") (name "Net-(IC55-Pad15)") (class "Default")
      (node (ref "IC55") (pin "15") (pinfunction "15_15") (pintype "passive"))
      (node (ref "SV110") (pin "13") (pinfunction "13_13") (pintype "passive"))
      (node (ref "SV110") (pin "14") (pinfunction "14_14") (pintype "passive"))
    )
    (net (code "886") (name "Net-(IC55-Pad16)") (class "Default")
      (node (ref "IC55") (pin "16") (pinfunction "16_16") (pintype "passive"))
      (node (ref "SV110") (pin "15") (pinfunction "15_15") (pintype "passive"))
      (node (ref "SV110") (pin "16") (pinfunction "16_16") (pintype "passive"))
    )
    (net (code "887") (name "Net-(IC56-Pad1)") (class "Default")
      (node (ref "IC56") (pin "1") (pinfunction "1_1") (pintype "passive"))
      (node (ref "SV111") (pin "15") (pinfunction "15_15") (pintype "passive"))
      (node (ref "SV111") (pin "16") (pinfunction "16_16") (pintype "passive"))
    )
    (net (code "888") (name "Net-(IC56-Pad2)") (class "Default")
      (node (ref "IC56") (pin "2") (pinfunction "2_2") (pintype "passive"))
      (node (ref "SV111") (pin "13") (pinfunction "13_13") (pintype "passive"))
      (node (ref "SV111") (pin "14") (pinfunction "14_14") (pintype "passive"))
    )
    (net (code "889") (name "Net-(IC56-Pad3)") (class "Default")
      (node (ref "IC56") (pin "3") (pinfunction "3_3") (pintype "passive"))
      (node (ref "SV111") (pin "11") (pinfunction "11_11") (pintype "passive"))
      (node (ref "SV111") (pin "12") (pinfunction "12_12") (pintype "passive"))
    )
    (net (code "890") (name "Net-(IC56-Pad4)") (class "Default")
      (node (ref "IC56") (pin "4") (pinfunction "4_4") (pintype "passive"))
      (node (ref "SV111") (pin "10") (pinfunction "10_10") (pintype "passive"))
      (node (ref "SV111") (pin "9") (pinfunction "9_9") (pintype "passive"))
    )
    (net (code "891") (name "Net-(IC56-Pad5)") (class "Default")
      (node (ref "IC56") (pin "5") (pinfunction "5_5") (pintype "passive"))
      (node (ref "SV111") (pin "7") (pinfunction "7_7") (pintype "passive"))
      (node (ref "SV111") (pin "8") (pinfunction "8_8") (pintype "passive"))
    )
    (net (code "892") (name "Net-(IC56-Pad6)") (class "Default")
      (node (ref "IC56") (pin "6") (pinfunction "6_6") (pintype "passive"))
      (node (ref "SV111") (pin "5") (pinfunction "5_5") (pintype "passive"))
      (node (ref "SV111") (pin "6") (pinfunction "6_6") (pintype "passive"))
    )
    (net (code "893") (name "Net-(IC56-Pad7)") (class "Default")
      (node (ref "IC56") (pin "7") (pinfunction "7_7") (pintype "passive"))
      (node (ref "SV111") (pin "3") (pinfunction "3_3") (pintype "passive"))
      (node (ref "SV111") (pin "4") (pinfunction "4_4") (pintype "passive"))
    )
    (net (code "894") (name "Net-(IC56-Pad8)") (class "Default")
      (node (ref "IC56") (pin "8") (pinfunction "8_8") (pintype "passive"))
      (node (ref "SV111") (pin "1") (pinfunction "1_1") (pintype "passive"))
      (node (ref "SV111") (pin "2") (pinfunction "2_2") (pintype "passive"))
    )
    (net (code "895") (name "Net-(IC56-Pad9)") (class "Default")
      (node (ref "IC56") (pin "9") (pinfunction "9_9") (pintype "passive"))
      (node (ref "SV112") (pin "1") (pinfunction "1_1") (pintype "passive"))
      (node (ref "SV112") (pin "2") (pinfunction "2_2") (pintype "passive"))
    )
    (net (code "896") (name "Net-(IC56-Pad10)") (class "Default")
      (node (ref "IC56") (pin "10") (pinfunction "10_10") (pintype "passive"))
      (node (ref "SV112") (pin "3") (pinfunction "3_3") (pintype "passive"))
      (node (ref "SV112") (pin "4") (pinfunction "4_4") (pintype "passive"))
    )
    (net (code "897") (name "Net-(IC56-Pad11)") (class "Default")
      (node (ref "IC56") (pin "11") (pinfunction "11_11") (pintype "passive"))
      (node (ref "SV112") (pin "5") (pinfunction "5_5") (pintype "passive"))
      (node (ref "SV112") (pin "6") (pinfunction "6_6") (pintype "passive"))
    )
    (net (code "898") (name "Net-(IC56-Pad12)") (class "Default")
      (node (ref "IC56") (pin "12") (pinfunction "12_12") (pintype "passive"))
      (node (ref "SV112") (pin "7") (pinfunction "7_7") (pintype "passive"))
      (node (ref "SV112") (pin "8") (pinfunction "8_8") (pintype "passive"))
    )
    (net (code "899") (name "Net-(IC56-Pad13)") (class "Default")
      (node (ref "IC56") (pin "13") (pinfunction "13_13") (pintype "passive"))
      (node (ref "SV112") (pin "10") (pinfunction "10_10") (pintype "passive"))
      (node (ref "SV112") (pin "9") (pinfunction "9_9") (pintype "passive"))
    )
    (net (code "900") (name "Net-(IC56-Pad14)") (class "Default")
      (node (ref "IC56") (pin "14") (pinfunction "14_14") (pintype "passive"))
      (node (ref "SV112") (pin "11") (pinfunction "11_11") (pintype "passive"))
      (node (ref "SV112") (pin "12") (pinfunction "12_12") (pintype "passive"))
    )
    (net (code "901") (name "Net-(IC56-Pad15)") (class "Default")
      (node (ref "IC56") (pin "15") (pinfunction "15_15") (pintype "passive"))
      (node (ref "SV112") (pin "13") (pinfunction "13_13") (pintype "passive"))
      (node (ref "SV112") (pin "14") (pinfunction "14_14") (pintype "passive"))
    )
    (net (code "902") (name "Net-(IC56-Pad16)") (class "Default")
      (node (ref "IC56") (pin "16") (pinfunction "16_16") (pintype "passive"))
      (node (ref "SV112") (pin "15") (pinfunction "15_15") (pintype "passive"))
      (node (ref "SV112") (pin "16") (pinfunction "16_16") (pintype "passive"))
    )
    (net (code "903") (name "Net-(IC57-Pad1)") (class "Default")
      (node (ref "IC57") (pin "1") (pinfunction "1_1") (pintype "passive"))
      (node (ref "SV113") (pin "15") (pinfunction "15_15") (pintype "passive"))
      (node (ref "SV113") (pin "16") (pinfunction "16_16") (pintype "passive"))
    )
    (net (code "904") (name "Net-(IC57-Pad2)") (class "Default")
      (node (ref "IC57") (pin "2") (pinfunction "2_2") (pintype "passive"))
      (node (ref "SV113") (pin "13") (pinfunction "13_13") (pintype "passive"))
      (node (ref "SV113") (pin "14") (pinfunction "14_14") (pintype "passive"))
    )
    (net (code "905") (name "Net-(IC57-Pad3)") (class "Default")
      (node (ref "IC57") (pin "3") (pinfunction "3_3") (pintype "passive"))
      (node (ref "SV113") (pin "11") (pinfunction "11_11") (pintype "passive"))
      (node (ref "SV113") (pin "12") (pinfunction "12_12") (pintype "passive"))
    )
    (net (code "906") (name "Net-(IC57-Pad4)") (class "Default")
      (node (ref "IC57") (pin "4") (pinfunction "4_4") (pintype "passive"))
      (node (ref "SV113") (pin "10") (pinfunction "10_10") (pintype "passive"))
      (node (ref "SV113") (pin "9") (pinfunction "9_9") (pintype "passive"))
    )
    (net (code "907") (name "Net-(IC57-Pad5)") (class "Default")
      (node (ref "IC57") (pin "5") (pinfunction "5_5") (pintype "passive"))
      (node (ref "SV113") (pin "7") (pinfunction "7_7") (pintype "passive"))
      (node (ref "SV113") (pin "8") (pinfunction "8_8") (pintype "passive"))
    )
    (net (code "908") (name "Net-(IC57-Pad6)") (class "Default")
      (node (ref "IC57") (pin "6") (pinfunction "6_6") (pintype "passive"))
      (node (ref "SV113") (pin "5") (pinfunction "5_5") (pintype "passive"))
      (node (ref "SV113") (pin "6") (pinfunction "6_6") (pintype "passive"))
    )
    (net (code "909") (name "Net-(IC57-Pad7)") (class "Default")
      (node (ref "IC57") (pin "7") (pinfunction "7_7") (pintype "passive"))
      (node (ref "SV113") (pin "3") (pinfunction "3_3") (pintype "passive"))
      (node (ref "SV113") (pin "4") (pinfunction "4_4") (pintype "passive"))
    )
    (net (code "910") (name "Net-(IC57-Pad8)") (class "Default")
      (node (ref "IC57") (pin "8") (pinfunction "8_8") (pintype "passive"))
      (node (ref "SV113") (pin "1") (pinfunction "1_1") (pintype "passive"))
      (node (ref "SV113") (pin "2") (pinfunction "2_2") (pintype "passive"))
    )
    (net (code "911") (name "Net-(IC57-Pad9)") (class "Default")
      (node (ref "IC57") (pin "9") (pinfunction "9_9") (pintype "passive"))
      (node (ref "SV114") (pin "1") (pinfunction "1_1") (pintype "passive"))
      (node (ref "SV114") (pin "2") (pinfunction "2_2") (pintype "passive"))
    )
    (net (code "912") (name "Net-(IC57-Pad10)") (class "Default")
      (node (ref "IC57") (pin "10") (pinfunction "10_10") (pintype "passive"))
      (node (ref "SV114") (pin "3") (pinfunction "3_3") (pintype "passive"))
      (node (ref "SV114") (pin "4") (pinfunction "4_4") (pintype "passive"))
    )
    (net (code "913") (name "Net-(IC57-Pad11)") (class "Default")
      (node (ref "IC57") (pin "11") (pinfunction "11_11") (pintype "passive"))
      (node (ref "SV114") (pin "5") (pinfunction "5_5") (pintype "passive"))
      (node (ref "SV114") (pin "6") (pinfunction "6_6") (pintype "passive"))
    )
    (net (code "914") (name "Net-(IC57-Pad12)") (class "Default")
      (node (ref "IC57") (pin "12") (pinfunction "12_12") (pintype "passive"))
      (node (ref "SV114") (pin "7") (pinfunction "7_7") (pintype "passive"))
      (node (ref "SV114") (pin "8") (pinfunction "8_8") (pintype "passive"))
    )
    (net (code "915") (name "Net-(IC57-Pad13)") (class "Default")
      (node (ref "IC57") (pin "13") (pinfunction "13_13") (pintype "passive"))
      (node (ref "SV114") (pin "10") (pinfunction "10_10") (pintype "passive"))
      (node (ref "SV114") (pin "9") (pinfunction "9_9") (pintype "passive"))
    )
    (net (code "916") (name "Net-(IC57-Pad14)") (class "Default")
      (node (ref "IC57") (pin "14") (pinfunction "14_14") (pintype "passive"))
      (node (ref "SV114") (pin "11") (pinfunction "11_11") (pintype "passive"))
      (node (ref "SV114") (pin "12") (pinfunction "12_12") (pintype "passive"))
    )
    (net (code "917") (name "Net-(IC57-Pad15)") (class "Default")
      (node (ref "IC57") (pin "15") (pinfunction "15_15") (pintype "passive"))
      (node (ref "SV114") (pin "13") (pinfunction "13_13") (pintype "passive"))
      (node (ref "SV114") (pin "14") (pinfunction "14_14") (pintype "passive"))
    )
    (net (code "918") (name "Net-(IC57-Pad16)") (class "Default")
      (node (ref "IC57") (pin "16") (pinfunction "16_16") (pintype "passive"))
      (node (ref "SV114") (pin "15") (pinfunction "15_15") (pintype "passive"))
      (node (ref "SV114") (pin "16") (pinfunction "16_16") (pintype "passive"))
    )
    (net (code "919") (name "Net-(IC58-Pad1)") (class "Default")
      (node (ref "IC58") (pin "1") (pinfunction "1_1") (pintype "passive"))
      (node (ref "SV115") (pin "15") (pinfunction "15_15") (pintype "passive"))
      (node (ref "SV115") (pin "16") (pinfunction "16_16") (pintype "passive"))
    )
    (net (code "920") (name "Net-(IC58-Pad2)") (class "Default")
      (node (ref "IC58") (pin "2") (pinfunction "2_2") (pintype "passive"))
      (node (ref "SV115") (pin "13") (pinfunction "13_13") (pintype "passive"))
      (node (ref "SV115") (pin "14") (pinfunction "14_14") (pintype "passive"))
    )
    (net (code "921") (name "Net-(IC58-Pad3)") (class "Default")
      (node (ref "IC58") (pin "3") (pinfunction "3_3") (pintype "passive"))
      (node (ref "SV115") (pin "11") (pinfunction "11_11") (pintype "passive"))
      (node (ref "SV115") (pin "12") (pinfunction "12_12") (pintype "passive"))
    )
    (net (code "922") (name "Net-(IC58-Pad4)") (class "Default")
      (node (ref "IC58") (pin "4") (pinfunction "4_4") (pintype "passive"))
      (node (ref "SV115") (pin "10") (pinfunction "10_10") (pintype "passive"))
      (node (ref "SV115") (pin "9") (pinfunction "9_9") (pintype "passive"))
    )
    (net (code "923") (name "Net-(IC58-Pad5)") (class "Default")
      (node (ref "IC58") (pin "5") (pinfunction "5_5") (pintype "passive"))
      (node (ref "SV115") (pin "7") (pinfunction "7_7") (pintype "passive"))
      (node (ref "SV115") (pin "8") (pinfunction "8_8") (pintype "passive"))
    )
    (net (code "924") (name "Net-(IC58-Pad6)") (class "Default")
      (node (ref "IC58") (pin "6") (pinfunction "6_6") (pintype "passive"))
      (node (ref "SV115") (pin "5") (pinfunction "5_5") (pintype "passive"))
      (node (ref "SV115") (pin "6") (pinfunction "6_6") (pintype "passive"))
    )
    (net (code "925") (name "Net-(IC58-Pad7)") (class "Default")
      (node (ref "IC58") (pin "7") (pinfunction "7_7") (pintype "passive"))
      (node (ref "SV115") (pin "3") (pinfunction "3_3") (pintype "passive"))
      (node (ref "SV115") (pin "4") (pinfunction "4_4") (pintype "passive"))
    )
    (net (code "926") (name "Net-(IC58-Pad8)") (class "Default")
      (node (ref "IC58") (pin "8") (pinfunction "8_8") (pintype "passive"))
      (node (ref "SV115") (pin "1") (pinfunction "1_1") (pintype "passive"))
      (node (ref "SV115") (pin "2") (pinfunction "2_2") (pintype "passive"))
    )
    (net (code "927") (name "Net-(IC58-Pad9)") (class "Default")
      (node (ref "IC58") (pin "9") (pinfunction "9_9") (pintype "passive"))
      (node (ref "SV116") (pin "1") (pinfunction "1_1") (pintype "passive"))
      (node (ref "SV116") (pin "2") (pinfunction "2_2") (pintype "passive"))
    )
    (net (code "928") (name "Net-(IC58-Pad10)") (class "Default")
      (node (ref "IC58") (pin "10") (pinfunction "10_10") (pintype "passive"))
      (node (ref "SV116") (pin "3") (pinfunction "3_3") (pintype "passive"))
      (node (ref "SV116") (pin "4") (pinfunction "4_4") (pintype "passive"))
    )
    (net (code "929") (name "Net-(IC58-Pad11)") (class "Default")
      (node (ref "IC58") (pin "11") (pinfunction "11_11") (pintype "passive"))
      (node (ref "SV116") (pin "5") (pinfunction "5_5") (pintype "passive"))
      (node (ref "SV116") (pin "6") (pinfunction "6_6") (pintype "passive"))
    )
    (net (code "930") (name "Net-(IC58-Pad12)") (class "Default")
      (node (ref "IC58") (pin "12") (pinfunction "12_12") (pintype "passive"))
      (node (ref "SV116") (pin "7") (pinfunction "7_7") (pintype "passive"))
      (node (ref "SV116") (pin "8") (pinfunction "8_8") (pintype "passive"))
    )
    (net (code "931") (name "Net-(IC58-Pad13)") (class "Default")
      (node (ref "IC58") (pin "13") (pinfunction "13_13") (pintype "passive"))
      (node (ref "SV116") (pin "10") (pinfunction "10_10") (pintype "passive"))
      (node (ref "SV116") (pin "9") (pinfunction "9_9") (pintype "passive"))
    )
    (net (code "932") (name "Net-(IC58-Pad14)") (class "Default")
      (node (ref "IC58") (pin "14") (pinfunction "14_14") (pintype "passive"))
      (node (ref "SV116") (pin "11") (pinfunction "11_11") (pintype "passive"))
      (node (ref "SV116") (pin "12") (pinfunction "12_12") (pintype "passive"))
    )
    (net (code "933") (name "Net-(IC58-Pad15)") (class "Default")
      (node (ref "IC58") (pin "15") (pinfunction "15_15") (pintype "passive"))
      (node (ref "SV116") (pin "13") (pinfunction "13_13") (pintype "passive"))
      (node (ref "SV116") (pin "14") (pinfunction "14_14") (pintype "passive"))
    )
    (net (code "934") (name "Net-(IC58-Pad16)") (class "Default")
      (node (ref "IC58") (pin "16") (pinfunction "16_16") (pintype "passive"))
      (node (ref "SV116") (pin "15") (pinfunction "15_15") (pintype "passive"))
      (node (ref "SV116") (pin "16") (pinfunction "16_16") (pintype "passive"))
    )
    (net (code "935") (name "Net-(IC59-Pad1)") (class "Default")
      (node (ref "IC59") (pin "1") (pinfunction "1_1") (pintype "passive"))
      (node (ref "SV117") (pin "15") (pinfunction "15_15") (pintype "passive"))
      (node (ref "SV117") (pin "16") (pinfunction "16_16") (pintype "passive"))
    )
    (net (code "936") (name "Net-(IC59-Pad2)") (class "Default")
      (node (ref "IC59") (pin "2") (pinfunction "2_2") (pintype "passive"))
      (node (ref "SV117") (pin "13") (pinfunction "13_13") (pintype "passive"))
      (node (ref "SV117") (pin "14") (pinfunction "14_14") (pintype "passive"))
    )
    (net (code "937") (name "Net-(IC59-Pad3)") (class "Default")
      (node (ref "IC59") (pin "3") (pinfunction "3_3") (pintype "passive"))
      (node (ref "SV117") (pin "11") (pinfunction "11_11") (pintype "passive"))
      (node (ref "SV117") (pin "12") (pinfunction "12_12") (pintype "passive"))
    )
    (net (code "938") (name "Net-(IC59-Pad4)") (class "Default")
      (node (ref "IC59") (pin "4") (pinfunction "4_4") (pintype "passive"))
      (node (ref "SV117") (pin "10") (pinfunction "10_10") (pintype "passive"))
      (node (ref "SV117") (pin "9") (pinfunction "9_9") (pintype "passive"))
    )
    (net (code "939") (name "Net-(IC59-Pad5)") (class "Default")
      (node (ref "IC59") (pin "5") (pinfunction "5_5") (pintype "passive"))
      (node (ref "SV117") (pin "7") (pinfunction "7_7") (pintype "passive"))
      (node (ref "SV117") (pin "8") (pinfunction "8_8") (pintype "passive"))
    )
    (net (code "940") (name "Net-(IC59-Pad6)") (class "Default")
      (node (ref "IC59") (pin "6") (pinfunction "6_6") (pintype "passive"))
      (node (ref "SV117") (pin "5") (pinfunction "5_5") (pintype "passive"))
      (node (ref "SV117") (pin "6") (pinfunction "6_6") (pintype "passive"))
    )
    (net (code "941") (name "Net-(IC59-Pad7)") (class "Default")
      (node (ref "IC59") (pin "7") (pinfunction "7_7") (pintype "passive"))
      (node (ref "SV117") (pin "3") (pinfunction "3_3") (pintype "passive"))
      (node (ref "SV117") (pin "4") (pinfunction "4_4") (pintype "passive"))
    )
    (net (code "942") (name "Net-(IC59-Pad8)") (class "Default")
      (node (ref "IC59") (pin "8") (pinfunction "8_8") (pintype "passive"))
      (node (ref "SV117") (pin "1") (pinfunction "1_1") (pintype "passive"))
      (node (ref "SV117") (pin "2") (pinfunction "2_2") (pintype "passive"))
    )
    (net (code "943") (name "Net-(IC59-Pad9)") (class "Default")
      (node (ref "IC59") (pin "9") (pinfunction "9_9") (pintype "passive"))
      (node (ref "SV118") (pin "1") (pinfunction "1_1") (pintype "passive"))
      (node (ref "SV118") (pin "2") (pinfunction "2_2") (pintype "passive"))
    )
    (net (code "944") (name "Net-(IC59-Pad10)") (class "Default")
      (node (ref "IC59") (pin "10") (pinfunction "10_10") (pintype "passive"))
      (node (ref "SV118") (pin "3") (pinfunction "3_3") (pintype "passive"))
      (node (ref "SV118") (pin "4") (pinfunction "4_4") (pintype "passive"))
    )
    (net (code "945") (name "Net-(IC59-Pad11)") (class "Default")
      (node (ref "IC59") (pin "11") (pinfunction "11_11") (pintype "passive"))
      (node (ref "SV118") (pin "5") (pinfunction "5_5") (pintype "passive"))
      (node (ref "SV118") (pin "6") (pinfunction "6_6") (pintype "passive"))
    )
    (net (code "946") (name "Net-(IC59-Pad12)") (class "Default")
      (node (ref "IC59") (pin "12") (pinfunction "12_12") (pintype "passive"))
      (node (ref "SV118") (pin "7") (pinfunction "7_7") (pintype "passive"))
      (node (ref "SV118") (pin "8") (pinfunction "8_8") (pintype "passive"))
    )
    (net (code "947") (name "Net-(IC59-Pad13)") (class "Default")
      (node (ref "IC59") (pin "13") (pinfunction "13_13") (pintype "passive"))
      (node (ref "SV118") (pin "10") (pinfunction "10_10") (pintype "passive"))
      (node (ref "SV118") (pin "9") (pinfunction "9_9") (pintype "passive"))
    )
    (net (code "948") (name "Net-(IC59-Pad14)") (class "Default")
      (node (ref "IC59") (pin "14") (pinfunction "14_14") (pintype "passive"))
      (node (ref "SV118") (pin "11") (pinfunction "11_11") (pintype "passive"))
      (node (ref "SV118") (pin "12") (pinfunction "12_12") (pintype "passive"))
    )
    (net (code "949") (name "Net-(IC59-Pad15)") (class "Default")
      (node (ref "IC59") (pin "15") (pinfunction "15_15") (pintype "passive"))
      (node (ref "SV118") (pin "13") (pinfunction "13_13") (pintype "passive"))
      (node (ref "SV118") (pin "14") (pinfunction "14_14") (pintype "passive"))
    )
    (net (code "950") (name "Net-(IC59-Pad16)") (class "Default")
      (node (ref "IC59") (pin "16") (pinfunction "16_16") (pintype "passive"))
      (node (ref "SV118") (pin "15") (pinfunction "15_15") (pintype "passive"))
      (node (ref "SV118") (pin "16") (pinfunction "16_16") (pintype "passive"))
    )
    (net (code "951") (name "Net-(IC60-Pad1)") (class "Default")
      (node (ref "IC60") (pin "1") (pinfunction "1_1") (pintype "passive"))
      (node (ref "SV119") (pin "15") (pinfunction "15_15") (pintype "passive"))
      (node (ref "SV119") (pin "16") (pinfunction "16_16") (pintype "passive"))
    )
    (net (code "952") (name "Net-(IC60-Pad2)") (class "Default")
      (node (ref "IC60") (pin "2") (pinfunction "2_2") (pintype "passive"))
      (node (ref "SV119") (pin "13") (pinfunction "13_13") (pintype "passive"))
      (node (ref "SV119") (pin "14") (pinfunction "14_14") (pintype "passive"))
    )
    (net (code "953") (name "Net-(IC60-Pad3)") (class "Default")
      (node (ref "IC60") (pin "3") (pinfunction "3_3") (pintype "passive"))
      (node (ref "SV119") (pin "11") (pinfunction "11_11") (pintype "passive"))
      (node (ref "SV119") (pin "12") (pinfunction "12_12") (pintype "passive"))
    )
    (net (code "954") (name "Net-(IC60-Pad4)") (class "Default")
      (node (ref "IC60") (pin "4") (pinfunction "4_4") (pintype "passive"))
      (node (ref "SV119") (pin "10") (pinfunction "10_10") (pintype "passive"))
      (node (ref "SV119") (pin "9") (pinfunction "9_9") (pintype "passive"))
    )
    (net (code "955") (name "Net-(IC60-Pad5)") (class "Default")
      (node (ref "IC60") (pin "5") (pinfunction "5_5") (pintype "passive"))
      (node (ref "SV119") (pin "7") (pinfunction "7_7") (pintype "passive"))
      (node (ref "SV119") (pin "8") (pinfunction "8_8") (pintype "passive"))
    )
    (net (code "956") (name "Net-(IC60-Pad6)") (class "Default")
      (node (ref "IC60") (pin "6") (pinfunction "6_6") (pintype "passive"))
      (node (ref "SV119") (pin "5") (pinfunction "5_5") (pintype "passive"))
      (node (ref "SV119") (pin "6") (pinfunction "6_6") (pintype "passive"))
    )
    (net (code "957") (name "Net-(IC60-Pad7)") (class "Default")
      (node (ref "IC60") (pin "7") (pinfunction "7_7") (pintype "passive"))
      (node (ref "SV119") (pin "3") (pinfunction "3_3") (pintype "passive"))
      (node (ref "SV119") (pin "4") (pinfunction "4_4") (pintype "passive"))
    )
    (net (code "958") (name "Net-(IC60-Pad8)") (class "Default")
      (node (ref "IC60") (pin "8") (pinfunction "8_8") (pintype "passive"))
      (node (ref "SV119") (pin "1") (pinfunction "1_1") (pintype "passive"))
      (node (ref "SV119") (pin "2") (pinfunction "2_2") (pintype "passive"))
    )
    (net (code "959") (name "Net-(IC60-Pad9)") (class "Default")
      (node (ref "IC60") (pin "9") (pinfunction "9_9") (pintype "passive"))
      (node (ref "SV120") (pin "1") (pinfunction "1_1") (pintype "passive"))
      (node (ref "SV120") (pin "2") (pinfunction "2_2") (pintype "passive"))
    )
    (net (code "960") (name "Net-(IC60-Pad10)") (class "Default")
      (node (ref "IC60") (pin "10") (pinfunction "10_10") (pintype "passive"))
      (node (ref "SV120") (pin "3") (pinfunction "3_3") (pintype "passive"))
      (node (ref "SV120") (pin "4") (pinfunction "4_4") (pintype "passive"))
    )
    (net (code "961") (name "Net-(IC60-Pad11)") (class "Default")
      (node (ref "IC60") (pin "11") (pinfunction "11_11") (pintype "passive"))
      (node (ref "SV120") (pin "5") (pinfunction "5_5") (pintype "passive"))
      (node (ref "SV120") (pin "6") (pinfunction "6_6") (pintype "passive"))
    )
    (net (code "962") (name "Net-(IC60-Pad12)") (class "Default")
      (node (ref "IC60") (pin "12") (pinfunction "12_12") (pintype "passive"))
      (node (ref "SV120") (pin "7") (pinfunction "7_7") (pintype "passive"))
      (node (ref "SV120") (pin "8") (pinfunction "8_8") (pintype "passive"))
    )
    (net (code "963") (name "Net-(IC60-Pad13)") (class "Default")
      (node (ref "IC60") (pin "13") (pinfunction "13_13") (pintype "passive"))
      (node (ref "SV120") (pin "10") (pinfunction "10_10") (pintype "passive"))
      (node (ref "SV120") (pin "9") (pinfunction "9_9") (pintype "passive"))
    )
    (net (code "964") (name "Net-(IC60-Pad14)") (class "Default")
      (node (ref "IC60") (pin "14") (pinfunction "14_14") (pintype "passive"))
      (node (ref "SV120") (pin "11") (pinfunction "11_11") (pintype "passive"))
      (node (ref "SV120") (pin "12") (pinfunction "12_12") (pintype "passive"))
    )
    (net (code "965") (name "Net-(IC60-Pad15)") (class "Default")
      (node (ref "IC60") (pin "15") (pinfunction "15_15") (pintype "passive"))
      (node (ref "SV120") (pin "13") (pinfunction "13_13") (pintype "passive"))
      (node (ref "SV120") (pin "14") (pinfunction "14_14") (pintype "passive"))
    )
    (net (code "966") (name "Net-(IC60-Pad16)") (class "Default")
      (node (ref "IC60") (pin "16") (pinfunction "16_16") (pintype "passive"))
      (node (ref "SV120") (pin "15") (pinfunction "15_15") (pintype "passive"))
      (node (ref "SV120") (pin "16") (pinfunction "16_16") (pintype "passive"))
    )
    (net (code "967") (name "Net-(IC61-Pad1)") (class "Default")
      (node (ref "IC61") (pin "1") (pinfunction "1_1") (pintype "passive"))
      (node (ref "SV130") (pin "15") (pinfunction "15_15") (pintype "passive"))
      (node (ref "SV130") (pin "16") (pinfunction "16_16") (pintype "passive"))
      (node (ref "SV131") (pin "15") (pinfunction "15_15") (pintype "passive"))
      (node (ref "SV131") (pin "16") (pinfunction "16_16") (pintype "passive"))
    )
    (net (code "968") (name "Net-(IC61-Pad2)") (class "Default")
      (node (ref "IC61") (pin "2") (pinfunction "2_2") (pintype "passive"))
      (node (ref "SV130") (pin "13") (pinfunction "13_13") (pintype "passive"))
      (node (ref "SV130") (pin "14") (pinfunction "14_14") (pintype "passive"))
      (node (ref "SV131") (pin "13") (pinfunction "13_13") (pintype "passive"))
      (node (ref "SV131") (pin "14") (pinfunction "14_14") (pintype "passive"))
    )
    (net (code "969") (name "Net-(IC61-Pad3)") (class "Default")
      (node (ref "IC61") (pin "3") (pinfunction "3_3") (pintype "passive"))
      (node (ref "SV130") (pin "11") (pinfunction "11_11") (pintype "passive"))
      (node (ref "SV130") (pin "12") (pinfunction "12_12") (pintype "passive"))
      (node (ref "SV131") (pin "11") (pinfunction "11_11") (pintype "passive"))
      (node (ref "SV131") (pin "12") (pinfunction "12_12") (pintype "passive"))
    )
    (net (code "970") (name "Net-(IC61-Pad4)") (class "Default")
      (node (ref "IC61") (pin "4") (pinfunction "4_4") (pintype "passive"))
      (node (ref "SV130") (pin "10") (pinfunction "10_10") (pintype "passive"))
      (node (ref "SV130") (pin "9") (pinfunction "9_9") (pintype "passive"))
      (node (ref "SV131") (pin "10") (pinfunction "10_10") (pintype "passive"))
      (node (ref "SV131") (pin "9") (pinfunction "9_9") (pintype "passive"))
    )
    (net (code "971") (name "Net-(IC61-Pad5)") (class "Default")
      (node (ref "IC61") (pin "5") (pinfunction "5_5") (pintype "passive"))
      (node (ref "SV130") (pin "7") (pinfunction "7_7") (pintype "passive"))
      (node (ref "SV130") (pin "8") (pinfunction "8_8") (pintype "passive"))
      (node (ref "SV131") (pin "7") (pinfunction "7_7") (pintype "passive"))
      (node (ref "SV131") (pin "8") (pinfunction "8_8") (pintype "passive"))
    )
    (net (code "972") (name "Net-(IC61-Pad6)") (class "Default")
      (node (ref "IC61") (pin "6") (pinfunction "6_6") (pintype "passive"))
      (node (ref "SV130") (pin "5") (pinfunction "5_5") (pintype "passive"))
      (node (ref "SV130") (pin "6") (pinfunction "6_6") (pintype "passive"))
      (node (ref "SV131") (pin "5") (pinfunction "5_5") (pintype "passive"))
      (node (ref "SV131") (pin "6") (pinfunction "6_6") (pintype "passive"))
    )
    (net (code "973") (name "Net-(IC61-Pad7)") (class "Default")
      (node (ref "IC61") (pin "7") (pinfunction "7_7") (pintype "passive"))
      (node (ref "SV130") (pin "3") (pinfunction "3_3") (pintype "passive"))
      (node (ref "SV130") (pin "4") (pinfunction "4_4") (pintype "passive"))
      (node (ref "SV131") (pin "3") (pinfunction "3_3") (pintype "passive"))
      (node (ref "SV131") (pin "4") (pinfunction "4_4") (pintype "passive"))
    )
    (net (code "974") (name "Net-(IC61-Pad8)") (class "Default")
      (node (ref "IC61") (pin "8") (pinfunction "8_8") (pintype "passive"))
      (node (ref "SV130") (pin "1") (pinfunction "1_1") (pintype "passive"))
      (node (ref "SV130") (pin "2") (pinfunction "2_2") (pintype "passive"))
      (node (ref "SV131") (pin "1") (pinfunction "1_1") (pintype "passive"))
      (node (ref "SV131") (pin "2") (pinfunction "2_2") (pintype "passive"))
    )
    (net (code "975") (name "Net-(IC61-Pad9)") (class "Default")
      (node (ref "IC61") (pin "9") (pinfunction "9_9") (pintype "passive"))
      (node (ref "SV129") (pin "1") (pinfunction "1_1") (pintype "passive"))
      (node (ref "SV129") (pin "2") (pinfunction "2_2") (pintype "passive"))
      (node (ref "SV132") (pin "8") (pinfunction "8_8") (pintype "passive"))
    )
    (net (code "976") (name "Net-(IC61-Pad10)") (class "Default")
      (node (ref "IC61") (pin "10") (pinfunction "10_10") (pintype "passive"))
      (node (ref "SV129") (pin "3") (pinfunction "3_3") (pintype "passive"))
      (node (ref "SV129") (pin "4") (pinfunction "4_4") (pintype "passive"))
      (node (ref "SV132") (pin "7") (pinfunction "7_7") (pintype "passive"))
    )
    (net (code "977") (name "Net-(IC61-Pad11)") (class "Default")
      (node (ref "IC61") (pin "11") (pinfunction "11_11") (pintype "passive"))
      (node (ref "SV129") (pin "5") (pinfunction "5_5") (pintype "passive"))
      (node (ref "SV129") (pin "6") (pinfunction "6_6") (pintype "passive"))
      (node (ref "SV132") (pin "6") (pinfunction "6_6") (pintype "passive"))
    )
    (net (code "978") (name "Net-(IC61-Pad12)") (class "Default")
      (node (ref "IC61") (pin "12") (pinfunction "12_12") (pintype "passive"))
      (node (ref "SV129") (pin "7") (pinfunction "7_7") (pintype "passive"))
      (node (ref "SV129") (pin "8") (pinfunction "8_8") (pintype "passive"))
      (node (ref "SV132") (pin "5") (pinfunction "5_5") (pintype "passive"))
    )
    (net (code "979") (name "Net-(IC61-Pad13)") (class "Default")
      (node (ref "IC61") (pin "13") (pinfunction "13_13") (pintype "passive"))
      (node (ref "SV129") (pin "10") (pinfunction "10_10") (pintype "passive"))
      (node (ref "SV129") (pin "9") (pinfunction "9_9") (pintype "passive"))
      (node (ref "SV132") (pin "4") (pinfunction "4_4") (pintype "passive"))
    )
    (net (code "980") (name "Net-(IC61-Pad14)") (class "Default")
      (node (ref "IC61") (pin "14") (pinfunction "14_14") (pintype "passive"))
      (node (ref "SV129") (pin "11") (pinfunction "11_11") (pintype "passive"))
      (node (ref "SV129") (pin "12") (pinfunction "12_12") (pintype "passive"))
      (node (ref "SV132") (pin "3") (pinfunction "3_3") (pintype "passive"))
    )
    (net (code "981") (name "Net-(IC61-Pad15)") (class "Default")
      (node (ref "IC61") (pin "15") (pinfunction "15_15") (pintype "passive"))
      (node (ref "SV129") (pin "13") (pinfunction "13_13") (pintype "passive"))
      (node (ref "SV129") (pin "14") (pinfunction "14_14") (pintype "passive"))
      (node (ref "SV132") (pin "2") (pinfunction "2_2") (pintype "passive"))
    )
    (net (code "982") (name "Net-(IC61-Pad16)") (class "Default")
      (node (ref "IC61") (pin "16") (pinfunction "16_16") (pintype "passive"))
      (node (ref "SV129") (pin "15") (pinfunction "15_15") (pintype "passive"))
      (node (ref "SV129") (pin "16") (pinfunction "16_16") (pintype "passive"))
      (node (ref "SV132") (pin "1") (pinfunction "1_1") (pintype "passive"))
    )
    (net (code "983") (name "Net-(IC62-Pad1)") (class "Default")
      (node (ref "IC62") (pin "1") (pinfunction "1_1") (pintype "passive"))
      (node (ref "SV134") (pin "15") (pinfunction "15_15") (pintype "passive"))
      (node (ref "SV134") (pin "16") (pinfunction "16_16") (pintype "passive"))
      (node (ref "SV135") (pin "15") (pinfunction "15_15") (pintype "passive"))
      (node (ref "SV135") (pin "16") (pinfunction "16_16") (pintype "passive"))
    )
    (net (code "984") (name "Net-(IC62-Pad2)") (class "Default")
      (node (ref "IC62") (pin "2") (pinfunction "2_2") (pintype "passive"))
      (node (ref "SV134") (pin "13") (pinfunction "13_13") (pintype "passive"))
      (node (ref "SV134") (pin "14") (pinfunction "14_14") (pintype "passive"))
      (node (ref "SV135") (pin "13") (pinfunction "13_13") (pintype "passive"))
      (node (ref "SV135") (pin "14") (pinfunction "14_14") (pintype "passive"))
    )
    (net (code "985") (name "Net-(IC62-Pad3)") (class "Default")
      (node (ref "IC62") (pin "3") (pinfunction "3_3") (pintype "passive"))
      (node (ref "SV134") (pin "11") (pinfunction "11_11") (pintype "passive"))
      (node (ref "SV134") (pin "12") (pinfunction "12_12") (pintype "passive"))
      (node (ref "SV135") (pin "11") (pinfunction "11_11") (pintype "passive"))
      (node (ref "SV135") (pin "12") (pinfunction "12_12") (pintype "passive"))
    )
    (net (code "986") (name "Net-(IC62-Pad4)") (class "Default")
      (node (ref "IC62") (pin "4") (pinfunction "4_4") (pintype "passive"))
      (node (ref "SV134") (pin "10") (pinfunction "10_10") (pintype "passive"))
      (node (ref "SV134") (pin "9") (pinfunction "9_9") (pintype "passive"))
      (node (ref "SV135") (pin "10") (pinfunction "10_10") (pintype "passive"))
      (node (ref "SV135") (pin "9") (pinfunction "9_9") (pintype "passive"))
    )
    (net (code "987") (name "Net-(IC62-Pad5)") (class "Default")
      (node (ref "IC62") (pin "5") (pinfunction "5_5") (pintype "passive"))
      (node (ref "SV134") (pin "7") (pinfunction "7_7") (pintype "passive"))
      (node (ref "SV134") (pin "8") (pinfunction "8_8") (pintype "passive"))
      (node (ref "SV135") (pin "7") (pinfunction "7_7") (pintype "passive"))
      (node (ref "SV135") (pin "8") (pinfunction "8_8") (pintype "passive"))
    )
    (net (code "988") (name "Net-(IC62-Pad6)") (class "Default")
      (node (ref "IC62") (pin "6") (pinfunction "6_6") (pintype "passive"))
      (node (ref "SV134") (pin "5") (pinfunction "5_5") (pintype "passive"))
      (node (ref "SV134") (pin "6") (pinfunction "6_6") (pintype "passive"))
      (node (ref "SV135") (pin "5") (pinfunction "5_5") (pintype "passive"))
      (node (ref "SV135") (pin "6") (pinfunction "6_6") (pintype "passive"))
    )
    (net (code "989") (name "Net-(IC62-Pad7)") (class "Default")
      (node (ref "IC62") (pin "7") (pinfunction "7_7") (pintype "passive"))
      (node (ref "SV134") (pin "3") (pinfunction "3_3") (pintype "passive"))
      (node (ref "SV134") (pin "4") (pinfunction "4_4") (pintype "passive"))
      (node (ref "SV135") (pin "3") (pinfunction "3_3") (pintype "passive"))
      (node (ref "SV135") (pin "4") (pinfunction "4_4") (pintype "passive"))
    )
    (net (code "990") (name "Net-(IC62-Pad8)") (class "Default")
      (node (ref "IC62") (pin "8") (pinfunction "8_8") (pintype "passive"))
      (node (ref "SV134") (pin "1") (pinfunction "1_1") (pintype "passive"))
      (node (ref "SV134") (pin "2") (pinfunction "2_2") (pintype "passive"))
      (node (ref "SV135") (pin "1") (pinfunction "1_1") (pintype "passive"))
      (node (ref "SV135") (pin "2") (pinfunction "2_2") (pintype "passive"))
    )
    (net (code "991") (name "Net-(IC62-Pad9)") (class "Default")
      (node (ref "IC62") (pin "9") (pinfunction "9_9") (pintype "passive"))
      (node (ref "SV133") (pin "1") (pinfunction "1_1") (pintype "passive"))
      (node (ref "SV133") (pin "2") (pinfunction "2_2") (pintype "passive"))
      (node (ref "SV136") (pin "8") (pinfunction "8_8") (pintype "passive"))
    )
    (net (code "992") (name "Net-(IC62-Pad10)") (class "Default")
      (node (ref "IC62") (pin "10") (pinfunction "10_10") (pintype "passive"))
      (node (ref "SV133") (pin "3") (pinfunction "3_3") (pintype "passive"))
      (node (ref "SV133") (pin "4") (pinfunction "4_4") (pintype "passive"))
      (node (ref "SV136") (pin "7") (pinfunction "7_7") (pintype "passive"))
    )
    (net (code "993") (name "Net-(IC62-Pad11)") (class "Default")
      (node (ref "IC62") (pin "11") (pinfunction "11_11") (pintype "passive"))
      (node (ref "SV133") (pin "5") (pinfunction "5_5") (pintype "passive"))
      (node (ref "SV133") (pin "6") (pinfunction "6_6") (pintype "passive"))
      (node (ref "SV136") (pin "6") (pinfunction "6_6") (pintype "passive"))
    )
    (net (code "994") (name "Net-(IC62-Pad12)") (class "Default")
      (node (ref "IC62") (pin "12") (pinfunction "12_12") (pintype "passive"))
      (node (ref "SV133") (pin "7") (pinfunction "7_7") (pintype "passive"))
      (node (ref "SV133") (pin "8") (pinfunction "8_8") (pintype "passive"))
      (node (ref "SV136") (pin "5") (pinfunction "5_5") (pintype "passive"))
    )
    (net (code "995") (name "Net-(IC62-Pad13)") (class "Default")
      (node (ref "IC62") (pin "13") (pinfunction "13_13") (pintype "passive"))
      (node (ref "SV133") (pin "10") (pinfunction "10_10") (pintype "passive"))
      (node (ref "SV133") (pin "9") (pinfunction "9_9") (pintype "passive"))
      (node (ref "SV136") (pin "4") (pinfunction "4_4") (pintype "passive"))
    )
    (net (code "996") (name "Net-(IC62-Pad14)") (class "Default")
      (node (ref "IC62") (pin "14") (pinfunction "14_14") (pintype "passive"))
      (node (ref "SV133") (pin "11") (pinfunction "11_11") (pintype "passive"))
      (node (ref "SV133") (pin "12") (pinfunction "12_12") (pintype "passive"))
      (node (ref "SV136") (pin "3") (pinfunction "3_3") (pintype "passive"))
    )
    (net (code "997") (name "Net-(IC62-Pad15)") (class "Default")
      (node (ref "IC62") (pin "15") (pinfunction "15_15") (pintype "passive"))
      (node (ref "SV133") (pin "13") (pinfunction "13_13") (pintype "passive"))
      (node (ref "SV133") (pin "14") (pinfunction "14_14") (pintype "passive"))
      (node (ref "SV136") (pin "2") (pinfunction "2_2") (pintype "passive"))
    )
    (net (code "998") (name "Net-(IC62-Pad16)") (class "Default")
      (node (ref "IC62") (pin "16") (pinfunction "16_16") (pintype "passive"))
      (node (ref "SV133") (pin "15") (pinfunction "15_15") (pintype "passive"))
      (node (ref "SV133") (pin "16") (pinfunction "16_16") (pintype "passive"))
      (node (ref "SV136") (pin "1") (pinfunction "1_1") (pintype "passive"))
    )
    (net (code "999") (name "Net-(IC63-Pad1)") (class "Default")
      (node (ref "IC63") (pin "1") (pinfunction "1_1") (pintype "passive"))
      (node (ref "SV138") (pin "15") (pinfunction "15_15") (pintype "passive"))
      (node (ref "SV138") (pin "16") (pinfunction "16_16") (pintype "passive"))
      (node (ref "SV139") (pin "15") (pinfunction "15_15") (pintype "passive"))
      (node (ref "SV139") (pin "16") (pinfunction "16_16") (pintype "passive"))
    )
    (net (code "1000") (name "Net-(IC63-Pad2)") (class "Default")
      (node (ref "IC63") (pin "2") (pinfunction "2_2") (pintype "passive"))
      (node (ref "SV138") (pin "13") (pinfunction "13_13") (pintype "passive"))
      (node (ref "SV138") (pin "14") (pinfunction "14_14") (pintype "passive"))
      (node (ref "SV139") (pin "13") (pinfunction "13_13") (pintype "passive"))
      (node (ref "SV139") (pin "14") (pinfunction "14_14") (pintype "passive"))
    )
    (net (code "1001") (name "Net-(IC63-Pad3)") (class "Default")
      (node (ref "IC63") (pin "3") (pinfunction "3_3") (pintype "passive"))
      (node (ref "SV138") (pin "11") (pinfunction "11_11") (pintype "passive"))
      (node (ref "SV138") (pin "12") (pinfunction "12_12") (pintype "passive"))
      (node (ref "SV139") (pin "11") (pinfunction "11_11") (pintype "passive"))
      (node (ref "SV139") (pin "12") (pinfunction "12_12") (pintype "passive"))
    )
    (net (code "1002") (name "Net-(IC63-Pad4)") (class "Default")
      (node (ref "IC63") (pin "4") (pinfunction "4_4") (pintype "passive"))
      (node (ref "SV138") (pin "10") (pinfunction "10_10") (pintype "passive"))
      (node (ref "SV138") (pin "9") (pinfunction "9_9") (pintype "passive"))
      (node (ref "SV139") (pin "10") (pinfunction "10_10") (pintype "passive"))
      (node (ref "SV139") (pin "9") (pinfunction "9_9") (pintype "passive"))
    )
    (net (code "1003") (name "Net-(IC63-Pad5)") (class "Default")
      (node (ref "IC63") (pin "5") (pinfunction "5_5") (pintype "passive"))
      (node (ref "SV138") (pin "7") (pinfunction "7_7") (pintype "passive"))
      (node (ref "SV138") (pin "8") (pinfunction "8_8") (pintype "passive"))
      (node (ref "SV139") (pin "7") (pinfunction "7_7") (pintype "passive"))
      (node (ref "SV139") (pin "8") (pinfunction "8_8") (pintype "passive"))
    )
    (net (code "1004") (name "Net-(IC63-Pad6)") (class "Default")
      (node (ref "IC63") (pin "6") (pinfunction "6_6") (pintype "passive"))
      (node (ref "SV138") (pin "5") (pinfunction "5_5") (pintype "passive"))
      (node (ref "SV138") (pin "6") (pinfunction "6_6") (pintype "passive"))
      (node (ref "SV139") (pin "5") (pinfunction "5_5") (pintype "passive"))
      (node (ref "SV139") (pin "6") (pinfunction "6_6") (pintype "passive"))
    )
    (net (code "1005") (name "Net-(IC63-Pad7)") (class "Default")
      (node (ref "IC63") (pin "7") (pinfunction "7_7") (pintype "passive"))
      (node (ref "SV138") (pin "3") (pinfunction "3_3") (pintype "passive"))
      (node (ref "SV138") (pin "4") (pinfunction "4_4") (pintype "passive"))
      (node (ref "SV139") (pin "3") (pinfunction "3_3") (pintype "passive"))
      (node (ref "SV139") (pin "4") (pinfunction "4_4") (pintype "passive"))
    )
    (net (code "1006") (name "Net-(IC63-Pad8)") (class "Default")
      (node (ref "IC63") (pin "8") (pinfunction "8_8") (pintype "passive"))
      (node (ref "SV138") (pin "1") (pinfunction "1_1") (pintype "passive"))
      (node (ref "SV138") (pin "2") (pinfunction "2_2") (pintype "passive"))
      (node (ref "SV139") (pin "1") (pinfunction "1_1") (pintype "passive"))
      (node (ref "SV139") (pin "2") (pinfunction "2_2") (pintype "passive"))
    )
    (net (code "1007") (name "Net-(IC63-Pad9)") (class "Default")
      (node (ref "IC63") (pin "9") (pinfunction "9_9") (pintype "passive"))
      (node (ref "SV137") (pin "1") (pinfunction "1_1") (pintype "passive"))
      (node (ref "SV137") (pin "2") (pinfunction "2_2") (pintype "passive"))
      (node (ref "SV140") (pin "8") (pinfunction "8_8") (pintype "passive"))
    )
    (net (code "1008") (name "Net-(IC63-Pad10)") (class "Default")
      (node (ref "IC63") (pin "10") (pinfunction "10_10") (pintype "passive"))
      (node (ref "SV137") (pin "3") (pinfunction "3_3") (pintype "passive"))
      (node (ref "SV137") (pin "4") (pinfunction "4_4") (pintype "passive"))
      (node (ref "SV140") (pin "7") (pinfunction "7_7") (pintype "passive"))
    )
    (net (code "1009") (name "Net-(IC63-Pad11)") (class "Default")
      (node (ref "IC63") (pin "11") (pinfunction "11_11") (pintype "passive"))
      (node (ref "SV137") (pin "5") (pinfunction "5_5") (pintype "passive"))
      (node (ref "SV137") (pin "6") (pinfunction "6_6") (pintype "passive"))
      (node (ref "SV140") (pin "6") (pinfunction "6_6") (pintype "passive"))
    )
    (net (code "1010") (name "Net-(IC63-Pad12)") (class "Default")
      (node (ref "IC63") (pin "12") (pinfunction "12_12") (pintype "passive"))
      (node (ref "SV137") (pin "7") (pinfunction "7_7") (pintype "passive"))
      (node (ref "SV137") (pin "8") (pinfunction "8_8") (pintype "passive"))
      (node (ref "SV140") (pin "5") (pinfunction "5_5") (pintype "passive"))
    )
    (net (code "1011") (name "Net-(IC63-Pad13)") (class "Default")
      (node (ref "IC63") (pin "13") (pinfunction "13_13") (pintype "passive"))
      (node (ref "SV137") (pin "10") (pinfunction "10_10") (pintype "passive"))
      (node (ref "SV137") (pin "9") (pinfunction "9_9") (pintype "passive"))
      (node (ref "SV140") (pin "4") (pinfunction "4_4") (pintype "passive"))
    )
    (net (code "1012") (name "Net-(IC63-Pad14)") (class "Default")
      (node (ref "IC63") (pin "14") (pinfunction "14_14") (pintype "passive"))
      (node (ref "SV137") (pin "11") (pinfunction "11_11") (pintype "passive"))
      (node (ref "SV137") (pin "12") (pinfunction "12_12") (pintype "passive"))
      (node (ref "SV140") (pin "3") (pinfunction "3_3") (pintype "passive"))
    )
    (net (code "1013") (name "Net-(IC63-Pad15)") (class "Default")
      (node (ref "IC63") (pin "15") (pinfunction "15_15") (pintype "passive"))
      (node (ref "SV137") (pin "13") (pinfunction "13_13") (pintype "passive"))
      (node (ref "SV137") (pin "14") (pinfunction "14_14") (pintype "passive"))
      (node (ref "SV140") (pin "2") (pinfunction "2_2") (pintype "passive"))
    )
    (net (code "1014") (name "Net-(IC63-Pad16)") (class "Default")
      (node (ref "IC63") (pin "16") (pinfunction "16_16") (pintype "passive"))
      (node (ref "SV137") (pin "15") (pinfunction "15_15") (pintype "passive"))
      (node (ref "SV137") (pin "16") (pinfunction "16_16") (pintype "passive"))
      (node (ref "SV140") (pin "1") (pinfunction "1_1") (pintype "passive"))
    )
    (net (code "1015") (name "Net-(IC64-Pad1)") (class "Default")
      (node (ref "IC64") (pin "1") (pinfunction "1_1") (pintype "passive"))
      (node (ref "SV142") (pin "15") (pinfunction "15_15") (pintype "passive"))
      (node (ref "SV142") (pin "16") (pinfunction "16_16") (pintype "passive"))
      (node (ref "SV143") (pin "15") (pinfunction "15_15") (pintype "passive"))
      (node (ref "SV143") (pin "16") (pinfunction "16_16") (pintype "passive"))
    )
    (net (code "1016") (name "Net-(IC64-Pad2)") (class "Default")
      (node (ref "IC64") (pin "2") (pinfunction "2_2") (pintype "passive"))
      (node (ref "SV142") (pin "13") (pinfunction "13_13") (pintype "passive"))
      (node (ref "SV142") (pin "14") (pinfunction "14_14") (pintype "passive"))
      (node (ref "SV143") (pin "13") (pinfunction "13_13") (pintype "passive"))
      (node (ref "SV143") (pin "14") (pinfunction "14_14") (pintype "passive"))
    )
    (net (code "1017") (name "Net-(IC64-Pad3)") (class "Default")
      (node (ref "IC64") (pin "3") (pinfunction "3_3") (pintype "passive"))
      (node (ref "SV142") (pin "11") (pinfunction "11_11") (pintype "passive"))
      (node (ref "SV142") (pin "12") (pinfunction "12_12") (pintype "passive"))
      (node (ref "SV143") (pin "11") (pinfunction "11_11") (pintype "passive"))
      (node (ref "SV143") (pin "12") (pinfunction "12_12") (pintype "passive"))
    )
    (net (code "1018") (name "Net-(IC64-Pad4)") (class "Default")
      (node (ref "IC64") (pin "4") (pinfunction "4_4") (pintype "passive"))
      (node (ref "SV142") (pin "10") (pinfunction "10_10") (pintype "passive"))
      (node (ref "SV142") (pin "9") (pinfunction "9_9") (pintype "passive"))
      (node (ref "SV143") (pin "10") (pinfunction "10_10") (pintype "passive"))
      (node (ref "SV143") (pin "9") (pinfunction "9_9") (pintype "passive"))
    )
    (net (code "1019") (name "Net-(IC64-Pad5)") (class "Default")
      (node (ref "IC64") (pin "5") (pinfunction "5_5") (pintype "passive"))
      (node (ref "SV142") (pin "7") (pinfunction "7_7") (pintype "passive"))
      (node (ref "SV142") (pin "8") (pinfunction "8_8") (pintype "passive"))
      (node (ref "SV143") (pin "7") (pinfunction "7_7") (pintype "passive"))
      (node (ref "SV143") (pin "8") (pinfunction "8_8") (pintype "passive"))
    )
    (net (code "1020") (name "Net-(IC64-Pad6)") (class "Default")
      (node (ref "IC64") (pin "6") (pinfunction "6_6") (pintype "passive"))
      (node (ref "SV142") (pin "5") (pinfunction "5_5") (pintype "passive"))
      (node (ref "SV142") (pin "6") (pinfunction "6_6") (pintype "passive"))
      (node (ref "SV143") (pin "5") (pinfunction "5_5") (pintype "passive"))
      (node (ref "SV143") (pin "6") (pinfunction "6_6") (pintype "passive"))
    )
    (net (code "1021") (name "Net-(IC64-Pad7)") (class "Default")
      (node (ref "IC64") (pin "7") (pinfunction "7_7") (pintype "passive"))
      (node (ref "SV142") (pin "3") (pinfunction "3_3") (pintype "passive"))
      (node (ref "SV142") (pin "4") (pinfunction "4_4") (pintype "passive"))
      (node (ref "SV143") (pin "3") (pinfunction "3_3") (pintype "passive"))
      (node (ref "SV143") (pin "4") (pinfunction "4_4") (pintype "passive"))
    )
    (net (code "1022") (name "Net-(IC64-Pad8)") (class "Default")
      (node (ref "IC64") (pin "8") (pinfunction "8_8") (pintype "passive"))
      (node (ref "SV142") (pin "1") (pinfunction "1_1") (pintype "passive"))
      (node (ref "SV142") (pin "2") (pinfunction "2_2") (pintype "passive"))
      (node (ref "SV143") (pin "1") (pinfunction "1_1") (pintype "passive"))
      (node (ref "SV143") (pin "2") (pinfunction "2_2") (pintype "passive"))
    )
    (net (code "1023") (name "Net-(IC64-Pad9)") (class "Default")
      (node (ref "IC64") (pin "9") (pinfunction "9_9") (pintype "passive"))
      (node (ref "SV141") (pin "1") (pinfunction "1_1") (pintype "passive"))
      (node (ref "SV141") (pin "2") (pinfunction "2_2") (pintype "passive"))
      (node (ref "SV144") (pin "8") (pinfunction "8_8") (pintype "passive"))
    )
    (net (code "1024") (name "Net-(IC64-Pad10)") (class "Default")
      (node (ref "IC64") (pin "10") (pinfunction "10_10") (pintype "passive"))
      (node (ref "SV141") (pin "3") (pinfunction "3_3") (pintype "passive"))
      (node (ref "SV141") (pin "4") (pinfunction "4_4") (pintype "passive"))
      (node (ref "SV144") (pin "7") (pinfunction "7_7") (pintype "passive"))
    )
    (net (code "1025") (name "Net-(IC64-Pad11)") (class "Default")
      (node (ref "IC64") (pin "11") (pinfunction "11_11") (pintype "passive"))
      (node (ref "SV141") (pin "5") (pinfunction "5_5") (pintype "passive"))
      (node (ref "SV141") (pin "6") (pinfunction "6_6") (pintype "passive"))
      (node (ref "SV144") (pin "6") (pinfunction "6_6") (pintype "passive"))
    )
    (net (code "1026") (name "Net-(IC64-Pad12)") (class "Default")
      (node (ref "IC64") (pin "12") (pinfunction "12_12") (pintype "passive"))
      (node (ref "SV141") (pin "7") (pinfunction "7_7") (pintype "passive"))
      (node (ref "SV141") (pin "8") (pinfunction "8_8") (pintype "passive"))
      (node (ref "SV144") (pin "5") (pinfunction "5_5") (pintype "passive"))
    )
    (net (code "1027") (name "Net-(IC64-Pad13)") (class "Default")
      (node (ref "IC64") (pin "13") (pinfunction "13_13") (pintype "passive"))
      (node (ref "SV141") (pin "10") (pinfunction "10_10") (pintype "passive"))
      (node (ref "SV141") (pin "9") (pinfunction "9_9") (pintype "passive"))
      (node (ref "SV144") (pin "4") (pinfunction "4_4") (pintype "passive"))
    )
    (net (code "1028") (name "Net-(IC64-Pad14)") (class "Default")
      (node (ref "IC64") (pin "14") (pinfunction "14_14") (pintype "passive"))
      (node (ref "SV141") (pin "11") (pinfunction "11_11") (pintype "passive"))
      (node (ref "SV141") (pin "12") (pinfunction "12_12") (pintype "passive"))
      (node (ref "SV144") (pin "3") (pinfunction "3_3") (pintype "passive"))
    )
    (net (code "1029") (name "Net-(IC64-Pad15)") (class "Default")
      (node (ref "IC64") (pin "15") (pinfunction "15_15") (pintype "passive"))
      (node (ref "SV141") (pin "13") (pinfunction "13_13") (pintype "passive"))
      (node (ref "SV141") (pin "14") (pinfunction "14_14") (pintype "passive"))
      (node (ref "SV144") (pin "2") (pinfunction "2_2") (pintype "passive"))
    )
    (net (code "1030") (name "Net-(IC64-Pad16)") (class "Default")
      (node (ref "IC64") (pin "16") (pinfunction "16_16") (pintype "passive"))
      (node (ref "SV141") (pin "15") (pinfunction "15_15") (pintype "passive"))
      (node (ref "SV141") (pin "16") (pinfunction "16_16") (pintype "passive"))
      (node (ref "SV144") (pin "1") (pinfunction "1_1") (pintype "passive"))
    )
    (net (code "1031") (name "Net-(IC65-Pad1)") (class "Default")
      (node (ref "IC65") (pin "1") (pinfunction "1_1") (pintype "passive"))
      (node (ref "SV146") (pin "15") (pinfunction "15_15") (pintype "passive"))
      (node (ref "SV146") (pin "16") (pinfunction "16_16") (pintype "passive"))
      (node (ref "SV147") (pin "15") (pinfunction "15_15") (pintype "passive"))
      (node (ref "SV147") (pin "16") (pinfunction "16_16") (pintype "passive"))
    )
    (net (code "1032") (name "Net-(IC65-Pad2)") (class "Default")
      (node (ref "IC65") (pin "2") (pinfunction "2_2") (pintype "passive"))
      (node (ref "SV146") (pin "13") (pinfunction "13_13") (pintype "passive"))
      (node (ref "SV146") (pin "14") (pinfunction "14_14") (pintype "passive"))
      (node (ref "SV147") (pin "13") (pinfunction "13_13") (pintype "passive"))
      (node (ref "SV147") (pin "14") (pinfunction "14_14") (pintype "passive"))
    )
    (net (code "1033") (name "Net-(IC65-Pad3)") (class "Default")
      (node (ref "IC65") (pin "3") (pinfunction "3_3") (pintype "passive"))
      (node (ref "SV146") (pin "11") (pinfunction "11_11") (pintype "passive"))
      (node (ref "SV146") (pin "12") (pinfunction "12_12") (pintype "passive"))
      (node (ref "SV147") (pin "11") (pinfunction "11_11") (pintype "passive"))
      (node (ref "SV147") (pin "12") (pinfunction "12_12") (pintype "passive"))
    )
    (net (code "1034") (name "Net-(IC65-Pad4)") (class "Default")
      (node (ref "IC65") (pin "4") (pinfunction "4_4") (pintype "passive"))
      (node (ref "SV146") (pin "10") (pinfunction "10_10") (pintype "passive"))
      (node (ref "SV146") (pin "9") (pinfunction "9_9") (pintype "passive"))
      (node (ref "SV147") (pin "10") (pinfunction "10_10") (pintype "passive"))
      (node (ref "SV147") (pin "9") (pinfunction "9_9") (pintype "passive"))
    )
    (net (code "1035") (name "Net-(IC65-Pad5)") (class "Default")
      (node (ref "IC65") (pin "5") (pinfunction "5_5") (pintype "passive"))
      (node (ref "SV146") (pin "7") (pinfunction "7_7") (pintype "passive"))
      (node (ref "SV146") (pin "8") (pinfunction "8_8") (pintype "passive"))
      (node (ref "SV147") (pin "7") (pinfunction "7_7") (pintype "passive"))
      (node (ref "SV147") (pin "8") (pinfunction "8_8") (pintype "passive"))
    )
    (net (code "1036") (name "Net-(IC65-Pad6)") (class "Default")
      (node (ref "IC65") (pin "6") (pinfunction "6_6") (pintype "passive"))
      (node (ref "SV146") (pin "5") (pinfunction "5_5") (pintype "passive"))
      (node (ref "SV146") (pin "6") (pinfunction "6_6") (pintype "passive"))
      (node (ref "SV147") (pin "5") (pinfunction "5_5") (pintype "passive"))
      (node (ref "SV147") (pin "6") (pinfunction "6_6") (pintype "passive"))
    )
    (net (code "1037") (name "Net-(IC65-Pad7)") (class "Default")
      (node (ref "IC65") (pin "7") (pinfunction "7_7") (pintype "passive"))
      (node (ref "SV146") (pin "3") (pinfunction "3_3") (pintype "passive"))
      (node (ref "SV146") (pin "4") (pinfunction "4_4") (pintype "passive"))
      (node (ref "SV147") (pin "3") (pinfunction "3_3") (pintype "passive"))
      (node (ref "SV147") (pin "4") (pinfunction "4_4") (pintype "passive"))
    )
    (net (code "1038") (name "Net-(IC65-Pad8)") (class "Default")
      (node (ref "IC65") (pin "8") (pinfunction "8_8") (pintype "passive"))
      (node (ref "SV146") (pin "1") (pinfunction "1_1") (pintype "passive"))
      (node (ref "SV146") (pin "2") (pinfunction "2_2") (pintype "passive"))
      (node (ref "SV147") (pin "1") (pinfunction "1_1") (pintype "passive"))
      (node (ref "SV147") (pin "2") (pinfunction "2_2") (pintype "passive"))
    )
    (net (code "1039") (name "Net-(IC65-Pad9)") (class "Default")
      (node (ref "IC65") (pin "9") (pinfunction "9_9") (pintype "passive"))
      (node (ref "SV145") (pin "1") (pinfunction "1_1") (pintype "passive"))
      (node (ref "SV145") (pin "2") (pinfunction "2_2") (pintype "passive"))
      (node (ref "SV148") (pin "8") (pinfunction "8_8") (pintype "passive"))
    )
    (net (code "1040") (name "Net-(IC65-Pad10)") (class "Default")
      (node (ref "IC65") (pin "10") (pinfunction "10_10") (pintype "passive"))
      (node (ref "SV145") (pin "3") (pinfunction "3_3") (pintype "passive"))
      (node (ref "SV145") (pin "4") (pinfunction "4_4") (pintype "passive"))
      (node (ref "SV148") (pin "7") (pinfunction "7_7") (pintype "passive"))
    )
    (net (code "1041") (name "Net-(IC65-Pad11)") (class "Default")
      (node (ref "IC65") (pin "11") (pinfunction "11_11") (pintype "passive"))
      (node (ref "SV145") (pin "5") (pinfunction "5_5") (pintype "passive"))
      (node (ref "SV145") (pin "6") (pinfunction "6_6") (pintype "passive"))
      (node (ref "SV148") (pin "6") (pinfunction "6_6") (pintype "passive"))
    )
    (net (code "1042") (name "Net-(IC65-Pad12)") (class "Default")
      (node (ref "IC65") (pin "12") (pinfunction "12_12") (pintype "passive"))
      (node (ref "SV145") (pin "7") (pinfunction "7_7") (pintype "passive"))
      (node (ref "SV145") (pin "8") (pinfunction "8_8") (pintype "passive"))
      (node (ref "SV148") (pin "5") (pinfunction "5_5") (pintype "passive"))
    )
    (net (code "1043") (name "Net-(IC65-Pad13)") (class "Default")
      (node (ref "IC65") (pin "13") (pinfunction "13_13") (pintype "passive"))
      (node (ref "SV145") (pin "10") (pinfunction "10_10") (pintype "passive"))
      (node (ref "SV145") (pin "9") (pinfunction "9_9") (pintype "passive"))
      (node (ref "SV148") (pin "4") (pinfunction "4_4") (pintype "passive"))
    )
    (net (code "1044") (name "Net-(IC65-Pad14)") (class "Default")
      (node (ref "IC65") (pin "14") (pinfunction "14_14") (pintype "passive"))
      (node (ref "SV145") (pin "11") (pinfunction "11_11") (pintype "passive"))
      (node (ref "SV145") (pin "12") (pinfunction "12_12") (pintype "passive"))
      (node (ref "SV148") (pin "3") (pinfunction "3_3") (pintype "passive"))
    )
    (net (code "1045") (name "Net-(IC65-Pad15)") (class "Default")
      (node (ref "IC65") (pin "15") (pinfunction "15_15") (pintype "passive"))
      (node (ref "SV145") (pin "13") (pinfunction "13_13") (pintype "passive"))
      (node (ref "SV145") (pin "14") (pinfunction "14_14") (pintype "passive"))
      (node (ref "SV148") (pin "2") (pinfunction "2_2") (pintype "passive"))
    )
    (net (code "1046") (name "Net-(IC65-Pad16)") (class "Default")
      (node (ref "IC65") (pin "16") (pinfunction "16_16") (pintype "passive"))
      (node (ref "SV145") (pin "15") (pinfunction "15_15") (pintype "passive"))
      (node (ref "SV145") (pin "16") (pinfunction "16_16") (pintype "passive"))
      (node (ref "SV148") (pin "1") (pinfunction "1_1") (pintype "passive"))
    )
    (net (code "1047") (name "Net-(IC66-Pad1)") (class "Default")
      (node (ref "IC66") (pin "1") (pinfunction "1_1") (pintype "passive"))
      (node (ref "SV150") (pin "15") (pinfunction "15_15") (pintype "passive"))
      (node (ref "SV150") (pin "16") (pinfunction "16_16") (pintype "passive"))
      (node (ref "SV151") (pin "15") (pinfunction "15_15") (pintype "passive"))
      (node (ref "SV151") (pin "16") (pinfunction "16_16") (pintype "passive"))
    )
    (net (code "1048") (name "Net-(IC66-Pad2)") (class "Default")
      (node (ref "IC66") (pin "2") (pinfunction "2_2") (pintype "passive"))
      (node (ref "SV150") (pin "13") (pinfunction "13_13") (pintype "passive"))
      (node (ref "SV150") (pin "14") (pinfunction "14_14") (pintype "passive"))
      (node (ref "SV151") (pin "13") (pinfunction "13_13") (pintype "passive"))
      (node (ref "SV151") (pin "14") (pinfunction "14_14") (pintype "passive"))
    )
    (net (code "1049") (name "Net-(IC66-Pad3)") (class "Default")
      (node (ref "IC66") (pin "3") (pinfunction "3_3") (pintype "passive"))
      (node (ref "SV150") (pin "11") (pinfunction "11_11") (pintype "passive"))
      (node (ref "SV150") (pin "12") (pinfunction "12_12") (pintype "passive"))
      (node (ref "SV151") (pin "11") (pinfunction "11_11") (pintype "passive"))
      (node (ref "SV151") (pin "12") (pinfunction "12_12") (pintype "passive"))
    )
    (net (code "1050") (name "Net-(IC66-Pad4)") (class "Default")
      (node (ref "IC66") (pin "4") (pinfunction "4_4") (pintype "passive"))
      (node (ref "SV150") (pin "10") (pinfunction "10_10") (pintype "passive"))
      (node (ref "SV150") (pin "9") (pinfunction "9_9") (pintype "passive"))
      (node (ref "SV151") (pin "10") (pinfunction "10_10") (pintype "passive"))
      (node (ref "SV151") (pin "9") (pinfunction "9_9") (pintype "passive"))
    )
    (net (code "1051") (name "Net-(IC66-Pad5)") (class "Default")
      (node (ref "IC66") (pin "5") (pinfunction "5_5") (pintype "passive"))
      (node (ref "SV150") (pin "7") (pinfunction "7_7") (pintype "passive"))
      (node (ref "SV150") (pin "8") (pinfunction "8_8") (pintype "passive"))
      (node (ref "SV151") (pin "7") (pinfunction "7_7") (pintype "passive"))
      (node (ref "SV151") (pin "8") (pinfunction "8_8") (pintype "passive"))
    )
    (net (code "1052") (name "Net-(IC66-Pad6)") (class "Default")
      (node (ref "IC66") (pin "6") (pinfunction "6_6") (pintype "passive"))
      (node (ref "SV150") (pin "5") (pinfunction "5_5") (pintype "passive"))
      (node (ref "SV150") (pin "6") (pinfunction "6_6") (pintype "passive"))
      (node (ref "SV151") (pin "5") (pinfunction "5_5") (pintype "passive"))
      (node (ref "SV151") (pin "6") (pinfunction "6_6") (pintype "passive"))
    )
    (net (code "1053") (name "Net-(IC66-Pad7)") (class "Default")
      (node (ref "IC66") (pin "7") (pinfunction "7_7") (pintype "passive"))
      (node (ref "SV150") (pin "3") (pinfunction "3_3") (pintype "passive"))
      (node (ref "SV150") (pin "4") (pinfunction "4_4") (pintype "passive"))
      (node (ref "SV151") (pin "3") (pinfunction "3_3") (pintype "passive"))
      (node (ref "SV151") (pin "4") (pinfunction "4_4") (pintype "passive"))
    )
    (net (code "1054") (name "Net-(IC66-Pad8)") (class "Default")
      (node (ref "IC66") (pin "8") (pinfunction "8_8") (pintype "passive"))
      (node (ref "SV150") (pin "1") (pinfunction "1_1") (pintype "passive"))
      (node (ref "SV150") (pin "2") (pinfunction "2_2") (pintype "passive"))
      (node (ref "SV151") (pin "1") (pinfunction "1_1") (pintype "passive"))
      (node (ref "SV151") (pin "2") (pinfunction "2_2") (pintype "passive"))
    )
    (net (code "1055") (name "Net-(IC66-Pad9)") (class "Default")
      (node (ref "IC66") (pin "9") (pinfunction "9_9") (pintype "passive"))
      (node (ref "SV149") (pin "1") (pinfunction "1_1") (pintype "passive"))
      (node (ref "SV149") (pin "2") (pinfunction "2_2") (pintype "passive"))
      (node (ref "SV152") (pin "8") (pinfunction "8_8") (pintype "passive"))
    )
    (net (code "1056") (name "Net-(IC66-Pad10)") (class "Default")
      (node (ref "IC66") (pin "10") (pinfunction "10_10") (pintype "passive"))
      (node (ref "SV149") (pin "3") (pinfunction "3_3") (pintype "passive"))
      (node (ref "SV149") (pin "4") (pinfunction "4_4") (pintype "passive"))
      (node (ref "SV152") (pin "7") (pinfunction "7_7") (pintype "passive"))
    )
    (net (code "1057") (name "Net-(IC66-Pad11)") (class "Default")
      (node (ref "IC66") (pin "11") (pinfunction "11_11") (pintype "passive"))
      (node (ref "SV149") (pin "5") (pinfunction "5_5") (pintype "passive"))
      (node (ref "SV149") (pin "6") (pinfunction "6_6") (pintype "passive"))
      (node (ref "SV152") (pin "6") (pinfunction "6_6") (pintype "passive"))
    )
    (net (code "1058") (name "Net-(IC66-Pad12)") (class "Default")
      (node (ref "IC66") (pin "12") (pinfunction "12_12") (pintype "passive"))
      (node (ref "SV149") (pin "7") (pinfunction "7_7") (pintype "passive"))
      (node (ref "SV149") (pin "8") (pinfunction "8_8") (pintype "passive"))
      (node (ref "SV152") (pin "5") (pinfunction "5_5") (pintype "passive"))
    )
    (net (code "1059") (name "Net-(IC66-Pad13)") (class "Default")
      (node (ref "IC66") (pin "13") (pinfunction "13_13") (pintype "passive"))
      (node (ref "SV149") (pin "10") (pinfunction "10_10") (pintype "passive"))
      (node (ref "SV149") (pin "9") (pinfunction "9_9") (pintype "passive"))
      (node (ref "SV152") (pin "4") (pinfunction "4_4") (pintype "passive"))
    )
    (net (code "1060") (name "Net-(IC66-Pad14)") (class "Default")
      (node (ref "IC66") (pin "14") (pinfunction "14_14") (pintype "passive"))
      (node (ref "SV149") (pin "11") (pinfunction "11_11") (pintype "passive"))
      (node (ref "SV149") (pin "12") (pinfunction "12_12") (pintype "passive"))
      (node (ref "SV152") (pin "3") (pinfunction "3_3") (pintype "passive"))
    )
    (net (code "1061") (name "Net-(IC66-Pad15)") (class "Default")
      (node (ref "IC66") (pin "15") (pinfunction "15_15") (pintype "passive"))
      (node (ref "SV149") (pin "13") (pinfunction "13_13") (pintype "passive"))
      (node (ref "SV149") (pin "14") (pinfunction "14_14") (pintype "passive"))
      (node (ref "SV152") (pin "2") (pinfunction "2_2") (pintype "passive"))
    )
    (net (code "1062") (name "Net-(IC66-Pad16)") (class "Default")
      (node (ref "IC66") (pin "16") (pinfunction "16_16") (pintype "passive"))
      (node (ref "SV149") (pin "15") (pinfunction "15_15") (pintype "passive"))
      (node (ref "SV149") (pin "16") (pinfunction "16_16") (pintype "passive"))
      (node (ref "SV152") (pin "1") (pinfunction "1_1") (pintype "passive"))
    )
    (net (code "1063") (name "Net-(IC67-Pad1)") (class "Default")
      (node (ref "IC67") (pin "1") (pinfunction "1_1") (pintype "passive"))
      (node (ref "SV154") (pin "15") (pinfunction "15_15") (pintype "passive"))
      (node (ref "SV154") (pin "16") (pinfunction "16_16") (pintype "passive"))
      (node (ref "SV155") (pin "15") (pinfunction "15_15") (pintype "passive"))
      (node (ref "SV155") (pin "16") (pinfunction "16_16") (pintype "passive"))
    )
    (net (code "1064") (name "Net-(IC67-Pad2)") (class "Default")
      (node (ref "IC67") (pin "2") (pinfunction "2_2") (pintype "passive"))
      (node (ref "SV154") (pin "13") (pinfunction "13_13") (pintype "passive"))
      (node (ref "SV154") (pin "14") (pinfunction "14_14") (pintype "passive"))
      (node (ref "SV155") (pin "13") (pinfunction "13_13") (pintype "passive"))
      (node (ref "SV155") (pin "14") (pinfunction "14_14") (pintype "passive"))
    )
    (net (code "1065") (name "Net-(IC67-Pad3)") (class "Default")
      (node (ref "IC67") (pin "3") (pinfunction "3_3") (pintype "passive"))
      (node (ref "SV154") (pin "11") (pinfunction "11_11") (pintype "passive"))
      (node (ref "SV154") (pin "12") (pinfunction "12_12") (pintype "passive"))
      (node (ref "SV155") (pin "11") (pinfunction "11_11") (pintype "passive"))
      (node (ref "SV155") (pin "12") (pinfunction "12_12") (pintype "passive"))
    )
    (net (code "1066") (name "Net-(IC67-Pad4)") (class "Default")
      (node (ref "IC67") (pin "4") (pinfunction "4_4") (pintype "passive"))
      (node (ref "SV154") (pin "10") (pinfunction "10_10") (pintype "passive"))
      (node (ref "SV154") (pin "9") (pinfunction "9_9") (pintype "passive"))
      (node (ref "SV155") (pin "10") (pinfunction "10_10") (pintype "passive"))
      (node (ref "SV155") (pin "9") (pinfunction "9_9") (pintype "passive"))
    )
    (net (code "1067") (name "Net-(IC67-Pad5)") (class "Default")
      (node (ref "IC67") (pin "5") (pinfunction "5_5") (pintype "passive"))
      (node (ref "SV154") (pin "7") (pinfunction "7_7") (pintype "passive"))
      (node (ref "SV154") (pin "8") (pinfunction "8_8") (pintype "passive"))
      (node (ref "SV155") (pin "7") (pinfunction "7_7") (pintype "passive"))
      (node (ref "SV155") (pin "8") (pinfunction "8_8") (pintype "passive"))
    )
    (net (code "1068") (name "Net-(IC67-Pad6)") (class "Default")
      (node (ref "IC67") (pin "6") (pinfunction "6_6") (pintype "passive"))
      (node (ref "SV154") (pin "5") (pinfunction "5_5") (pintype "passive"))
      (node (ref "SV154") (pin "6") (pinfunction "6_6") (pintype "passive"))
      (node (ref "SV155") (pin "5") (pinfunction "5_5") (pintype "passive"))
      (node (ref "SV155") (pin "6") (pinfunction "6_6") (pintype "passive"))
    )
    (net (code "1069") (name "Net-(IC67-Pad7)") (class "Default")
      (node (ref "IC67") (pin "7") (pinfunction "7_7") (pintype "passive"))
      (node (ref "SV154") (pin "3") (pinfunction "3_3") (pintype "passive"))
      (node (ref "SV154") (pin "4") (pinfunction "4_4") (pintype "passive"))
      (node (ref "SV155") (pin "3") (pinfunction "3_3") (pintype "passive"))
      (node (ref "SV155") (pin "4") (pinfunction "4_4") (pintype "passive"))
    )
    (net (code "1070") (name "Net-(IC67-Pad8)") (class "Default")
      (node (ref "IC67") (pin "8") (pinfunction "8_8") (pintype "passive"))
      (node (ref "SV154") (pin "1") (pinfunction "1_1") (pintype "passive"))
      (node (ref "SV154") (pin "2") (pinfunction "2_2") (pintype "passive"))
      (node (ref "SV155") (pin "1") (pinfunction "1_1") (pintype "passive"))
      (node (ref "SV155") (pin "2") (pinfunction "2_2") (pintype "passive"))
    )
    (net (code "1071") (name "Net-(IC67-Pad9)") (class "Default")
      (node (ref "IC67") (pin "9") (pinfunction "9_9") (pintype "passive"))
      (node (ref "SV153") (pin "1") (pinfunction "1_1") (pintype "passive"))
      (node (ref "SV153") (pin "2") (pinfunction "2_2") (pintype "passive"))
      (node (ref "SV156") (pin "8") (pinfunction "8_8") (pintype "passive"))
    )
    (net (code "1072") (name "Net-(IC67-Pad10)") (class "Default")
      (node (ref "IC67") (pin "10") (pinfunction "10_10") (pintype "passive"))
      (node (ref "SV153") (pin "3") (pinfunction "3_3") (pintype "passive"))
      (node (ref "SV153") (pin "4") (pinfunction "4_4") (pintype "passive"))
      (node (ref "SV156") (pin "7") (pinfunction "7_7") (pintype "passive"))
    )
    (net (code "1073") (name "Net-(IC67-Pad11)") (class "Default")
      (node (ref "IC67") (pin "11") (pinfunction "11_11") (pintype "passive"))
      (node (ref "SV153") (pin "5") (pinfunction "5_5") (pintype "passive"))
      (node (ref "SV153") (pin "6") (pinfunction "6_6") (pintype "passive"))
      (node (ref "SV156") (pin "6") (pinfunction "6_6") (pintype "passive"))
    )
    (net (code "1074") (name "Net-(IC67-Pad12)") (class "Default")
      (node (ref "IC67") (pin "12") (pinfunction "12_12") (pintype "passive"))
      (node (ref "SV153") (pin "7") (pinfunction "7_7") (pintype "passive"))
      (node (ref "SV153") (pin "8") (pinfunction "8_8") (pintype "passive"))
      (node (ref "SV156") (pin "5") (pinfunction "5_5") (pintype "passive"))
    )
    (net (code "1075") (name "Net-(IC67-Pad13)") (class "Default")
      (node (ref "IC67") (pin "13") (pinfunction "13_13") (pintype "passive"))
      (node (ref "SV153") (pin "10") (pinfunction "10_10") (pintype "passive"))
      (node (ref "SV153") (pin "9") (pinfunction "9_9") (pintype "passive"))
      (node (ref "SV156") (pin "4") (pinfunction "4_4") (pintype "passive"))
    )
    (net (code "1076") (name "Net-(IC67-Pad14)") (class "Default")
      (node (ref "IC67") (pin "14") (pinfunction "14_14") (pintype "passive"))
      (node (ref "SV153") (pin "11") (pinfunction "11_11") (pintype "passive"))
      (node (ref "SV153") (pin "12") (pinfunction "12_12") (pintype "passive"))
      (node (ref "SV156") (pin "3") (pinfunction "3_3") (pintype "passive"))
    )
    (net (code "1077") (name "Net-(IC67-Pad15)") (class "Default")
      (node (ref "IC67") (pin "15") (pinfunction "15_15") (pintype "passive"))
      (node (ref "SV153") (pin "13") (pinfunction "13_13") (pintype "passive"))
      (node (ref "SV153") (pin "14") (pinfunction "14_14") (pintype "passive"))
      (node (ref "SV156") (pin "2") (pinfunction "2_2") (pintype "passive"))
    )
    (net (code "1078") (name "Net-(IC67-Pad16)") (class "Default")
      (node (ref "IC67") (pin "16") (pinfunction "16_16") (pintype "passive"))
      (node (ref "SV153") (pin "15") (pinfunction "15_15") (pintype "passive"))
      (node (ref "SV153") (pin "16") (pinfunction "16_16") (pintype "passive"))
      (node (ref "SV156") (pin "1") (pinfunction "1_1") (pintype "passive"))
    )
    (net (code "1079") (name "Net-(IC68-Pad1)") (class "Default")
      (node (ref "IC68") (pin "1") (pinfunction "1_1") (pintype "passive"))
      (node (ref "SV158") (pin "15") (pinfunction "15_15") (pintype "passive"))
      (node (ref "SV158") (pin "16") (pinfunction "16_16") (pintype "passive"))
      (node (ref "SV159") (pin "15") (pinfunction "15_15") (pintype "passive"))
      (node (ref "SV159") (pin "16") (pinfunction "16_16") (pintype "passive"))
    )
    (net (code "1080") (name "Net-(IC68-Pad2)") (class "Default")
      (node (ref "IC68") (pin "2") (pinfunction "2_2") (pintype "passive"))
      (node (ref "SV158") (pin "13") (pinfunction "13_13") (pintype "passive"))
      (node (ref "SV158") (pin "14") (pinfunction "14_14") (pintype "passive"))
      (node (ref "SV159") (pin "13") (pinfunction "13_13") (pintype "passive"))
      (node (ref "SV159") (pin "14") (pinfunction "14_14") (pintype "passive"))
    )
    (net (code "1081") (name "Net-(IC68-Pad3)") (class "Default")
      (node (ref "IC68") (pin "3") (pinfunction "3_3") (pintype "passive"))
      (node (ref "SV158") (pin "11") (pinfunction "11_11") (pintype "passive"))
      (node (ref "SV158") (pin "12") (pinfunction "12_12") (pintype "passive"))
      (node (ref "SV159") (pin "11") (pinfunction "11_11") (pintype "passive"))
      (node (ref "SV159") (pin "12") (pinfunction "12_12") (pintype "passive"))
    )
    (net (code "1082") (name "Net-(IC68-Pad4)") (class "Default")
      (node (ref "IC68") (pin "4") (pinfunction "4_4") (pintype "passive"))
      (node (ref "SV158") (pin "10") (pinfunction "10_10") (pintype "passive"))
      (node (ref "SV158") (pin "9") (pinfunction "9_9") (pintype "passive"))
      (node (ref "SV159") (pin "10") (pinfunction "10_10") (pintype "passive"))
      (node (ref "SV159") (pin "9") (pinfunction "9_9") (pintype "passive"))
    )
    (net (code "1083") (name "Net-(IC68-Pad5)") (class "Default")
      (node (ref "IC68") (pin "5") (pinfunction "5_5") (pintype "passive"))
      (node (ref "SV158") (pin "7") (pinfunction "7_7") (pintype "passive"))
      (node (ref "SV158") (pin "8") (pinfunction "8_8") (pintype "passive"))
      (node (ref "SV159") (pin "7") (pinfunction "7_7") (pintype "passive"))
      (node (ref "SV159") (pin "8") (pinfunction "8_8") (pintype "passive"))
    )
    (net (code "1084") (name "Net-(IC68-Pad6)") (class "Default")
      (node (ref "IC68") (pin "6") (pinfunction "6_6") (pintype "passive"))
      (node (ref "SV158") (pin "5") (pinfunction "5_5") (pintype "passive"))
      (node (ref "SV158") (pin "6") (pinfunction "6_6") (pintype "passive"))
      (node (ref "SV159") (pin "5") (pinfunction "5_5") (pintype "passive"))
      (node (ref "SV159") (pin "6") (pinfunction "6_6") (pintype "passive"))
    )
    (net (code "1085") (name "Net-(IC68-Pad7)") (class "Default")
      (node (ref "IC68") (pin "7") (pinfunction "7_7") (pintype "passive"))
      (node (ref "SV158") (pin "3") (pinfunction "3_3") (pintype "passive"))
      (node (ref "SV158") (pin "4") (pinfunction "4_4") (pintype "passive"))
      (node (ref "SV159") (pin "3") (pinfunction "3_3") (pintype "passive"))
      (node (ref "SV159") (pin "4") (pinfunction "4_4") (pintype "passive"))
    )
    (net (code "1086") (name "Net-(IC68-Pad8)") (class "Default")
      (node (ref "IC68") (pin "8") (pinfunction "8_8") (pintype "passive"))
      (node (ref "SV158") (pin "1") (pinfunction "1_1") (pintype "passive"))
      (node (ref "SV158") (pin "2") (pinfunction "2_2") (pintype "passive"))
      (node (ref "SV159") (pin "1") (pinfunction "1_1") (pintype "passive"))
      (node (ref "SV159") (pin "2") (pinfunction "2_2") (pintype "passive"))
    )
    (net (code "1087") (name "Net-(IC68-Pad9)") (class "Default")
      (node (ref "IC68") (pin "9") (pinfunction "9_9") (pintype "passive"))
      (node (ref "SV157") (pin "1") (pinfunction "1_1") (pintype "passive"))
      (node (ref "SV157") (pin "2") (pinfunction "2_2") (pintype "passive"))
      (node (ref "SV160") (pin "8") (pinfunction "8_8") (pintype "passive"))
    )
    (net (code "1088") (name "Net-(IC68-Pad10)") (class "Default")
      (node (ref "IC68") (pin "10") (pinfunction "10_10") (pintype "passive"))
      (node (ref "SV157") (pin "3") (pinfunction "3_3") (pintype "passive"))
      (node (ref "SV157") (pin "4") (pinfunction "4_4") (pintype "passive"))
      (node (ref "SV160") (pin "7") (pinfunction "7_7") (pintype "passive"))
    )
    (net (code "1089") (name "Net-(IC68-Pad11)") (class "Default")
      (node (ref "IC68") (pin "11") (pinfunction "11_11") (pintype "passive"))
      (node (ref "SV157") (pin "5") (pinfunction "5_5") (pintype "passive"))
      (node (ref "SV157") (pin "6") (pinfunction "6_6") (pintype "passive"))
      (node (ref "SV160") (pin "6") (pinfunction "6_6") (pintype "passive"))
    )
    (net (code "1090") (name "Net-(IC68-Pad12)") (class "Default")
      (node (ref "IC68") (pin "12") (pinfunction "12_12") (pintype "passive"))
      (node (ref "SV157") (pin "7") (pinfunction "7_7") (pintype "passive"))
      (node (ref "SV157") (pin "8") (pinfunction "8_8") (pintype "passive"))
      (node (ref "SV160") (pin "5") (pinfunction "5_5") (pintype "passive"))
    )
    (net (code "1091") (name "Net-(IC68-Pad13)") (class "Default")
      (node (ref "IC68") (pin "13") (pinfunction "13_13") (pintype "passive"))
      (node (ref "SV157") (pin "10") (pinfunction "10_10") (pintype "passive"))
      (node (ref "SV157") (pin "9") (pinfunction "9_9") (pintype "passive"))
      (node (ref "SV160") (pin "4") (pinfunction "4_4") (pintype "passive"))
    )
    (net (code "1092") (name "Net-(IC68-Pad14)") (class "Default")
      (node (ref "IC68") (pin "14") (pinfunction "14_14") (pintype "passive"))
      (node (ref "SV157") (pin "11") (pinfunction "11_11") (pintype "passive"))
      (node (ref "SV157") (pin "12") (pinfunction "12_12") (pintype "passive"))
      (node (ref "SV160") (pin "3") (pinfunction "3_3") (pintype "passive"))
    )
    (net (code "1093") (name "Net-(IC68-Pad15)") (class "Default")
      (node (ref "IC68") (pin "15") (pinfunction "15_15") (pintype "passive"))
      (node (ref "SV157") (pin "13") (pinfunction "13_13") (pintype "passive"))
      (node (ref "SV157") (pin "14") (pinfunction "14_14") (pintype "passive"))
      (node (ref "SV160") (pin "2") (pinfunction "2_2") (pintype "passive"))
    )
    (net (code "1094") (name "Net-(IC68-Pad16)") (class "Default")
      (node (ref "IC68") (pin "16") (pinfunction "16_16") (pintype "passive"))
      (node (ref "SV157") (pin "15") (pinfunction "15_15") (pintype "passive"))
      (node (ref "SV157") (pin "16") (pinfunction "16_16") (pintype "passive"))
      (node (ref "SV160") (pin "1") (pinfunction "1_1") (pintype "passive"))
    )
    (net (code "1095") (name "Net-(IC69-Pad1)") (class "Default")
      (node (ref "IC69") (pin "1") (pinfunction "1_1") (pintype "passive"))
      (node (ref "SV162") (pin "15") (pinfunction "15_15") (pintype "passive"))
      (node (ref "SV162") (pin "16") (pinfunction "16_16") (pintype "passive"))
      (node (ref "SV163") (pin "15") (pinfunction "15_15") (pintype "passive"))
      (node (ref "SV163") (pin "16") (pinfunction "16_16") (pintype "passive"))
    )
    (net (code "1096") (name "Net-(IC69-Pad2)") (class "Default")
      (node (ref "IC69") (pin "2") (pinfunction "2_2") (pintype "passive"))
      (node (ref "SV162") (pin "13") (pinfunction "13_13") (pintype "passive"))
      (node (ref "SV162") (pin "14") (pinfunction "14_14") (pintype "passive"))
      (node (ref "SV163") (pin "13") (pinfunction "13_13") (pintype "passive"))
      (node (ref "SV163") (pin "14") (pinfunction "14_14") (pintype "passive"))
    )
    (net (code "1097") (name "Net-(IC69-Pad3)") (class "Default")
      (node (ref "IC69") (pin "3") (pinfunction "3_3") (pintype "passive"))
      (node (ref "SV162") (pin "11") (pinfunction "11_11") (pintype "passive"))
      (node (ref "SV162") (pin "12") (pinfunction "12_12") (pintype "passive"))
      (node (ref "SV163") (pin "11") (pinfunction "11_11") (pintype "passive"))
      (node (ref "SV163") (pin "12") (pinfunction "12_12") (pintype "passive"))
    )
    (net (code "1098") (name "Net-(IC69-Pad4)") (class "Default")
      (node (ref "IC69") (pin "4") (pinfunction "4_4") (pintype "passive"))
      (node (ref "SV162") (pin "10") (pinfunction "10_10") (pintype "passive"))
      (node (ref "SV162") (pin "9") (pinfunction "9_9") (pintype "passive"))
      (node (ref "SV163") (pin "10") (pinfunction "10_10") (pintype "passive"))
      (node (ref "SV163") (pin "9") (pinfunction "9_9") (pintype "passive"))
    )
    (net (code "1099") (name "Net-(IC69-Pad5)") (class "Default")
      (node (ref "IC69") (pin "5") (pinfunction "5_5") (pintype "passive"))
      (node (ref "SV162") (pin "7") (pinfunction "7_7") (pintype "passive"))
      (node (ref "SV162") (pin "8") (pinfunction "8_8") (pintype "passive"))
      (node (ref "SV163") (pin "7") (pinfunction "7_7") (pintype "passive"))
      (node (ref "SV163") (pin "8") (pinfunction "8_8") (pintype "passive"))
    )
    (net (code "1100") (name "Net-(IC69-Pad6)") (class "Default")
      (node (ref "IC69") (pin "6") (pinfunction "6_6") (pintype "passive"))
      (node (ref "SV162") (pin "5") (pinfunction "5_5") (pintype "passive"))
      (node (ref "SV162") (pin "6") (pinfunction "6_6") (pintype "passive"))
      (node (ref "SV163") (pin "5") (pinfunction "5_5") (pintype "passive"))
      (node (ref "SV163") (pin "6") (pinfunction "6_6") (pintype "passive"))
    )
    (net (code "1101") (name "Net-(IC69-Pad7)") (class "Default")
      (node (ref "IC69") (pin "7") (pinfunction "7_7") (pintype "passive"))
      (node (ref "SV162") (pin "3") (pinfunction "3_3") (pintype "passive"))
      (node (ref "SV162") (pin "4") (pinfunction "4_4") (pintype "passive"))
      (node (ref "SV163") (pin "3") (pinfunction "3_3") (pintype "passive"))
      (node (ref "SV163") (pin "4") (pinfunction "4_4") (pintype "passive"))
    )
    (net (code "1102") (name "Net-(IC69-Pad8)") (class "Default")
      (node (ref "IC69") (pin "8") (pinfunction "8_8") (pintype "passive"))
      (node (ref "SV162") (pin "1") (pinfunction "1_1") (pintype "passive"))
      (node (ref "SV162") (pin "2") (pinfunction "2_2") (pintype "passive"))
      (node (ref "SV163") (pin "1") (pinfunction "1_1") (pintype "passive"))
      (node (ref "SV163") (pin "2") (pinfunction "2_2") (pintype "passive"))
    )
    (net (code "1103") (name "Net-(IC69-Pad9)") (class "Default")
      (node (ref "IC69") (pin "9") (pinfunction "9_9") (pintype "passive"))
      (node (ref "SV161") (pin "1") (pinfunction "1_1") (pintype "passive"))
      (node (ref "SV161") (pin "2") (pinfunction "2_2") (pintype "passive"))
      (node (ref "SV164") (pin "8") (pinfunction "8_8") (pintype "passive"))
    )
    (net (code "1104") (name "Net-(IC69-Pad10)") (class "Default")
      (node (ref "IC69") (pin "10") (pinfunction "10_10") (pintype "passive"))
      (node (ref "SV161") (pin "3") (pinfunction "3_3") (pintype "passive"))
      (node (ref "SV161") (pin "4") (pinfunction "4_4") (pintype "passive"))
      (node (ref "SV164") (pin "7") (pinfunction "7_7") (pintype "passive"))
    )
    (net (code "1105") (name "Net-(IC69-Pad11)") (class "Default")
      (node (ref "IC69") (pin "11") (pinfunction "11_11") (pintype "passive"))
      (node (ref "SV161") (pin "5") (pinfunction "5_5") (pintype "passive"))
      (node (ref "SV161") (pin "6") (pinfunction "6_6") (pintype "passive"))
      (node (ref "SV164") (pin "6") (pinfunction "6_6") (pintype "passive"))
    )
    (net (code "1106") (name "Net-(IC69-Pad12)") (class "Default")
      (node (ref "IC69") (pin "12") (pinfunction "12_12") (pintype "passive"))
      (node (ref "SV161") (pin "7") (pinfunction "7_7") (pintype "passive"))
      (node (ref "SV161") (pin "8") (pinfunction "8_8") (pintype "passive"))
      (node (ref "SV164") (pin "5") (pinfunction "5_5") (pintype "passive"))
    )
    (net (code "1107") (name "Net-(IC69-Pad13)") (class "Default")
      (node (ref "IC69") (pin "13") (pinfunction "13_13") (pintype "passive"))
      (node (ref "SV161") (pin "10") (pinfunction "10_10") (pintype "passive"))
      (node (ref "SV161") (pin "9") (pinfunction "9_9") (pintype "passive"))
      (node (ref "SV164") (pin "4") (pinfunction "4_4") (pintype "passive"))
    )
    (net (code "1108") (name "Net-(IC69-Pad14)") (class "Default")
      (node (ref "IC69") (pin "14") (pinfunction "14_14") (pintype "passive"))
      (node (ref "SV161") (pin "11") (pinfunction "11_11") (pintype "passive"))
      (node (ref "SV161") (pin "12") (pinfunction "12_12") (pintype "passive"))
      (node (ref "SV164") (pin "3") (pinfunction "3_3") (pintype "passive"))
    )
    (net (code "1109") (name "Net-(IC69-Pad15)") (class "Default")
      (node (ref "IC69") (pin "15") (pinfunction "15_15") (pintype "passive"))
      (node (ref "SV161") (pin "13") (pinfunction "13_13") (pintype "passive"))
      (node (ref "SV161") (pin "14") (pinfunction "14_14") (pintype "passive"))
      (node (ref "SV164") (pin "2") (pinfunction "2_2") (pintype "passive"))
    )
    (net (code "1110") (name "Net-(IC69-Pad16)") (class "Default")
      (node (ref "IC69") (pin "16") (pinfunction "16_16") (pintype "passive"))
      (node (ref "SV161") (pin "15") (pinfunction "15_15") (pintype "passive"))
      (node (ref "SV161") (pin "16") (pinfunction "16_16") (pintype "passive"))
      (node (ref "SV164") (pin "1") (pinfunction "1_1") (pintype "passive"))
    )
    (net (code "1111") (name "Net-(IC70-Pad1)") (class "Default")
      (node (ref "IC70") (pin "1") (pinfunction "1_1") (pintype "passive"))
      (node (ref "SV166") (pin "15") (pinfunction "15_15") (pintype "passive"))
      (node (ref "SV166") (pin "16") (pinfunction "16_16") (pintype "passive"))
      (node (ref "SV167") (pin "15") (pinfunction "15_15") (pintype "passive"))
      (node (ref "SV167") (pin "16") (pinfunction "16_16") (pintype "passive"))
    )
    (net (code "1112") (name "Net-(IC70-Pad2)") (class "Default")
      (node (ref "IC70") (pin "2") (pinfunction "2_2") (pintype "passive"))
      (node (ref "SV166") (pin "13") (pinfunction "13_13") (pintype "passive"))
      (node (ref "SV166") (pin "14") (pinfunction "14_14") (pintype "passive"))
      (node (ref "SV167") (pin "13") (pinfunction "13_13") (pintype "passive"))
      (node (ref "SV167") (pin "14") (pinfunction "14_14") (pintype "passive"))
    )
    (net (code "1113") (name "Net-(IC70-Pad3)") (class "Default")
      (node (ref "IC70") (pin "3") (pinfunction "3_3") (pintype "passive"))
      (node (ref "SV166") (pin "11") (pinfunction "11_11") (pintype "passive"))
      (node (ref "SV166") (pin "12") (pinfunction "12_12") (pintype "passive"))
      (node (ref "SV167") (pin "11") (pinfunction "11_11") (pintype "passive"))
      (node (ref "SV167") (pin "12") (pinfunction "12_12") (pintype "passive"))
    )
    (net (code "1114") (name "Net-(IC70-Pad4)") (class "Default")
      (node (ref "IC70") (pin "4") (pinfunction "4_4") (pintype "passive"))
      (node (ref "SV166") (pin "10") (pinfunction "10_10") (pintype "passive"))
      (node (ref "SV166") (pin "9") (pinfunction "9_9") (pintype "passive"))
      (node (ref "SV167") (pin "10") (pinfunction "10_10") (pintype "passive"))
      (node (ref "SV167") (pin "9") (pinfunction "9_9") (pintype "passive"))
    )
    (net (code "1115") (name "Net-(IC70-Pad5)") (class "Default")
      (node (ref "IC70") (pin "5") (pinfunction "5_5") (pintype "passive"))
      (node (ref "SV166") (pin "7") (pinfunction "7_7") (pintype "passive"))
      (node (ref "SV166") (pin "8") (pinfunction "8_8") (pintype "passive"))
      (node (ref "SV167") (pin "7") (pinfunction "7_7") (pintype "passive"))
      (node (ref "SV167") (pin "8") (pinfunction "8_8") (pintype "passive"))
    )
    (net (code "1116") (name "Net-(IC70-Pad6)") (class "Default")
      (node (ref "IC70") (pin "6") (pinfunction "6_6") (pintype "passive"))
      (node (ref "SV166") (pin "5") (pinfunction "5_5") (pintype "passive"))
      (node (ref "SV166") (pin "6") (pinfunction "6_6") (pintype "passive"))
      (node (ref "SV167") (pin "5") (pinfunction "5_5") (pintype "passive"))
      (node (ref "SV167") (pin "6") (pinfunction "6_6") (pintype "passive"))
    )
    (net (code "1117") (name "Net-(IC70-Pad7)") (class "Default")
      (node (ref "IC70") (pin "7") (pinfunction "7_7") (pintype "passive"))
      (node (ref "SV166") (pin "3") (pinfunction "3_3") (pintype "passive"))
      (node (ref "SV166") (pin "4") (pinfunction "4_4") (pintype "passive"))
      (node (ref "SV167") (pin "3") (pinfunction "3_3") (pintype "passive"))
      (node (ref "SV167") (pin "4") (pinfunction "4_4") (pintype "passive"))
    )
    (net (code "1118") (name "Net-(IC70-Pad8)") (class "Default")
      (node (ref "IC70") (pin "8") (pinfunction "8_8") (pintype "passive"))
      (node (ref "SV166") (pin "1") (pinfunction "1_1") (pintype "passive"))
      (node (ref "SV166") (pin "2") (pinfunction "2_2") (pintype "passive"))
      (node (ref "SV167") (pin "1") (pinfunction "1_1") (pintype "passive"))
      (node (ref "SV167") (pin "2") (pinfunction "2_2") (pintype "passive"))
    )
    (net (code "1119") (name "Net-(IC70-Pad9)") (class "Default")
      (node (ref "IC70") (pin "9") (pinfunction "9_9") (pintype "passive"))
      (node (ref "SV165") (pin "1") (pinfunction "1_1") (pintype "passive"))
      (node (ref "SV165") (pin "2") (pinfunction "2_2") (pintype "passive"))
      (node (ref "SV168") (pin "8") (pinfunction "8_8") (pintype "passive"))
    )
    (net (code "1120") (name "Net-(IC70-Pad10)") (class "Default")
      (node (ref "IC70") (pin "10") (pinfunction "10_10") (pintype "passive"))
      (node (ref "SV165") (pin "3") (pinfunction "3_3") (pintype "passive"))
      (node (ref "SV165") (pin "4") (pinfunction "4_4") (pintype "passive"))
      (node (ref "SV168") (pin "7") (pinfunction "7_7") (pintype "passive"))
    )
    (net (code "1121") (name "Net-(IC70-Pad11)") (class "Default")
      (node (ref "IC70") (pin "11") (pinfunction "11_11") (pintype "passive"))
      (node (ref "SV165") (pin "5") (pinfunction "5_5") (pintype "passive"))
      (node (ref "SV165") (pin "6") (pinfunction "6_6") (pintype "passive"))
      (node (ref "SV168") (pin "6") (pinfunction "6_6") (pintype "passive"))
    )
    (net (code "1122") (name "Net-(IC70-Pad12)") (class "Default")
      (node (ref "IC70") (pin "12") (pinfunction "12_12") (pintype "passive"))
      (node (ref "SV165") (pin "7") (pinfunction "7_7") (pintype "passive"))
      (node (ref "SV165") (pin "8") (pinfunction "8_8") (pintype "passive"))
      (node (ref "SV168") (pin "5") (pinfunction "5_5") (pintype "passive"))
    )
    (net (code "1123") (name "Net-(IC70-Pad13)") (class "Default")
      (node (ref "IC70") (pin "13") (pinfunction "13_13") (pintype "passive"))
      (node (ref "SV165") (pin "10") (pinfunction "10_10") (pintype "passive"))
      (node (ref "SV165") (pin "9") (pinfunction "9_9") (pintype "passive"))
      (node (ref "SV168") (pin "4") (pinfunction "4_4") (pintype "passive"))
    )
    (net (code "1124") (name "Net-(IC70-Pad14)") (class "Default")
      (node (ref "IC70") (pin "14") (pinfunction "14_14") (pintype "passive"))
      (node (ref "SV165") (pin "11") (pinfunction "11_11") (pintype "passive"))
      (node (ref "SV165") (pin "12") (pinfunction "12_12") (pintype "passive"))
      (node (ref "SV168") (pin "3") (pinfunction "3_3") (pintype "passive"))
    )
    (net (code "1125") (name "Net-(IC70-Pad15)") (class "Default")
      (node (ref "IC70") (pin "15") (pinfunction "15_15") (pintype "passive"))
      (node (ref "SV165") (pin "13") (pinfunction "13_13") (pintype "passive"))
      (node (ref "SV165") (pin "14") (pinfunction "14_14") (pintype "passive"))
      (node (ref "SV168") (pin "2") (pinfunction "2_2") (pintype "passive"))
    )
    (net (code "1126") (name "Net-(IC70-Pad16)") (class "Default")
      (node (ref "IC70") (pin "16") (pinfunction "16_16") (pintype "passive"))
      (node (ref "SV165") (pin "15") (pinfunction "15_15") (pintype "passive"))
      (node (ref "SV165") (pin "16") (pinfunction "16_16") (pintype "passive"))
      (node (ref "SV168") (pin "1") (pinfunction "1_1") (pintype "passive"))
    )
    (net (code "1127") (name "Net-(IC71-Pad1)") (class "Default")
      (node (ref "IC71") (pin "1") (pinfunction "1_1") (pintype "passive"))
      (node (ref "SV170") (pin "15") (pinfunction "15_15") (pintype "passive"))
      (node (ref "SV170") (pin "16") (pinfunction "16_16") (pintype "passive"))
      (node (ref "SV171") (pin "15") (pinfunction "15_15") (pintype "passive"))
      (node (ref "SV171") (pin "16") (pinfunction "16_16") (pintype "passive"))
    )
    (net (code "1128") (name "Net-(IC71-Pad2)") (class "Default")
      (node (ref "IC71") (pin "2") (pinfunction "2_2") (pintype "passive"))
      (node (ref "SV170") (pin "13") (pinfunction "13_13") (pintype "passive"))
      (node (ref "SV170") (pin "14") (pinfunction "14_14") (pintype "passive"))
      (node (ref "SV171") (pin "13") (pinfunction "13_13") (pintype "passive"))
      (node (ref "SV171") (pin "14") (pinfunction "14_14") (pintype "passive"))
    )
    (net (code "1129") (name "Net-(IC71-Pad3)") (class "Default")
      (node (ref "IC71") (pin "3") (pinfunction "3_3") (pintype "passive"))
      (node (ref "SV170") (pin "11") (pinfunction "11_11") (pintype "passive"))
      (node (ref "SV170") (pin "12") (pinfunction "12_12") (pintype "passive"))
      (node (ref "SV171") (pin "11") (pinfunction "11_11") (pintype "passive"))
      (node (ref "SV171") (pin "12") (pinfunction "12_12") (pintype "passive"))
    )
    (net (code "1130") (name "Net-(IC71-Pad4)") (class "Default")
      (node (ref "IC71") (pin "4") (pinfunction "4_4") (pintype "passive"))
      (node (ref "SV170") (pin "10") (pinfunction "10_10") (pintype "passive"))
      (node (ref "SV170") (pin "9") (pinfunction "9_9") (pintype "passive"))
      (node (ref "SV171") (pin "10") (pinfunction "10_10") (pintype "passive"))
      (node (ref "SV171") (pin "9") (pinfunction "9_9") (pintype "passive"))
    )
    (net (code "1131") (name "Net-(IC71-Pad5)") (class "Default")
      (node (ref "IC71") (pin "5") (pinfunction "5_5") (pintype "passive"))
      (node (ref "SV170") (pin "7") (pinfunction "7_7") (pintype "passive"))
      (node (ref "SV170") (pin "8") (pinfunction "8_8") (pintype "passive"))
      (node (ref "SV171") (pin "7") (pinfunction "7_7") (pintype "passive"))
      (node (ref "SV171") (pin "8") (pinfunction "8_8") (pintype "passive"))
    )
    (net (code "1132") (name "Net-(IC71-Pad6)") (class "Default")
      (node (ref "IC71") (pin "6") (pinfunction "6_6") (pintype "passive"))
      (node (ref "SV170") (pin "5") (pinfunction "5_5") (pintype "passive"))
      (node (ref "SV170") (pin "6") (pinfunction "6_6") (pintype "passive"))
      (node (ref "SV171") (pin "5") (pinfunction "5_5") (pintype "passive"))
      (node (ref "SV171") (pin "6") (pinfunction "6_6") (pintype "passive"))
    )
    (net (code "1133") (name "Net-(IC71-Pad7)") (class "Default")
      (node (ref "IC71") (pin "7") (pinfunction "7_7") (pintype "passive"))
      (node (ref "SV170") (pin "3") (pinfunction "3_3") (pintype "passive"))
      (node (ref "SV170") (pin "4") (pinfunction "4_4") (pintype "passive"))
      (node (ref "SV171") (pin "3") (pinfunction "3_3") (pintype "passive"))
      (node (ref "SV171") (pin "4") (pinfunction "4_4") (pintype "passive"))
    )
    (net (code "1134") (name "Net-(IC71-Pad8)") (class "Default")
      (node (ref "IC71") (pin "8") (pinfunction "8_8") (pintype "passive"))
      (node (ref "SV170") (pin "1") (pinfunction "1_1") (pintype "passive"))
      (node (ref "SV170") (pin "2") (pinfunction "2_2") (pintype "passive"))
      (node (ref "SV171") (pin "1") (pinfunction "1_1") (pintype "passive"))
      (node (ref "SV171") (pin "2") (pinfunction "2_2") (pintype "passive"))
    )
    (net (code "1135") (name "Net-(IC71-Pad9)") (class "Default")
      (node (ref "IC71") (pin "9") (pinfunction "9_9") (pintype "passive"))
      (node (ref "SV169") (pin "1") (pinfunction "1_1") (pintype "passive"))
      (node (ref "SV169") (pin "2") (pinfunction "2_2") (pintype "passive"))
      (node (ref "SV172") (pin "8") (pinfunction "8_8") (pintype "passive"))
    )
    (net (code "1136") (name "Net-(IC71-Pad10)") (class "Default")
      (node (ref "IC71") (pin "10") (pinfunction "10_10") (pintype "passive"))
      (node (ref "SV169") (pin "3") (pinfunction "3_3") (pintype "passive"))
      (node (ref "SV169") (pin "4") (pinfunction "4_4") (pintype "passive"))
      (node (ref "SV172") (pin "7") (pinfunction "7_7") (pintype "passive"))
    )
    (net (code "1137") (name "Net-(IC71-Pad11)") (class "Default")
      (node (ref "IC71") (pin "11") (pinfunction "11_11") (pintype "passive"))
      (node (ref "SV169") (pin "5") (pinfunction "5_5") (pintype "passive"))
      (node (ref "SV169") (pin "6") (pinfunction "6_6") (pintype "passive"))
      (node (ref "SV172") (pin "6") (pinfunction "6_6") (pintype "passive"))
    )
    (net (code "1138") (name "Net-(IC71-Pad12)") (class "Default")
      (node (ref "IC71") (pin "12") (pinfunction "12_12") (pintype "passive"))
      (node (ref "SV169") (pin "7") (pinfunction "7_7") (pintype "passive"))
      (node (ref "SV169") (pin "8") (pinfunction "8_8") (pintype "passive"))
      (node (ref "SV172") (pin "5") (pinfunction "5_5") (pintype "passive"))
    )
    (net (code "1139") (name "Net-(IC71-Pad13)") (class "Default")
      (node (ref "IC71") (pin "13") (pinfunction "13_13") (pintype "passive"))
      (node (ref "SV169") (pin "10") (pinfunction "10_10") (pintype "passive"))
      (node (ref "SV169") (pin "9") (pinfunction "9_9") (pintype "passive"))
      (node (ref "SV172") (pin "4") (pinfunction "4_4") (pintype "passive"))
    )
    (net (code "1140") (name "Net-(IC71-Pad14)") (class "Default")
      (node (ref "IC71") (pin "14") (pinfunction "14_14") (pintype "passive"))
      (node (ref "SV169") (pin "11") (pinfunction "11_11") (pintype "passive"))
      (node (ref "SV169") (pin "12") (pinfunction "12_12") (pintype "passive"))
      (node (ref "SV172") (pin "3") (pinfunction "3_3") (pintype "passive"))
    )
    (net (code "1141") (name "Net-(IC71-Pad15)") (class "Default")
      (node (ref "IC71") (pin "15") (pinfunction "15_15") (pintype "passive"))
      (node (ref "SV169") (pin "13") (pinfunction "13_13") (pintype "passive"))
      (node (ref "SV169") (pin "14") (pinfunction "14_14") (pintype "passive"))
      (node (ref "SV172") (pin "2") (pinfunction "2_2") (pintype "passive"))
    )
    (net (code "1142") (name "Net-(IC71-Pad16)") (class "Default")
      (node (ref "IC71") (pin "16") (pinfunction "16_16") (pintype "passive"))
      (node (ref "SV169") (pin "15") (pinfunction "15_15") (pintype "passive"))
      (node (ref "SV169") (pin "16") (pinfunction "16_16") (pintype "passive"))
      (node (ref "SV172") (pin "1") (pinfunction "1_1") (pintype "passive"))
    )
    (net (code "1143") (name "Net-(IC72-Pad1)") (class "Default")
      (node (ref "IC72") (pin "1") (pinfunction "1_1") (pintype "passive"))
      (node (ref "SV174") (pin "15") (pinfunction "15_15") (pintype "passive"))
      (node (ref "SV174") (pin "16") (pinfunction "16_16") (pintype "passive"))
      (node (ref "SV175") (pin "15") (pinfunction "15_15") (pintype "passive"))
      (node (ref "SV175") (pin "16") (pinfunction "16_16") (pintype "passive"))
    )
    (net (code "1144") (name "Net-(IC72-Pad2)") (class "Default")
      (node (ref "IC72") (pin "2") (pinfunction "2_2") (pintype "passive"))
      (node (ref "SV174") (pin "13") (pinfunction "13_13") (pintype "passive"))
      (node (ref "SV174") (pin "14") (pinfunction "14_14") (pintype "passive"))
      (node (ref "SV175") (pin "13") (pinfunction "13_13") (pintype "passive"))
      (node (ref "SV175") (pin "14") (pinfunction "14_14") (pintype "passive"))
    )
    (net (code "1145") (name "Net-(IC72-Pad3)") (class "Default")
      (node (ref "IC72") (pin "3") (pinfunction "3_3") (pintype "passive"))
      (node (ref "SV174") (pin "11") (pinfunction "11_11") (pintype "passive"))
      (node (ref "SV174") (pin "12") (pinfunction "12_12") (pintype "passive"))
      (node (ref "SV175") (pin "11") (pinfunction "11_11") (pintype "passive"))
      (node (ref "SV175") (pin "12") (pinfunction "12_12") (pintype "passive"))
    )
    (net (code "1146") (name "Net-(IC72-Pad4)") (class "Default")
      (node (ref "IC72") (pin "4") (pinfunction "4_4") (pintype "passive"))
      (node (ref "SV174") (pin "10") (pinfunction "10_10") (pintype "passive"))
      (node (ref "SV174") (pin "9") (pinfunction "9_9") (pintype "passive"))
      (node (ref "SV175") (pin "10") (pinfunction "10_10") (pintype "passive"))
      (node (ref "SV175") (pin "9") (pinfunction "9_9") (pintype "passive"))
    )
    (net (code "1147") (name "Net-(IC72-Pad5)") (class "Default")
      (node (ref "IC72") (pin "5") (pinfunction "5_5") (pintype "passive"))
      (node (ref "SV174") (pin "7") (pinfunction "7_7") (pintype "passive"))
      (node (ref "SV174") (pin "8") (pinfunction "8_8") (pintype "passive"))
      (node (ref "SV175") (pin "7") (pinfunction "7_7") (pintype "passive"))
      (node (ref "SV175") (pin "8") (pinfunction "8_8") (pintype "passive"))
    )
    (net (code "1148") (name "Net-(IC72-Pad6)") (class "Default")
      (node (ref "IC72") (pin "6") (pinfunction "6_6") (pintype "passive"))
      (node (ref "SV174") (pin "5") (pinfunction "5_5") (pintype "passive"))
      (node (ref "SV174") (pin "6") (pinfunction "6_6") (pintype "passive"))
      (node (ref "SV175") (pin "5") (pinfunction "5_5") (pintype "passive"))
      (node (ref "SV175") (pin "6") (pinfunction "6_6") (pintype "passive"))
    )
    (net (code "1149") (name "Net-(IC72-Pad7)") (class "Default")
      (node (ref "IC72") (pin "7") (pinfunction "7_7") (pintype "passive"))
      (node (ref "SV174") (pin "3") (pinfunction "3_3") (pintype "passive"))
      (node (ref "SV174") (pin "4") (pinfunction "4_4") (pintype "passive"))
      (node (ref "SV175") (pin "3") (pinfunction "3_3") (pintype "passive"))
      (node (ref "SV175") (pin "4") (pinfunction "4_4") (pintype "passive"))
    )
    (net (code "1150") (name "Net-(IC72-Pad8)") (class "Default")
      (node (ref "IC72") (pin "8") (pinfunction "8_8") (pintype "passive"))
      (node (ref "SV174") (pin "1") (pinfunction "1_1") (pintype "passive"))
      (node (ref "SV174") (pin "2") (pinfunction "2_2") (pintype "passive"))
      (node (ref "SV175") (pin "1") (pinfunction "1_1") (pintype "passive"))
      (node (ref "SV175") (pin "2") (pinfunction "2_2") (pintype "passive"))
    )
    (net (code "1151") (name "Net-(IC72-Pad9)") (class "Default")
      (node (ref "IC72") (pin "9") (pinfunction "9_9") (pintype "passive"))
      (node (ref "SV173") (pin "1") (pinfunction "1_1") (pintype "passive"))
      (node (ref "SV173") (pin "2") (pinfunction "2_2") (pintype "passive"))
      (node (ref "SV176") (pin "8") (pinfunction "8_8") (pintype "passive"))
    )
    (net (code "1152") (name "Net-(IC72-Pad10)") (class "Default")
      (node (ref "IC72") (pin "10") (pinfunction "10_10") (pintype "passive"))
      (node (ref "SV173") (pin "3") (pinfunction "3_3") (pintype "passive"))
      (node (ref "SV173") (pin "4") (pinfunction "4_4") (pintype "passive"))
      (node (ref "SV176") (pin "7") (pinfunction "7_7") (pintype "passive"))
    )
    (net (code "1153") (name "Net-(IC72-Pad11)") (class "Default")
      (node (ref "IC72") (pin "11") (pinfunction "11_11") (pintype "passive"))
      (node (ref "SV173") (pin "5") (pinfunction "5_5") (pintype "passive"))
      (node (ref "SV173") (pin "6") (pinfunction "6_6") (pintype "passive"))
      (node (ref "SV176") (pin "6") (pinfunction "6_6") (pintype "passive"))
    )
    (net (code "1154") (name "Net-(IC72-Pad12)") (class "Default")
      (node (ref "IC72") (pin "12") (pinfunction "12_12") (pintype "passive"))
      (node (ref "SV173") (pin "7") (pinfunction "7_7") (pintype "passive"))
      (node (ref "SV173") (pin "8") (pinfunction "8_8") (pintype "passive"))
      (node (ref "SV176") (pin "5") (pinfunction "5_5") (pintype "passive"))
    )
    (net (code "1155") (name "Net-(IC72-Pad13)") (class "Default")
      (node (ref "IC72") (pin "13") (pinfunction "13_13") (pintype "passive"))
      (node (ref "SV173") (pin "10") (pinfunction "10_10") (pintype "passive"))
      (node (ref "SV173") (pin "9") (pinfunction "9_9") (pintype "passive"))
      (node (ref "SV176") (pin "4") (pinfunction "4_4") (pintype "passive"))
    )
    (net (code "1156") (name "Net-(IC72-Pad14)") (class "Default")
      (node (ref "IC72") (pin "14") (pinfunction "14_14") (pintype "passive"))
      (node (ref "SV173") (pin "11") (pinfunction "11_11") (pintype "passive"))
      (node (ref "SV173") (pin "12") (pinfunction "12_12") (pintype "passive"))
      (node (ref "SV176") (pin "3") (pinfunction "3_3") (pintype "passive"))
    )
    (net (code "1157") (name "Net-(IC72-Pad15)") (class "Default")
      (node (ref "IC72") (pin "15") (pinfunction "15_15") (pintype "passive"))
      (node (ref "SV173") (pin "13") (pinfunction "13_13") (pintype "passive"))
      (node (ref "SV173") (pin "14") (pinfunction "14_14") (pintype "passive"))
      (node (ref "SV176") (pin "2") (pinfunction "2_2") (pintype "passive"))
    )
    (net (code "1158") (name "Net-(IC72-Pad16)") (class "Default")
      (node (ref "IC72") (pin "16") (pinfunction "16_16") (pintype "passive"))
      (node (ref "SV173") (pin "15") (pinfunction "15_15") (pintype "passive"))
      (node (ref "SV173") (pin "16") (pinfunction "16_16") (pintype "passive"))
      (node (ref "SV176") (pin "1") (pinfunction "1_1") (pintype "passive"))
    )
    (net (code "1159") (name "Net-(SV121-Pad1)") (class "Default")
      (node (ref "SV121") (pin "1") (pinfunction "1_1") (pintype "passive"))
      (node (ref "SV122") (pin "2") (pinfunction "2_2") (pintype "passive"))
    )
    (net (code "1160") (name "Net-(SV121-Pad2)") (class "Default")
      (node (ref "SV121") (pin "2") (pinfunction "2_2") (pintype "passive"))
      (node (ref "SV122") (pin "1") (pinfunction "1_1") (pintype "passive"))
    )
    (net (code "1161") (name "Net-(SV121-Pad3)") (class "Default")
      (node (ref "SV121") (pin "3") (pinfunction "3_3") (pintype "passive"))
      (node (ref "SV122") (pin "4") (pinfunction "4_4") (pintype "passive"))
    )
    (net (code "1162") (name "Net-(SV121-Pad4)") (class "Default")
      (node (ref "SV121") (pin "4") (pinfunction "4_4") (pintype "passive"))
      (node (ref "SV122") (pin "3") (pinfunction "3_3") (pintype "passive"))
    )
    (net (code "1163") (name "Net-(SV121-Pad5)") (class "Default")
      (node (ref "SV121") (pin "5") (pinfunction "5_5") (pintype "passive"))
      (node (ref "SV122") (pin "6") (pinfunction "6_6") (pintype "passive"))
    )
    (net (code "1164") (name "Net-(SV121-Pad6)") (class "Default")
      (node (ref "SV121") (pin "6") (pinfunction "6_6") (pintype "passive"))
      (node (ref "SV122") (pin "5") (pinfunction "5_5") (pintype "passive"))
    )
    (net (code "1165") (name "Net-(SV121-Pad7)") (class "Default")
      (node (ref "SV121") (pin "7") (pinfunction "7_7") (pintype "passive"))
      (node (ref "SV122") (pin "8") (pinfunction "8_8") (pintype "passive"))
    )
    (net (code "1166") (name "Net-(SV121-Pad8)") (class "Default")
      (node (ref "SV121") (pin "8") (pinfunction "8_8") (pintype "passive"))
      (node (ref "SV122") (pin "7") (pinfunction "7_7") (pintype "passive"))
    )
    (net (code "1167") (name "Net-(SV121-Pad9)") (class "Default")
      (node (ref "SV121") (pin "9") (pinfunction "9_9") (pintype "passive"))
      (node (ref "SV122") (pin "10") (pinfunction "10_10") (pintype "passive"))
    )
    (net (code "1168") (name "Net-(SV121-Pad10)") (class "Default")
      (node (ref "SV121") (pin "10") (pinfunction "10_10") (pintype "passive"))
      (node (ref "SV122") (pin "9") (pinfunction "9_9") (pintype "passive"))
    )
    (net (code "1169") (name "Net-(SV121-Pad11)") (class "Default")
      (node (ref "SV121") (pin "11") (pinfunction "11_11") (pintype "passive"))
      (node (ref "SV122") (pin "12") (pinfunction "12_12") (pintype "passive"))
    )
    (net (code "1170") (name "Net-(SV121-Pad12)") (class "Default")
      (node (ref "SV121") (pin "12") (pinfunction "12_12") (pintype "passive"))
      (node (ref "SV122") (pin "11") (pinfunction "11_11") (pintype "passive"))
    )
    (net (code "1171") (name "Net-(SV121-Pad13)") (class "Default")
      (node (ref "SV121") (pin "13") (pinfunction "13_13") (pintype "passive"))
      (node (ref "SV122") (pin "14") (pinfunction "14_14") (pintype "passive"))
    )
    (net (code "1172") (name "Net-(SV121-Pad14)") (class "Default")
      (node (ref "SV121") (pin "14") (pinfunction "14_14") (pintype "passive"))
      (node (ref "SV122") (pin "13") (pinfunction "13_13") (pintype "passive"))
    )
    (net (code "1173") (name "Net-(SV121-Pad15)") (class "Default")
      (node (ref "SV121") (pin "15") (pinfunction "15_15") (pintype "passive"))
      (node (ref "SV122") (pin "16") (pinfunction "16_16") (pintype "passive"))
    )
    (net (code "1174") (name "Net-(SV121-Pad16)") (class "Default")
      (node (ref "SV121") (pin "16") (pinfunction "16_16") (pintype "passive"))
      (node (ref "SV122") (pin "15") (pinfunction "15_15") (pintype "passive"))
    )
    (net (code "1175") (name "Net-(SV121-Pad17)") (class "Default")
      (node (ref "SV121") (pin "17") (pinfunction "17_17") (pintype "passive"))
      (node (ref "SV122") (pin "18") (pinfunction "18_18") (pintype "passive"))
    )
    (net (code "1176") (name "Net-(SV121-Pad18)") (class "Default")
      (node (ref "SV121") (pin "18") (pinfunction "18_18") (pintype "passive"))
      (node (ref "SV122") (pin "17") (pinfunction "17_17") (pintype "passive"))
    )
    (net (code "1177") (name "Net-(SV121-Pad19)") (class "Default")
      (node (ref "SV121") (pin "19") (pinfunction "19_19") (pintype "passive"))
      (node (ref "SV122") (pin "20") (pinfunction "20_20") (pintype "passive"))
    )
    (net (code "1178") (name "Net-(SV121-Pad20)") (class "Default")
      (node (ref "SV121") (pin "20") (pinfunction "20_20") (pintype "passive"))
      (node (ref "SV122") (pin "19") (pinfunction "19_19") (pintype "passive"))
    )
    (net (code "1179") (name "Net-(SV121-Pad21)") (class "Default")
      (node (ref "SV121") (pin "21") (pinfunction "21_21") (pintype "passive"))
      (node (ref "SV122") (pin "22") (pinfunction "22_22") (pintype "passive"))
    )
    (net (code "1180") (name "Net-(SV121-Pad22)") (class "Default")
      (node (ref "SV121") (pin "22") (pinfunction "22_22") (pintype "passive"))
      (node (ref "SV122") (pin "21") (pinfunction "21_21") (pintype "passive"))
    )
    (net (code "1181") (name "Net-(SV121-Pad23)") (class "Default")
      (node (ref "SV121") (pin "23") (pinfunction "23_23") (pintype "passive"))
      (node (ref "SV122") (pin "24") (pinfunction "24_24") (pintype "passive"))
    )
    (net (code "1182") (name "Net-(SV121-Pad24)") (class "Default")
      (node (ref "SV121") (pin "24") (pinfunction "24_24") (pintype "passive"))
      (node (ref "SV122") (pin "23") (pinfunction "23_23") (pintype "passive"))
    )
    (net (code "1183") (name "Net-(SV121-Pad25)") (class "Default")
      (node (ref "SV121") (pin "25") (pinfunction "25_25") (pintype "passive"))
      (node (ref "SV122") (pin "26") (pinfunction "26_26") (pintype "passive"))
    )
    (net (code "1184") (name "Net-(SV121-Pad26)") (class "Default")
      (node (ref "SV121") (pin "26") (pinfunction "26_26") (pintype "passive"))
      (node (ref "SV122") (pin "25") (pinfunction "25_25") (pintype "passive"))
    )
    (net (code "1185") (name "Net-(SV121-Pad27)") (class "Default")
      (node (ref "SV121") (pin "27") (pinfunction "27_27") (pintype "passive"))
      (node (ref "SV122") (pin "28") (pinfunction "28_28") (pintype "passive"))
    )
    (net (code "1186") (name "Net-(SV121-Pad28)") (class "Default")
      (node (ref "SV121") (pin "28") (pinfunction "28_28") (pintype "passive"))
      (node (ref "SV122") (pin "27") (pinfunction "27_27") (pintype "passive"))
    )
    (net (code "1187") (name "Net-(SV121-Pad29)") (class "Default")
      (node (ref "SV121") (pin "29") (pinfunction "29_29") (pintype "passive"))
      (node (ref "SV122") (pin "30") (pinfunction "30_30") (pintype "passive"))
    )
    (net (code "1188") (name "Net-(SV121-Pad30)") (class "Default")
      (node (ref "SV121") (pin "30") (pinfunction "30_30") (pintype "passive"))
      (node (ref "SV122") (pin "29") (pinfunction "29_29") (pintype "passive"))
    )
    (net (code "1189") (name "Net-(SV121-Pad31)") (class "Default")
      (node (ref "SV121") (pin "31") (pinfunction "31_31") (pintype "passive"))
      (node (ref "SV122") (pin "32") (pinfunction "32_32") (pintype "passive"))
    )
    (net (code "1190") (name "Net-(SV121-Pad32)") (class "Default")
      (node (ref "SV121") (pin "32") (pinfunction "32_32") (pintype "passive"))
      (node (ref "SV122") (pin "31") (pinfunction "31_31") (pintype "passive"))
    )
    (net (code "1191") (name "Net-(SV121-Pad33)") (class "Default")
      (node (ref "SV121") (pin "33") (pinfunction "33_33") (pintype "passive"))
      (node (ref "SV122") (pin "34") (pinfunction "34_34") (pintype "passive"))
    )
    (net (code "1192") (name "Net-(SV121-Pad34)") (class "Default")
      (node (ref "SV121") (pin "34") (pinfunction "34_34") (pintype "passive"))
      (node (ref "SV122") (pin "33") (pinfunction "33_33") (pintype "passive"))
    )
    (net (code "1193") (name "Net-(SV121-Pad35)") (class "Default")
      (node (ref "SV121") (pin "35") (pinfunction "35_35") (pintype "passive"))
      (node (ref "SV122") (pin "36") (pinfunction "36_36") (pintype "passive"))
    )
    (net (code "1194") (name "Net-(SV121-Pad36)") (class "Default")
      (node (ref "SV121") (pin "36") (pinfunction "36_36") (pintype "passive"))
      (node (ref "SV122") (pin "35") (pinfunction "35_35") (pintype "passive"))
    )
    (net (code "1195") (name "Net-(SV121-Pad37)") (class "Default")
      (node (ref "SV121") (pin "37") (pinfunction "37_37") (pintype "passive"))
      (node (ref "SV122") (pin "38") (pinfunction "38_38") (pintype "passive"))
    )
    (net (code "1196") (name "Net-(SV121-Pad38)") (class "Default")
      (node (ref "SV121") (pin "38") (pinfunction "38_38") (pintype "passive"))
      (node (ref "SV122") (pin "37") (pinfunction "37_37") (pintype "passive"))
    )
    (net (code "1197") (name "Net-(SV121-Pad39)") (class "Default")
      (node (ref "SV121") (pin "39") (pinfunction "39_39") (pintype "passive"))
      (node (ref "SV122") (pin "40") (pinfunction "40_40") (pintype "passive"))
    )
    (net (code "1198") (name "Net-(SV121-Pad40)") (class "Default")
      (node (ref "SV121") (pin "40") (pinfunction "40_40") (pintype "passive"))
      (node (ref "SV122") (pin "39") (pinfunction "39_39") (pintype "passive"))
    )
    (net (code "1199") (name "Net-(SV123-Pad1)") (class "Default")
      (node (ref "SV123") (pin "1") (pinfunction "1_1") (pintype "passive"))
      (node (ref "SV124") (pin "2") (pinfunction "2_2") (pintype "passive"))
    )
    (net (code "1200") (name "Net-(SV123-Pad2)") (class "Default")
      (node (ref "SV123") (pin "2") (pinfunction "2_2") (pintype "passive"))
      (node (ref "SV124") (pin "1") (pinfunction "1_1") (pintype "passive"))
    )
    (net (code "1201") (name "Net-(SV123-Pad3)") (class "Default")
      (node (ref "SV123") (pin "3") (pinfunction "3_3") (pintype "passive"))
      (node (ref "SV124") (pin "4") (pinfunction "4_4") (pintype "passive"))
    )
    (net (code "1202") (name "Net-(SV123-Pad4)") (class "Default")
      (node (ref "SV123") (pin "4") (pinfunction "4_4") (pintype "passive"))
      (node (ref "SV124") (pin "3") (pinfunction "3_3") (pintype "passive"))
    )
    (net (code "1203") (name "Net-(SV123-Pad5)") (class "Default")
      (node (ref "SV123") (pin "5") (pinfunction "5_5") (pintype "passive"))
      (node (ref "SV124") (pin "6") (pinfunction "6_6") (pintype "passive"))
    )
    (net (code "1204") (name "Net-(SV123-Pad6)") (class "Default")
      (node (ref "SV123") (pin "6") (pinfunction "6_6") (pintype "passive"))
      (node (ref "SV124") (pin "5") (pinfunction "5_5") (pintype "passive"))
    )
    (net (code "1205") (name "Net-(SV123-Pad7)") (class "Default")
      (node (ref "SV123") (pin "7") (pinfunction "7_7") (pintype "passive"))
      (node (ref "SV124") (pin "8") (pinfunction "8_8") (pintype "passive"))
    )
    (net (code "1206") (name "Net-(SV123-Pad8)") (class "Default")
      (node (ref "SV123") (pin "8") (pinfunction "8_8") (pintype "passive"))
      (node (ref "SV124") (pin "7") (pinfunction "7_7") (pintype "passive"))
    )
    (net (code "1207") (name "Net-(SV123-Pad9)") (class "Default")
      (node (ref "SV123") (pin "9") (pinfunction "9_9") (pintype "passive"))
      (node (ref "SV124") (pin "10") (pinfunction "10_10") (pintype "passive"))
    )
    (net (code "1208") (name "Net-(SV123-Pad10)") (class "Default")
      (node (ref "SV123") (pin "10") (pinfunction "10_10") (pintype "passive"))
      (node (ref "SV124") (pin "9") (pinfunction "9_9") (pintype "passive"))
    )
    (net (code "1209") (name "Net-(SV123-Pad11)") (class "Default")
      (node (ref "SV123") (pin "11") (pinfunction "11_11") (pintype "passive"))
      (node (ref "SV124") (pin "12") (pinfunction "12_12") (pintype "passive"))
    )
    (net (code "1210") (name "Net-(SV123-Pad12)") (class "Default")
      (node (ref "SV123") (pin "12") (pinfunction "12_12") (pintype "passive"))
      (node (ref "SV124") (pin "11") (pinfunction "11_11") (pintype "passive"))
    )
    (net (code "1211") (name "Net-(SV123-Pad13)") (class "Default")
      (node (ref "SV123") (pin "13") (pinfunction "13_13") (pintype "passive"))
      (node (ref "SV124") (pin "14") (pinfunction "14_14") (pintype "passive"))
    )
    (net (code "1212") (name "Net-(SV123-Pad14)") (class "Default")
      (node (ref "SV123") (pin "14") (pinfunction "14_14") (pintype "passive"))
      (node (ref "SV124") (pin "13") (pinfunction "13_13") (pintype "passive"))
    )
    (net (code "1213") (name "Net-(SV123-Pad15)") (class "Default")
      (node (ref "SV123") (pin "15") (pinfunction "15_15") (pintype "passive"))
      (node (ref "SV124") (pin "16") (pinfunction "16_16") (pintype "passive"))
    )
    (net (code "1214") (name "Net-(SV123-Pad16)") (class "Default")
      (node (ref "SV123") (pin "16") (pinfunction "16_16") (pintype "passive"))
      (node (ref "SV124") (pin "15") (pinfunction "15_15") (pintype "passive"))
    )
    (net (code "1215") (name "Net-(SV123-Pad17)") (class "Default")
      (node (ref "SV123") (pin "17") (pinfunction "17_17") (pintype "passive"))
      (node (ref "SV124") (pin "18") (pinfunction "18_18") (pintype "passive"))
    )
    (net (code "1216") (name "Net-(SV123-Pad18)") (class "Default")
      (node (ref "SV123") (pin "18") (pinfunction "18_18") (pintype "passive"))
      (node (ref "SV124") (pin "17") (pinfunction "17_17") (pintype "passive"))
    )
    (net (code "1217") (name "Net-(SV123-Pad19)") (class "Default")
      (node (ref "SV123") (pin "19") (pinfunction "19_19") (pintype "passive"))
      (node (ref "SV124") (pin "20") (pinfunction "20_20") (pintype "passive"))
    )
    (net (code "1218") (name "Net-(SV123-Pad20)") (class "Default")
      (node (ref "SV123") (pin "20") (pinfunction "20_20") (pintype "passive"))
      (node (ref "SV124") (pin "19") (pinfunction "19_19") (pintype "passive"))
    )
    (net (code "1219") (name "Net-(SV123-Pad21)") (class "Default")
      (node (ref "SV123") (pin "21") (pinfunction "21_21") (pintype "passive"))
      (node (ref "SV124") (pin "22") (pinfunction "22_22") (pintype "passive"))
    )
    (net (code "1220") (name "Net-(SV123-Pad22)") (class "Default")
      (node (ref "SV123") (pin "22") (pinfunction "22_22") (pintype "passive"))
      (node (ref "SV124") (pin "21") (pinfunction "21_21") (pintype "passive"))
    )
    (net (code "1221") (name "Net-(SV123-Pad23)") (class "Default")
      (node (ref "SV123") (pin "23") (pinfunction "23_23") (pintype "passive"))
      (node (ref "SV124") (pin "24") (pinfunction "24_24") (pintype "passive"))
    )
    (net (code "1222") (name "Net-(SV123-Pad24)") (class "Default")
      (node (ref "SV123") (pin "24") (pinfunction "24_24") (pintype "passive"))
      (node (ref "SV124") (pin "23") (pinfunction "23_23") (pintype "passive"))
    )
    (net (code "1223") (name "Net-(SV123-Pad25)") (class "Default")
      (node (ref "SV123") (pin "25") (pinfunction "25_25") (pintype "passive"))
      (node (ref "SV124") (pin "26") (pinfunction "26_26") (pintype "passive"))
    )
    (net (code "1224") (name "Net-(SV123-Pad26)") (class "Default")
      (node (ref "SV123") (pin "26") (pinfunction "26_26") (pintype "passive"))
      (node (ref "SV124") (pin "25") (pinfunction "25_25") (pintype "passive"))
    )
    (net (code "1225") (name "Net-(SV123-Pad27)") (class "Default")
      (node (ref "SV123") (pin "27") (pinfunction "27_27") (pintype "passive"))
      (node (ref "SV124") (pin "28") (pinfunction "28_28") (pintype "passive"))
    )
    (net (code "1226") (name "Net-(SV123-Pad28)") (class "Default")
      (node (ref "SV123") (pin "28") (pinfunction "28_28") (pintype "passive"))
      (node (ref "SV124") (pin "27") (pinfunction "27_27") (pintype "passive"))
    )
    (net (code "1227") (name "Net-(SV123-Pad29)") (class "Default")
      (node (ref "SV123") (pin "29") (pinfunction "29_29") (pintype "passive"))
      (node (ref "SV124") (pin "30") (pinfunction "30_30") (pintype "passive"))
    )
    (net (code "1228") (name "Net-(SV123-Pad30)") (class "Default")
      (node (ref "SV123") (pin "30") (pinfunction "30_30") (pintype "passive"))
      (node (ref "SV124") (pin "29") (pinfunction "29_29") (pintype "passive"))
    )
    (net (code "1229") (name "Net-(SV123-Pad31)") (class "Default")
      (node (ref "SV123") (pin "31") (pinfunction "31_31") (pintype "passive"))
      (node (ref "SV124") (pin "32") (pinfunction "32_32") (pintype "passive"))
    )
    (net (code "1230") (name "Net-(SV123-Pad32)") (class "Default")
      (node (ref "SV123") (pin "32") (pinfunction "32_32") (pintype "passive"))
      (node (ref "SV124") (pin "31") (pinfunction "31_31") (pintype "passive"))
    )
    (net (code "1231") (name "Net-(SV123-Pad33)") (class "Default")
      (node (ref "SV123") (pin "33") (pinfunction "33_33") (pintype "passive"))
      (node (ref "SV124") (pin "34") (pinfunction "34_34") (pintype "passive"))
    )
    (net (code "1232") (name "Net-(SV123-Pad34)") (class "Default")
      (node (ref "SV123") (pin "34") (pinfunction "34_34") (pintype "passive"))
      (node (ref "SV124") (pin "33") (pinfunction "33_33") (pintype "passive"))
    )
    (net (code "1233") (name "Net-(SV123-Pad35)") (class "Default")
      (node (ref "SV123") (pin "35") (pinfunction "35_35") (pintype "passive"))
      (node (ref "SV124") (pin "36") (pinfunction "36_36") (pintype "passive"))
    )
    (net (code "1234") (name "Net-(SV123-Pad36)") (class "Default")
      (node (ref "SV123") (pin "36") (pinfunction "36_36") (pintype "passive"))
      (node (ref "SV124") (pin "35") (pinfunction "35_35") (pintype "passive"))
    )
    (net (code "1235") (name "Net-(SV123-Pad37)") (class "Default")
      (node (ref "SV123") (pin "37") (pinfunction "37_37") (pintype "passive"))
      (node (ref "SV124") (pin "38") (pinfunction "38_38") (pintype "passive"))
    )
    (net (code "1236") (name "Net-(SV123-Pad38)") (class "Default")
      (node (ref "SV123") (pin "38") (pinfunction "38_38") (pintype "passive"))
      (node (ref "SV124") (pin "37") (pinfunction "37_37") (pintype "passive"))
    )
    (net (code "1237") (name "Net-(SV123-Pad39)") (class "Default")
      (node (ref "SV123") (pin "39") (pinfunction "39_39") (pintype "passive"))
      (node (ref "SV124") (pin "40") (pinfunction "40_40") (pintype "passive"))
    )
    (net (code "1238") (name "Net-(SV123-Pad40)") (class "Default")
      (node (ref "SV123") (pin "40") (pinfunction "40_40") (pintype "passive"))
      (node (ref "SV124") (pin "39") (pinfunction "39_39") (pintype "passive"))
    )
    (net (code "1239") (name "Net-(SV125-Pad1)") (class "Default")
      (node (ref "SV125") (pin "1") (pinfunction "1_1") (pintype "passive"))
      (node (ref "SV126") (pin "2") (pinfunction "2_2") (pintype "passive"))
    )
    (net (code "1240") (name "Net-(SV125-Pad2)") (class "Default")
      (node (ref "SV125") (pin "2") (pinfunction "2_2") (pintype "passive"))
      (node (ref "SV126") (pin "1") (pinfunction "1_1") (pintype "passive"))
    )
    (net (code "1241") (name "Net-(SV125-Pad3)") (class "Default")
      (node (ref "SV125") (pin "3") (pinfunction "3_3") (pintype "passive"))
      (node (ref "SV126") (pin "4") (pinfunction "4_4") (pintype "passive"))
    )
    (net (code "1242") (name "Net-(SV125-Pad4)") (class "Default")
      (node (ref "SV125") (pin "4") (pinfunction "4_4") (pintype "passive"))
      (node (ref "SV126") (pin "3") (pinfunction "3_3") (pintype "passive"))
    )
    (net (code "1243") (name "Net-(SV125-Pad5)") (class "Default")
      (node (ref "SV125") (pin "5") (pinfunction "5_5") (pintype "passive"))
      (node (ref "SV126") (pin "6") (pinfunction "6_6") (pintype "passive"))
    )
    (net (code "1244") (name "Net-(SV125-Pad6)") (class "Default")
      (node (ref "SV125") (pin "6") (pinfunction "6_6") (pintype "passive"))
      (node (ref "SV126") (pin "5") (pinfunction "5_5") (pintype "passive"))
    )
    (net (code "1245") (name "Net-(SV125-Pad7)") (class "Default")
      (node (ref "SV125") (pin "7") (pinfunction "7_7") (pintype "passive"))
      (node (ref "SV126") (pin "8") (pinfunction "8_8") (pintype "passive"))
    )
    (net (code "1246") (name "Net-(SV125-Pad8)") (class "Default")
      (node (ref "SV125") (pin "8") (pinfunction "8_8") (pintype "passive"))
      (node (ref "SV126") (pin "7") (pinfunction "7_7") (pintype "passive"))
    )
    (net (code "1247") (name "Net-(SV125-Pad9)") (class "Default")
      (node (ref "SV125") (pin "9") (pinfunction "9_9") (pintype "passive"))
      (node (ref "SV126") (pin "10") (pinfunction "10_10") (pintype "passive"))
    )
    (net (code "1248") (name "Net-(SV125-Pad10)") (class "Default")
      (node (ref "SV125") (pin "10") (pinfunction "10_10") (pintype "passive"))
      (node (ref "SV126") (pin "9") (pinfunction "9_9") (pintype "passive"))
    )
    (net (code "1249") (name "Net-(SV125-Pad11)") (class "Default")
      (node (ref "SV125") (pin "11") (pinfunction "11_11") (pintype "passive"))
      (node (ref "SV126") (pin "12") (pinfunction "12_12") (pintype "passive"))
    )
    (net (code "1250") (name "Net-(SV125-Pad12)") (class "Default")
      (node (ref "SV125") (pin "12") (pinfunction "12_12") (pintype "passive"))
      (node (ref "SV126") (pin "11") (pinfunction "11_11") (pintype "passive"))
    )
    (net (code "1251") (name "Net-(SV125-Pad13)") (class "Default")
      (node (ref "SV125") (pin "13") (pinfunction "13_13") (pintype "passive"))
      (node (ref "SV126") (pin "14") (pinfunction "14_14") (pintype "passive"))
    )
    (net (code "1252") (name "Net-(SV125-Pad14)") (class "Default")
      (node (ref "SV125") (pin "14") (pinfunction "14_14") (pintype "passive"))
      (node (ref "SV126") (pin "13") (pinfunction "13_13") (pintype "passive"))
    )
    (net (code "1253") (name "Net-(SV125-Pad15)") (class "Default")
      (node (ref "SV125") (pin "15") (pinfunction "15_15") (pintype "passive"))
      (node (ref "SV126") (pin "16") (pinfunction "16_16") (pintype "passive"))
    )
    (net (code "1254") (name "Net-(SV125-Pad16)") (class "Default")
      (node (ref "SV125") (pin "16") (pinfunction "16_16") (pintype "passive"))
      (node (ref "SV126") (pin "15") (pinfunction "15_15") (pintype "passive"))
    )
    (net (code "1255") (name "Net-(SV125-Pad17)") (class "Default")
      (node (ref "SV125") (pin "17") (pinfunction "17_17") (pintype "passive"))
      (node (ref "SV126") (pin "18") (pinfunction "18_18") (pintype "passive"))
    )
    (net (code "1256") (name "Net-(SV125-Pad18)") (class "Default")
      (node (ref "SV125") (pin "18") (pinfunction "18_18") (pintype "passive"))
      (node (ref "SV126") (pin "17") (pinfunction "17_17") (pintype "passive"))
    )
    (net (code "1257") (name "Net-(SV125-Pad19)") (class "Default")
      (node (ref "SV125") (pin "19") (pinfunction "19_19") (pintype "passive"))
      (node (ref "SV126") (pin "20") (pinfunction "20_20") (pintype "passive"))
    )
    (net (code "1258") (name "Net-(SV125-Pad20)") (class "Default")
      (node (ref "SV125") (pin "20") (pinfunction "20_20") (pintype "passive"))
      (node (ref "SV126") (pin "19") (pinfunction "19_19") (pintype "passive"))
    )
    (net (code "1259") (name "Net-(SV125-Pad21)") (class "Default")
      (node (ref "SV125") (pin "21") (pinfunction "21_21") (pintype "passive"))
      (node (ref "SV126") (pin "22") (pinfunction "22_22") (pintype "passive"))
    )
    (net (code "1260") (name "Net-(SV125-Pad22)") (class "Default")
      (node (ref "SV125") (pin "22") (pinfunction "22_22") (pintype "passive"))
      (node (ref "SV126") (pin "21") (pinfunction "21_21") (pintype "passive"))
    )
    (net (code "1261") (name "Net-(SV125-Pad23)") (class "Default")
      (node (ref "SV125") (pin "23") (pinfunction "23_23") (pintype "passive"))
      (node (ref "SV126") (pin "24") (pinfunction "24_24") (pintype "passive"))
    )
    (net (code "1262") (name "Net-(SV125-Pad24)") (class "Default")
      (node (ref "SV125") (pin "24") (pinfunction "24_24") (pintype "passive"))
      (node (ref "SV126") (pin "23") (pinfunction "23_23") (pintype "passive"))
    )
    (net (code "1263") (name "Net-(SV125-Pad25)") (class "Default")
      (node (ref "SV125") (pin "25") (pinfunction "25_25") (pintype "passive"))
      (node (ref "SV126") (pin "26") (pinfunction "26_26") (pintype "passive"))
    )
    (net (code "1264") (name "Net-(SV125-Pad26)") (class "Default")
      (node (ref "SV125") (pin "26") (pinfunction "26_26") (pintype "passive"))
      (node (ref "SV126") (pin "25") (pinfunction "25_25") (pintype "passive"))
    )
    (net (code "1265") (name "Net-(SV125-Pad27)") (class "Default")
      (node (ref "SV125") (pin "27") (pinfunction "27_27") (pintype "passive"))
      (node (ref "SV126") (pin "28") (pinfunction "28_28") (pintype "passive"))
    )
    (net (code "1266") (name "Net-(SV125-Pad28)") (class "Default")
      (node (ref "SV125") (pin "28") (pinfunction "28_28") (pintype "passive"))
      (node (ref "SV126") (pin "27") (pinfunction "27_27") (pintype "passive"))
    )
    (net (code "1267") (name "Net-(SV125-Pad29)") (class "Default")
      (node (ref "SV125") (pin "29") (pinfunction "29_29") (pintype "passive"))
      (node (ref "SV126") (pin "30") (pinfunction "30_30") (pintype "passive"))
    )
    (net (code "1268") (name "Net-(SV125-Pad30)") (class "Default")
      (node (ref "SV125") (pin "30") (pinfunction "30_30") (pintype "passive"))
      (node (ref "SV126") (pin "29") (pinfunction "29_29") (pintype "passive"))
    )
    (net (code "1269") (name "Net-(SV125-Pad31)") (class "Default")
      (node (ref "SV125") (pin "31") (pinfunction "31_31") (pintype "passive"))
      (node (ref "SV126") (pin "32") (pinfunction "32_32") (pintype "passive"))
    )
    (net (code "1270") (name "Net-(SV125-Pad32)") (class "Default")
      (node (ref "SV125") (pin "32") (pinfunction "32_32") (pintype "passive"))
      (node (ref "SV126") (pin "31") (pinfunction "31_31") (pintype "passive"))
    )
    (net (code "1271") (name "Net-(SV125-Pad33)") (class "Default")
      (node (ref "SV125") (pin "33") (pinfunction "33_33") (pintype "passive"))
      (node (ref "SV126") (pin "34") (pinfunction "34_34") (pintype "passive"))
    )
    (net (code "1272") (name "Net-(SV125-Pad34)") (class "Default")
      (node (ref "SV125") (pin "34") (pinfunction "34_34") (pintype "passive"))
      (node (ref "SV126") (pin "33") (pinfunction "33_33") (pintype "passive"))
    )
    (net (code "1273") (name "Net-(SV125-Pad35)") (class "Default")
      (node (ref "SV125") (pin "35") (pinfunction "35_35") (pintype "passive"))
      (node (ref "SV126") (pin "36") (pinfunction "36_36") (pintype "passive"))
    )
    (net (code "1274") (name "Net-(SV125-Pad36)") (class "Default")
      (node (ref "SV125") (pin "36") (pinfunction "36_36") (pintype "passive"))
      (node (ref "SV126") (pin "35") (pinfunction "35_35") (pintype "passive"))
    )
    (net (code "1275") (name "Net-(SV125-Pad37)") (class "Default")
      (node (ref "SV125") (pin "37") (pinfunction "37_37") (pintype "passive"))
      (node (ref "SV126") (pin "38") (pinfunction "38_38") (pintype "passive"))
    )
    (net (code "1276") (name "Net-(SV125-Pad38)") (class "Default")
      (node (ref "SV125") (pin "38") (pinfunction "38_38") (pintype "passive"))
      (node (ref "SV126") (pin "37") (pinfunction "37_37") (pintype "passive"))
    )
    (net (code "1277") (name "Net-(SV125-Pad39)") (class "Default")
      (node (ref "SV125") (pin "39") (pinfunction "39_39") (pintype "passive"))
      (node (ref "SV126") (pin "40") (pinfunction "40_40") (pintype "passive"))
    )
    (net (code "1278") (name "Net-(SV125-Pad40)") (class "Default")
      (node (ref "SV125") (pin "40") (pinfunction "40_40") (pintype "passive"))
      (node (ref "SV126") (pin "39") (pinfunction "39_39") (pintype "passive"))
    )
    (net (code "1279") (name "Net-(SV127-Pad1)") (class "Default")
      (node (ref "SV127") (pin "1") (pinfunction "1_1") (pintype "passive"))
      (node (ref "SV128") (pin "2") (pinfunction "2_2") (pintype "passive"))
    )
    (net (code "1280") (name "Net-(SV127-Pad2)") (class "Default")
      (node (ref "SV127") (pin "2") (pinfunction "2_2") (pintype "passive"))
      (node (ref "SV128") (pin "1") (pinfunction "1_1") (pintype "passive"))
    )
    (net (code "1281") (name "Net-(SV127-Pad3)") (class "Default")
      (node (ref "SV127") (pin "3") (pinfunction "3_3") (pintype "passive"))
      (node (ref "SV128") (pin "4") (pinfunction "4_4") (pintype "passive"))
    )
    (net (code "1282") (name "Net-(SV127-Pad4)") (class "Default")
      (node (ref "SV127") (pin "4") (pinfunction "4_4") (pintype "passive"))
      (node (ref "SV128") (pin "3") (pinfunction "3_3") (pintype "passive"))
    )
    (net (code "1283") (name "Net-(SV127-Pad5)") (class "Default")
      (node (ref "SV127") (pin "5") (pinfunction "5_5") (pintype "passive"))
      (node (ref "SV128") (pin "6") (pinfunction "6_6") (pintype "passive"))
    )
    (net (code "1284") (name "Net-(SV127-Pad6)") (class "Default")
      (node (ref "SV127") (pin "6") (pinfunction "6_6") (pintype "passive"))
      (node (ref "SV128") (pin "5") (pinfunction "5_5") (pintype "passive"))
    )
    (net (code "1285") (name "Net-(SV127-Pad7)") (class "Default")
      (node (ref "SV127") (pin "7") (pinfunction "7_7") (pintype "passive"))
      (node (ref "SV128") (pin "8") (pinfunction "8_8") (pintype "passive"))
    )
    (net (code "1286") (name "Net-(SV127-Pad8)") (class "Default")
      (node (ref "SV127") (pin "8") (pinfunction "8_8") (pintype "passive"))
      (node (ref "SV128") (pin "7") (pinfunction "7_7") (pintype "passive"))
    )
    (net (code "1287") (name "Net-(SV127-Pad9)") (class "Default")
      (node (ref "SV127") (pin "9") (pinfunction "9_9") (pintype "passive"))
      (node (ref "SV128") (pin "10") (pinfunction "10_10") (pintype "passive"))
    )
    (net (code "1288") (name "Net-(SV127-Pad10)") (class "Default")
      (node (ref "SV127") (pin "10") (pinfunction "10_10") (pintype "passive"))
      (node (ref "SV128") (pin "9") (pinfunction "9_9") (pintype "passive"))
    )
    (net (code "1289") (name "Net-(SV127-Pad11)") (class "Default")
      (node (ref "SV127") (pin "11") (pinfunction "11_11") (pintype "passive"))
      (node (ref "SV128") (pin "12") (pinfunction "12_12") (pintype "passive"))
    )
    (net (code "1290") (name "Net-(SV127-Pad12)") (class "Default")
      (node (ref "SV127") (pin "12") (pinfunction "12_12") (pintype "passive"))
      (node (ref "SV128") (pin "11") (pinfunction "11_11") (pintype "passive"))
    )
    (net (code "1291") (name "Net-(SV127-Pad13)") (class "Default")
      (node (ref "SV127") (pin "13") (pinfunction "13_13") (pintype "passive"))
      (node (ref "SV128") (pin "14") (pinfunction "14_14") (pintype "passive"))
    )
    (net (code "1292") (name "Net-(SV127-Pad14)") (class "Default")
      (node (ref "SV127") (pin "14") (pinfunction "14_14") (pintype "passive"))
      (node (ref "SV128") (pin "13") (pinfunction "13_13") (pintype "passive"))
    )
    (net (code "1293") (name "Net-(SV127-Pad15)") (class "Default")
      (node (ref "SV127") (pin "15") (pinfunction "15_15") (pintype "passive"))
      (node (ref "SV128") (pin "16") (pinfunction "16_16") (pintype "passive"))
    )
    (net (code "1294") (name "Net-(SV127-Pad16)") (class "Default")
      (node (ref "SV127") (pin "16") (pinfunction "16_16") (pintype "passive"))
      (node (ref "SV128") (pin "15") (pinfunction "15_15") (pintype "passive"))
    )
    (net (code "1295") (name "Net-(SV127-Pad17)") (class "Default")
      (node (ref "SV127") (pin "17") (pinfunction "17_17") (pintype "passive"))
      (node (ref "SV128") (pin "18") (pinfunction "18_18") (pintype "passive"))
    )
    (net (code "1296") (name "Net-(SV127-Pad18)") (class "Default")
      (node (ref "SV127") (pin "18") (pinfunction "18_18") (pintype "passive"))
      (node (ref "SV128") (pin "17") (pinfunction "17_17") (pintype "passive"))
    )
    (net (code "1297") (name "Net-(SV127-Pad19)") (class "Default")
      (node (ref "SV127") (pin "19") (pinfunction "19_19") (pintype "passive"))
      (node (ref "SV128") (pin "20") (pinfunction "20_20") (pintype "passive"))
    )
    (net (code "1298") (name "Net-(SV127-Pad20)") (class "Default")
      (node (ref "SV127") (pin "20") (pinfunction "20_20") (pintype "passive"))
      (node (ref "SV128") (pin "19") (pinfunction "19_19") (pintype "passive"))
    )
    (net (code "1299") (name "Net-(SV127-Pad21)") (class "Default")
      (node (ref "SV127") (pin "21") (pinfunction "21_21") (pintype "passive"))
      (node (ref "SV128") (pin "22") (pinfunction "22_22") (pintype "passive"))
    )
    (net (code "1300") (name "Net-(SV127-Pad22)") (class "Default")
      (node (ref "SV127") (pin "22") (pinfunction "22_22") (pintype "passive"))
      (node (ref "SV128") (pin "21") (pinfunction "21_21") (pintype "passive"))
    )
    (net (code "1301") (name "Net-(SV127-Pad23)") (class "Default")
      (node (ref "SV127") (pin "23") (pinfunction "23_23") (pintype "passive"))
      (node (ref "SV128") (pin "24") (pinfunction "24_24") (pintype "passive"))
    )
    (net (code "1302") (name "Net-(SV127-Pad24)") (class "Default")
      (node (ref "SV127") (pin "24") (pinfunction "24_24") (pintype "passive"))
      (node (ref "SV128") (pin "23") (pinfunction "23_23") (pintype "passive"))
    )
    (net (code "1303") (name "Net-(SV127-Pad25)") (class "Default")
      (node (ref "SV127") (pin "25") (pinfunction "25_25") (pintype "passive"))
      (node (ref "SV128") (pin "26") (pinfunction "26_26") (pintype "passive"))
    )
    (net (code "1304") (name "Net-(SV127-Pad26)") (class "Default")
      (node (ref "SV127") (pin "26") (pinfunction "26_26") (pintype "passive"))
      (node (ref "SV128") (pin "25") (pinfunction "25_25") (pintype "passive"))
    )
    (net (code "1305") (name "Net-(SV127-Pad27)") (class "Default")
      (node (ref "SV127") (pin "27") (pinfunction "27_27") (pintype "passive"))
      (node (ref "SV128") (pin "28") (pinfunction "28_28") (pintype "passive"))
    )
    (net (code "1306") (name "Net-(SV127-Pad28)") (class "Default")
      (node (ref "SV127") (pin "28") (pinfunction "28_28") (pintype "passive"))
      (node (ref "SV128") (pin "27") (pinfunction "27_27") (pintype "passive"))
    )
    (net (code "1307") (name "Net-(SV127-Pad29)") (class "Default")
      (node (ref "SV127") (pin "29") (pinfunction "29_29") (pintype "passive"))
      (node (ref "SV128") (pin "30") (pinfunction "30_30") (pintype "passive"))
    )
    (net (code "1308") (name "Net-(SV127-Pad30)") (class "Default")
      (node (ref "SV127") (pin "30") (pinfunction "30_30") (pintype "passive"))
      (node (ref "SV128") (pin "29") (pinfunction "29_29") (pintype "passive"))
    )
    (net (code "1309") (name "Net-(SV127-Pad31)") (class "Default")
      (node (ref "SV127") (pin "31") (pinfunction "31_31") (pintype "passive"))
      (node (ref "SV128") (pin "32") (pinfunction "32_32") (pintype "passive"))
    )
    (net (code "1310") (name "Net-(SV127-Pad32)") (class "Default")
      (node (ref "SV127") (pin "32") (pinfunction "32_32") (pintype "passive"))
      (node (ref "SV128") (pin "31") (pinfunction "31_31") (pintype "passive"))
    )
    (net (code "1311") (name "Net-(SV127-Pad33)") (class "Default")
      (node (ref "SV127") (pin "33") (pinfunction "33_33") (pintype "passive"))
      (node (ref "SV128") (pin "34") (pinfunction "34_34") (pintype "passive"))
    )
    (net (code "1312") (name "Net-(SV127-Pad34)") (class "Default")
      (node (ref "SV127") (pin "34") (pinfunction "34_34") (pintype "passive"))
      (node (ref "SV128") (pin "33") (pinfunction "33_33") (pintype "passive"))
    )
    (net (code "1313") (name "Net-(SV127-Pad35)") (class "Default")
      (node (ref "SV127") (pin "35") (pinfunction "35_35") (pintype "passive"))
      (node (ref "SV128") (pin "36") (pinfunction "36_36") (pintype "passive"))
    )
    (net (code "1314") (name "Net-(SV127-Pad36)") (class "Default")
      (node (ref "SV127") (pin "36") (pinfunction "36_36") (pintype "passive"))
      (node (ref "SV128") (pin "35") (pinfunction "35_35") (pintype "passive"))
    )
    (net (code "1315") (name "Net-(SV127-Pad37)") (class "Default")
      (node (ref "SV127") (pin "37") (pinfunction "37_37") (pintype "passive"))
      (node (ref "SV128") (pin "38") (pinfunction "38_38") (pintype "passive"))
    )
    (net (code "1316") (name "Net-(SV127-Pad38)") (class "Default")
      (node (ref "SV127") (pin "38") (pinfunction "38_38") (pintype "passive"))
      (node (ref "SV128") (pin "37") (pinfunction "37_37") (pintype "passive"))
    )
    (net (code "1317") (name "Net-(SV127-Pad39)") (class "Default")
      (node (ref "SV127") (pin "39") (pinfunction "39_39") (pintype "passive"))
      (node (ref "SV128") (pin "40") (pinfunction "40_40") (pintype "passive"))
    )
    (net (code "1318") (name "Net-(SV127-Pad40)") (class "Default")
      (node (ref "SV127") (pin "40") (pinfunction "40_40") (pintype "passive"))
      (node (ref "SV128") (pin "39") (pinfunction "39_39") (pintype "passive"))
    )
    (net (code "1319") (name "Net-(U$2A-1)") (class "Default")
      (node (ref "JA1") (pin "1") (pinfunction "1_1") (pintype "passive"))
      (node (ref "U$2") (pin "AA1") (pinfunction "1_AA1") (pintype "bidirectional"))
    )
    (net (code "1320") (name "Net-(U$2AF-1)") (class "Default")
      (node (ref "JA2") (pin "16") (pinfunction "16_16") (pintype "passive"))
      (node (ref "U$2") (pin "AT2") (pinfunction "1_AT2") (pintype "bidirectional"))
    )
    (net (code "1321") (name "Net-(U$2AK-1)") (class "Default")
      (node (ref "JB1") (pin "1") (pinfunction "1_1") (pintype "passive"))
      (node (ref "U$2") (pin "BA1") (pinfunction "1_BA1") (pintype "bidirectional"))
    )
    (net (code "1322") (name "Net-(U$2AM-1)") (class "Default")
      (node (ref "JB1") (pin "2") (pinfunction "2_2") (pintype "passive"))
      (node (ref "U$2") (pin "BB1") (pinfunction "1_BB1") (pintype "bidirectional"))
    )
    (net (code "1323") (name "Net-(U$2AN-1)") (class "Default")
      (node (ref "JB2") (pin "2") (pinfunction "2_2") (pintype "passive"))
      (node (ref "U$2") (pin "BB2") (pinfunction "1_BB2") (pintype "bidirectional"))
    )
    (net (code "1324") (name "Net-(U$2AO-1)") (class "Default")
      (node (ref "JB1") (pin "3") (pinfunction "3_3") (pintype "passive"))
      (node (ref "U$2") (pin "BC1") (pinfunction "1_BC1") (pintype "bidirectional"))
    )
    (net (code "1325") (name "Net-(U$2AU-1)") (class "Default")
      (node (ref "JB1") (pin "6") (pinfunction "6_6") (pintype "passive"))
      (node (ref "U$2") (pin "BF1") (pinfunction "1_BF1") (pintype "bidirectional"))
    )
    (net (code "1326") (name "Net-(U$2AV-1)") (class "Default")
      (node (ref "JB2") (pin "6") (pinfunction "6_6") (pintype "passive"))
      (node (ref "U$2") (pin "BF2") (pinfunction "1_BF2") (pintype "bidirectional"))
    )
    (net (code "1327") (name "Net-(U$2BG-1)") (class "Default")
      (node (ref "JB1") (pin "12") (pinfunction "12_12") (pintype "passive"))
      (node (ref "U$2") (pin "BN1") (pinfunction "1_BN1") (pintype "bidirectional"))
    )
    (net (code "1328") (name "Net-(U$2BH-1)") (class "Default")
      (node (ref "JB2") (pin "12") (pinfunction "12_12") (pintype "passive"))
      (node (ref "U$2") (pin "BN2") (pinfunction "1_BN2") (pintype "bidirectional"))
    )
    (net (code "1329") (name "Net-(U$2BN-1)") (class "Default")
      (node (ref "JB2") (pin "15") (pinfunction "15_15") (pintype "passive"))
      (node (ref "U$2") (pin "BS2") (pinfunction "1_BS2") (pintype "bidirectional"))
    )
    (net (code "1330") (name "Net-(U$2BP-1)") (class "Default")
      (node (ref "JB2") (pin "16") (pinfunction "16_16") (pintype "passive"))
      (node (ref "U$2") (pin "BT2") (pinfunction "1_BT2") (pintype "bidirectional"))
    )
    (net (code "1331") (name "Net-(U$2BU-1)") (class "Default")
      (node (ref "JC1") (pin "1") (pinfunction "1_1") (pintype "passive"))
      (node (ref "U$2") (pin "CA1") (pinfunction "1_CA1") (pintype "bidirectional"))
    )
    (net (code "1332") (name "Net-(U$2BW-1)") (class "Default")
      (node (ref "JC1") (pin "2") (pinfunction "2_2") (pintype "passive"))
      (node (ref "U$2") (pin "CB1") (pinfunction "1_CB1") (pintype "bidirectional"))
    )
    (net (code "1333") (name "Net-(U$2BX-1)") (class "Default")
      (node (ref "JC2") (pin "2") (pinfunction "2_2") (pintype "passive"))
      (node (ref "U$2") (pin "CB2") (pinfunction "1_CB2") (pintype "bidirectional"))
    )
    (net (code "1334") (name "Net-(U$2BY-1)") (class "Default")
      (node (ref "JC1") (pin "3") (pinfunction "3_3") (pintype "passive"))
      (node (ref "U$2") (pin "CC1") (pinfunction "1_CC1") (pintype "bidirectional"))
    )
    (net (code "1335") (name "Net-(U$2C-1)") (class "Default")
      (node (ref "JA1") (pin "2") (pinfunction "2_2") (pintype "passive"))
      (node (ref "U$2") (pin "AB1") (pinfunction "1_AB1") (pintype "bidirectional"))
    )
    (net (code "1336") (name "Net-(U$2CE-1)") (class "Default")
      (node (ref "JC1") (pin "6") (pinfunction "6_6") (pintype "passive"))
      (node (ref "U$2") (pin "CF1") (pinfunction "1_CF1") (pintype "bidirectional"))
    )
    (net (code "1337") (name "Net-(U$2CF-1)") (class "Default")
      (node (ref "JC2") (pin "6") (pinfunction "6_6") (pintype "passive"))
      (node (ref "U$2") (pin "CF2") (pinfunction "1_CF2") (pintype "bidirectional"))
    )
    (net (code "1338") (name "Net-(U$2CQ-1)") (class "Default")
      (node (ref "JC1") (pin "12") (pinfunction "12_12") (pintype "passive"))
      (node (ref "U$2") (pin "CN1") (pinfunction "1_CN1") (pintype "bidirectional"))
    )
    (net (code "1339") (name "Net-(U$2CR-1)") (class "Default")
      (node (ref "JC2") (pin "12") (pinfunction "12_12") (pintype "passive"))
      (node (ref "U$2") (pin "CN2") (pinfunction "1_CN2") (pintype "bidirectional"))
    )
    (net (code "1340") (name "Net-(U$2CZ-1)") (class "Default")
      (node (ref "JC2") (pin "16") (pinfunction "16_16") (pintype "passive"))
      (node (ref "U$2") (pin "CT2") (pinfunction "1_CT2") (pintype "bidirectional"))
    )
    (net (code "1341") (name "Net-(U$2D-1)") (class "Default")
      (node (ref "JA2") (pin "2") (pinfunction "2_2") (pintype "passive"))
      (node (ref "U$2") (pin "AB2") (pinfunction "1_AB2") (pintype "bidirectional"))
    )
    (net (code "1342") (name "Net-(U$2DE-1)") (class "Default")
      (node (ref "JD1") (pin "1") (pinfunction "1_1") (pintype "passive"))
      (node (ref "U$2") (pin "DA1") (pinfunction "1_DA1") (pintype "bidirectional"))
    )
    (net (code "1343") (name "Net-(U$2DG-1)") (class "Default")
      (node (ref "JD1") (pin "2") (pinfunction "2_2") (pintype "passive"))
      (node (ref "U$2") (pin "DB1") (pinfunction "1_DB1") (pintype "bidirectional"))
    )
    (net (code "1344") (name "Net-(U$2DH-1)") (class "Default")
      (node (ref "JD2") (pin "2") (pinfunction "2_2") (pintype "passive"))
      (node (ref "U$2") (pin "DB2") (pinfunction "1_DB2") (pintype "bidirectional"))
    )
    (net (code "1345") (name "Net-(U$2DI-1)") (class "Default")
      (node (ref "JD1") (pin "3") (pinfunction "3_3") (pintype "passive"))
      (node (ref "U$2") (pin "DC1") (pinfunction "1_DC1") (pintype "bidirectional"))
    )
    (net (code "1346") (name "Net-(U$2DO-1)") (class "Default")
      (node (ref "JD1") (pin "6") (pinfunction "6_6") (pintype "passive"))
      (node (ref "U$2") (pin "DF1") (pinfunction "1_DF1") (pintype "bidirectional"))
    )
    (net (code "1347") (name "Net-(U$2DP-1)") (class "Default")
      (node (ref "JD2") (pin "6") (pinfunction "6_6") (pintype "passive"))
      (node (ref "U$2") (pin "DF2") (pinfunction "1_DF2") (pintype "bidirectional"))
    )
    (net (code "1348") (name "Net-(U$2E-1)") (class "Default")
      (node (ref "JA1") (pin "3") (pinfunction "3_3") (pintype "passive"))
      (node (ref "U$2") (pin "AC1") (pinfunction "1_AC1") (pintype "bidirectional"))
    )
    (net (code "1349") (name "Net-(U$2EA-1)") (class "Default")
      (node (ref "JD1") (pin "12") (pinfunction "12_12") (pintype "passive"))
      (node (ref "U$2") (pin "DN1") (pinfunction "1_DN1") (pintype "bidirectional"))
    )
    (net (code "1350") (name "Net-(U$2EB-1)") (class "Default")
      (node (ref "JD2") (pin "12") (pinfunction "12_12") (pintype "passive"))
      (node (ref "U$2") (pin "DN2") (pinfunction "1_DN2") (pintype "bidirectional"))
    )
    (net (code "1351") (name "Net-(U$2EJ-1)") (class "Default")
      (node (ref "JD2") (pin "16") (pinfunction "16_16") (pintype "passive"))
      (node (ref "U$2") (pin "DT2") (pinfunction "1_DT2") (pintype "bidirectional"))
    )
    (net (code "1352") (name "Net-(U$2K-1)") (class "Default")
      (node (ref "JA1") (pin "6") (pinfunction "6_6") (pintype "passive"))
      (node (ref "U$2") (pin "AF1") (pinfunction "1_AF1") (pintype "bidirectional"))
    )
    (net (code "1353") (name "Net-(U$2L-1)") (class "Default")
      (node (ref "JA2") (pin "6") (pinfunction "6_6") (pintype "passive"))
      (node (ref "U$2") (pin "AF2") (pinfunction "1_AF2") (pintype "bidirectional"))
    )
    (net (code "1354") (name "Net-(U$2W-1)") (class "Default")
      (node (ref "JA1") (pin "12") (pinfunction "12_12") (pintype "passive"))
      (node (ref "U$2") (pin "AN1") (pinfunction "1_AN1") (pintype "bidirectional"))
    )
    (net (code "1355") (name "Net-(U$2X-1)") (class "Default")
      (node (ref "JA2") (pin "12") (pinfunction "12_12") (pintype "passive"))
      (node (ref "U$2") (pin "AN2") (pinfunction "1_AN2") (pintype "bidirectional"))
    )
    (net (code "1356") (name "POWER_OK") (class "Default")
      (node (ref "JB2") (pin "18") (pinfunction "18_18") (pintype "passive"))
      (node (ref "U$2") (pin "BV2") (pinfunction "1_BV2") (pintype "bidirectional"))
    )
    (net (code "1357") (name "PULSE_LA") (class "Default")
      (node (ref "JD2") (pin "14") (pinfunction "14_14") (pintype "passive"))
      (node (ref "U$2") (pin "DR2") (pinfunction "1_DR2") (pintype "bidirectional"))
    )
    (net (code "1358") (name "RETURN") (class "Default")
      (node (ref "JA2") (pin "14") (pinfunction "14_14") (pintype "passive"))
      (node (ref "U$2") (pin "AR2") (pinfunction "1_AR2") (pintype "bidirectional"))
    )
    (net (code "1359") (name "SOURCE") (class "Default")
      (node (ref "JA2") (pin "10") (pinfunction "10_10") (pintype "passive"))
      (node (ref "U$2") (pin "AL2") (pinfunction "1_AL2") (pintype "bidirectional"))
    )
    (net (code "1360") (name "STROBE") (class "Default")
      (node (ref "JA2") (pin "11") (pinfunction "11_11") (pintype "passive"))
      (node (ref "U$2") (pin "AM2") (pinfunction "1_AM2") (pintype "bidirectional"))
    )
    (net (code "1361") (name "SWITCH") (class "Default")
      (node (ref "JD2") (pin "18") (pinfunction "18_18") (pintype "passive"))
      (node (ref "U$2") (pin "DV2") (pinfunction "1_DV2") (pintype "bidirectional"))
    )
    (net (code "1362") (name "TP1") (class "Default")
      (node (ref "JC2") (pin "4") (pinfunction "4_4") (pintype "passive"))
      (node (ref "U$2") (pin "CD2") (pinfunction "1_CD2") (pintype "bidirectional"))
    )
    (net (code "1363") (name "TP2") (class "Default")
      (node (ref "JC2") (pin "5") (pinfunction "5_5") (pintype "passive"))
      (node (ref "U$2") (pin "CE2") (pinfunction "1_CE2") (pintype "bidirectional"))
    )
    (net (code "1364") (name "TP3") (class "Default")
      (node (ref "JC2") (pin "7") (pinfunction "7_7") (pintype "passive"))
      (node (ref "U$2") (pin "CH2") (pinfunction "1_CH2") (pintype "bidirectional"))
    )
    (net (code "1365") (name "TP4") (class "Default")
      (node (ref "JC2") (pin "8") (pinfunction "8_8") (pintype "passive"))
      (node (ref "U$2") (pin "CJ2") (pinfunction "1_CJ2") (pintype "bidirectional"))
    )
    (net (code "1366") (name "VCC") (class "Default")
      (node (ref "C1") (pin "+") (pinfunction "+_+") (pintype "passive"))
      (node (ref "C10") (pin "1") (pinfunction "1_1") (pintype "passive"))
      (node (ref "C100") (pin "1") (pinfunction "1_1") (pintype "passive"))
      (node (ref "C101") (pin "+") (pinfunction "+_+") (pintype "passive"))
      (node (ref "C102") (pin "1") (pinfunction "1_1") (pintype "passive"))
      (node (ref "C103") (pin "+") (pinfunction "+_+") (pintype "passive"))
      (node (ref "C104") (pin "1") (pinfunction "1_1") (pintype "passive"))
      (node (ref "C105") (pin "+") (pinfunction "+_+") (pintype "passive"))
      (node (ref "C106") (pin "1") (pinfunction "1_1") (pintype "passive"))
      (node (ref "C107") (pin "+") (pinfunction "+_+") (pintype "passive"))
      (node (ref "C108") (pin "1") (pinfunction "1_1") (pintype "passive"))
      (node (ref "C109") (pin "+") (pinfunction "+_+") (pintype "passive"))
      (node (ref "C11") (pin "+") (pinfunction "+_+") (pintype "passive"))
      (node (ref "C110") (pin "1") (pinfunction "1_1") (pintype "passive"))
      (node (ref "C111") (pin "+") (pinfunction "+_+") (pintype "passive"))
      (node (ref "C112") (pin "1") (pinfunction "1_1") (pintype "passive"))
      (node (ref "C113") (pin "+") (pinfunction "+_+") (pintype "passive"))
      (node (ref "C114") (pin "1") (pinfunction "1_1") (pintype "passive"))
      (node (ref "C115") (pin "+") (pinfunction "+_+") (pintype "passive"))
      (node (ref "C116") (pin "1") (pinfunction "1_1") (pintype "passive"))
      (node (ref "C117") (pin "+") (pinfunction "+_+") (pintype "passive"))
      (node (ref "C118") (pin "1") (pinfunction "1_1") (pintype "passive"))
      (node (ref "C119") (pin "+") (pinfunction "+_+") (pintype "passive"))
      (node (ref "C12") (pin "1") (pinfunction "1_1") (pintype "passive"))
      (node (ref "C120") (pin "1") (pinfunction "1_1") (pintype "passive"))
      (node (ref "C121") (pin "1") (pinfunction "1_1") (pintype "passive"))
      (node (ref "C122") (pin "1") (pinfunction "1_1") (pintype "passive"))
      (node (ref "C123") (pin "1") (pinfunction "1_1") (pintype "passive"))
      (node (ref "C124") (pin "1") (pinfunction "1_1") (pintype "passive"))
      (node (ref "C125") (pin "1") (pinfunction "1_1") (pintype "passive"))
      (node (ref "C126") (pin "1") (pinfunction "1_1") (pintype "passive"))
      (node (ref "C127") (pin "1") (pinfunction "1_1") (pintype "passive"))
      (node (ref "C128") (pin "1") (pinfunction "1_1") (pintype "passive"))
      (node (ref "C129") (pin "1") (pinfunction "1_1") (pintype "passive"))
      (node (ref "C13") (pin "+") (pinfunction "+_+") (pintype "passive"))
      (node (ref "C130") (pin "1") (pinfunction "1_1") (pintype "passive"))
      (node (ref "C131") (pin "1") (pinfunction "1_1") (pintype "passive"))
      (node (ref "C132") (pin "1") (pinfunction "1_1") (pintype "passive"))
      (node (ref "C133") (pin "1") (pinfunction "1_1") (pintype "passive"))
      (node (ref "C134") (pin "1") (pinfunction "1_1") (pintype "passive"))
      (node (ref "C135") (pin "1") (pinfunction "1_1") (pintype "passive"))
      (node (ref "C136") (pin "1") (pinfunction "1_1") (pintype "passive"))
      (node (ref "C14") (pin "1") (pinfunction "1_1") (pintype "passive"))
      (node (ref "C15") (pin "+") (pinfunction "+_+") (pintype "passive"))
      (node (ref "C16") (pin "1") (pinfunction "1_1") (pintype "passive"))
      (node (ref "C17") (pin "+") (pinfunction "+_+") (pintype "passive"))
      (node (ref "C18") (pin "1") (pinfunction "1_1") (pintype "passive"))
      (node (ref "C19") (pin "+") (pinfunction "+_+") (pintype "passive"))
      (node (ref "C2") (pin "1") (pinfunction "1_1") (pintype "passive"))
      (node (ref "C20") (pin "1") (pinfunction "1_1") (pintype "passive"))
      (node (ref "C21") (pin "+") (pinfunction "+_+") (pintype "passive"))
      (node (ref "C22") (pin "1") (pinfunction "1_1") (pintype "passive"))
      (node (ref "C23") (pin "+") (pinfunction "+_+") (pintype "passive"))
      (node (ref "C24") (pin "1") (pinfunction "1_1") (pintype "passive"))
      (node (ref "C25") (pin "+") (pinfunction "+_+") (pintype "passive"))
      (node (ref "C26") (pin "1") (pinfunction "1_1") (pintype "passive"))
      (node (ref "C27") (pin "+") (pinfunction "+_+") (pintype "passive"))
      (node (ref "C28") (pin "1") (pinfunction "1_1") (pintype "passive"))
      (node (ref "C29") (pin "+") (pinfunction "+_+") (pintype "passive"))
      (node (ref "C3") (pin "+") (pinfunction "+_+") (pintype "passive"))
      (node (ref "C30") (pin "1") (pinfunction "1_1") (pintype "passive"))
      (node (ref "C31") (pin "+") (pinfunction "+_+") (pintype "passive"))
      (node (ref "C32") (pin "1") (pinfunction "1_1") (pintype "passive"))
      (node (ref "C33") (pin "+") (pinfunction "+_+") (pintype "passive"))
      (node (ref "C34") (pin "1") (pinfunction "1_1") (pintype "passive"))
      (node (ref "C35") (pin "+") (pinfunction "+_+") (pintype "passive"))
      (node (ref "C36") (pin "1") (pinfunction "1_1") (pintype "passive"))
      (node (ref "C37") (pin "+") (pinfunction "+_+") (pintype "passive"))
      (node (ref "C38") (pin "1") (pinfunction "1_1") (pintype "passive"))
      (node (ref "C39") (pin "+") (pinfunction "+_+") (pintype "passive"))
      (node (ref "C4") (pin "1") (pinfunction "1_1") (pintype "passive"))
      (node (ref "C40") (pin "1") (pinfunction "1_1") (pintype "passive"))
      (node (ref "C41") (pin "+") (pinfunction "+_+") (pintype "passive"))
      (node (ref "C42") (pin "1") (pinfunction "1_1") (pintype "passive"))
      (node (ref "C43") (pin "+") (pinfunction "+_+") (pintype "passive"))
      (node (ref "C44") (pin "1") (pinfunction "1_1") (pintype "passive"))
      (node (ref "C45") (pin "+") (pinfunction "+_+") (pintype "passive"))
      (node (ref "C46") (pin "1") (pinfunction "1_1") (pintype "passive"))
      (node (ref "C47") (pin "+") (pinfunction "+_+") (pintype "passive"))
      (node (ref "C48") (pin "1") (pinfunction "1_1") (pintype "passive"))
      (node (ref "C49") (pin "+") (pinfunction "+_+") (pintype "passive"))
      (node (ref "C5") (pin "+") (pinfunction "+_+") (pintype "passive"))
      (node (ref "C50") (pin "1") (pinfunction "1_1") (pintype "passive"))
      (node (ref "C51") (pin "+") (pinfunction "+_+") (pintype "passive"))
      (node (ref "C52") (pin "1") (pinfunction "1_1") (pintype "passive"))
      (node (ref "C53") (pin "+") (pinfunction "+_+") (pintype "passive"))
      (node (ref "C54") (pin "1") (pinfunction "1_1") (pintype "passive"))
      (node (ref "C55") (pin "+") (pinfunction "+_+") (pintype "passive"))
      (node (ref "C56") (pin "1") (pinfunction "1_1") (pintype "passive"))
      (node (ref "C57") (pin "+") (pinfunction "+_+") (pintype "passive"))
      (node (ref "C58") (pin "1") (pinfunction "1_1") (pintype "passive"))
      (node (ref "C59") (pin "+") (pinfunction "+_+") (pintype "passive"))
      (node (ref "C6") (pin "1") (pinfunction "1_1") (pintype "passive"))
      (node (ref "C60") (pin "1") (pinfunction "1_1") (pintype "passive"))
      (node (ref "C61") (pin "+") (pinfunction "+_+") (pintype "passive"))
      (node (ref "C62") (pin "1") (pinfunction "1_1") (pintype "passive"))
      (node (ref "C63") (pin "+") (pinfunction "+_+") (pintype "passive"))
      (node (ref "C64") (pin "1") (pinfunction "1_1") (pintype "passive"))
      (node (ref "C65") (pin "+") (pinfunction "+_+") (pintype "passive"))
      (node (ref "C66") (pin "1") (pinfunction "1_1") (pintype "passive"))
      (node (ref "C67") (pin "+") (pinfunction "+_+") (pintype "passive"))
      (node (ref "C68") (pin "1") (pinfunction "1_1") (pintype "passive"))
      (node (ref "C69") (pin "+") (pinfunction "+_+") (pintype "passive"))
      (node (ref "C7") (pin "+") (pinfunction "+_+") (pintype "passive"))
      (node (ref "C70") (pin "1") (pinfunction "1_1") (pintype "passive"))
      (node (ref "C71") (pin "+") (pinfunction "+_+") (pintype "passive"))
      (node (ref "C72") (pin "1") (pinfunction "1_1") (pintype "passive"))
      (node (ref "C73") (pin "+") (pinfunction "+_+") (pintype "passive"))
      (node (ref "C74") (pin "1") (pinfunction "1_1") (pintype "passive"))
      (node (ref "C75") (pin "+") (pinfunction "+_+") (pintype "passive"))
      (node (ref "C76") (pin "1") (pinfunction "1_1") (pintype "passive"))
      (node (ref "C77") (pin "+") (pinfunction "+_+") (pintype "passive"))
      (node (ref "C78") (pin "1") (pinfunction "1_1") (pintype "passive"))
      (node (ref "C79") (pin "+") (pinfunction "+_+") (pintype "passive"))
      (node (ref "C8") (pin "1") (pinfunction "1_1") (pintype "passive"))
      (node (ref "C80") (pin "1") (pinfunction "1_1") (pintype "passive"))
      (node (ref "C81") (pin "+") (pinfunction "+_+") (pintype "passive"))
      (node (ref "C82") (pin "1") (pinfunction "1_1") (pintype "passive"))
      (node (ref "C83") (pin "+") (pinfunction "+_+") (pintype "passive"))
      (node (ref "C84") (pin "1") (pinfunction "1_1") (pintype "passive"))
      (node (ref "C85") (pin "+") (pinfunction "+_+") (pintype "passive"))
      (node (ref "C86") (pin "1") (pinfunction "1_1") (pintype "passive"))
      (node (ref "C87") (pin "+") (pinfunction "+_+") (pintype "passive"))
      (node (ref "C88") (pin "1") (pinfunction "1_1") (pintype "passive"))
      (node (ref "C89") (pin "+") (pinfunction "+_+") (pintype "passive"))
      (node (ref "C9") (pin "+") (pinfunction "+_+") (pintype "passive"))
      (node (ref "C90") (pin "1") (pinfunction "1_1") (pintype "passive"))
      (node (ref "C91") (pin "+") (pinfunction "+_+") (pintype "passive"))
      (node (ref "C92") (pin "1") (pinfunction "1_1") (pintype "passive"))
      (node (ref "C93") (pin "+") (pinfunction "+_+") (pintype "passive"))
      (node (ref "C94") (pin "1") (pinfunction "1_1") (pintype "passive"))
      (node (ref "C95") (pin "+") (pinfunction "+_+") (pintype "passive"))
      (node (ref "C96") (pin "1") (pinfunction "1_1") (pintype "passive"))
      (node (ref "C97") (pin "+") (pinfunction "+_+") (pintype "passive"))
      (node (ref "C98") (pin "1") (pinfunction "1_1") (pintype "passive"))
      (node (ref "C99") (pin "+") (pinfunction "+_+") (pintype "passive"))
      (node (ref "JA2") (pin "1") (pinfunction "1_1") (pintype "passive"))
      (node (ref "JB2") (pin "1") (pinfunction "1_1") (pintype "passive"))
      (node (ref "JC2") (pin "1") (pinfunction "1_1") (pintype "passive"))
      (node (ref "U$2") (pin "AA2") (pinfunction "1_AA2") (pintype "bidirectional"))
      (node (ref "U$2") (pin "BA2") (pinfunction "1_BA2") (pintype "bidirectional"))
      (node (ref "U$2") (pin "CA2") (pinfunction "1_CA2") (pintype "bidirectional"))
    )
    (net (code "1367") (name "WRITE") (class "Default")
      (node (ref "JA2") (pin "15") (pinfunction "15_15") (pintype "passive"))
      (node (ref "U$2") (pin "AS2") (pinfunction "1_AS2") (pintype "bidirectional"))
    )
    (net (code "1368") (name "~{BREAK_CYCLE}") (class "Default")
      (node (ref "JB2") (pin "10") (pinfunction "10_10") (pintype "passive"))
      (node (ref "U$2") (pin "BL2") (pinfunction "1_BL2") (pintype "bidirectional"))
    )
    (net (code "1369") (name "~{BRK_DATA_CONT}") (class "Default")
      (node (ref "JB2") (pin "9") (pinfunction "9_9") (pintype "passive"))
      (node (ref "U$2") (pin "BK2") (pinfunction "1_BK2") (pintype "bidirectional"))
    )
    (net (code "1370") (name "~{BRK_IN_PROG}") (class "Default")
      (node (ref "JB2") (pin "5") (pinfunction "5_5") (pintype "passive"))
      (node (ref "U$2") (pin "BE2") (pinfunction "1_BE2") (pintype "bidirectional"))
    )
    (net (code "1371") (name "~{BUS_STROBE}") (class "Default")
      (node (ref "JC1") (pin "9") (pinfunction "9_9") (pintype "passive"))
      (node (ref "U$2") (pin "CK1") (pinfunction "1_CK1") (pintype "bidirectional"))
    )
    (net (code "1372") (name "~{C0}") (class "Default")
      (node (ref "JC1") (pin "5") (pinfunction "5_5") (pintype "passive"))
      (node (ref "U$2") (pin "CE1") (pinfunction "1_CE1") (pintype "bidirectional"))
    )
    (net (code "1373") (name "~{C1}") (class "Default")
      (node (ref "JC1") (pin "7") (pinfunction "7_7") (pintype "passive"))
      (node (ref "U$2") (pin "CH1") (pinfunction "1_CH1") (pintype "bidirectional"))
    )
    (net (code "1374") (name "~{C2}") (class "Default")
      (node (ref "JC1") (pin "8") (pinfunction "8_8") (pintype "passive"))
      (node (ref "U$2") (pin "CJ1") (pinfunction "1_CJ1") (pintype "bidirectional"))
    )
    (net (code "1375") (name "~{CPMA_DISABLE}") (class "Default")
      (node (ref "JC1") (pin "17") (pinfunction "17_17") (pintype "passive"))
      (node (ref "U$2") (pin "CU1") (pinfunction "1_CU1") (pintype "bidirectional"))
    )
    (net (code "1376") (name "~{DATA0}") (class "Default")
      (node (ref "JA1") (pin "14") (pinfunction "14_14") (pintype "passive"))
      (node (ref "U$2") (pin "AR1") (pinfunction "1_AR1") (pintype "bidirectional"))
    )
    (net (code "1377") (name "~{DATA1}") (class "Default")
      (node (ref "JA1") (pin "15") (pinfunction "15_15") (pintype "passive"))
      (node (ref "U$2") (pin "AS1") (pinfunction "1_AS1") (pintype "bidirectional"))
    )
    (net (code "1378") (name "~{DATA2}") (class "Default")
      (node (ref "JA1") (pin "17") (pinfunction "17_17") (pintype "passive"))
      (node (ref "U$2") (pin "AU1") (pinfunction "1_AU1") (pintype "bidirectional"))
    )
    (net (code "1379") (name "~{DATA3}") (class "Default")
      (node (ref "JA1") (pin "18") (pinfunction "18_18") (pintype "passive"))
      (node (ref "U$2") (pin "AV1") (pinfunction "1_AV1") (pintype "bidirectional"))
    )
    (net (code "1380") (name "~{DATA4}") (class "Default")
      (node (ref "JB1") (pin "14") (pinfunction "14_14") (pintype "passive"))
      (node (ref "U$2") (pin "BR1") (pinfunction "1_BR1") (pintype "bidirectional"))
    )
    (net (code "1381") (name "~{DATA5}") (class "Default")
      (node (ref "JB1") (pin "15") (pinfunction "15_15") (pintype "passive"))
      (node (ref "U$2") (pin "BS1") (pinfunction "1_BS1") (pintype "bidirectional"))
    )
    (net (code "1382") (name "~{DATA6}") (class "Default")
      (node (ref "JB1") (pin "17") (pinfunction "17_17") (pintype "passive"))
      (node (ref "U$2") (pin "BU1") (pinfunction "1_BU1") (pintype "bidirectional"))
    )
    (net (code "1383") (name "~{DATA7}") (class "Default")
      (node (ref "JB1") (pin "18") (pinfunction "18_18") (pintype "passive"))
      (node (ref "U$2") (pin "BV1") (pinfunction "1_BV1") (pintype "bidirectional"))
    )
    (net (code "1384") (name "~{DATA8}") (class "Default")
      (node (ref "JD1") (pin "14") (pinfunction "14_14") (pintype "passive"))
      (node (ref "U$2") (pin "DR1") (pinfunction "1_DR1") (pintype "bidirectional"))
    )
    (net (code "1385") (name "~{DATA9}") (class "Default")
      (node (ref "JD1") (pin "15") (pinfunction "15_15") (pintype "passive"))
      (node (ref "U$2") (pin "DS1") (pinfunction "1_DS1") (pintype "bidirectional"))
    )
    (net (code "1386") (name "~{DATA10}") (class "Default")
      (node (ref "JD1") (pin "17") (pinfunction "17_17") (pintype "passive"))
      (node (ref "U$2") (pin "DU1") (pinfunction "1_DU1") (pintype "bidirectional"))
    )
    (net (code "1387") (name "~{DATA11}") (class "Default")
      (node (ref "JD1") (pin "18") (pinfunction "18_18") (pintype "passive"))
      (node (ref "U$2") (pin "DV1") (pinfunction "1_DV1") (pintype "bidirectional"))
    )
    (net (code "1388") (name "~{D}") (class "Default")
      (node (ref "JD2") (pin "9") (pinfunction "9_9") (pintype "passive"))
      (node (ref "U$2") (pin "DK2") (pinfunction "1_DK2") (pintype "bidirectional"))
    )
    (net (code "1389") (name "~{EMA0}") (class "Default")
      (node (ref "JA2") (pin "4") (pinfunction "4_4") (pintype "passive"))
      (node (ref "U$2") (pin "AD2") (pinfunction "1_AD2") (pintype "bidirectional"))
    )
    (net (code "1390") (name "~{EMA1}") (class "Default")
      (node (ref "JA2") (pin "5") (pinfunction "5_5") (pintype "passive"))
      (node (ref "U$2") (pin "AE2") (pinfunction "1_AE2") (pintype "bidirectional"))
    )
    (net (code "1391") (name "~{EMA2}") (class "Default")
      (node (ref "JA2") (pin "7") (pinfunction "7_7") (pintype "passive"))
      (node (ref "U$2") (pin "AH2") (pinfunction "1_AH2") (pintype "bidirectional"))
    )
    (net (code "1392") (name "~{E}") (class "Default")
      (node (ref "JD2") (pin "10") (pinfunction "10_10") (pintype "passive"))
      (node (ref "U$2") (pin "DL2") (pinfunction "1_DL2") (pintype "bidirectional"))
    )
    (net (code "1393") (name "~{FSET}") (class "Default")
      (node (ref "JD2") (pin "13") (pinfunction "13_13") (pintype "passive"))
      (node (ref "U$2") (pin "DP2") (pinfunction "1_DP2") (pintype "bidirectional"))
    )
    (net (code "1394") (name "~{F}") (class "Default")
      (node (ref "JD2") (pin "8") (pinfunction "8_8") (pintype "passive"))
      (node (ref "U$2") (pin "DJ2") (pinfunction "1_DJ2") (pintype "bidirectional"))
    )
    (net (code "1395") (name "~{IND1}") (class "Default")
      (node (ref "JC2") (pin "17") (pinfunction "17_17") (pintype "passive"))
      (node (ref "U$2") (pin "CU2") (pinfunction "1_CU2") (pintype "bidirectional"))
    )
    (net (code "1396") (name "~{IND2}") (class "Default")
      (node (ref "JC2") (pin "18") (pinfunction "18_18") (pintype "passive"))
      (node (ref "U$2") (pin "CV2") (pinfunction "1_CV2") (pintype "bidirectional"))
    )
    (net (code "1397") (name "~{INTERNAL_IO}") (class "Default")
      (node (ref "JC1") (pin "10") (pinfunction "10_10") (pintype "passive"))
      (node (ref "U$2") (pin "CL1") (pinfunction "1_CL1") (pintype "bidirectional"))
    )
    (net (code "1398") (name "~{INT_RQST}") (class "Default")
      (node (ref "JC1") (pin "13") (pinfunction "13_13") (pintype "passive"))
      (node (ref "U$2") (pin "CP1") (pinfunction "1_CP1") (pintype "bidirectional"))
    )
    (net (code "1399") (name "~{IO_PAUSE}") (class "Default")
      (node (ref "JC1") (pin "4") (pinfunction "4_4") (pintype "passive"))
      (node (ref "U$2") (pin "CD1") (pinfunction "1_CD1") (pintype "bidirectional"))
    )
    (net (code "1400") (name "~{IR0}") (class "Default")
      (node (ref "JD2") (pin "4") (pinfunction "4_4") (pintype "passive"))
      (node (ref "U$2") (pin "DD2") (pinfunction "1_DD2") (pintype "bidirectional"))
    )
    (net (code "1401") (name "~{IR1}") (class "Default")
      (node (ref "JD2") (pin "5") (pinfunction "5_5") (pintype "passive"))
      (node (ref "U$2") (pin "DE2") (pinfunction "1_DE2") (pintype "bidirectional"))
    )
    (net (code "1402") (name "~{IR2}") (class "Default")
      (node (ref "JD2") (pin "7") (pinfunction "7_7") (pintype "passive"))
      (node (ref "U$2") (pin "DH2") (pinfunction "1_DH2") (pintype "bidirectional"))
    )
    (net (code "1403") (name "~{KEY_CONT}") (class "Default")
      (node (ref "JD2") (pin "17") (pinfunction "17_17") (pintype "passive"))
      (node (ref "U$2") (pin "DU2") (pinfunction "1_DU2") (pintype "bidirectional"))
    )
    (net (code "1404") (name "~{LA_ENABLE}") (class "Default")
      (node (ref "JB2") (pin "11") (pinfunction "11_11") (pintype "passive"))
      (node (ref "U$2") (pin "BM2") (pinfunction "1_BM2") (pintype "bidirectional"))
    )
    (net (code "1405") (name "~{LINK_DATA}") (class "Default")
      (node (ref "JC2") (pin "14") (pinfunction "14_14") (pintype "passive"))
      (node (ref "U$2") (pin "CR2") (pinfunction "1_CR2") (pintype "bidirectional"))
    )
    (net (code "1406") (name "~{LINK_LOAD}") (class "Default")
      (node (ref "JC2") (pin "15") (pinfunction "15_15") (pintype "passive"))
      (node (ref "U$2") (pin "CS2") (pinfunction "1_CS2") (pintype "bidirectional"))
    )
    (net (code "1407") (name "~{LINK}") (class "Default")
      (node (ref "JA2") (pin "18") (pinfunction "18_18") (pintype "passive"))
      (node (ref "U$2") (pin "AV2") (pinfunction "1_AV2") (pintype "bidirectional"))
    )
    (net (code "1408") (name "~{LOAD_CONT}") (class "Default")
      (node (ref "JB2") (pin "7") (pinfunction "7_7") (pintype "passive"))
      (node (ref "U$2") (pin "BH2") (pinfunction "1_BH2") (pintype "bidirectional"))
    )
    (net (code "1409") (name "~{MA00}") (class "Default")
      (node (ref "JA1") (pin "4") (pinfunction "4_4") (pintype "passive"))
      (node (ref "U$2") (pin "AD1") (pinfunction "1_AD1") (pintype "bidirectional"))
    )
    (net (code "1410") (name "~{MA01}") (class "Default")
      (node (ref "JA1") (pin "5") (pinfunction "5_5") (pintype "passive"))
      (node (ref "U$2") (pin "AE1") (pinfunction "1_AE1") (pintype "bidirectional"))
    )
    (net (code "1411") (name "~{MA02}") (class "Default")
      (node (ref "JA1") (pin "7") (pinfunction "7_7") (pintype "passive"))
      (node (ref "U$2") (pin "AH1") (pinfunction "1_AH1") (pintype "bidirectional"))
    )
    (net (code "1412") (name "~{MA03}") (class "Default")
      (node (ref "JA1") (pin "8") (pinfunction "8_8") (pintype "passive"))
      (node (ref "U$2") (pin "AJ1") (pinfunction "1_AJ1") (pintype "bidirectional"))
    )
    (net (code "1413") (name "~{MA04}") (class "Default")
      (node (ref "JB1") (pin "4") (pinfunction "4_4") (pintype "passive"))
      (node (ref "U$2") (pin "BD1") (pinfunction "1_BD1") (pintype "bidirectional"))
    )
    (net (code "1414") (name "~{MA05}") (class "Default")
      (node (ref "JB1") (pin "5") (pinfunction "5_5") (pintype "passive"))
      (node (ref "U$2") (pin "BE1") (pinfunction "1_BE1") (pintype "bidirectional"))
    )
    (net (code "1415") (name "~{MA06}") (class "Default")
      (node (ref "JB1") (pin "7") (pinfunction "7_7") (pintype "passive"))
      (node (ref "U$2") (pin "BH1") (pinfunction "1_BH1") (pintype "bidirectional"))
    )
    (net (code "1416") (name "~{MA07}") (class "Default")
      (node (ref "JB1") (pin "8") (pinfunction "8_8") (pintype "passive"))
      (node (ref "U$2") (pin "BJ1") (pinfunction "1_BJ1") (pintype "bidirectional"))
    )
    (net (code "1417") (name "~{MA08}") (class "Default")
      (node (ref "JD1") (pin "4") (pinfunction "4_4") (pintype "passive"))
      (node (ref "U$2") (pin "DD1") (pinfunction "1_DD1") (pintype "bidirectional"))
    )
    (net (code "1418") (name "~{MA09}") (class "Default")
      (node (ref "JD1") (pin "5") (pinfunction "5_5") (pintype "passive"))
      (node (ref "U$2") (pin "DE1") (pinfunction "1_DE1") (pintype "bidirectional"))
    )
    (net (code "1419") (name "~{MA10}") (class "Default")
      (node (ref "JD1") (pin "7") (pinfunction "7_7") (pintype "passive"))
      (node (ref "U$2") (pin "DH1") (pinfunction "1_DH1") (pintype "bidirectional"))
    )
    (net (code "1420") (name "~{MA11}") (class "Default")
      (node (ref "JD1") (pin "8") (pinfunction "8_8") (pintype "passive"))
      (node (ref "U$2") (pin "DJ1") (pinfunction "1_DJ1") (pintype "bidirectional"))
    )
    (net (code "1421") (name "~{MD00}") (class "Default")
      (node (ref "JA1") (pin "9") (pinfunction "9_9") (pintype "passive"))
      (node (ref "U$2") (pin "AK1") (pinfunction "1_AK1") (pintype "bidirectional"))
    )
    (net (code "1422") (name "~{MD01}") (class "Default")
      (node (ref "JA1") (pin "10") (pinfunction "10_10") (pintype "passive"))
      (node (ref "U$2") (pin "AL1") (pinfunction "1_AL1") (pintype "bidirectional"))
    )
    (net (code "1423") (name "~{MD02}") (class "Default")
      (node (ref "JA1") (pin "11") (pinfunction "11_11") (pintype "passive"))
      (node (ref "U$2") (pin "AM1") (pinfunction "1_AM1") (pintype "bidirectional"))
    )
    (net (code "1424") (name "~{MD03}") (class "Default")
      (node (ref "JA1") (pin "13") (pinfunction "13_13") (pintype "passive"))
      (node (ref "U$2") (pin "AP1") (pinfunction "1_AP1") (pintype "bidirectional"))
    )
    (net (code "1425") (name "~{MD04}") (class "Default")
      (node (ref "JB1") (pin "9") (pinfunction "9_9") (pintype "passive"))
      (node (ref "U$2") (pin "BK1") (pinfunction "1_BK1") (pintype "bidirectional"))
    )
    (net (code "1426") (name "~{MD05}") (class "Default")
      (node (ref "JB1") (pin "10") (pinfunction "10_10") (pintype "passive"))
      (node (ref "U$2") (pin "BL1") (pinfunction "1_BL1") (pintype "bidirectional"))
    )
    (net (code "1427") (name "~{MD06}") (class "Default")
      (node (ref "JB1") (pin "11") (pinfunction "11_11") (pintype "passive"))
      (node (ref "U$2") (pin "BM1") (pinfunction "1_BM1") (pintype "bidirectional"))
    )
    (net (code "1428") (name "~{MD07}") (class "Default")
      (node (ref "JB1") (pin "13") (pinfunction "13_13") (pintype "passive"))
      (node (ref "U$2") (pin "BP1") (pinfunction "1_BP1") (pintype "bidirectional"))
    )
    (net (code "1429") (name "~{MD08}") (class "Default")
      (node (ref "JD1") (pin "9") (pinfunction "9_9") (pintype "passive"))
      (node (ref "U$2") (pin "DK1") (pinfunction "1_DK1") (pintype "bidirectional"))
    )
    (net (code "1430") (name "~{MD09}") (class "Default")
      (node (ref "JD1") (pin "10") (pinfunction "10_10") (pintype "passive"))
      (node (ref "U$2") (pin "DL1") (pinfunction "1_DL1") (pintype "bidirectional"))
    )
    (net (code "1431") (name "~{MD10}") (class "Default")
      (node (ref "JD1") (pin "11") (pinfunction "11_11") (pintype "passive"))
      (node (ref "U$2") (pin "DM1") (pinfunction "1_DM1") (pintype "bidirectional"))
    )
    (net (code "1432") (name "~{MD11}") (class "Default")
      (node (ref "JD1") (pin "13") (pinfunction "13_13") (pintype "passive"))
      (node (ref "U$2") (pin "DP1") (pinfunction "1_DP1") (pintype "bidirectional"))
    )
    (net (code "1433") (name "~{MD_DIR}") (class "Default")
      (node (ref "JA2") (pin "9") (pinfunction "9_9") (pintype "passive"))
      (node (ref "U$2") (pin "AK2") (pinfunction "1_AK2") (pintype "bidirectional"))
    )
    (net (code "1434") (name "~{MEM_START}") (class "Default")
      (node (ref "JA2") (pin "8") (pinfunction "8_8") (pintype "passive"))
      (node (ref "U$2") (pin "AJ2") (pinfunction "1_AJ2") (pintype "bidirectional"))
    )
    (net (code "1435") (name "~{MS_DISABLE}") (class "Default")
      (node (ref "JC1") (pin "18") (pinfunction "18_18") (pintype "passive"))
      (node (ref "U$2") (pin "CV1") (pinfunction "1_CV1") (pintype "bidirectional"))
    )
    (net (code "1436") (name "~{NOT_LAST_TR}") (class "Default")
      (node (ref "JC1") (pin "11") (pinfunction "11_11") (pintype "passive"))
      (node (ref "U$2") (pin "CM1") (pinfunction "1_CM1") (pintype "bidirectional"))
    )
    (net (code "1437") (name "~{NTS_STALL}") (class "Default")
      (node (ref "JB2") (pin "14") (pinfunction "14_14") (pintype "passive"))
      (node (ref "U$2") (pin "BR2") (pinfunction "1_BR2") (pintype "bidirectional"))
    )
    (net (code "1438") (name "~{OVERFLOW}") (class "Default")
      (node (ref "JB2") (pin "8") (pinfunction "8_8") (pintype "passive"))
      (node (ref "U$2") (pin "BJ2") (pinfunction "1_BJ2") (pintype "bidirectional"))
    )
    (net (code "1439") (name "~{ROM_ADDR}") (class "Default")
      (node (ref "JA2") (pin "17") (pinfunction "17_17") (pintype "passive"))
      (node (ref "U$2") (pin "AU2") (pinfunction "1_AU2") (pintype "bidirectional"))
    )
    (net (code "1440") (name "~{RUN}") (class "Default")
      (node (ref "JB2") (pin "17") (pinfunction "17_17") (pintype "passive"))
      (node (ref "U$2") (pin "BU2") (pinfunction "1_BU2") (pintype "bidirectional"))
    )
    (net (code "1441") (name "~{SKIP}") (class "Default")
      (node (ref "JC1") (pin "15") (pinfunction "15_15") (pintype "passive"))
      (node (ref "U$2") (pin "CS1") (pinfunction "1_CS1") (pintype "bidirectional"))
    )
    (net (code "1442") (name "~{STOP}") (class "Default")
      (node (ref "JD2") (pin "15") (pinfunction "15_15") (pintype "passive"))
      (node (ref "U$2") (pin "DS2") (pinfunction "1_DS2") (pintype "bidirectional"))
    )
    (net (code "1443") (name "~{TS1}") (class "Default")
      (node (ref "JC2") (pin "9") (pinfunction "9_9") (pintype "passive"))
      (node (ref "U$2") (pin "CK2") (pinfunction "1_CK2") (pintype "bidirectional"))
    )
    (net (code "1444") (name "~{TS2}") (class "Default")
      (node (ref "JC2") (pin "10") (pinfunction "10_10") (pintype "passive"))
      (node (ref "U$2") (pin "CL2") (pinfunction "1_CL2") (pintype "bidirectional"))
    )
    (net (code "1445") (name "~{TS3}") (class "Default")
      (node (ref "JC2") (pin "11") (pinfunction "11_11") (pintype "passive"))
      (node (ref "U$2") (pin "CM2") (pinfunction "1_CM2") (pintype "bidirectional"))
    )
    (net (code "1446") (name "~{TS4}") (class "Default")
      (node (ref "JC2") (pin "13") (pinfunction "13_13") (pintype "passive"))
      (node (ref "U$2") (pin "CP2") (pinfunction "1_CP2") (pintype "bidirectional"))
    )
    (net (code "1447") (name "~{USER_MODE}") (class "Default")
      (node (ref "JD2") (pin "11") (pinfunction "11_11") (pintype "passive"))
      (node (ref "U$2") (pin "DM2") (pinfunction "1_DM2") (pintype "bidirectional"))
    )
  )
)
